# SMPS.net
KiCad netlist of a schematic drawn in Altium Designer
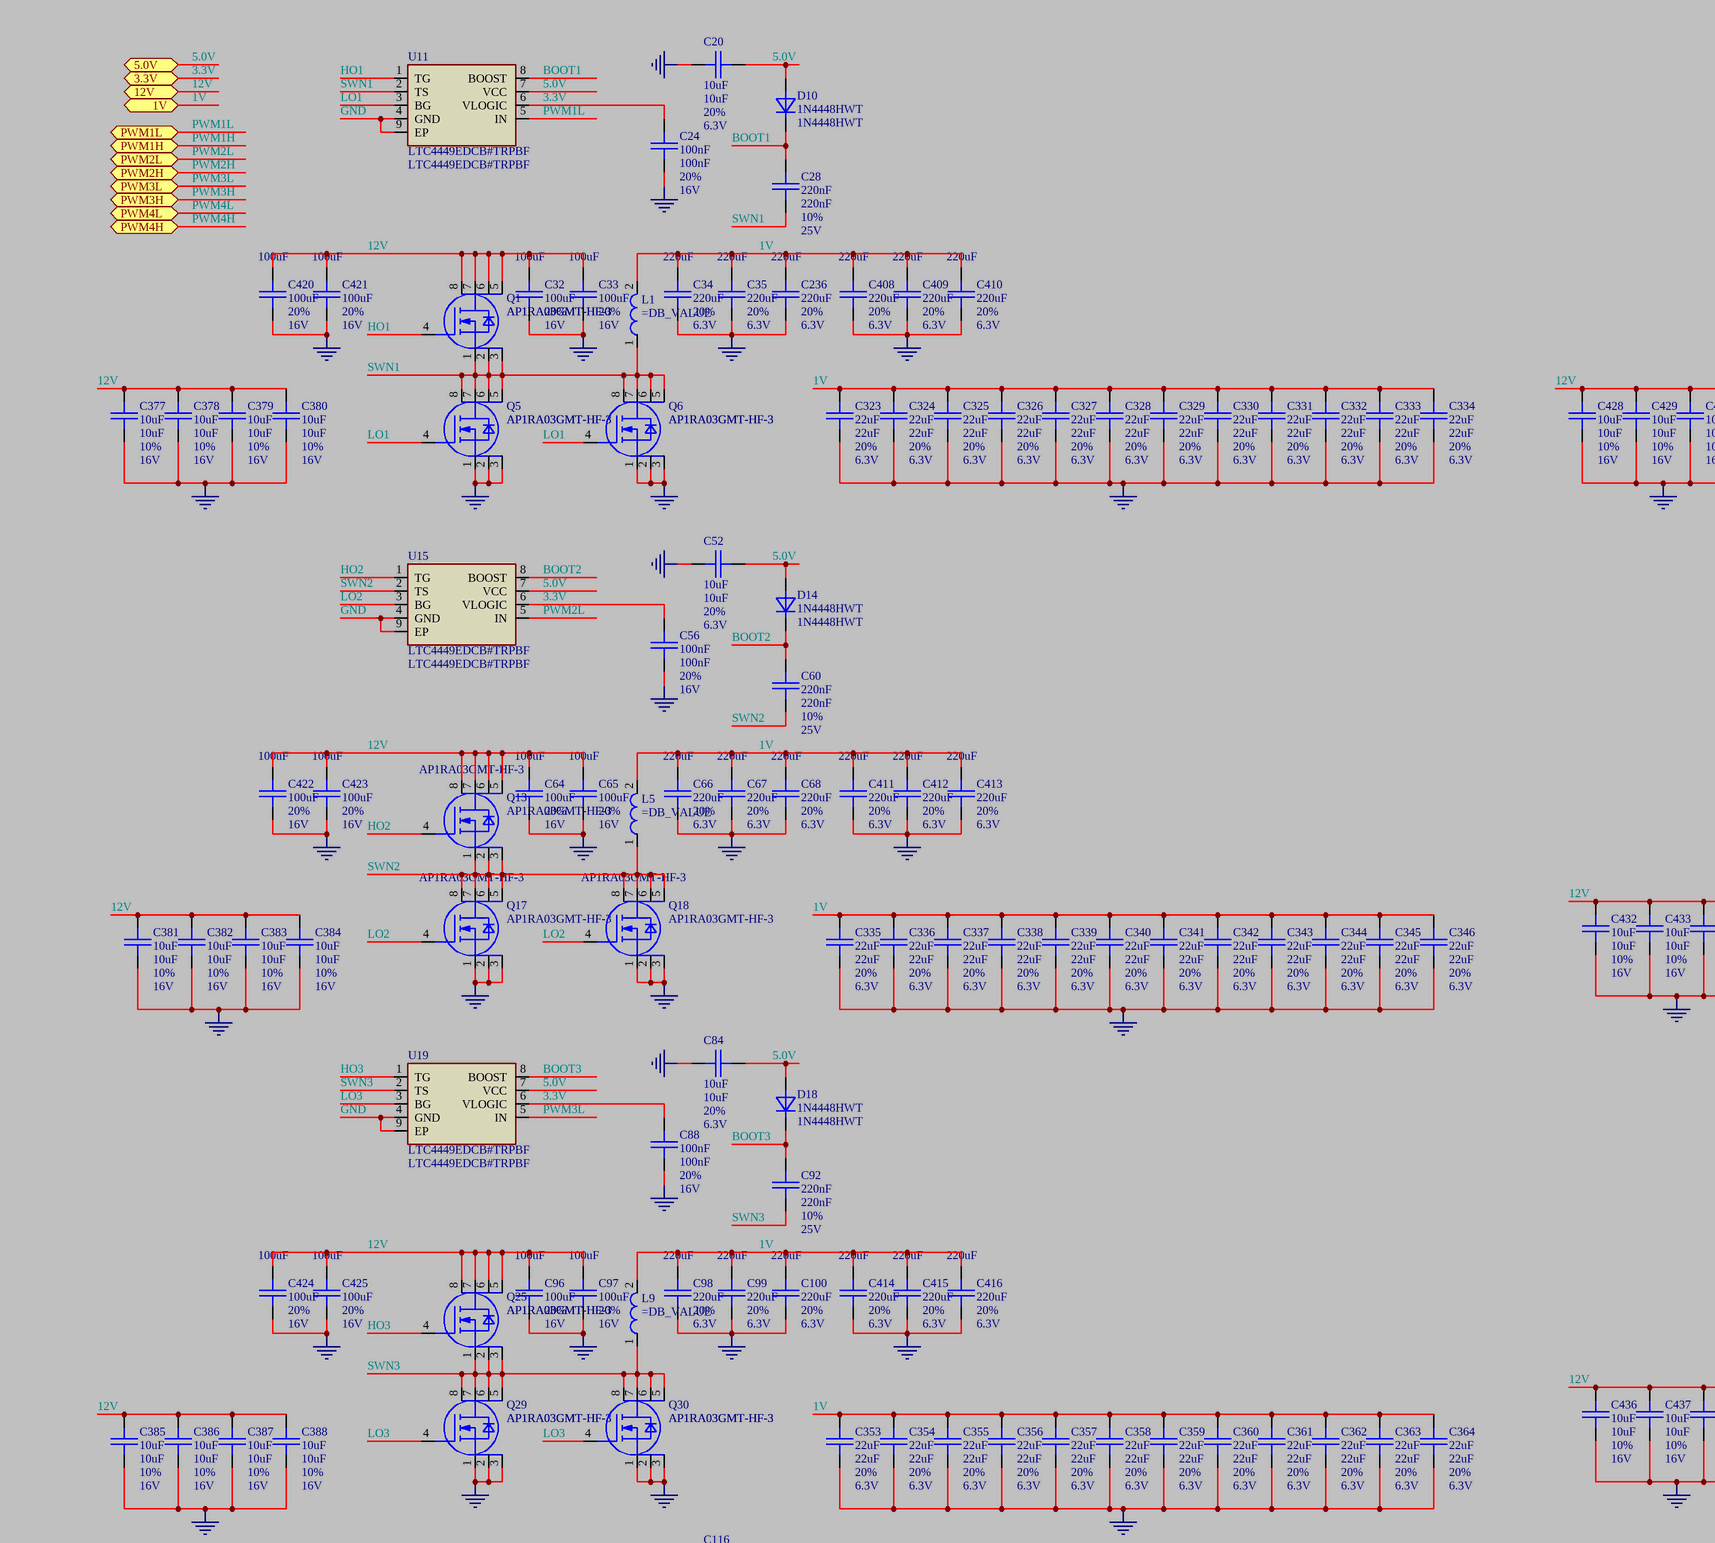
[diagram p0: SMPS.SchDoc, top left]
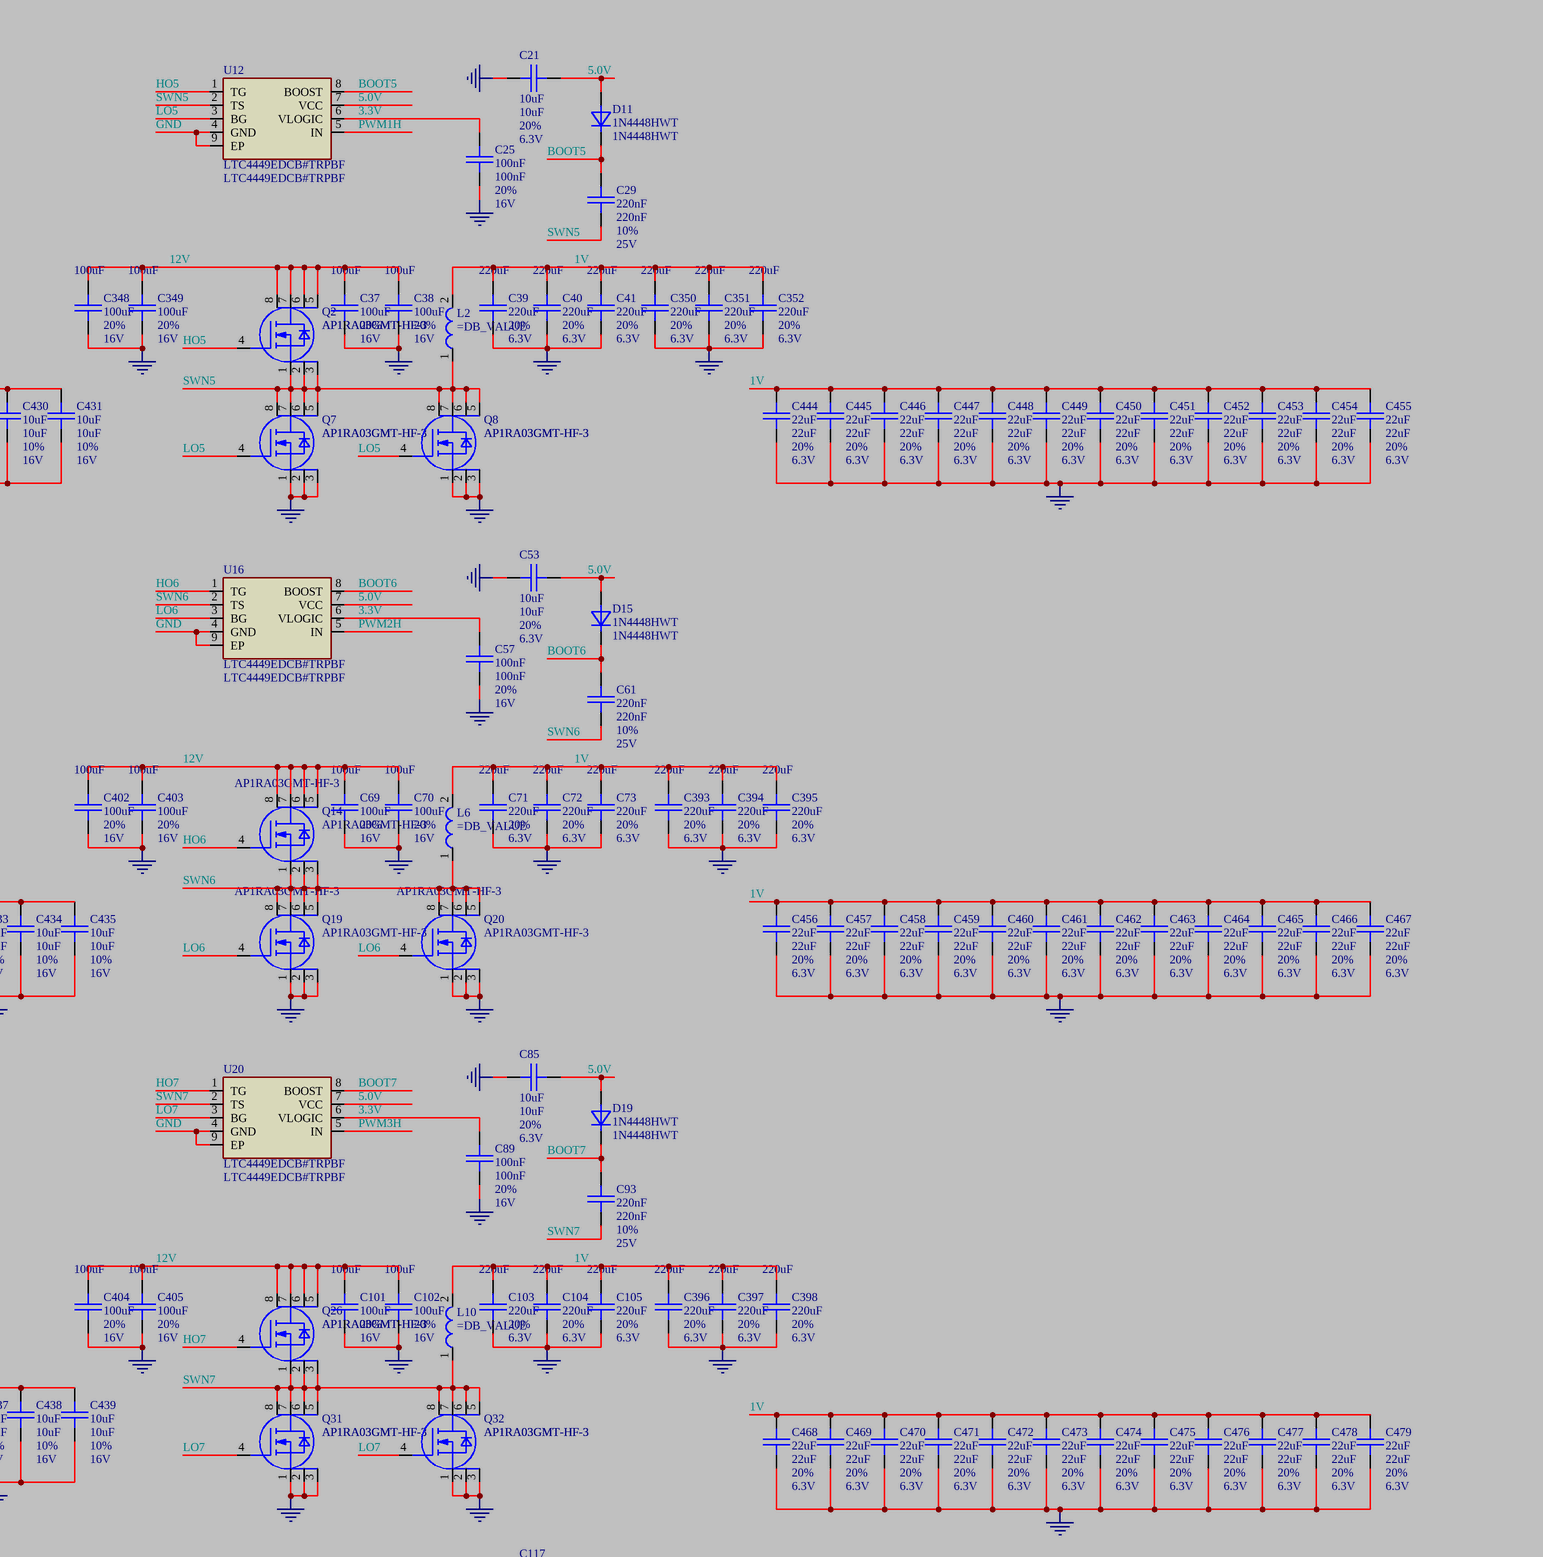
[diagram p1: SMPS.SchDoc, top right]
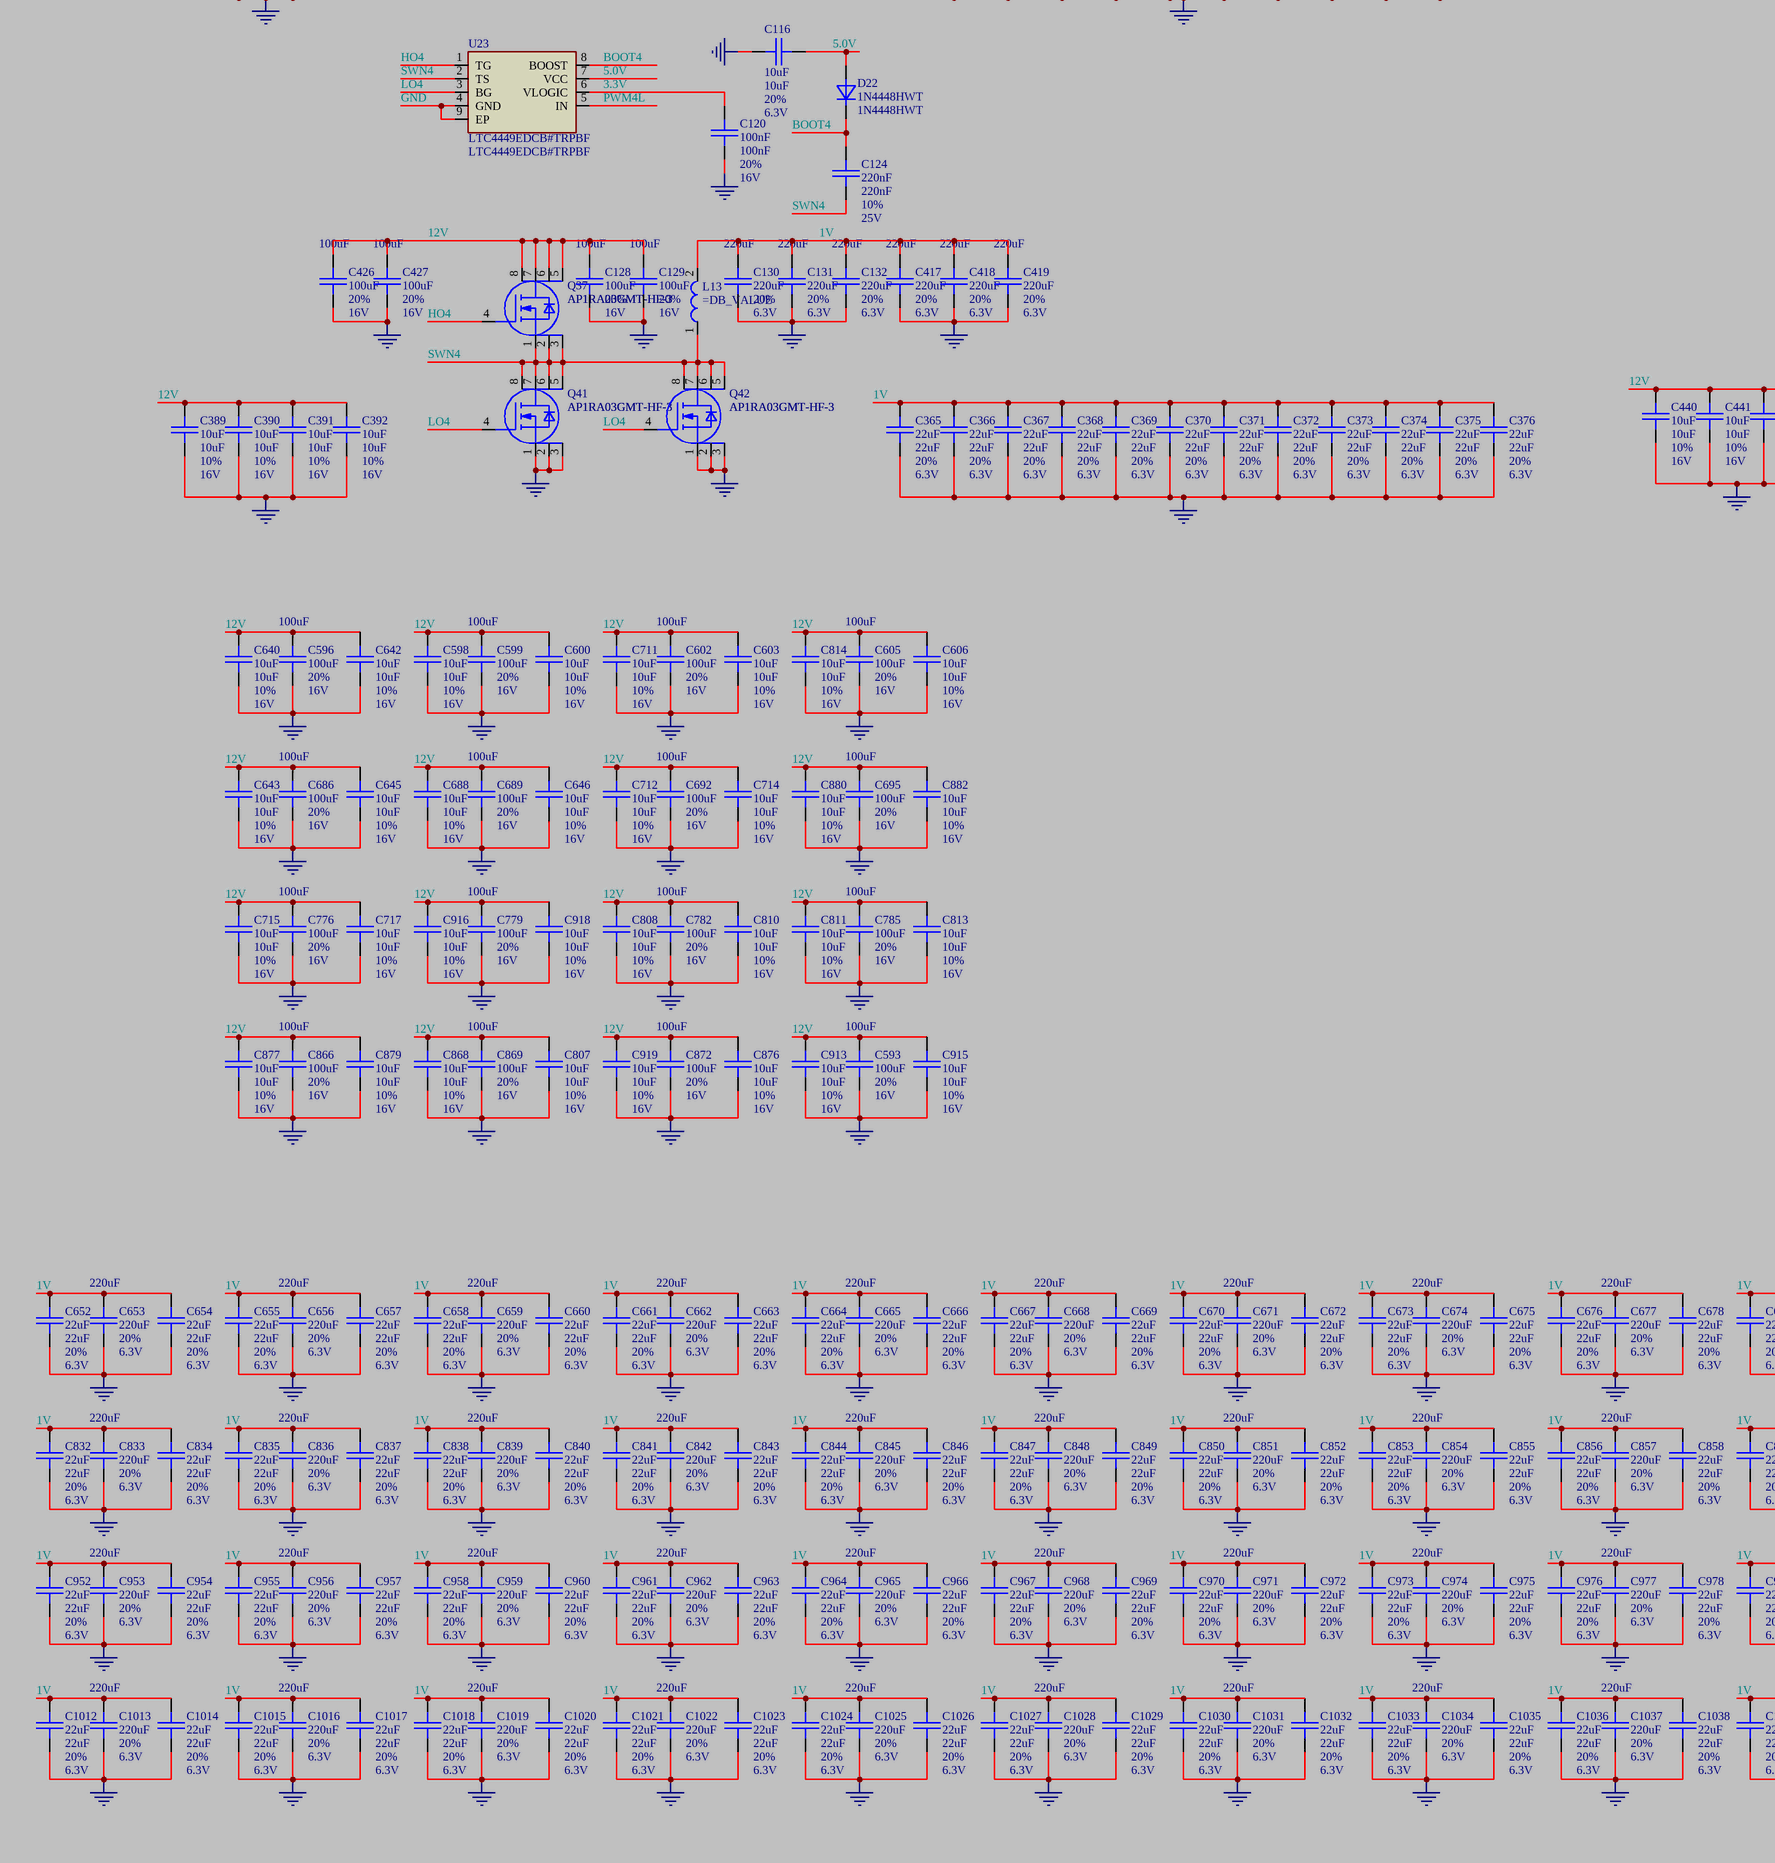
[diagram p2: SMPS.SchDoc, bottom left]
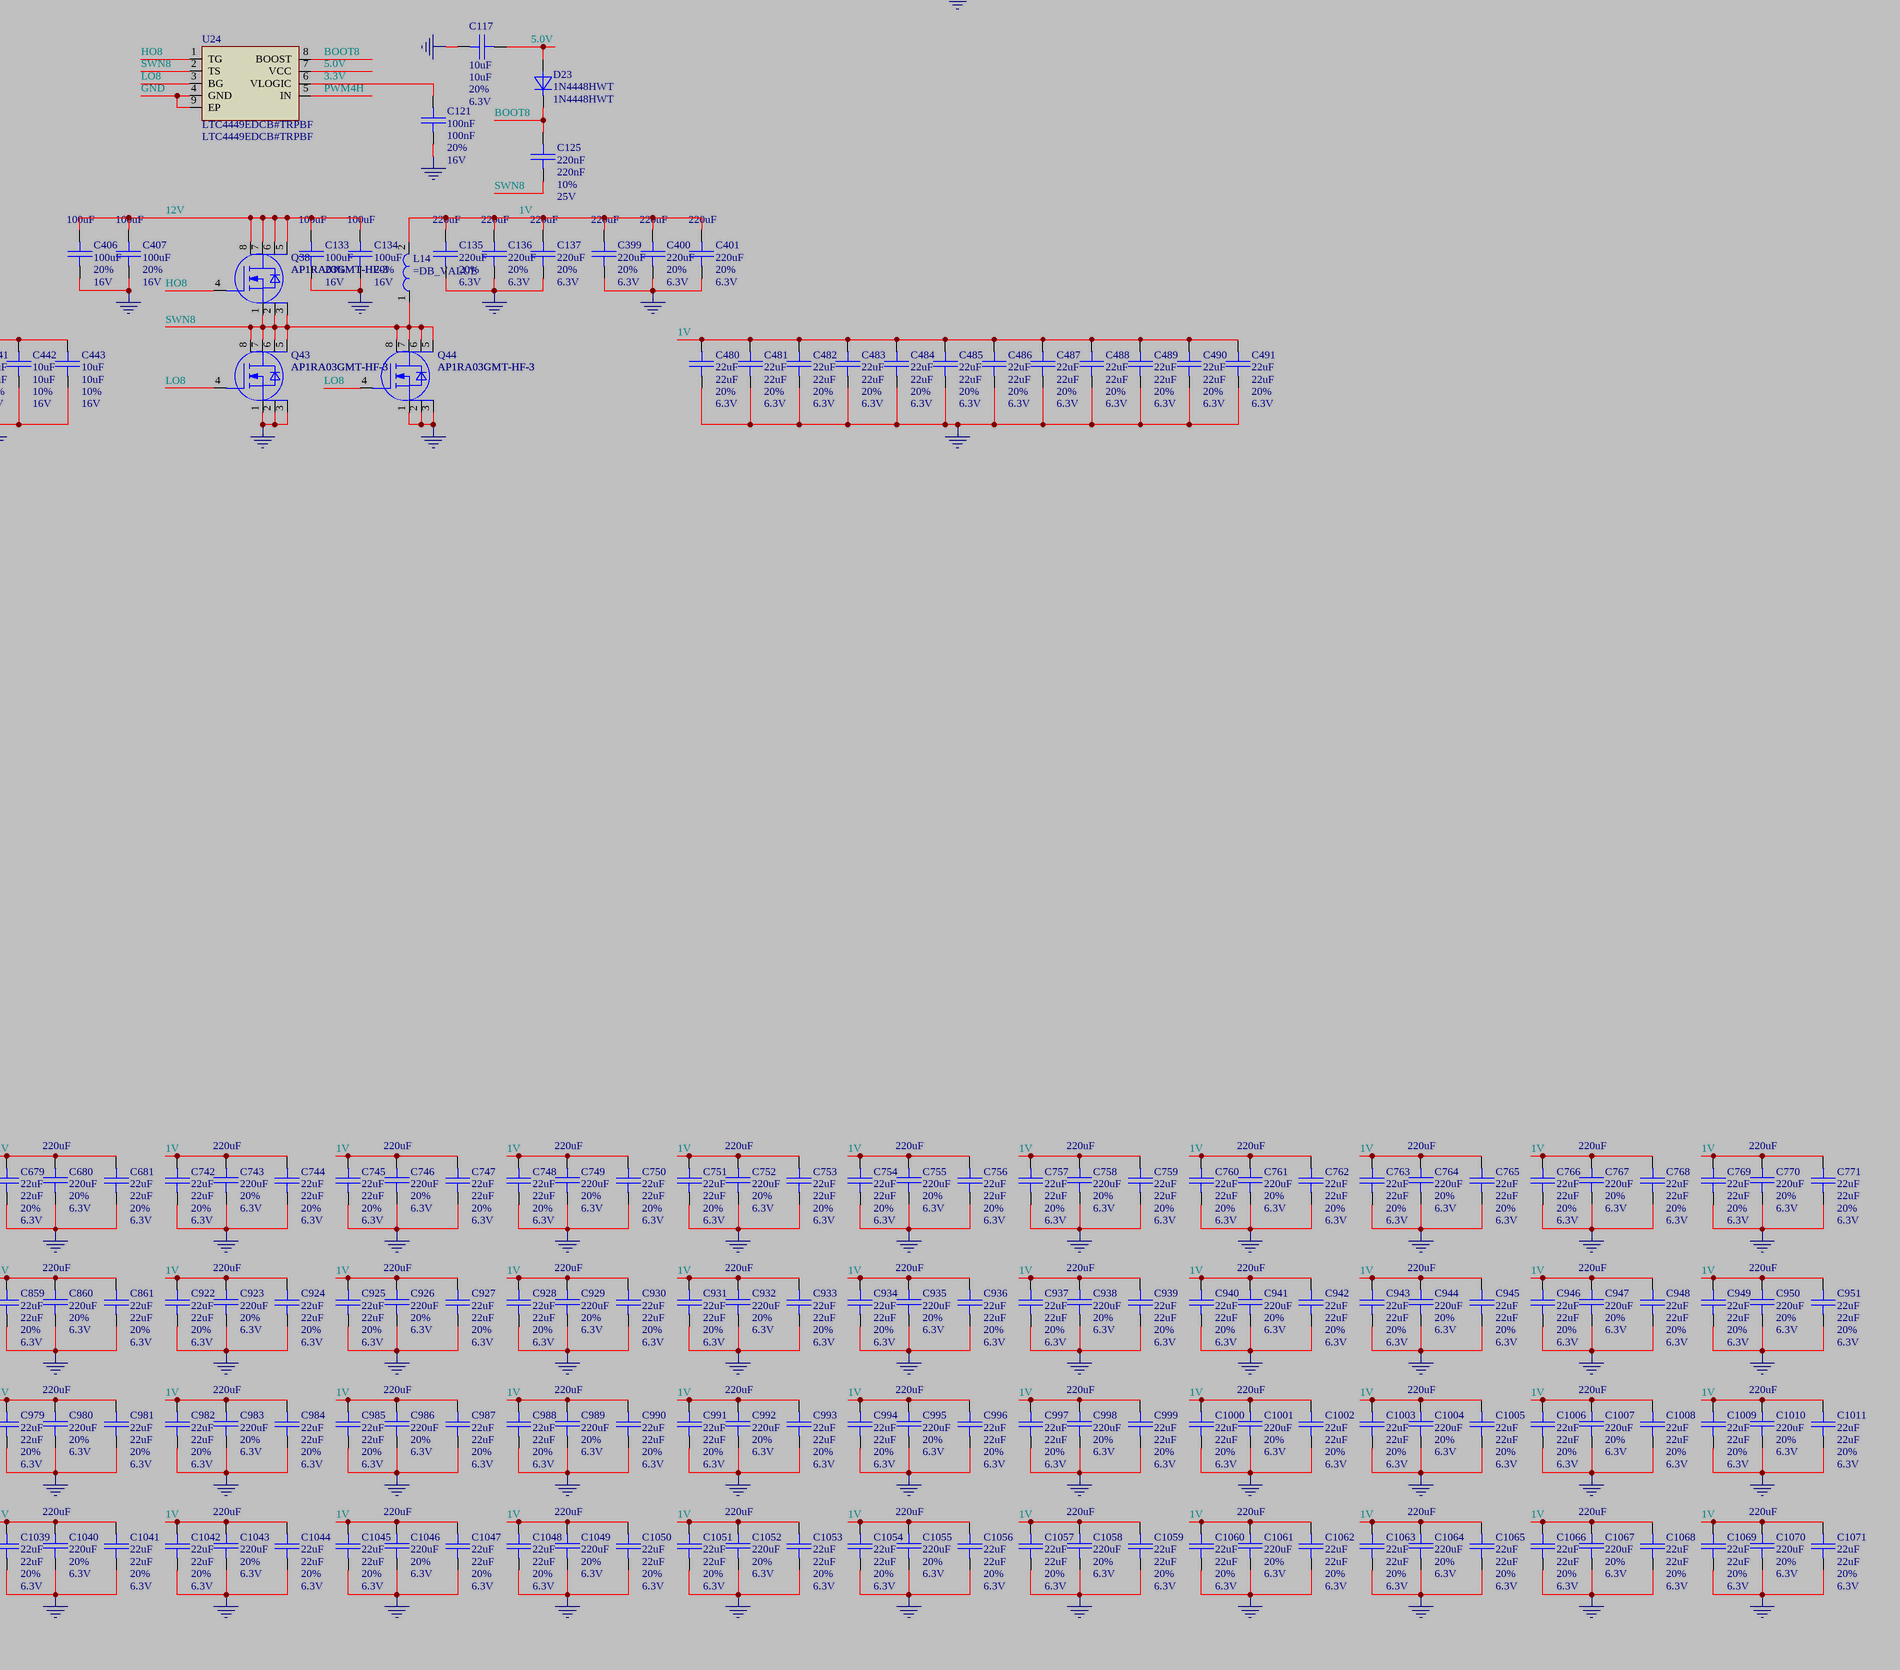
[diagram p3: SMPS.SchDoc, bottom right]

(export (version "E")
  (design (tool "Eeschema 10.0.6"))
  (components
    (comp (ref "C20")
      (value "10uF")
      (footprint "SMD_0603_CAPC1608X95N")
      (fields
        (field (name "DB_PART_NUMBER") "CAP000043646")
        (field (name "DB_VALUE") "10uF")
        (field (name "DB_TOLERANCE") "20%")
        (field (name "DB_VOLTAGE") "6.3V")
        (field (name "DB_MANUFACTURER_PART") "KEMET    C0603C106M9PAC")
        (field (name "DB_APPROVED_BY") "ISHIDDEN=T")
      )
      (libsource (lib "Database_Libs1") (part "C"))
    )
    (comp (ref "C21")
      (value "10uF")
      (footprint "SMD_0603_CAPC1608X95N")
      (fields
        (field (name "DB_PART_NUMBER") "CAP000043646")
        (field (name "DB_VALUE") "10uF")
        (field (name "DB_TOLERANCE") "20%")
        (field (name "DB_VOLTAGE") "6.3V")
        (field (name "DB_MANUFACTURER_PART") "KEMET    C0603C106M9PAC")
        (field (name "DB_APPROVED_BY") "ISHIDDEN=T")
      )
      (libsource (lib "Database_Libs1") (part "C"))
    )
    (comp (ref "C24")
      (value "100nF")
      (footprint "SMD_0402_CAPC1005X55N")
      (fields
        (field (name "DB_PART_NUMBER") "CAP000022751")
        (field (name "DB_VALUE") "100nF")
        (field (name "DB_TOLERANCE") "20%")
        (field (name "DB_VOLTAGE") "16V")
        (field (name "DB_MANUFACTURER_PART") "KEMET    C0402F104M4RAC")
        (field (name "DB_APPROVED_BY") "ISHIDDEN=T")
      )
      (libsource (lib "Database_Libs1") (part "C"))
    )
    (comp (ref "C25")
      (value "100nF")
      (footprint "SMD_0402_CAPC1005X55N")
      (fields
        (field (name "DB_PART_NUMBER") "CAP000022751")
        (field (name "DB_VALUE") "100nF")
        (field (name "DB_TOLERANCE") "20%")
        (field (name "DB_VOLTAGE") "16V")
        (field (name "DB_MANUFACTURER_PART") "KEMET    C0402F104M4RAC")
        (field (name "DB_APPROVED_BY") "ISHIDDEN=T")
      )
      (libsource (lib "Database_Libs1") (part "C"))
    )
    (comp (ref "C28")
      (value "220nF")
      (footprint "SMD_0603_CAPC1608X95N")
      (fields
        (field (name "DB_PART_NUMBER") "CAP000022968")
        (field (name "DB_VALUE") "220nF")
        (field (name "DB_TOLERANCE") "10%")
        (field (name "DB_VOLTAGE") "25V")
        (field (name "DB_MANUFACTURER_PART") "KEMET    C0603F224K3RAC")
        (field (name "DB_APPROVED_BY") "ISHIDDEN=T")
      )
      (libsource (lib "Database_Libs1") (part "C"))
    )
    (comp (ref "C29")
      (value "220nF")
      (footprint "SMD_0603_CAPC1608X95N")
      (fields
        (field (name "DB_PART_NUMBER") "CAP000022968")
        (field (name "DB_VALUE") "220nF")
        (field (name "DB_TOLERANCE") "10%")
        (field (name "DB_VOLTAGE") "25V")
        (field (name "DB_MANUFACTURER_PART") "KEMET    C0603F224K3RAC")
        (field (name "DB_APPROVED_BY") "ISHIDDEN=T")
      )
      (libsource (lib "Database_Libs1") (part "C"))
    )
    (comp (ref "C32")
      (value "100uF")
      (footprint "SMD_1210_CAPC3225X270N")
      (fields
        (field (name "DB_PART_NUMBER") "TMP-2512")
        (field (name "DB_VALUE") "100uF")
        (field (name "DB_TOLERANCE") "20%")
        (field (name "DB_VOLTAGE") "16V")
        (field (name "DB_MANUFACTURER_PART") "YAGEO    CC1210MRX5R7BB107")
      )
      (libsource (lib "Database_Libs1") (part "C"))
    )
    (comp (ref "C33")
      (value "100uF")
      (footprint "SMD_1210_CAPC3225X270N")
      (fields
        (field (name "DB_PART_NUMBER") "TMP-2512")
        (field (name "DB_VALUE") "100uF")
        (field (name "DB_TOLERANCE") "20%")
        (field (name "DB_VOLTAGE") "16V")
        (field (name "DB_MANUFACTURER_PART") "YAGEO    CC1210MRX5R7BB107")
      )
      (libsource (lib "Database_Libs1") (part "C"))
    )
    (comp (ref "C34")
      (value "220uF")
      (footprint "SMD_1210_CAPC3225X279N")
      (fields
        (field (name "DB_PART_NUMBER") "CAP000047355")
        (field (name "DB_VALUE") "220uF")
        (field (name "DB_TOLERANCE") "20%")
        (field (name "DB_VOLTAGE") "6.3V")
        (field (name "DB_MANUFACTURER_PART") "SAMSUNG    CL32A227MQVNNNE")
        (field (name "DB_APPROVED_BY") "VSN")
      )
      (libsource (lib "Database_Libs1") (part "C"))
    )
    (comp (ref "C35")
      (value "220uF")
      (footprint "SMD_1210_CAPC3225X279N")
      (fields
        (field (name "DB_PART_NUMBER") "CAP000047355")
        (field (name "DB_VALUE") "220uF")
        (field (name "DB_TOLERANCE") "20%")
        (field (name "DB_VOLTAGE") "6.3V")
        (field (name "DB_MANUFACTURER_PART") "SAMSUNG    CL32A227MQVNNNE")
        (field (name "DB_APPROVED_BY") "VSN")
      )
      (libsource (lib "Database_Libs1") (part "C"))
    )
    (comp (ref "C37")
      (value "100uF")
      (footprint "SMD_1210_CAPC3225X270N")
      (fields
        (field (name "DB_PART_NUMBER") "TMP-2512")
        (field (name "DB_VALUE") "100uF")
        (field (name "DB_TOLERANCE") "20%")
        (field (name "DB_VOLTAGE") "16V")
        (field (name "DB_MANUFACTURER_PART") "YAGEO    CC1210MRX5R7BB107")
      )
      (libsource (lib "Database_Libs1") (part "C"))
    )
    (comp (ref "C38")
      (value "100uF")
      (footprint "SMD_1210_CAPC3225X270N")
      (fields
        (field (name "DB_PART_NUMBER") "TMP-2512")
        (field (name "DB_VALUE") "100uF")
        (field (name "DB_TOLERANCE") "20%")
        (field (name "DB_VOLTAGE") "16V")
        (field (name "DB_MANUFACTURER_PART") "YAGEO    CC1210MRX5R7BB107")
      )
      (libsource (lib "Database_Libs1") (part "C"))
    )
    (comp (ref "C39")
      (value "220uF")
      (footprint "SMD_1210_CAPC3225X279N")
      (fields
        (field (name "DB_PART_NUMBER") "CAP000047355")
        (field (name "DB_VALUE") "220uF")
        (field (name "DB_TOLERANCE") "20%")
        (field (name "DB_VOLTAGE") "6.3V")
        (field (name "DB_MANUFACTURER_PART") "SAMSUNG    CL32A227MQVNNNE")
        (field (name "DB_APPROVED_BY") "VSN")
      )
      (libsource (lib "Database_Libs1") (part "C"))
    )
    (comp (ref "C40")
      (value "220uF")
      (footprint "SMD_1210_CAPC3225X279N")
      (fields
        (field (name "DB_PART_NUMBER") "CAP000047355")
        (field (name "DB_VALUE") "220uF")
        (field (name "DB_TOLERANCE") "20%")
        (field (name "DB_VOLTAGE") "6.3V")
        (field (name "DB_MANUFACTURER_PART") "SAMSUNG    CL32A227MQVNNNE")
        (field (name "DB_APPROVED_BY") "VSN")
      )
      (libsource (lib "Database_Libs1") (part "C"))
    )
    (comp (ref "C41")
      (value "220uF")
      (footprint "SMD_1210_CAPC3225X279N")
      (fields
        (field (name "DB_PART_NUMBER") "CAP000047355")
        (field (name "DB_VALUE") "220uF")
        (field (name "DB_TOLERANCE") "20%")
        (field (name "DB_VOLTAGE") "6.3V")
        (field (name "DB_MANUFACTURER_PART") "SAMSUNG    CL32A227MQVNNNE")
        (field (name "DB_APPROVED_BY") "VSN")
      )
      (libsource (lib "Database_Libs1") (part "C"))
    )
    (comp (ref "C52")
      (value "10uF")
      (footprint "SMD_0603_CAPC1608X95N")
      (fields
        (field (name "DB_PART_NUMBER") "CAP000043646")
        (field (name "DB_VALUE") "10uF")
        (field (name "DB_TOLERANCE") "20%")
        (field (name "DB_VOLTAGE") "6.3V")
        (field (name "DB_MANUFACTURER_PART") "KEMET    C0603C106M9PAC")
        (field (name "DB_APPROVED_BY") "ISHIDDEN=T")
      )
      (libsource (lib "Database_Libs1") (part "C"))
    )
    (comp (ref "C53")
      (value "10uF")
      (footprint "SMD_0603_CAPC1608X95N")
      (fields
        (field (name "DB_PART_NUMBER") "CAP000043646")
        (field (name "DB_VALUE") "10uF")
        (field (name "DB_TOLERANCE") "20%")
        (field (name "DB_VOLTAGE") "6.3V")
        (field (name "DB_MANUFACTURER_PART") "KEMET    C0603C106M9PAC")
        (field (name "DB_APPROVED_BY") "ISHIDDEN=T")
      )
      (libsource (lib "Database_Libs1") (part "C"))
    )
    (comp (ref "C56")
      (value "100nF")
      (footprint "SMD_0402_CAPC1005X55N")
      (fields
        (field (name "DB_PART_NUMBER") "CAP000022751")
        (field (name "DB_VALUE") "100nF")
        (field (name "DB_TOLERANCE") "20%")
        (field (name "DB_VOLTAGE") "16V")
        (field (name "DB_MANUFACTURER_PART") "KEMET    C0402F104M4RAC")
        (field (name "DB_APPROVED_BY") "ISHIDDEN=T")
      )
      (libsource (lib "Database_Libs1") (part "C"))
    )
    (comp (ref "C57")
      (value "100nF")
      (footprint "SMD_0402_CAPC1005X55N")
      (fields
        (field (name "DB_PART_NUMBER") "CAP000022751")
        (field (name "DB_VALUE") "100nF")
        (field (name "DB_TOLERANCE") "20%")
        (field (name "DB_VOLTAGE") "16V")
        (field (name "DB_MANUFACTURER_PART") "KEMET    C0402F104M4RAC")
        (field (name "DB_APPROVED_BY") "ISHIDDEN=T")
      )
      (libsource (lib "Database_Libs1") (part "C"))
    )
    (comp (ref "C60")
      (value "220nF")
      (footprint "SMD_0603_CAPC1608X95N")
      (fields
        (field (name "DB_PART_NUMBER") "CAP000022968")
        (field (name "DB_VALUE") "220nF")
        (field (name "DB_TOLERANCE") "10%")
        (field (name "DB_VOLTAGE") "25V")
        (field (name "DB_MANUFACTURER_PART") "KEMET    C0603F224K3RAC")
        (field (name "DB_APPROVED_BY") "ISHIDDEN=T")
      )
      (libsource (lib "Database_Libs1") (part "C"))
    )
    (comp (ref "C61")
      (value "220nF")
      (footprint "SMD_0603_CAPC1608X95N")
      (fields
        (field (name "DB_PART_NUMBER") "CAP000022968")
        (field (name "DB_VALUE") "220nF")
        (field (name "DB_TOLERANCE") "10%")
        (field (name "DB_VOLTAGE") "25V")
        (field (name "DB_MANUFACTURER_PART") "KEMET    C0603F224K3RAC")
        (field (name "DB_APPROVED_BY") "ISHIDDEN=T")
      )
      (libsource (lib "Database_Libs1") (part "C"))
    )
    (comp (ref "C64")
      (value "100uF")
      (footprint "SMD_1210_CAPC3225X270N")
      (fields
        (field (name "DB_PART_NUMBER") "TMP-2512")
        (field (name "DB_VALUE") "100uF")
        (field (name "DB_TOLERANCE") "20%")
        (field (name "DB_VOLTAGE") "16V")
        (field (name "DB_MANUFACTURER_PART") "YAGEO    CC1210MRX5R7BB107")
      )
      (libsource (lib "Database_Libs1") (part "C"))
    )
    (comp (ref "C65")
      (value "100uF")
      (footprint "SMD_1210_CAPC3225X270N")
      (fields
        (field (name "DB_PART_NUMBER") "TMP-2512")
        (field (name "DB_VALUE") "100uF")
        (field (name "DB_TOLERANCE") "20%")
        (field (name "DB_VOLTAGE") "16V")
        (field (name "DB_MANUFACTURER_PART") "YAGEO    CC1210MRX5R7BB107")
      )
      (libsource (lib "Database_Libs1") (part "C"))
    )
    (comp (ref "C66")
      (value "220uF")
      (footprint "SMD_1210_CAPC3225X279N")
      (fields
        (field (name "DB_PART_NUMBER") "CAP000047355")
        (field (name "DB_VALUE") "220uF")
        (field (name "DB_TOLERANCE") "20%")
        (field (name "DB_VOLTAGE") "6.3V")
        (field (name "DB_MANUFACTURER_PART") "SAMSUNG    CL32A227MQVNNNE")
        (field (name "DB_APPROVED_BY") "VSN")
      )
      (libsource (lib "Database_Libs1") (part "C"))
    )
    (comp (ref "C67")
      (value "220uF")
      (footprint "SMD_1210_CAPC3225X279N")
      (fields
        (field (name "DB_PART_NUMBER") "CAP000047355")
        (field (name "DB_VALUE") "220uF")
        (field (name "DB_TOLERANCE") "20%")
        (field (name "DB_VOLTAGE") "6.3V")
        (field (name "DB_MANUFACTURER_PART") "SAMSUNG    CL32A227MQVNNNE")
        (field (name "DB_APPROVED_BY") "VSN")
      )
      (libsource (lib "Database_Libs1") (part "C"))
    )
    (comp (ref "C68")
      (value "220uF")
      (footprint "SMD_1210_CAPC3225X279N")
      (fields
        (field (name "DB_PART_NUMBER") "CAP000047355")
        (field (name "DB_VALUE") "220uF")
        (field (name "DB_TOLERANCE") "20%")
        (field (name "DB_VOLTAGE") "6.3V")
        (field (name "DB_MANUFACTURER_PART") "SAMSUNG    CL32A227MQVNNNE")
        (field (name "DB_APPROVED_BY") "VSN")
      )
      (libsource (lib "Database_Libs1") (part "C"))
    )
    (comp (ref "C69")
      (value "100uF")
      (footprint "SMD_1210_CAPC3225X270N")
      (fields
        (field (name "DB_PART_NUMBER") "TMP-2512")
        (field (name "DB_VALUE") "100uF")
        (field (name "DB_TOLERANCE") "20%")
        (field (name "DB_VOLTAGE") "16V")
        (field (name "DB_MANUFACTURER_PART") "YAGEO    CC1210MRX5R7BB107")
      )
      (libsource (lib "Database_Libs1") (part "C"))
    )
    (comp (ref "C70")
      (value "100uF")
      (footprint "SMD_1210_CAPC3225X270N")
      (fields
        (field (name "DB_PART_NUMBER") "TMP-2512")
        (field (name "DB_VALUE") "100uF")
        (field (name "DB_TOLERANCE") "20%")
        (field (name "DB_VOLTAGE") "16V")
        (field (name "DB_MANUFACTURER_PART") "YAGEO    CC1210MRX5R7BB107")
      )
      (libsource (lib "Database_Libs1") (part "C"))
    )
    (comp (ref "C71")
      (value "220uF")
      (footprint "SMD_1210_CAPC3225X279N")
      (fields
        (field (name "DB_PART_NUMBER") "CAP000047355")
        (field (name "DB_VALUE") "220uF")
        (field (name "DB_TOLERANCE") "20%")
        (field (name "DB_VOLTAGE") "6.3V")
        (field (name "DB_MANUFACTURER_PART") "SAMSUNG    CL32A227MQVNNNE")
        (field (name "DB_APPROVED_BY") "VSN")
      )
      (libsource (lib "Database_Libs1") (part "C"))
    )
    (comp (ref "C72")
      (value "220uF")
      (footprint "SMD_1210_CAPC3225X279N")
      (fields
        (field (name "DB_PART_NUMBER") "CAP000047355")
        (field (name "DB_VALUE") "220uF")
        (field (name "DB_TOLERANCE") "20%")
        (field (name "DB_VOLTAGE") "6.3V")
        (field (name "DB_MANUFACTURER_PART") "SAMSUNG    CL32A227MQVNNNE")
        (field (name "DB_APPROVED_BY") "VSN")
      )
      (libsource (lib "Database_Libs1") (part "C"))
    )
    (comp (ref "C73")
      (value "220uF")
      (footprint "SMD_1210_CAPC3225X279N")
      (fields
        (field (name "DB_PART_NUMBER") "CAP000047355")
        (field (name "DB_VALUE") "220uF")
        (field (name "DB_TOLERANCE") "20%")
        (field (name "DB_VOLTAGE") "6.3V")
        (field (name "DB_MANUFACTURER_PART") "SAMSUNG    CL32A227MQVNNNE")
        (field (name "DB_APPROVED_BY") "VSN")
      )
      (libsource (lib "Database_Libs1") (part "C"))
    )
    (comp (ref "C84")
      (value "10uF")
      (footprint "SMD_0603_CAPC1608X95N")
      (fields
        (field (name "DB_PART_NUMBER") "CAP000043646")
        (field (name "DB_VALUE") "10uF")
        (field (name "DB_TOLERANCE") "20%")
        (field (name "DB_VOLTAGE") "6.3V")
        (field (name "DB_MANUFACTURER_PART") "KEMET    C0603C106M9PAC")
        (field (name "DB_APPROVED_BY") "ISHIDDEN=T")
      )
      (libsource (lib "Database_Libs1") (part "C"))
    )
    (comp (ref "C85")
      (value "10uF")
      (footprint "SMD_0603_CAPC1608X95N")
      (fields
        (field (name "DB_PART_NUMBER") "CAP000043646")
        (field (name "DB_VALUE") "10uF")
        (field (name "DB_TOLERANCE") "20%")
        (field (name "DB_VOLTAGE") "6.3V")
        (field (name "DB_MANUFACTURER_PART") "KEMET    C0603C106M9PAC")
        (field (name "DB_APPROVED_BY") "ISHIDDEN=T")
      )
      (libsource (lib "Database_Libs1") (part "C"))
    )
    (comp (ref "C88")
      (value "100nF")
      (footprint "SMD_0402_CAPC1005X55N")
      (fields
        (field (name "DB_PART_NUMBER") "CAP000022751")
        (field (name "DB_VALUE") "100nF")
        (field (name "DB_TOLERANCE") "20%")
        (field (name "DB_VOLTAGE") "16V")
        (field (name "DB_MANUFACTURER_PART") "KEMET    C0402F104M4RAC")
        (field (name "DB_APPROVED_BY") "ISHIDDEN=T")
      )
      (libsource (lib "Database_Libs1") (part "C"))
    )
    (comp (ref "C89")
      (value "100nF")
      (footprint "SMD_0402_CAPC1005X55N")
      (fields
        (field (name "DB_PART_NUMBER") "CAP000022751")
        (field (name "DB_VALUE") "100nF")
        (field (name "DB_TOLERANCE") "20%")
        (field (name "DB_VOLTAGE") "16V")
        (field (name "DB_MANUFACTURER_PART") "KEMET    C0402F104M4RAC")
        (field (name "DB_APPROVED_BY") "ISHIDDEN=T")
      )
      (libsource (lib "Database_Libs1") (part "C"))
    )
    (comp (ref "C92")
      (value "220nF")
      (footprint "SMD_0603_CAPC1608X95N")
      (fields
        (field (name "DB_PART_NUMBER") "CAP000022968")
        (field (name "DB_VALUE") "220nF")
        (field (name "DB_TOLERANCE") "10%")
        (field (name "DB_VOLTAGE") "25V")
        (field (name "DB_MANUFACTURER_PART") "KEMET    C0603F224K3RAC")
        (field (name "DB_APPROVED_BY") "ISHIDDEN=T")
      )
      (libsource (lib "Database_Libs1") (part "C"))
    )
    (comp (ref "C93")
      (value "220nF")
      (footprint "SMD_0603_CAPC1608X95N")
      (fields
        (field (name "DB_PART_NUMBER") "CAP000022968")
        (field (name "DB_VALUE") "220nF")
        (field (name "DB_TOLERANCE") "10%")
        (field (name "DB_VOLTAGE") "25V")
        (field (name "DB_MANUFACTURER_PART") "KEMET    C0603F224K3RAC")
        (field (name "DB_APPROVED_BY") "ISHIDDEN=T")
      )
      (libsource (lib "Database_Libs1") (part "C"))
    )
    (comp (ref "C96")
      (value "100uF")
      (footprint "SMD_1210_CAPC3225X270N")
      (fields
        (field (name "DB_PART_NUMBER") "TMP-2512")
        (field (name "DB_VALUE") "100uF")
        (field (name "DB_TOLERANCE") "20%")
        (field (name "DB_VOLTAGE") "16V")
        (field (name "DB_MANUFACTURER_PART") "YAGEO    CC1210MRX5R7BB107")
      )
      (libsource (lib "Database_Libs1") (part "C"))
    )
    (comp (ref "C97")
      (value "100uF")
      (footprint "SMD_1210_CAPC3225X270N")
      (fields
        (field (name "DB_PART_NUMBER") "TMP-2512")
        (field (name "DB_VALUE") "100uF")
        (field (name "DB_TOLERANCE") "20%")
        (field (name "DB_VOLTAGE") "16V")
        (field (name "DB_MANUFACTURER_PART") "YAGEO    CC1210MRX5R7BB107")
      )
      (libsource (lib "Database_Libs1") (part "C"))
    )
    (comp (ref "C98")
      (value "220uF")
      (footprint "SMD_1210_CAPC3225X279N")
      (fields
        (field (name "DB_PART_NUMBER") "CAP000047355")
        (field (name "DB_VALUE") "220uF")
        (field (name "DB_TOLERANCE") "20%")
        (field (name "DB_VOLTAGE") "6.3V")
        (field (name "DB_MANUFACTURER_PART") "SAMSUNG    CL32A227MQVNNNE")
        (field (name "DB_APPROVED_BY") "VSN")
      )
      (libsource (lib "Database_Libs1") (part "C"))
    )
    (comp (ref "C99")
      (value "220uF")
      (footprint "SMD_1210_CAPC3225X279N")
      (fields
        (field (name "DB_PART_NUMBER") "CAP000047355")
        (field (name "DB_VALUE") "220uF")
        (field (name "DB_TOLERANCE") "20%")
        (field (name "DB_VOLTAGE") "6.3V")
        (field (name "DB_MANUFACTURER_PART") "SAMSUNG    CL32A227MQVNNNE")
        (field (name "DB_APPROVED_BY") "VSN")
      )
      (libsource (lib "Database_Libs1") (part "C"))
    )
    (comp (ref "C100")
      (value "220uF")
      (footprint "SMD_1210_CAPC3225X279N")
      (fields
        (field (name "DB_PART_NUMBER") "CAP000047355")
        (field (name "DB_VALUE") "220uF")
        (field (name "DB_TOLERANCE") "20%")
        (field (name "DB_VOLTAGE") "6.3V")
        (field (name "DB_MANUFACTURER_PART") "SAMSUNG    CL32A227MQVNNNE")
        (field (name "DB_APPROVED_BY") "VSN")
      )
      (libsource (lib "Database_Libs1") (part "C"))
    )
    (comp (ref "C101")
      (value "100uF")
      (footprint "SMD_1210_CAPC3225X270N")
      (fields
        (field (name "DB_PART_NUMBER") "TMP-2512")
        (field (name "DB_VALUE") "100uF")
        (field (name "DB_TOLERANCE") "20%")
        (field (name "DB_VOLTAGE") "16V")
        (field (name "DB_MANUFACTURER_PART") "YAGEO    CC1210MRX5R7BB107")
      )
      (libsource (lib "Database_Libs1") (part "C"))
    )
    (comp (ref "C102")
      (value "100uF")
      (footprint "SMD_1210_CAPC3225X270N")
      (fields
        (field (name "DB_PART_NUMBER") "TMP-2512")
        (field (name "DB_VALUE") "100uF")
        (field (name "DB_TOLERANCE") "20%")
        (field (name "DB_VOLTAGE") "16V")
        (field (name "DB_MANUFACTURER_PART") "YAGEO    CC1210MRX5R7BB107")
      )
      (libsource (lib "Database_Libs1") (part "C"))
    )
    (comp (ref "C103")
      (value "220uF")
      (footprint "SMD_1210_CAPC3225X279N")
      (fields
        (field (name "DB_PART_NUMBER") "CAP000047355")
        (field (name "DB_VALUE") "220uF")
        (field (name "DB_TOLERANCE") "20%")
        (field (name "DB_VOLTAGE") "6.3V")
        (field (name "DB_MANUFACTURER_PART") "SAMSUNG    CL32A227MQVNNNE")
        (field (name "DB_APPROVED_BY") "VSN")
      )
      (libsource (lib "Database_Libs1") (part "C"))
    )
    (comp (ref "C104")
      (value "220uF")
      (footprint "SMD_1210_CAPC3225X279N")
      (fields
        (field (name "DB_PART_NUMBER") "CAP000047355")
        (field (name "DB_VALUE") "220uF")
        (field (name "DB_TOLERANCE") "20%")
        (field (name "DB_VOLTAGE") "6.3V")
        (field (name "DB_MANUFACTURER_PART") "SAMSUNG    CL32A227MQVNNNE")
        (field (name "DB_APPROVED_BY") "VSN")
      )
      (libsource (lib "Database_Libs1") (part "C"))
    )
    (comp (ref "C105")
      (value "220uF")
      (footprint "SMD_1210_CAPC3225X279N")
      (fields
        (field (name "DB_PART_NUMBER") "CAP000047355")
        (field (name "DB_VALUE") "220uF")
        (field (name "DB_TOLERANCE") "20%")
        (field (name "DB_VOLTAGE") "6.3V")
        (field (name "DB_MANUFACTURER_PART") "SAMSUNG    CL32A227MQVNNNE")
        (field (name "DB_APPROVED_BY") "VSN")
      )
      (libsource (lib "Database_Libs1") (part "C"))
    )
    (comp (ref "C116")
      (value "10uF")
      (footprint "SMD_0603_CAPC1608X95N")
      (fields
        (field (name "DB_PART_NUMBER") "CAP000043646")
        (field (name "DB_VALUE") "10uF")
        (field (name "DB_TOLERANCE") "20%")
        (field (name "DB_VOLTAGE") "6.3V")
        (field (name "DB_MANUFACTURER_PART") "KEMET    C0603C106M9PAC")
        (field (name "DB_APPROVED_BY") "ISHIDDEN=T")
      )
      (libsource (lib "Database_Libs1") (part "C"))
    )
    (comp (ref "C117")
      (value "10uF")
      (footprint "SMD_0603_CAPC1608X95N")
      (fields
        (field (name "DB_PART_NUMBER") "CAP000043646")
        (field (name "DB_VALUE") "10uF")
        (field (name "DB_TOLERANCE") "20%")
        (field (name "DB_VOLTAGE") "6.3V")
        (field (name "DB_MANUFACTURER_PART") "KEMET    C0603C106M9PAC")
        (field (name "DB_APPROVED_BY") "ISHIDDEN=T")
      )
      (libsource (lib "Database_Libs1") (part "C"))
    )
    (comp (ref "C120")
      (value "100nF")
      (footprint "SMD_0402_CAPC1005X55N")
      (fields
        (field (name "DB_PART_NUMBER") "CAP000022751")
        (field (name "DB_VALUE") "100nF")
        (field (name "DB_TOLERANCE") "20%")
        (field (name "DB_VOLTAGE") "16V")
        (field (name "DB_MANUFACTURER_PART") "KEMET    C0402F104M4RAC")
        (field (name "DB_APPROVED_BY") "ISHIDDEN=T")
      )
      (libsource (lib "Database_Libs1") (part "C"))
    )
    (comp (ref "C121")
      (value "100nF")
      (footprint "SMD_0402_CAPC1005X55N")
      (fields
        (field (name "DB_PART_NUMBER") "CAP000022751")
        (field (name "DB_VALUE") "100nF")
        (field (name "DB_TOLERANCE") "20%")
        (field (name "DB_VOLTAGE") "16V")
        (field (name "DB_MANUFACTURER_PART") "KEMET    C0402F104M4RAC")
        (field (name "DB_APPROVED_BY") "ISHIDDEN=T")
      )
      (libsource (lib "Database_Libs1") (part "C"))
    )
    (comp (ref "C124")
      (value "220nF")
      (footprint "SMD_0603_CAPC1608X95N")
      (fields
        (field (name "DB_PART_NUMBER") "CAP000022968")
        (field (name "DB_VALUE") "220nF")
        (field (name "DB_TOLERANCE") "10%")
        (field (name "DB_VOLTAGE") "25V")
        (field (name "DB_MANUFACTURER_PART") "KEMET    C0603F224K3RAC")
        (field (name "DB_APPROVED_BY") "ISHIDDEN=T")
      )
      (libsource (lib "Database_Libs1") (part "C"))
    )
    (comp (ref "C125")
      (value "220nF")
      (footprint "SMD_0603_CAPC1608X95N")
      (fields
        (field (name "DB_PART_NUMBER") "CAP000022968")
        (field (name "DB_VALUE") "220nF")
        (field (name "DB_TOLERANCE") "10%")
        (field (name "DB_VOLTAGE") "25V")
        (field (name "DB_MANUFACTURER_PART") "KEMET    C0603F224K3RAC")
        (field (name "DB_APPROVED_BY") "ISHIDDEN=T")
      )
      (libsource (lib "Database_Libs1") (part "C"))
    )
    (comp (ref "C128")
      (value "100uF")
      (footprint "SMD_1210_CAPC3225X270N")
      (fields
        (field (name "DB_PART_NUMBER") "TMP-2512")
        (field (name "DB_VALUE") "100uF")
        (field (name "DB_TOLERANCE") "20%")
        (field (name "DB_VOLTAGE") "16V")
        (field (name "DB_MANUFACTURER_PART") "YAGEO    CC1210MRX5R7BB107")
      )
      (libsource (lib "Database_Libs1") (part "C"))
    )
    (comp (ref "C129")
      (value "100uF")
      (footprint "SMD_1210_CAPC3225X270N")
      (fields
        (field (name "DB_PART_NUMBER") "TMP-2512")
        (field (name "DB_VALUE") "100uF")
        (field (name "DB_TOLERANCE") "20%")
        (field (name "DB_VOLTAGE") "16V")
        (field (name "DB_MANUFACTURER_PART") "YAGEO    CC1210MRX5R7BB107")
      )
      (libsource (lib "Database_Libs1") (part "C"))
    )
    (comp (ref "C130")
      (value "220uF")
      (footprint "SMD_1210_CAPC3225X279N")
      (fields
        (field (name "DB_PART_NUMBER") "CAP000047355")
        (field (name "DB_VALUE") "220uF")
        (field (name "DB_TOLERANCE") "20%")
        (field (name "DB_VOLTAGE") "6.3V")
        (field (name "DB_MANUFACTURER_PART") "SAMSUNG    CL32A227MQVNNNE")
        (field (name "DB_APPROVED_BY") "VSN")
      )
      (libsource (lib "Database_Libs1") (part "C"))
    )
    (comp (ref "C131")
      (value "220uF")
      (footprint "SMD_1210_CAPC3225X279N")
      (fields
        (field (name "DB_PART_NUMBER") "CAP000047355")
        (field (name "DB_VALUE") "220uF")
        (field (name "DB_TOLERANCE") "20%")
        (field (name "DB_VOLTAGE") "6.3V")
        (field (name "DB_MANUFACTURER_PART") "SAMSUNG    CL32A227MQVNNNE")
        (field (name "DB_APPROVED_BY") "VSN")
      )
      (libsource (lib "Database_Libs1") (part "C"))
    )
    (comp (ref "C132")
      (value "220uF")
      (footprint "SMD_1210_CAPC3225X279N")
      (fields
        (field (name "DB_PART_NUMBER") "CAP000047355")
        (field (name "DB_VALUE") "220uF")
        (field (name "DB_TOLERANCE") "20%")
        (field (name "DB_VOLTAGE") "6.3V")
        (field (name "DB_MANUFACTURER_PART") "SAMSUNG    CL32A227MQVNNNE")
        (field (name "DB_APPROVED_BY") "VSN")
      )
      (libsource (lib "Database_Libs1") (part "C"))
    )
    (comp (ref "C133")
      (value "100uF")
      (footprint "SMD_1210_CAPC3225X270N")
      (fields
        (field (name "DB_PART_NUMBER") "TMP-2512")
        (field (name "DB_VALUE") "100uF")
        (field (name "DB_TOLERANCE") "20%")
        (field (name "DB_VOLTAGE") "16V")
        (field (name "DB_MANUFACTURER_PART") "YAGEO    CC1210MRX5R7BB107")
      )
      (libsource (lib "Database_Libs1") (part "C"))
    )
    (comp (ref "C134")
      (value "100uF")
      (footprint "SMD_1210_CAPC3225X270N")
      (fields
        (field (name "DB_PART_NUMBER") "TMP-2512")
        (field (name "DB_VALUE") "100uF")
        (field (name "DB_TOLERANCE") "20%")
        (field (name "DB_VOLTAGE") "16V")
        (field (name "DB_MANUFACTURER_PART") "YAGEO    CC1210MRX5R7BB107")
      )
      (libsource (lib "Database_Libs1") (part "C"))
    )
    (comp (ref "C135")
      (value "220uF")
      (footprint "SMD_1210_CAPC3225X279N")
      (fields
        (field (name "DB_PART_NUMBER") "CAP000047355")
        (field (name "DB_VALUE") "220uF")
        (field (name "DB_TOLERANCE") "20%")
        (field (name "DB_VOLTAGE") "6.3V")
        (field (name "DB_MANUFACTURER_PART") "SAMSUNG    CL32A227MQVNNNE")
        (field (name "DB_APPROVED_BY") "VSN")
      )
      (libsource (lib "Database_Libs1") (part "C"))
    )
    (comp (ref "C136")
      (value "220uF")
      (footprint "SMD_1210_CAPC3225X279N")
      (fields
        (field (name "DB_PART_NUMBER") "CAP000047355")
        (field (name "DB_VALUE") "220uF")
        (field (name "DB_TOLERANCE") "20%")
        (field (name "DB_VOLTAGE") "6.3V")
        (field (name "DB_MANUFACTURER_PART") "SAMSUNG    CL32A227MQVNNNE")
        (field (name "DB_APPROVED_BY") "VSN")
      )
      (libsource (lib "Database_Libs1") (part "C"))
    )
    (comp (ref "C137")
      (value "220uF")
      (footprint "SMD_1210_CAPC3225X279N")
      (fields
        (field (name "DB_PART_NUMBER") "CAP000047355")
        (field (name "DB_VALUE") "220uF")
        (field (name "DB_TOLERANCE") "20%")
        (field (name "DB_VOLTAGE") "6.3V")
        (field (name "DB_MANUFACTURER_PART") "SAMSUNG    CL32A227MQVNNNE")
        (field (name "DB_APPROVED_BY") "VSN")
      )
      (libsource (lib "Database_Libs1") (part "C"))
    )
    (comp (ref "C236")
      (value "220uF")
      (footprint "SMD_1210_CAPC3225X279N")
      (fields
        (field (name "DB_PART_NUMBER") "CAP000047355")
        (field (name "DB_VALUE") "220uF")
        (field (name "DB_TOLERANCE") "20%")
        (field (name "DB_VOLTAGE") "6.3V")
        (field (name "DB_MANUFACTURER_PART") "SAMSUNG    CL32A227MQVNNNE")
        (field (name "DB_APPROVED_BY") "VSN")
      )
      (libsource (lib "Database_Libs1") (part "C"))
    )
    (comp (ref "C323")
      (value "22uF")
      (footprint "SMD_0805_CAPC2012X145N")
      (fields
        (field (name "DB_PART_NUMBER") "CAP000043686")
        (field (name "DB_VALUE") "22uF")
        (field (name "DB_TOLERANCE") "20%")
        (field (name "DB_VOLTAGE") "6.3V")
        (field (name "DB_MANUFACTURER_PART") "KEMET    C0805C226M9PAC")
        (field (name "DB_APPROVED_BY") "ISHIDDEN=T")
      )
      (libsource (lib "Database_Libs1") (part "C"))
    )
    (comp (ref "C324")
      (value "22uF")
      (footprint "SMD_0805_CAPC2012X145N")
      (fields
        (field (name "DB_PART_NUMBER") "CAP000043686")
        (field (name "DB_VALUE") "22uF")
        (field (name "DB_TOLERANCE") "20%")
        (field (name "DB_VOLTAGE") "6.3V")
        (field (name "DB_MANUFACTURER_PART") "KEMET    C0805C226M9PAC")
        (field (name "DB_APPROVED_BY") "ISHIDDEN=T")
      )
      (libsource (lib "Database_Libs1") (part "C"))
    )
    (comp (ref "C325")
      (value "22uF")
      (footprint "SMD_0805_CAPC2012X145N")
      (fields
        (field (name "DB_PART_NUMBER") "CAP000043686")
        (field (name "DB_VALUE") "22uF")
        (field (name "DB_TOLERANCE") "20%")
        (field (name "DB_VOLTAGE") "6.3V")
        (field (name "DB_MANUFACTURER_PART") "KEMET    C0805C226M9PAC")
        (field (name "DB_APPROVED_BY") "ISHIDDEN=T")
      )
      (libsource (lib "Database_Libs1") (part "C"))
    )
    (comp (ref "C326")
      (value "22uF")
      (footprint "SMD_0805_CAPC2012X145N")
      (fields
        (field (name "DB_PART_NUMBER") "CAP000043686")
        (field (name "DB_VALUE") "22uF")
        (field (name "DB_TOLERANCE") "20%")
        (field (name "DB_VOLTAGE") "6.3V")
        (field (name "DB_MANUFACTURER_PART") "KEMET    C0805C226M9PAC")
        (field (name "DB_APPROVED_BY") "ISHIDDEN=T")
      )
      (libsource (lib "Database_Libs1") (part "C"))
    )
    (comp (ref "C327")
      (value "22uF")
      (footprint "SMD_0805_CAPC2012X145N")
      (fields
        (field (name "DB_PART_NUMBER") "CAP000043686")
        (field (name "DB_VALUE") "22uF")
        (field (name "DB_TOLERANCE") "20%")
        (field (name "DB_VOLTAGE") "6.3V")
        (field (name "DB_MANUFACTURER_PART") "KEMET    C0805C226M9PAC")
        (field (name "DB_APPROVED_BY") "ISHIDDEN=T")
      )
      (libsource (lib "Database_Libs1") (part "C"))
    )
    (comp (ref "C328")
      (value "22uF")
      (footprint "SMD_0805_CAPC2012X145N")
      (fields
        (field (name "DB_PART_NUMBER") "CAP000043686")
        (field (name "DB_VALUE") "22uF")
        (field (name "DB_TOLERANCE") "20%")
        (field (name "DB_VOLTAGE") "6.3V")
        (field (name "DB_MANUFACTURER_PART") "KEMET    C0805C226M9PAC")
        (field (name "DB_APPROVED_BY") "ISHIDDEN=T")
      )
      (libsource (lib "Database_Libs1") (part "C"))
    )
    (comp (ref "C329")
      (value "22uF")
      (footprint "SMD_0805_CAPC2012X145N")
      (fields
        (field (name "DB_PART_NUMBER") "CAP000043686")
        (field (name "DB_VALUE") "22uF")
        (field (name "DB_TOLERANCE") "20%")
        (field (name "DB_VOLTAGE") "6.3V")
        (field (name "DB_MANUFACTURER_PART") "KEMET    C0805C226M9PAC")
        (field (name "DB_APPROVED_BY") "ISHIDDEN=T")
      )
      (libsource (lib "Database_Libs1") (part "C"))
    )
    (comp (ref "C330")
      (value "22uF")
      (footprint "SMD_0805_CAPC2012X145N")
      (fields
        (field (name "DB_PART_NUMBER") "CAP000043686")
        (field (name "DB_VALUE") "22uF")
        (field (name "DB_TOLERANCE") "20%")
        (field (name "DB_VOLTAGE") "6.3V")
        (field (name "DB_MANUFACTURER_PART") "KEMET    C0805C226M9PAC")
        (field (name "DB_APPROVED_BY") "ISHIDDEN=T")
      )
      (libsource (lib "Database_Libs1") (part "C"))
    )
    (comp (ref "C331")
      (value "22uF")
      (footprint "SMD_0805_CAPC2012X145N")
      (fields
        (field (name "DB_PART_NUMBER") "CAP000043686")
        (field (name "DB_VALUE") "22uF")
        (field (name "DB_TOLERANCE") "20%")
        (field (name "DB_VOLTAGE") "6.3V")
        (field (name "DB_MANUFACTURER_PART") "KEMET    C0805C226M9PAC")
        (field (name "DB_APPROVED_BY") "ISHIDDEN=T")
      )
      (libsource (lib "Database_Libs1") (part "C"))
    )
    (comp (ref "C332")
      (value "22uF")
      (footprint "SMD_0805_CAPC2012X145N")
      (fields
        (field (name "DB_PART_NUMBER") "CAP000043686")
        (field (name "DB_VALUE") "22uF")
        (field (name "DB_TOLERANCE") "20%")
        (field (name "DB_VOLTAGE") "6.3V")
        (field (name "DB_MANUFACTURER_PART") "KEMET    C0805C226M9PAC")
        (field (name "DB_APPROVED_BY") "ISHIDDEN=T")
      )
      (libsource (lib "Database_Libs1") (part "C"))
    )
    (comp (ref "C333")
      (value "22uF")
      (footprint "SMD_0805_CAPC2012X145N")
      (fields
        (field (name "DB_PART_NUMBER") "CAP000043686")
        (field (name "DB_VALUE") "22uF")
        (field (name "DB_TOLERANCE") "20%")
        (field (name "DB_VOLTAGE") "6.3V")
        (field (name "DB_MANUFACTURER_PART") "KEMET    C0805C226M9PAC")
        (field (name "DB_APPROVED_BY") "ISHIDDEN=T")
      )
      (libsource (lib "Database_Libs1") (part "C"))
    )
    (comp (ref "C334")
      (value "22uF")
      (footprint "SMD_0805_CAPC2012X145N")
      (fields
        (field (name "DB_PART_NUMBER") "CAP000043686")
        (field (name "DB_VALUE") "22uF")
        (field (name "DB_TOLERANCE") "20%")
        (field (name "DB_VOLTAGE") "6.3V")
        (field (name "DB_MANUFACTURER_PART") "KEMET    C0805C226M9PAC")
        (field (name "DB_APPROVED_BY") "ISHIDDEN=T")
      )
      (libsource (lib "Database_Libs1") (part "C"))
    )
    (comp (ref "C335")
      (value "22uF")
      (footprint "SMD_0805_CAPC2012X145N")
      (fields
        (field (name "DB_PART_NUMBER") "CAP000043686")
        (field (name "DB_VALUE") "22uF")
        (field (name "DB_TOLERANCE") "20%")
        (field (name "DB_VOLTAGE") "6.3V")
        (field (name "DB_MANUFACTURER_PART") "KEMET    C0805C226M9PAC")
        (field (name "DB_APPROVED_BY") "ISHIDDEN=T")
      )
      (libsource (lib "Database_Libs1") (part "C"))
    )
    (comp (ref "C336")
      (value "22uF")
      (footprint "SMD_0805_CAPC2012X145N")
      (fields
        (field (name "DB_PART_NUMBER") "CAP000043686")
        (field (name "DB_VALUE") "22uF")
        (field (name "DB_TOLERANCE") "20%")
        (field (name "DB_VOLTAGE") "6.3V")
        (field (name "DB_MANUFACTURER_PART") "KEMET    C0805C226M9PAC")
        (field (name "DB_APPROVED_BY") "ISHIDDEN=T")
      )
      (libsource (lib "Database_Libs1") (part "C"))
    )
    (comp (ref "C337")
      (value "22uF")
      (footprint "SMD_0805_CAPC2012X145N")
      (fields
        (field (name "DB_PART_NUMBER") "CAP000043686")
        (field (name "DB_VALUE") "22uF")
        (field (name "DB_TOLERANCE") "20%")
        (field (name "DB_VOLTAGE") "6.3V")
        (field (name "DB_MANUFACTURER_PART") "KEMET    C0805C226M9PAC")
        (field (name "DB_APPROVED_BY") "ISHIDDEN=T")
      )
      (libsource (lib "Database_Libs1") (part "C"))
    )
    (comp (ref "C338")
      (value "22uF")
      (footprint "SMD_0805_CAPC2012X145N")
      (fields
        (field (name "DB_PART_NUMBER") "CAP000043686")
        (field (name "DB_VALUE") "22uF")
        (field (name "DB_TOLERANCE") "20%")
        (field (name "DB_VOLTAGE") "6.3V")
        (field (name "DB_MANUFACTURER_PART") "KEMET    C0805C226M9PAC")
        (field (name "DB_APPROVED_BY") "ISHIDDEN=T")
      )
      (libsource (lib "Database_Libs1") (part "C"))
    )
    (comp (ref "C339")
      (value "22uF")
      (footprint "SMD_0805_CAPC2012X145N")
      (fields
        (field (name "DB_PART_NUMBER") "CAP000043686")
        (field (name "DB_VALUE") "22uF")
        (field (name "DB_TOLERANCE") "20%")
        (field (name "DB_VOLTAGE") "6.3V")
        (field (name "DB_MANUFACTURER_PART") "KEMET    C0805C226M9PAC")
        (field (name "DB_APPROVED_BY") "ISHIDDEN=T")
      )
      (libsource (lib "Database_Libs1") (part "C"))
    )
    (comp (ref "C340")
      (value "22uF")
      (footprint "SMD_0805_CAPC2012X145N")
      (fields
        (field (name "DB_PART_NUMBER") "CAP000043686")
        (field (name "DB_VALUE") "22uF")
        (field (name "DB_TOLERANCE") "20%")
        (field (name "DB_VOLTAGE") "6.3V")
        (field (name "DB_MANUFACTURER_PART") "KEMET    C0805C226M9PAC")
        (field (name "DB_APPROVED_BY") "ISHIDDEN=T")
      )
      (libsource (lib "Database_Libs1") (part "C"))
    )
    (comp (ref "C341")
      (value "22uF")
      (footprint "SMD_0805_CAPC2012X145N")
      (fields
        (field (name "DB_PART_NUMBER") "CAP000043686")
        (field (name "DB_VALUE") "22uF")
        (field (name "DB_TOLERANCE") "20%")
        (field (name "DB_VOLTAGE") "6.3V")
        (field (name "DB_MANUFACTURER_PART") "KEMET    C0805C226M9PAC")
        (field (name "DB_APPROVED_BY") "ISHIDDEN=T")
      )
      (libsource (lib "Database_Libs1") (part "C"))
    )
    (comp (ref "C342")
      (value "22uF")
      (footprint "SMD_0805_CAPC2012X145N")
      (fields
        (field (name "DB_PART_NUMBER") "CAP000043686")
        (field (name "DB_VALUE") "22uF")
        (field (name "DB_TOLERANCE") "20%")
        (field (name "DB_VOLTAGE") "6.3V")
        (field (name "DB_MANUFACTURER_PART") "KEMET    C0805C226M9PAC")
        (field (name "DB_APPROVED_BY") "ISHIDDEN=T")
      )
      (libsource (lib "Database_Libs1") (part "C"))
    )
    (comp (ref "C343")
      (value "22uF")
      (footprint "SMD_0805_CAPC2012X145N")
      (fields
        (field (name "DB_PART_NUMBER") "CAP000043686")
        (field (name "DB_VALUE") "22uF")
        (field (name "DB_TOLERANCE") "20%")
        (field (name "DB_VOLTAGE") "6.3V")
        (field (name "DB_MANUFACTURER_PART") "KEMET    C0805C226M9PAC")
        (field (name "DB_APPROVED_BY") "ISHIDDEN=T")
      )
      (libsource (lib "Database_Libs1") (part "C"))
    )
    (comp (ref "C344")
      (value "22uF")
      (footprint "SMD_0805_CAPC2012X145N")
      (fields
        (field (name "DB_PART_NUMBER") "CAP000043686")
        (field (name "DB_VALUE") "22uF")
        (field (name "DB_TOLERANCE") "20%")
        (field (name "DB_VOLTAGE") "6.3V")
        (field (name "DB_MANUFACTURER_PART") "KEMET    C0805C226M9PAC")
        (field (name "DB_APPROVED_BY") "ISHIDDEN=T")
      )
      (libsource (lib "Database_Libs1") (part "C"))
    )
    (comp (ref "C345")
      (value "22uF")
      (footprint "SMD_0805_CAPC2012X145N")
      (fields
        (field (name "DB_PART_NUMBER") "CAP000043686")
        (field (name "DB_VALUE") "22uF")
        (field (name "DB_TOLERANCE") "20%")
        (field (name "DB_VOLTAGE") "6.3V")
        (field (name "DB_MANUFACTURER_PART") "KEMET    C0805C226M9PAC")
        (field (name "DB_APPROVED_BY") "ISHIDDEN=T")
      )
      (libsource (lib "Database_Libs1") (part "C"))
    )
    (comp (ref "C346")
      (value "22uF")
      (footprint "SMD_0805_CAPC2012X145N")
      (fields
        (field (name "DB_PART_NUMBER") "CAP000043686")
        (field (name "DB_VALUE") "22uF")
        (field (name "DB_TOLERANCE") "20%")
        (field (name "DB_VOLTAGE") "6.3V")
        (field (name "DB_MANUFACTURER_PART") "KEMET    C0805C226M9PAC")
        (field (name "DB_APPROVED_BY") "ISHIDDEN=T")
      )
      (libsource (lib "Database_Libs1") (part "C"))
    )
    (comp (ref "C348")
      (value "100uF")
      (footprint "SMD_1210_CAPC3225X270N")
      (fields
        (field (name "DB_PART_NUMBER") "TMP-2512")
        (field (name "DB_VALUE") "100uF")
        (field (name "DB_TOLERANCE") "20%")
        (field (name "DB_VOLTAGE") "16V")
        (field (name "DB_MANUFACTURER_PART") "YAGEO    CC1210MRX5R7BB107")
      )
      (libsource (lib "Database_Libs1") (part "C"))
    )
    (comp (ref "C349")
      (value "100uF")
      (footprint "SMD_1210_CAPC3225X270N")
      (fields
        (field (name "DB_PART_NUMBER") "TMP-2512")
        (field (name "DB_VALUE") "100uF")
        (field (name "DB_TOLERANCE") "20%")
        (field (name "DB_VOLTAGE") "16V")
        (field (name "DB_MANUFACTURER_PART") "YAGEO    CC1210MRX5R7BB107")
      )
      (libsource (lib "Database_Libs1") (part "C"))
    )
    (comp (ref "C350")
      (value "220uF")
      (footprint "SMD_1210_CAPC3225X279N")
      (fields
        (field (name "DB_PART_NUMBER") "CAP000047355")
        (field (name "DB_VALUE") "220uF")
        (field (name "DB_TOLERANCE") "20%")
        (field (name "DB_VOLTAGE") "6.3V")
        (field (name "DB_MANUFACTURER_PART") "SAMSUNG    CL32A227MQVNNNE")
        (field (name "DB_APPROVED_BY") "VSN")
      )
      (libsource (lib "Database_Libs1") (part "C"))
    )
    (comp (ref "C351")
      (value "220uF")
      (footprint "SMD_1210_CAPC3225X279N")
      (fields
        (field (name "DB_PART_NUMBER") "CAP000047355")
        (field (name "DB_VALUE") "220uF")
        (field (name "DB_TOLERANCE") "20%")
        (field (name "DB_VOLTAGE") "6.3V")
        (field (name "DB_MANUFACTURER_PART") "SAMSUNG    CL32A227MQVNNNE")
        (field (name "DB_APPROVED_BY") "VSN")
      )
      (libsource (lib "Database_Libs1") (part "C"))
    )
    (comp (ref "C352")
      (value "220uF")
      (footprint "SMD_1210_CAPC3225X279N")
      (fields
        (field (name "DB_PART_NUMBER") "CAP000047355")
        (field (name "DB_VALUE") "220uF")
        (field (name "DB_TOLERANCE") "20%")
        (field (name "DB_VOLTAGE") "6.3V")
        (field (name "DB_MANUFACTURER_PART") "SAMSUNG    CL32A227MQVNNNE")
        (field (name "DB_APPROVED_BY") "VSN")
      )
      (libsource (lib "Database_Libs1") (part "C"))
    )
    (comp (ref "C353")
      (value "22uF")
      (footprint "SMD_0805_CAPC2012X145N")
      (fields
        (field (name "DB_PART_NUMBER") "CAP000043686")
        (field (name "DB_VALUE") "22uF")
        (field (name "DB_TOLERANCE") "20%")
        (field (name "DB_VOLTAGE") "6.3V")
        (field (name "DB_MANUFACTURER_PART") "KEMET    C0805C226M9PAC")
        (field (name "DB_APPROVED_BY") "ISHIDDEN=T")
      )
      (libsource (lib "Database_Libs1") (part "C"))
    )
    (comp (ref "C354")
      (value "22uF")
      (footprint "SMD_0805_CAPC2012X145N")
      (fields
        (field (name "DB_PART_NUMBER") "CAP000043686")
        (field (name "DB_VALUE") "22uF")
        (field (name "DB_TOLERANCE") "20%")
        (field (name "DB_VOLTAGE") "6.3V")
        (field (name "DB_MANUFACTURER_PART") "KEMET    C0805C226M9PAC")
        (field (name "DB_APPROVED_BY") "ISHIDDEN=T")
      )
      (libsource (lib "Database_Libs1") (part "C"))
    )
    (comp (ref "C355")
      (value "22uF")
      (footprint "SMD_0805_CAPC2012X145N")
      (fields
        (field (name "DB_PART_NUMBER") "CAP000043686")
        (field (name "DB_VALUE") "22uF")
        (field (name "DB_TOLERANCE") "20%")
        (field (name "DB_VOLTAGE") "6.3V")
        (field (name "DB_MANUFACTURER_PART") "KEMET    C0805C226M9PAC")
        (field (name "DB_APPROVED_BY") "ISHIDDEN=T")
      )
      (libsource (lib "Database_Libs1") (part "C"))
    )
    (comp (ref "C356")
      (value "22uF")
      (footprint "SMD_0805_CAPC2012X145N")
      (fields
        (field (name "DB_PART_NUMBER") "CAP000043686")
        (field (name "DB_VALUE") "22uF")
        (field (name "DB_TOLERANCE") "20%")
        (field (name "DB_VOLTAGE") "6.3V")
        (field (name "DB_MANUFACTURER_PART") "KEMET    C0805C226M9PAC")
        (field (name "DB_APPROVED_BY") "ISHIDDEN=T")
      )
      (libsource (lib "Database_Libs1") (part "C"))
    )
    (comp (ref "C357")
      (value "22uF")
      (footprint "SMD_0805_CAPC2012X145N")
      (fields
        (field (name "DB_PART_NUMBER") "CAP000043686")
        (field (name "DB_VALUE") "22uF")
        (field (name "DB_TOLERANCE") "20%")
        (field (name "DB_VOLTAGE") "6.3V")
        (field (name "DB_MANUFACTURER_PART") "KEMET    C0805C226M9PAC")
        (field (name "DB_APPROVED_BY") "ISHIDDEN=T")
      )
      (libsource (lib "Database_Libs1") (part "C"))
    )
    (comp (ref "C358")
      (value "22uF")
      (footprint "SMD_0805_CAPC2012X145N")
      (fields
        (field (name "DB_PART_NUMBER") "CAP000043686")
        (field (name "DB_VALUE") "22uF")
        (field (name "DB_TOLERANCE") "20%")
        (field (name "DB_VOLTAGE") "6.3V")
        (field (name "DB_MANUFACTURER_PART") "KEMET    C0805C226M9PAC")
        (field (name "DB_APPROVED_BY") "ISHIDDEN=T")
      )
      (libsource (lib "Database_Libs1") (part "C"))
    )
    (comp (ref "C359")
      (value "22uF")
      (footprint "SMD_0805_CAPC2012X145N")
      (fields
        (field (name "DB_PART_NUMBER") "CAP000043686")
        (field (name "DB_VALUE") "22uF")
        (field (name "DB_TOLERANCE") "20%")
        (field (name "DB_VOLTAGE") "6.3V")
        (field (name "DB_MANUFACTURER_PART") "KEMET    C0805C226M9PAC")
        (field (name "DB_APPROVED_BY") "ISHIDDEN=T")
      )
      (libsource (lib "Database_Libs1") (part "C"))
    )
    (comp (ref "C360")
      (value "22uF")
      (footprint "SMD_0805_CAPC2012X145N")
      (fields
        (field (name "DB_PART_NUMBER") "CAP000043686")
        (field (name "DB_VALUE") "22uF")
        (field (name "DB_TOLERANCE") "20%")
        (field (name "DB_VOLTAGE") "6.3V")
        (field (name "DB_MANUFACTURER_PART") "KEMET    C0805C226M9PAC")
        (field (name "DB_APPROVED_BY") "ISHIDDEN=T")
      )
      (libsource (lib "Database_Libs1") (part "C"))
    )
    (comp (ref "C361")
      (value "22uF")
      (footprint "SMD_0805_CAPC2012X145N")
      (fields
        (field (name "DB_PART_NUMBER") "CAP000043686")
        (field (name "DB_VALUE") "22uF")
        (field (name "DB_TOLERANCE") "20%")
        (field (name "DB_VOLTAGE") "6.3V")
        (field (name "DB_MANUFACTURER_PART") "KEMET    C0805C226M9PAC")
        (field (name "DB_APPROVED_BY") "ISHIDDEN=T")
      )
      (libsource (lib "Database_Libs1") (part "C"))
    )
    (comp (ref "C362")
      (value "22uF")
      (footprint "SMD_0805_CAPC2012X145N")
      (fields
        (field (name "DB_PART_NUMBER") "CAP000043686")
        (field (name "DB_VALUE") "22uF")
        (field (name "DB_TOLERANCE") "20%")
        (field (name "DB_VOLTAGE") "6.3V")
        (field (name "DB_MANUFACTURER_PART") "KEMET    C0805C226M9PAC")
        (field (name "DB_APPROVED_BY") "ISHIDDEN=T")
      )
      (libsource (lib "Database_Libs1") (part "C"))
    )
    (comp (ref "C363")
      (value "22uF")
      (footprint "SMD_0805_CAPC2012X145N")
      (fields
        (field (name "DB_PART_NUMBER") "CAP000043686")
        (field (name "DB_VALUE") "22uF")
        (field (name "DB_TOLERANCE") "20%")
        (field (name "DB_VOLTAGE") "6.3V")
        (field (name "DB_MANUFACTURER_PART") "KEMET    C0805C226M9PAC")
        (field (name "DB_APPROVED_BY") "ISHIDDEN=T")
      )
      (libsource (lib "Database_Libs1") (part "C"))
    )
    (comp (ref "C364")
      (value "22uF")
      (footprint "SMD_0805_CAPC2012X145N")
      (fields
        (field (name "DB_PART_NUMBER") "CAP000043686")
        (field (name "DB_VALUE") "22uF")
        (field (name "DB_TOLERANCE") "20%")
        (field (name "DB_VOLTAGE") "6.3V")
        (field (name "DB_MANUFACTURER_PART") "KEMET    C0805C226M9PAC")
        (field (name "DB_APPROVED_BY") "ISHIDDEN=T")
      )
      (libsource (lib "Database_Libs1") (part "C"))
    )
    (comp (ref "C365")
      (value "22uF")
      (footprint "SMD_0805_CAPC2012X145N")
      (fields
        (field (name "DB_PART_NUMBER") "CAP000043686")
        (field (name "DB_VALUE") "22uF")
        (field (name "DB_TOLERANCE") "20%")
        (field (name "DB_VOLTAGE") "6.3V")
        (field (name "DB_MANUFACTURER_PART") "KEMET    C0805C226M9PAC")
        (field (name "DB_APPROVED_BY") "ISHIDDEN=T")
      )
      (libsource (lib "Database_Libs1") (part "C"))
    )
    (comp (ref "C366")
      (value "22uF")
      (footprint "SMD_0805_CAPC2012X145N")
      (fields
        (field (name "DB_PART_NUMBER") "CAP000043686")
        (field (name "DB_VALUE") "22uF")
        (field (name "DB_TOLERANCE") "20%")
        (field (name "DB_VOLTAGE") "6.3V")
        (field (name "DB_MANUFACTURER_PART") "KEMET    C0805C226M9PAC")
        (field (name "DB_APPROVED_BY") "ISHIDDEN=T")
      )
      (libsource (lib "Database_Libs1") (part "C"))
    )
    (comp (ref "C367")
      (value "22uF")
      (footprint "SMD_0805_CAPC2012X145N")
      (fields
        (field (name "DB_PART_NUMBER") "CAP000043686")
        (field (name "DB_VALUE") "22uF")
        (field (name "DB_TOLERANCE") "20%")
        (field (name "DB_VOLTAGE") "6.3V")
        (field (name "DB_MANUFACTURER_PART") "KEMET    C0805C226M9PAC")
        (field (name "DB_APPROVED_BY") "ISHIDDEN=T")
      )
      (libsource (lib "Database_Libs1") (part "C"))
    )
    (comp (ref "C368")
      (value "22uF")
      (footprint "SMD_0805_CAPC2012X145N")
      (fields
        (field (name "DB_PART_NUMBER") "CAP000043686")
        (field (name "DB_VALUE") "22uF")
        (field (name "DB_TOLERANCE") "20%")
        (field (name "DB_VOLTAGE") "6.3V")
        (field (name "DB_MANUFACTURER_PART") "KEMET    C0805C226M9PAC")
        (field (name "DB_APPROVED_BY") "ISHIDDEN=T")
      )
      (libsource (lib "Database_Libs1") (part "C"))
    )
    (comp (ref "C369")
      (value "22uF")
      (footprint "SMD_0805_CAPC2012X145N")
      (fields
        (field (name "DB_PART_NUMBER") "CAP000043686")
        (field (name "DB_VALUE") "22uF")
        (field (name "DB_TOLERANCE") "20%")
        (field (name "DB_VOLTAGE") "6.3V")
        (field (name "DB_MANUFACTURER_PART") "KEMET    C0805C226M9PAC")
        (field (name "DB_APPROVED_BY") "ISHIDDEN=T")
      )
      (libsource (lib "Database_Libs1") (part "C"))
    )
    (comp (ref "C370")
      (value "22uF")
      (footprint "SMD_0805_CAPC2012X145N")
      (fields
        (field (name "DB_PART_NUMBER") "CAP000043686")
        (field (name "DB_VALUE") "22uF")
        (field (name "DB_TOLERANCE") "20%")
        (field (name "DB_VOLTAGE") "6.3V")
        (field (name "DB_MANUFACTURER_PART") "KEMET    C0805C226M9PAC")
        (field (name "DB_APPROVED_BY") "ISHIDDEN=T")
      )
      (libsource (lib "Database_Libs1") (part "C"))
    )
    (comp (ref "C371")
      (value "22uF")
      (footprint "SMD_0805_CAPC2012X145N")
      (fields
        (field (name "DB_PART_NUMBER") "CAP000043686")
        (field (name "DB_VALUE") "22uF")
        (field (name "DB_TOLERANCE") "20%")
        (field (name "DB_VOLTAGE") "6.3V")
        (field (name "DB_MANUFACTURER_PART") "KEMET    C0805C226M9PAC")
        (field (name "DB_APPROVED_BY") "ISHIDDEN=T")
      )
      (libsource (lib "Database_Libs1") (part "C"))
    )
    (comp (ref "C372")
      (value "22uF")
      (footprint "SMD_0805_CAPC2012X145N")
      (fields
        (field (name "DB_PART_NUMBER") "CAP000043686")
        (field (name "DB_VALUE") "22uF")
        (field (name "DB_TOLERANCE") "20%")
        (field (name "DB_VOLTAGE") "6.3V")
        (field (name "DB_MANUFACTURER_PART") "KEMET    C0805C226M9PAC")
        (field (name "DB_APPROVED_BY") "ISHIDDEN=T")
      )
      (libsource (lib "Database_Libs1") (part "C"))
    )
    (comp (ref "C373")
      (value "22uF")
      (footprint "SMD_0805_CAPC2012X145N")
      (fields
        (field (name "DB_PART_NUMBER") "CAP000043686")
        (field (name "DB_VALUE") "22uF")
        (field (name "DB_TOLERANCE") "20%")
        (field (name "DB_VOLTAGE") "6.3V")
        (field (name "DB_MANUFACTURER_PART") "KEMET    C0805C226M9PAC")
        (field (name "DB_APPROVED_BY") "ISHIDDEN=T")
      )
      (libsource (lib "Database_Libs1") (part "C"))
    )
    (comp (ref "C374")
      (value "22uF")
      (footprint "SMD_0805_CAPC2012X145N")
      (fields
        (field (name "DB_PART_NUMBER") "CAP000043686")
        (field (name "DB_VALUE") "22uF")
        (field (name "DB_TOLERANCE") "20%")
        (field (name "DB_VOLTAGE") "6.3V")
        (field (name "DB_MANUFACTURER_PART") "KEMET    C0805C226M9PAC")
        (field (name "DB_APPROVED_BY") "ISHIDDEN=T")
      )
      (libsource (lib "Database_Libs1") (part "C"))
    )
    (comp (ref "C375")
      (value "22uF")
      (footprint "SMD_0805_CAPC2012X145N")
      (fields
        (field (name "DB_PART_NUMBER") "CAP000043686")
        (field (name "DB_VALUE") "22uF")
        (field (name "DB_TOLERANCE") "20%")
        (field (name "DB_VOLTAGE") "6.3V")
        (field (name "DB_MANUFACTURER_PART") "KEMET    C0805C226M9PAC")
        (field (name "DB_APPROVED_BY") "ISHIDDEN=T")
      )
      (libsource (lib "Database_Libs1") (part "C"))
    )
    (comp (ref "C376")
      (value "22uF")
      (footprint "SMD_0805_CAPC2012X145N")
      (fields
        (field (name "DB_PART_NUMBER") "CAP000043686")
        (field (name "DB_VALUE") "22uF")
        (field (name "DB_TOLERANCE") "20%")
        (field (name "DB_VOLTAGE") "6.3V")
        (field (name "DB_MANUFACTURER_PART") "KEMET    C0805C226M9PAC")
        (field (name "DB_APPROVED_BY") "ISHIDDEN=T")
      )
      (libsource (lib "Database_Libs1") (part "C"))
    )
    (comp (ref "C377")
      (value "10uF")
      (footprint "SMD_0805_CAPC2012X145N")
      (fields
        (field (name "DB_PART_NUMBER") "CAP000043636")
        (field (name "DB_VALUE") "10uF")
        (field (name "DB_TOLERANCE") "10%")
        (field (name "DB_VOLTAGE") "16V")
        (field (name "DB_MANUFACTURER_PART") "KEMET    C0805C106K4PAC")
        (field (name "DB_APPROVED_BY") "ISHIDDEN=T")
      )
      (libsource (lib "Database_Libs1") (part "C"))
    )
    (comp (ref "C378")
      (value "10uF")
      (footprint "SMD_0805_CAPC2012X145N")
      (fields
        (field (name "DB_PART_NUMBER") "CAP000043636")
        (field (name "DB_VALUE") "10uF")
        (field (name "DB_TOLERANCE") "10%")
        (field (name "DB_VOLTAGE") "16V")
        (field (name "DB_MANUFACTURER_PART") "KEMET    C0805C106K4PAC")
        (field (name "DB_APPROVED_BY") "ISHIDDEN=T")
      )
      (libsource (lib "Database_Libs1") (part "C"))
    )
    (comp (ref "C379")
      (value "10uF")
      (footprint "SMD_0805_CAPC2012X145N")
      (fields
        (field (name "DB_PART_NUMBER") "CAP000043636")
        (field (name "DB_VALUE") "10uF")
        (field (name "DB_TOLERANCE") "10%")
        (field (name "DB_VOLTAGE") "16V")
        (field (name "DB_MANUFACTURER_PART") "KEMET    C0805C106K4PAC")
        (field (name "DB_APPROVED_BY") "ISHIDDEN=T")
      )
      (libsource (lib "Database_Libs1") (part "C"))
    )
    (comp (ref "C380")
      (value "10uF")
      (footprint "SMD_0805_CAPC2012X145N")
      (fields
        (field (name "DB_PART_NUMBER") "CAP000043636")
        (field (name "DB_VALUE") "10uF")
        (field (name "DB_TOLERANCE") "10%")
        (field (name "DB_VOLTAGE") "16V")
        (field (name "DB_MANUFACTURER_PART") "KEMET    C0805C106K4PAC")
        (field (name "DB_APPROVED_BY") "ISHIDDEN=T")
      )
      (libsource (lib "Database_Libs1") (part "C"))
    )
    (comp (ref "C381")
      (value "10uF")
      (footprint "SMD_0805_CAPC2012X145N")
      (fields
        (field (name "DB_PART_NUMBER") "CAP000043636")
        (field (name "DB_VALUE") "10uF")
        (field (name "DB_TOLERANCE") "10%")
        (field (name "DB_VOLTAGE") "16V")
        (field (name "DB_MANUFACTURER_PART") "KEMET    C0805C106K4PAC")
        (field (name "DB_APPROVED_BY") "ISHIDDEN=T")
      )
      (libsource (lib "Database_Libs1") (part "C"))
    )
    (comp (ref "C382")
      (value "10uF")
      (footprint "SMD_0805_CAPC2012X145N")
      (fields
        (field (name "DB_PART_NUMBER") "CAP000043636")
        (field (name "DB_VALUE") "10uF")
        (field (name "DB_TOLERANCE") "10%")
        (field (name "DB_VOLTAGE") "16V")
        (field (name "DB_MANUFACTURER_PART") "KEMET    C0805C106K4PAC")
        (field (name "DB_APPROVED_BY") "ISHIDDEN=T")
      )
      (libsource (lib "Database_Libs1") (part "C"))
    )
    (comp (ref "C383")
      (value "10uF")
      (footprint "SMD_0805_CAPC2012X145N")
      (fields
        (field (name "DB_PART_NUMBER") "CAP000043636")
        (field (name "DB_VALUE") "10uF")
        (field (name "DB_TOLERANCE") "10%")
        (field (name "DB_VOLTAGE") "16V")
        (field (name "DB_MANUFACTURER_PART") "KEMET    C0805C106K4PAC")
        (field (name "DB_APPROVED_BY") "ISHIDDEN=T")
      )
      (libsource (lib "Database_Libs1") (part "C"))
    )
    (comp (ref "C384")
      (value "10uF")
      (footprint "SMD_0805_CAPC2012X145N")
      (fields
        (field (name "DB_PART_NUMBER") "CAP000043636")
        (field (name "DB_VALUE") "10uF")
        (field (name "DB_TOLERANCE") "10%")
        (field (name "DB_VOLTAGE") "16V")
        (field (name "DB_MANUFACTURER_PART") "KEMET    C0805C106K4PAC")
        (field (name "DB_APPROVED_BY") "ISHIDDEN=T")
      )
      (libsource (lib "Database_Libs1") (part "C"))
    )
    (comp (ref "C385")
      (value "10uF")
      (footprint "SMD_0805_CAPC2012X145N")
      (fields
        (field (name "DB_PART_NUMBER") "CAP000043636")
        (field (name "DB_VALUE") "10uF")
        (field (name "DB_TOLERANCE") "10%")
        (field (name "DB_VOLTAGE") "16V")
        (field (name "DB_MANUFACTURER_PART") "KEMET    C0805C106K4PAC")
        (field (name "DB_APPROVED_BY") "ISHIDDEN=T")
      )
      (libsource (lib "Database_Libs1") (part "C"))
    )
    (comp (ref "C386")
      (value "10uF")
      (footprint "SMD_0805_CAPC2012X145N")
      (fields
        (field (name "DB_PART_NUMBER") "CAP000043636")
        (field (name "DB_VALUE") "10uF")
        (field (name "DB_TOLERANCE") "10%")
        (field (name "DB_VOLTAGE") "16V")
        (field (name "DB_MANUFACTURER_PART") "KEMET    C0805C106K4PAC")
        (field (name "DB_APPROVED_BY") "ISHIDDEN=T")
      )
      (libsource (lib "Database_Libs1") (part "C"))
    )
    (comp (ref "C387")
      (value "10uF")
      (footprint "SMD_0805_CAPC2012X145N")
      (fields
        (field (name "DB_PART_NUMBER") "CAP000043636")
        (field (name "DB_VALUE") "10uF")
        (field (name "DB_TOLERANCE") "10%")
        (field (name "DB_VOLTAGE") "16V")
        (field (name "DB_MANUFACTURER_PART") "KEMET    C0805C106K4PAC")
        (field (name "DB_APPROVED_BY") "ISHIDDEN=T")
      )
      (libsource (lib "Database_Libs1") (part "C"))
    )
    (comp (ref "C388")
      (value "10uF")
      (footprint "SMD_0805_CAPC2012X145N")
      (fields
        (field (name "DB_PART_NUMBER") "CAP000043636")
        (field (name "DB_VALUE") "10uF")
        (field (name "DB_TOLERANCE") "10%")
        (field (name "DB_VOLTAGE") "16V")
        (field (name "DB_MANUFACTURER_PART") "KEMET    C0805C106K4PAC")
        (field (name "DB_APPROVED_BY") "ISHIDDEN=T")
      )
      (libsource (lib "Database_Libs1") (part "C"))
    )
    (comp (ref "C389")
      (value "10uF")
      (footprint "SMD_0805_CAPC2012X145N")
      (fields
        (field (name "DB_PART_NUMBER") "CAP000043636")
        (field (name "DB_VALUE") "10uF")
        (field (name "DB_TOLERANCE") "10%")
        (field (name "DB_VOLTAGE") "16V")
        (field (name "DB_MANUFACTURER_PART") "KEMET    C0805C106K4PAC")
        (field (name "DB_APPROVED_BY") "ISHIDDEN=T")
      )
      (libsource (lib "Database_Libs1") (part "C"))
    )
    (comp (ref "C390")
      (value "10uF")
      (footprint "SMD_0805_CAPC2012X145N")
      (fields
        (field (name "DB_PART_NUMBER") "CAP000043636")
        (field (name "DB_VALUE") "10uF")
        (field (name "DB_TOLERANCE") "10%")
        (field (name "DB_VOLTAGE") "16V")
        (field (name "DB_MANUFACTURER_PART") "KEMET    C0805C106K4PAC")
        (field (name "DB_APPROVED_BY") "ISHIDDEN=T")
      )
      (libsource (lib "Database_Libs1") (part "C"))
    )
    (comp (ref "C391")
      (value "10uF")
      (footprint "SMD_0805_CAPC2012X145N")
      (fields
        (field (name "DB_PART_NUMBER") "CAP000043636")
        (field (name "DB_VALUE") "10uF")
        (field (name "DB_TOLERANCE") "10%")
        (field (name "DB_VOLTAGE") "16V")
        (field (name "DB_MANUFACTURER_PART") "KEMET    C0805C106K4PAC")
        (field (name "DB_APPROVED_BY") "ISHIDDEN=T")
      )
      (libsource (lib "Database_Libs1") (part "C"))
    )
    (comp (ref "C392")
      (value "10uF")
      (footprint "SMD_0805_CAPC2012X145N")
      (fields
        (field (name "DB_PART_NUMBER") "CAP000043636")
        (field (name "DB_VALUE") "10uF")
        (field (name "DB_TOLERANCE") "10%")
        (field (name "DB_VOLTAGE") "16V")
        (field (name "DB_MANUFACTURER_PART") "KEMET    C0805C106K4PAC")
        (field (name "DB_APPROVED_BY") "ISHIDDEN=T")
      )
      (libsource (lib "Database_Libs1") (part "C"))
    )
    (comp (ref "C393")
      (value "220uF")
      (footprint "SMD_1210_CAPC3225X279N")
      (fields
        (field (name "DB_PART_NUMBER") "CAP000047355")
        (field (name "DB_VALUE") "220uF")
        (field (name "DB_TOLERANCE") "20%")
        (field (name "DB_VOLTAGE") "6.3V")
        (field (name "DB_MANUFACTURER_PART") "SAMSUNG    CL32A227MQVNNNE")
        (field (name "DB_APPROVED_BY") "VSN")
      )
      (libsource (lib "Database_Libs1") (part "C"))
    )
    (comp (ref "C394")
      (value "220uF")
      (footprint "SMD_1210_CAPC3225X279N")
      (fields
        (field (name "DB_PART_NUMBER") "CAP000047355")
        (field (name "DB_VALUE") "220uF")
        (field (name "DB_TOLERANCE") "20%")
        (field (name "DB_VOLTAGE") "6.3V")
        (field (name "DB_MANUFACTURER_PART") "SAMSUNG    CL32A227MQVNNNE")
        (field (name "DB_APPROVED_BY") "VSN")
      )
      (libsource (lib "Database_Libs1") (part "C"))
    )
    (comp (ref "C395")
      (value "220uF")
      (footprint "SMD_1210_CAPC3225X279N")
      (fields
        (field (name "DB_PART_NUMBER") "CAP000047355")
        (field (name "DB_VALUE") "220uF")
        (field (name "DB_TOLERANCE") "20%")
        (field (name "DB_VOLTAGE") "6.3V")
        (field (name "DB_MANUFACTURER_PART") "SAMSUNG    CL32A227MQVNNNE")
        (field (name "DB_APPROVED_BY") "VSN")
      )
      (libsource (lib "Database_Libs1") (part "C"))
    )
    (comp (ref "C396")
      (value "220uF")
      (footprint "SMD_1210_CAPC3225X279N")
      (fields
        (field (name "DB_PART_NUMBER") "CAP000047355")
        (field (name "DB_VALUE") "220uF")
        (field (name "DB_TOLERANCE") "20%")
        (field (name "DB_VOLTAGE") "6.3V")
        (field (name "DB_MANUFACTURER_PART") "SAMSUNG    CL32A227MQVNNNE")
        (field (name "DB_APPROVED_BY") "VSN")
      )
      (libsource (lib "Database_Libs1") (part "C"))
    )
    (comp (ref "C397")
      (value "220uF")
      (footprint "SMD_1210_CAPC3225X279N")
      (fields
        (field (name "DB_PART_NUMBER") "CAP000047355")
        (field (name "DB_VALUE") "220uF")
        (field (name "DB_TOLERANCE") "20%")
        (field (name "DB_VOLTAGE") "6.3V")
        (field (name "DB_MANUFACTURER_PART") "SAMSUNG    CL32A227MQVNNNE")
        (field (name "DB_APPROVED_BY") "VSN")
      )
      (libsource (lib "Database_Libs1") (part "C"))
    )
    (comp (ref "C398")
      (value "220uF")
      (footprint "SMD_1210_CAPC3225X279N")
      (fields
        (field (name "DB_PART_NUMBER") "CAP000047355")
        (field (name "DB_VALUE") "220uF")
        (field (name "DB_TOLERANCE") "20%")
        (field (name "DB_VOLTAGE") "6.3V")
        (field (name "DB_MANUFACTURER_PART") "SAMSUNG    CL32A227MQVNNNE")
        (field (name "DB_APPROVED_BY") "VSN")
      )
      (libsource (lib "Database_Libs1") (part "C"))
    )
    (comp (ref "C399")
      (value "220uF")
      (footprint "SMD_1210_CAPC3225X279N")
      (fields
        (field (name "DB_PART_NUMBER") "CAP000047355")
        (field (name "DB_VALUE") "220uF")
        (field (name "DB_TOLERANCE") "20%")
        (field (name "DB_VOLTAGE") "6.3V")
        (field (name "DB_MANUFACTURER_PART") "SAMSUNG    CL32A227MQVNNNE")
        (field (name "DB_APPROVED_BY") "VSN")
      )
      (libsource (lib "Database_Libs1") (part "C"))
    )
    (comp (ref "C400")
      (value "220uF")
      (footprint "SMD_1210_CAPC3225X279N")
      (fields
        (field (name "DB_PART_NUMBER") "CAP000047355")
        (field (name "DB_VALUE") "220uF")
        (field (name "DB_TOLERANCE") "20%")
        (field (name "DB_VOLTAGE") "6.3V")
        (field (name "DB_MANUFACTURER_PART") "SAMSUNG    CL32A227MQVNNNE")
        (field (name "DB_APPROVED_BY") "VSN")
      )
      (libsource (lib "Database_Libs1") (part "C"))
    )
    (comp (ref "C401")
      (value "220uF")
      (footprint "SMD_1210_CAPC3225X279N")
      (fields
        (field (name "DB_PART_NUMBER") "CAP000047355")
        (field (name "DB_VALUE") "220uF")
        (field (name "DB_TOLERANCE") "20%")
        (field (name "DB_VOLTAGE") "6.3V")
        (field (name "DB_MANUFACTURER_PART") "SAMSUNG    CL32A227MQVNNNE")
        (field (name "DB_APPROVED_BY") "VSN")
      )
      (libsource (lib "Database_Libs1") (part "C"))
    )
    (comp (ref "C402")
      (value "100uF")
      (footprint "SMD_1210_CAPC3225X270N")
      (fields
        (field (name "DB_PART_NUMBER") "TMP-2512")
        (field (name "DB_VALUE") "100uF")
        (field (name "DB_TOLERANCE") "20%")
        (field (name "DB_VOLTAGE") "16V")
        (field (name "DB_MANUFACTURER_PART") "YAGEO    CC1210MRX5R7BB107")
      )
      (libsource (lib "Database_Libs1") (part "C"))
    )
    (comp (ref "C403")
      (value "100uF")
      (footprint "SMD_1210_CAPC3225X270N")
      (fields
        (field (name "DB_PART_NUMBER") "TMP-2512")
        (field (name "DB_VALUE") "100uF")
        (field (name "DB_TOLERANCE") "20%")
        (field (name "DB_VOLTAGE") "16V")
        (field (name "DB_MANUFACTURER_PART") "YAGEO    CC1210MRX5R7BB107")
      )
      (libsource (lib "Database_Libs1") (part "C"))
    )
    (comp (ref "C404")
      (value "100uF")
      (footprint "SMD_1210_CAPC3225X270N")
      (fields
        (field (name "DB_PART_NUMBER") "TMP-2512")
        (field (name "DB_VALUE") "100uF")
        (field (name "DB_TOLERANCE") "20%")
        (field (name "DB_VOLTAGE") "16V")
        (field (name "DB_MANUFACTURER_PART") "YAGEO    CC1210MRX5R7BB107")
      )
      (libsource (lib "Database_Libs1") (part "C"))
    )
    (comp (ref "C405")
      (value "100uF")
      (footprint "SMD_1210_CAPC3225X270N")
      (fields
        (field (name "DB_PART_NUMBER") "TMP-2512")
        (field (name "DB_VALUE") "100uF")
        (field (name "DB_TOLERANCE") "20%")
        (field (name "DB_VOLTAGE") "16V")
        (field (name "DB_MANUFACTURER_PART") "YAGEO    CC1210MRX5R7BB107")
      )
      (libsource (lib "Database_Libs1") (part "C"))
    )
    (comp (ref "C406")
      (value "100uF")
      (footprint "SMD_1210_CAPC3225X270N")
      (fields
        (field (name "DB_PART_NUMBER") "TMP-2512")
        (field (name "DB_VALUE") "100uF")
        (field (name "DB_TOLERANCE") "20%")
        (field (name "DB_VOLTAGE") "16V")
        (field (name "DB_MANUFACTURER_PART") "YAGEO    CC1210MRX5R7BB107")
      )
      (libsource (lib "Database_Libs1") (part "C"))
    )
    (comp (ref "C407")
      (value "100uF")
      (footprint "SMD_1210_CAPC3225X270N")
      (fields
        (field (name "DB_PART_NUMBER") "TMP-2512")
        (field (name "DB_VALUE") "100uF")
        (field (name "DB_TOLERANCE") "20%")
        (field (name "DB_VOLTAGE") "16V")
        (field (name "DB_MANUFACTURER_PART") "YAGEO    CC1210MRX5R7BB107")
      )
      (libsource (lib "Database_Libs1") (part "C"))
    )
    (comp (ref "C408")
      (value "220uF")
      (footprint "SMD_1210_CAPC3225X279N")
      (fields
        (field (name "DB_PART_NUMBER") "CAP000047355")
        (field (name "DB_VALUE") "220uF")
        (field (name "DB_TOLERANCE") "20%")
        (field (name "DB_VOLTAGE") "6.3V")
        (field (name "DB_MANUFACTURER_PART") "SAMSUNG    CL32A227MQVNNNE")
        (field (name "DB_APPROVED_BY") "VSN")
      )
      (libsource (lib "Database_Libs1") (part "C"))
    )
    (comp (ref "C409")
      (value "220uF")
      (footprint "SMD_1210_CAPC3225X279N")
      (fields
        (field (name "DB_PART_NUMBER") "CAP000047355")
        (field (name "DB_VALUE") "220uF")
        (field (name "DB_TOLERANCE") "20%")
        (field (name "DB_VOLTAGE") "6.3V")
        (field (name "DB_MANUFACTURER_PART") "SAMSUNG    CL32A227MQVNNNE")
        (field (name "DB_APPROVED_BY") "VSN")
      )
      (libsource (lib "Database_Libs1") (part "C"))
    )
    (comp (ref "C410")
      (value "220uF")
      (footprint "SMD_1210_CAPC3225X279N")
      (fields
        (field (name "DB_PART_NUMBER") "CAP000047355")
        (field (name "DB_VALUE") "220uF")
        (field (name "DB_TOLERANCE") "20%")
        (field (name "DB_VOLTAGE") "6.3V")
        (field (name "DB_MANUFACTURER_PART") "SAMSUNG    CL32A227MQVNNNE")
        (field (name "DB_APPROVED_BY") "VSN")
      )
      (libsource (lib "Database_Libs1") (part "C"))
    )
    (comp (ref "C411")
      (value "220uF")
      (footprint "SMD_1210_CAPC3225X279N")
      (fields
        (field (name "DB_PART_NUMBER") "CAP000047355")
        (field (name "DB_VALUE") "220uF")
        (field (name "DB_TOLERANCE") "20%")
        (field (name "DB_VOLTAGE") "6.3V")
        (field (name "DB_MANUFACTURER_PART") "SAMSUNG    CL32A227MQVNNNE")
        (field (name "DB_APPROVED_BY") "VSN")
      )
      (libsource (lib "Database_Libs1") (part "C"))
    )
    (comp (ref "C412")
      (value "220uF")
      (footprint "SMD_1210_CAPC3225X279N")
      (fields
        (field (name "DB_PART_NUMBER") "CAP000047355")
        (field (name "DB_VALUE") "220uF")
        (field (name "DB_TOLERANCE") "20%")
        (field (name "DB_VOLTAGE") "6.3V")
        (field (name "DB_MANUFACTURER_PART") "SAMSUNG    CL32A227MQVNNNE")
        (field (name "DB_APPROVED_BY") "VSN")
      )
      (libsource (lib "Database_Libs1") (part "C"))
    )
    (comp (ref "C413")
      (value "220uF")
      (footprint "SMD_1210_CAPC3225X279N")
      (fields
        (field (name "DB_PART_NUMBER") "CAP000047355")
        (field (name "DB_VALUE") "220uF")
        (field (name "DB_TOLERANCE") "20%")
        (field (name "DB_VOLTAGE") "6.3V")
        (field (name "DB_MANUFACTURER_PART") "SAMSUNG    CL32A227MQVNNNE")
        (field (name "DB_APPROVED_BY") "VSN")
      )
      (libsource (lib "Database_Libs1") (part "C"))
    )
    (comp (ref "C414")
      (value "220uF")
      (footprint "SMD_1210_CAPC3225X279N")
      (fields
        (field (name "DB_PART_NUMBER") "CAP000047355")
        (field (name "DB_VALUE") "220uF")
        (field (name "DB_TOLERANCE") "20%")
        (field (name "DB_VOLTAGE") "6.3V")
        (field (name "DB_MANUFACTURER_PART") "SAMSUNG    CL32A227MQVNNNE")
        (field (name "DB_APPROVED_BY") "VSN")
      )
      (libsource (lib "Database_Libs1") (part "C"))
    )
    (comp (ref "C415")
      (value "220uF")
      (footprint "SMD_1210_CAPC3225X279N")
      (fields
        (field (name "DB_PART_NUMBER") "CAP000047355")
        (field (name "DB_VALUE") "220uF")
        (field (name "DB_TOLERANCE") "20%")
        (field (name "DB_VOLTAGE") "6.3V")
        (field (name "DB_MANUFACTURER_PART") "SAMSUNG    CL32A227MQVNNNE")
        (field (name "DB_APPROVED_BY") "VSN")
      )
      (libsource (lib "Database_Libs1") (part "C"))
    )
    (comp (ref "C416")
      (value "220uF")
      (footprint "SMD_1210_CAPC3225X279N")
      (fields
        (field (name "DB_PART_NUMBER") "CAP000047355")
        (field (name "DB_VALUE") "220uF")
        (field (name "DB_TOLERANCE") "20%")
        (field (name "DB_VOLTAGE") "6.3V")
        (field (name "DB_MANUFACTURER_PART") "SAMSUNG    CL32A227MQVNNNE")
        (field (name "DB_APPROVED_BY") "VSN")
      )
      (libsource (lib "Database_Libs1") (part "C"))
    )
    (comp (ref "C417")
      (value "220uF")
      (footprint "SMD_1210_CAPC3225X279N")
      (fields
        (field (name "DB_PART_NUMBER") "CAP000047355")
        (field (name "DB_VALUE") "220uF")
        (field (name "DB_TOLERANCE") "20%")
        (field (name "DB_VOLTAGE") "6.3V")
        (field (name "DB_MANUFACTURER_PART") "SAMSUNG    CL32A227MQVNNNE")
        (field (name "DB_APPROVED_BY") "VSN")
      )
      (libsource (lib "Database_Libs1") (part "C"))
    )
    (comp (ref "C418")
      (value "220uF")
      (footprint "SMD_1210_CAPC3225X279N")
      (fields
        (field (name "DB_PART_NUMBER") "CAP000047355")
        (field (name "DB_VALUE") "220uF")
        (field (name "DB_TOLERANCE") "20%")
        (field (name "DB_VOLTAGE") "6.3V")
        (field (name "DB_MANUFACTURER_PART") "SAMSUNG    CL32A227MQVNNNE")
        (field (name "DB_APPROVED_BY") "VSN")
      )
      (libsource (lib "Database_Libs1") (part "C"))
    )
    (comp (ref "C419")
      (value "220uF")
      (footprint "SMD_1210_CAPC3225X279N")
      (fields
        (field (name "DB_PART_NUMBER") "CAP000047355")
        (field (name "DB_VALUE") "220uF")
        (field (name "DB_TOLERANCE") "20%")
        (field (name "DB_VOLTAGE") "6.3V")
        (field (name "DB_MANUFACTURER_PART") "SAMSUNG    CL32A227MQVNNNE")
        (field (name "DB_APPROVED_BY") "VSN")
      )
      (libsource (lib "Database_Libs1") (part "C"))
    )
    (comp (ref "C420")
      (value "100uF")
      (footprint "SMD_1210_CAPC3225X270N")
      (fields
        (field (name "DB_PART_NUMBER") "TMP-2512")
        (field (name "DB_VALUE") "100uF")
        (field (name "DB_TOLERANCE") "20%")
        (field (name "DB_VOLTAGE") "16V")
        (field (name "DB_MANUFACTURER_PART") "YAGEO    CC1210MRX5R7BB107")
      )
      (libsource (lib "Database_Libs1") (part "C"))
    )
    (comp (ref "C421")
      (value "100uF")
      (footprint "SMD_1210_CAPC3225X270N")
      (fields
        (field (name "DB_PART_NUMBER") "TMP-2512")
        (field (name "DB_VALUE") "100uF")
        (field (name "DB_TOLERANCE") "20%")
        (field (name "DB_VOLTAGE") "16V")
        (field (name "DB_MANUFACTURER_PART") "YAGEO    CC1210MRX5R7BB107")
      )
      (libsource (lib "Database_Libs1") (part "C"))
    )
    (comp (ref "C422")
      (value "100uF")
      (footprint "SMD_1210_CAPC3225X270N")
      (fields
        (field (name "DB_PART_NUMBER") "TMP-2512")
        (field (name "DB_VALUE") "100uF")
        (field (name "DB_TOLERANCE") "20%")
        (field (name "DB_VOLTAGE") "16V")
        (field (name "DB_MANUFACTURER_PART") "YAGEO    CC1210MRX5R7BB107")
      )
      (libsource (lib "Database_Libs1") (part "C"))
    )
    (comp (ref "C423")
      (value "100uF")
      (footprint "SMD_1210_CAPC3225X270N")
      (fields
        (field (name "DB_PART_NUMBER") "TMP-2512")
        (field (name "DB_VALUE") "100uF")
        (field (name "DB_TOLERANCE") "20%")
        (field (name "DB_VOLTAGE") "16V")
        (field (name "DB_MANUFACTURER_PART") "YAGEO    CC1210MRX5R7BB107")
      )
      (libsource (lib "Database_Libs1") (part "C"))
    )
    (comp (ref "C424")
      (value "100uF")
      (footprint "SMD_1210_CAPC3225X270N")
      (fields
        (field (name "DB_PART_NUMBER") "TMP-2512")
        (field (name "DB_VALUE") "100uF")
        (field (name "DB_TOLERANCE") "20%")
        (field (name "DB_VOLTAGE") "16V")
        (field (name "DB_MANUFACTURER_PART") "YAGEO    CC1210MRX5R7BB107")
      )
      (libsource (lib "Database_Libs1") (part "C"))
    )
    (comp (ref "C425")
      (value "100uF")
      (footprint "SMD_1210_CAPC3225X270N")
      (fields
        (field (name "DB_PART_NUMBER") "TMP-2512")
        (field (name "DB_VALUE") "100uF")
        (field (name "DB_TOLERANCE") "20%")
        (field (name "DB_VOLTAGE") "16V")
        (field (name "DB_MANUFACTURER_PART") "YAGEO    CC1210MRX5R7BB107")
      )
      (libsource (lib "Database_Libs1") (part "C"))
    )
    (comp (ref "C426")
      (value "100uF")
      (footprint "SMD_1210_CAPC3225X270N")
      (fields
        (field (name "DB_PART_NUMBER") "TMP-2512")
        (field (name "DB_VALUE") "100uF")
        (field (name "DB_TOLERANCE") "20%")
        (field (name "DB_VOLTAGE") "16V")
        (field (name "DB_MANUFACTURER_PART") "YAGEO    CC1210MRX5R7BB107")
      )
      (libsource (lib "Database_Libs1") (part "C"))
    )
    (comp (ref "C427")
      (value "100uF")
      (footprint "SMD_1210_CAPC3225X270N")
      (fields
        (field (name "DB_PART_NUMBER") "TMP-2512")
        (field (name "DB_VALUE") "100uF")
        (field (name "DB_TOLERANCE") "20%")
        (field (name "DB_VOLTAGE") "16V")
        (field (name "DB_MANUFACTURER_PART") "YAGEO    CC1210MRX5R7BB107")
      )
      (libsource (lib "Database_Libs1") (part "C"))
    )
    (comp (ref "C428")
      (value "10uF")
      (footprint "SMD_0805_CAPC2012X145N")
      (fields
        (field (name "DB_PART_NUMBER") "CAP000043636")
        (field (name "DB_VALUE") "10uF")
        (field (name "DB_TOLERANCE") "10%")
        (field (name "DB_VOLTAGE") "16V")
        (field (name "DB_MANUFACTURER_PART") "KEMET    C0805C106K4PAC")
        (field (name "DB_APPROVED_BY") "ISHIDDEN=T")
      )
      (libsource (lib "Database_Libs1") (part "C"))
    )
    (comp (ref "C429")
      (value "10uF")
      (footprint "SMD_0805_CAPC2012X145N")
      (fields
        (field (name "DB_PART_NUMBER") "CAP000043636")
        (field (name "DB_VALUE") "10uF")
        (field (name "DB_TOLERANCE") "10%")
        (field (name "DB_VOLTAGE") "16V")
        (field (name "DB_MANUFACTURER_PART") "KEMET    C0805C106K4PAC")
        (field (name "DB_APPROVED_BY") "ISHIDDEN=T")
      )
      (libsource (lib "Database_Libs1") (part "C"))
    )
    (comp (ref "C430")
      (value "10uF")
      (footprint "SMD_0805_CAPC2012X145N")
      (fields
        (field (name "DB_PART_NUMBER") "CAP000043636")
        (field (name "DB_VALUE") "10uF")
        (field (name "DB_TOLERANCE") "10%")
        (field (name "DB_VOLTAGE") "16V")
        (field (name "DB_MANUFACTURER_PART") "KEMET    C0805C106K4PAC")
        (field (name "DB_APPROVED_BY") "ISHIDDEN=T")
      )
      (libsource (lib "Database_Libs1") (part "C"))
    )
    (comp (ref "C431")
      (value "10uF")
      (footprint "SMD_0805_CAPC2012X145N")
      (fields
        (field (name "DB_PART_NUMBER") "CAP000043636")
        (field (name "DB_VALUE") "10uF")
        (field (name "DB_TOLERANCE") "10%")
        (field (name "DB_VOLTAGE") "16V")
        (field (name "DB_MANUFACTURER_PART") "KEMET    C0805C106K4PAC")
        (field (name "DB_APPROVED_BY") "ISHIDDEN=T")
      )
      (libsource (lib "Database_Libs1") (part "C"))
    )
    (comp (ref "C432")
      (value "10uF")
      (footprint "SMD_0805_CAPC2012X145N")
      (fields
        (field (name "DB_PART_NUMBER") "CAP000043636")
        (field (name "DB_VALUE") "10uF")
        (field (name "DB_TOLERANCE") "10%")
        (field (name "DB_VOLTAGE") "16V")
        (field (name "DB_MANUFACTURER_PART") "KEMET    C0805C106K4PAC")
        (field (name "DB_APPROVED_BY") "ISHIDDEN=T")
      )
      (libsource (lib "Database_Libs1") (part "C"))
    )
    (comp (ref "C433")
      (value "10uF")
      (footprint "SMD_0805_CAPC2012X145N")
      (fields
        (field (name "DB_PART_NUMBER") "CAP000043636")
        (field (name "DB_VALUE") "10uF")
        (field (name "DB_TOLERANCE") "10%")
        (field (name "DB_VOLTAGE") "16V")
        (field (name "DB_MANUFACTURER_PART") "KEMET    C0805C106K4PAC")
        (field (name "DB_APPROVED_BY") "ISHIDDEN=T")
      )
      (libsource (lib "Database_Libs1") (part "C"))
    )
    (comp (ref "C434")
      (value "10uF")
      (footprint "SMD_0805_CAPC2012X145N")
      (fields
        (field (name "DB_PART_NUMBER") "CAP000043636")
        (field (name "DB_VALUE") "10uF")
        (field (name "DB_TOLERANCE") "10%")
        (field (name "DB_VOLTAGE") "16V")
        (field (name "DB_MANUFACTURER_PART") "KEMET    C0805C106K4PAC")
        (field (name "DB_APPROVED_BY") "ISHIDDEN=T")
      )
      (libsource (lib "Database_Libs1") (part "C"))
    )
    (comp (ref "C435")
      (value "10uF")
      (footprint "SMD_0805_CAPC2012X145N")
      (fields
        (field (name "DB_PART_NUMBER") "CAP000043636")
        (field (name "DB_VALUE") "10uF")
        (field (name "DB_TOLERANCE") "10%")
        (field (name "DB_VOLTAGE") "16V")
        (field (name "DB_MANUFACTURER_PART") "KEMET    C0805C106K4PAC")
        (field (name "DB_APPROVED_BY") "ISHIDDEN=T")
      )
      (libsource (lib "Database_Libs1") (part "C"))
    )
    (comp (ref "C436")
      (value "10uF")
      (footprint "SMD_0805_CAPC2012X145N")
      (fields
        (field (name "DB_PART_NUMBER") "CAP000043636")
        (field (name "DB_VALUE") "10uF")
        (field (name "DB_TOLERANCE") "10%")
        (field (name "DB_VOLTAGE") "16V")
        (field (name "DB_MANUFACTURER_PART") "KEMET    C0805C106K4PAC")
        (field (name "DB_APPROVED_BY") "ISHIDDEN=T")
      )
      (libsource (lib "Database_Libs1") (part "C"))
    )
    (comp (ref "C437")
      (value "10uF")
      (footprint "SMD_0805_CAPC2012X145N")
      (fields
        (field (name "DB_PART_NUMBER") "CAP000043636")
        (field (name "DB_VALUE") "10uF")
        (field (name "DB_TOLERANCE") "10%")
        (field (name "DB_VOLTAGE") "16V")
        (field (name "DB_MANUFACTURER_PART") "KEMET    C0805C106K4PAC")
        (field (name "DB_APPROVED_BY") "ISHIDDEN=T")
      )
      (libsource (lib "Database_Libs1") (part "C"))
    )
    (comp (ref "C438")
      (value "10uF")
      (footprint "SMD_0805_CAPC2012X145N")
      (fields
        (field (name "DB_PART_NUMBER") "CAP000043636")
        (field (name "DB_VALUE") "10uF")
        (field (name "DB_TOLERANCE") "10%")
        (field (name "DB_VOLTAGE") "16V")
        (field (name "DB_MANUFACTURER_PART") "KEMET    C0805C106K4PAC")
        (field (name "DB_APPROVED_BY") "ISHIDDEN=T")
      )
      (libsource (lib "Database_Libs1") (part "C"))
    )
    (comp (ref "C439")
      (value "10uF")
      (footprint "SMD_0805_CAPC2012X145N")
      (fields
        (field (name "DB_PART_NUMBER") "CAP000043636")
        (field (name "DB_VALUE") "10uF")
        (field (name "DB_TOLERANCE") "10%")
        (field (name "DB_VOLTAGE") "16V")
        (field (name "DB_MANUFACTURER_PART") "KEMET    C0805C106K4PAC")
        (field (name "DB_APPROVED_BY") "ISHIDDEN=T")
      )
      (libsource (lib "Database_Libs1") (part "C"))
    )
    (comp (ref "C440")
      (value "10uF")
      (footprint "SMD_0805_CAPC2012X145N")
      (fields
        (field (name "DB_PART_NUMBER") "CAP000043636")
        (field (name "DB_VALUE") "10uF")
        (field (name "DB_TOLERANCE") "10%")
        (field (name "DB_VOLTAGE") "16V")
        (field (name "DB_MANUFACTURER_PART") "KEMET    C0805C106K4PAC")
        (field (name "DB_APPROVED_BY") "ISHIDDEN=T")
      )
      (libsource (lib "Database_Libs1") (part "C"))
    )
    (comp (ref "C441")
      (value "10uF")
      (footprint "SMD_0805_CAPC2012X145N")
      (fields
        (field (name "DB_PART_NUMBER") "CAP000043636")
        (field (name "DB_VALUE") "10uF")
        (field (name "DB_TOLERANCE") "10%")
        (field (name "DB_VOLTAGE") "16V")
        (field (name "DB_MANUFACTURER_PART") "KEMET    C0805C106K4PAC")
        (field (name "DB_APPROVED_BY") "ISHIDDEN=T")
      )
      (libsource (lib "Database_Libs1") (part "C"))
    )
    (comp (ref "C442")
      (value "10uF")
      (footprint "SMD_0805_CAPC2012X145N")
      (fields
        (field (name "DB_PART_NUMBER") "CAP000043636")
        (field (name "DB_VALUE") "10uF")
        (field (name "DB_TOLERANCE") "10%")
        (field (name "DB_VOLTAGE") "16V")
        (field (name "DB_MANUFACTURER_PART") "KEMET    C0805C106K4PAC")
        (field (name "DB_APPROVED_BY") "ISHIDDEN=T")
      )
      (libsource (lib "Database_Libs1") (part "C"))
    )
    (comp (ref "C443")
      (value "10uF")
      (footprint "SMD_0805_CAPC2012X145N")
      (fields
        (field (name "DB_PART_NUMBER") "CAP000043636")
        (field (name "DB_VALUE") "10uF")
        (field (name "DB_TOLERANCE") "10%")
        (field (name "DB_VOLTAGE") "16V")
        (field (name "DB_MANUFACTURER_PART") "KEMET    C0805C106K4PAC")
        (field (name "DB_APPROVED_BY") "ISHIDDEN=T")
      )
      (libsource (lib "Database_Libs1") (part "C"))
    )
    (comp (ref "C444")
      (value "22uF")
      (footprint "SMD_0805_CAPC2012X145N")
      (fields
        (field (name "DB_PART_NUMBER") "CAP000043686")
        (field (name "DB_VALUE") "22uF")
        (field (name "DB_TOLERANCE") "20%")
        (field (name "DB_VOLTAGE") "6.3V")
        (field (name "DB_MANUFACTURER_PART") "KEMET    C0805C226M9PAC")
        (field (name "DB_APPROVED_BY") "ISHIDDEN=T")
      )
      (libsource (lib "Database_Libs1") (part "C"))
    )
    (comp (ref "C445")
      (value "22uF")
      (footprint "SMD_0805_CAPC2012X145N")
      (fields
        (field (name "DB_PART_NUMBER") "CAP000043686")
        (field (name "DB_VALUE") "22uF")
        (field (name "DB_TOLERANCE") "20%")
        (field (name "DB_VOLTAGE") "6.3V")
        (field (name "DB_MANUFACTURER_PART") "KEMET    C0805C226M9PAC")
        (field (name "DB_APPROVED_BY") "ISHIDDEN=T")
      )
      (libsource (lib "Database_Libs1") (part "C"))
    )
    (comp (ref "C446")
      (value "22uF")
      (footprint "SMD_0805_CAPC2012X145N")
      (fields
        (field (name "DB_PART_NUMBER") "CAP000043686")
        (field (name "DB_VALUE") "22uF")
        (field (name "DB_TOLERANCE") "20%")
        (field (name "DB_VOLTAGE") "6.3V")
        (field (name "DB_MANUFACTURER_PART") "KEMET    C0805C226M9PAC")
        (field (name "DB_APPROVED_BY") "ISHIDDEN=T")
      )
      (libsource (lib "Database_Libs1") (part "C"))
    )
    (comp (ref "C447")
      (value "22uF")
      (footprint "SMD_0805_CAPC2012X145N")
      (fields
        (field (name "DB_PART_NUMBER") "CAP000043686")
        (field (name "DB_VALUE") "22uF")
        (field (name "DB_TOLERANCE") "20%")
        (field (name "DB_VOLTAGE") "6.3V")
        (field (name "DB_MANUFACTURER_PART") "KEMET    C0805C226M9PAC")
        (field (name "DB_APPROVED_BY") "ISHIDDEN=T")
      )
      (libsource (lib "Database_Libs1") (part "C"))
    )
    (comp (ref "C448")
      (value "22uF")
      (footprint "SMD_0805_CAPC2012X145N")
      (fields
        (field (name "DB_PART_NUMBER") "CAP000043686")
        (field (name "DB_VALUE") "22uF")
        (field (name "DB_TOLERANCE") "20%")
        (field (name "DB_VOLTAGE") "6.3V")
        (field (name "DB_MANUFACTURER_PART") "KEMET    C0805C226M9PAC")
        (field (name "DB_APPROVED_BY") "ISHIDDEN=T")
      )
      (libsource (lib "Database_Libs1") (part "C"))
    )
    (comp (ref "C449")
      (value "22uF")
      (footprint "SMD_0805_CAPC2012X145N")
      (fields
        (field (name "DB_PART_NUMBER") "CAP000043686")
        (field (name "DB_VALUE") "22uF")
        (field (name "DB_TOLERANCE") "20%")
        (field (name "DB_VOLTAGE") "6.3V")
        (field (name "DB_MANUFACTURER_PART") "KEMET    C0805C226M9PAC")
        (field (name "DB_APPROVED_BY") "ISHIDDEN=T")
      )
      (libsource (lib "Database_Libs1") (part "C"))
    )
    (comp (ref "C450")
      (value "22uF")
      (footprint "SMD_0805_CAPC2012X145N")
      (fields
        (field (name "DB_PART_NUMBER") "CAP000043686")
        (field (name "DB_VALUE") "22uF")
        (field (name "DB_TOLERANCE") "20%")
        (field (name "DB_VOLTAGE") "6.3V")
        (field (name "DB_MANUFACTURER_PART") "KEMET    C0805C226M9PAC")
        (field (name "DB_APPROVED_BY") "ISHIDDEN=T")
      )
      (libsource (lib "Database_Libs1") (part "C"))
    )
    (comp (ref "C451")
      (value "22uF")
      (footprint "SMD_0805_CAPC2012X145N")
      (fields
        (field (name "DB_PART_NUMBER") "CAP000043686")
        (field (name "DB_VALUE") "22uF")
        (field (name "DB_TOLERANCE") "20%")
        (field (name "DB_VOLTAGE") "6.3V")
        (field (name "DB_MANUFACTURER_PART") "KEMET    C0805C226M9PAC")
        (field (name "DB_APPROVED_BY") "ISHIDDEN=T")
      )
      (libsource (lib "Database_Libs1") (part "C"))
    )
    (comp (ref "C452")
      (value "22uF")
      (footprint "SMD_0805_CAPC2012X145N")
      (fields
        (field (name "DB_PART_NUMBER") "CAP000043686")
        (field (name "DB_VALUE") "22uF")
        (field (name "DB_TOLERANCE") "20%")
        (field (name "DB_VOLTAGE") "6.3V")
        (field (name "DB_MANUFACTURER_PART") "KEMET    C0805C226M9PAC")
        (field (name "DB_APPROVED_BY") "ISHIDDEN=T")
      )
      (libsource (lib "Database_Libs1") (part "C"))
    )
    (comp (ref "C453")
      (value "22uF")
      (footprint "SMD_0805_CAPC2012X145N")
      (fields
        (field (name "DB_PART_NUMBER") "CAP000043686")
        (field (name "DB_VALUE") "22uF")
        (field (name "DB_TOLERANCE") "20%")
        (field (name "DB_VOLTAGE") "6.3V")
        (field (name "DB_MANUFACTURER_PART") "KEMET    C0805C226M9PAC")
        (field (name "DB_APPROVED_BY") "ISHIDDEN=T")
      )
      (libsource (lib "Database_Libs1") (part "C"))
    )
    (comp (ref "C454")
      (value "22uF")
      (footprint "SMD_0805_CAPC2012X145N")
      (fields
        (field (name "DB_PART_NUMBER") "CAP000043686")
        (field (name "DB_VALUE") "22uF")
        (field (name "DB_TOLERANCE") "20%")
        (field (name "DB_VOLTAGE") "6.3V")
        (field (name "DB_MANUFACTURER_PART") "KEMET    C0805C226M9PAC")
        (field (name "DB_APPROVED_BY") "ISHIDDEN=T")
      )
      (libsource (lib "Database_Libs1") (part "C"))
    )
    (comp (ref "C455")
      (value "22uF")
      (footprint "SMD_0805_CAPC2012X145N")
      (fields
        (field (name "DB_PART_NUMBER") "CAP000043686")
        (field (name "DB_VALUE") "22uF")
        (field (name "DB_TOLERANCE") "20%")
        (field (name "DB_VOLTAGE") "6.3V")
        (field (name "DB_MANUFACTURER_PART") "KEMET    C0805C226M9PAC")
        (field (name "DB_APPROVED_BY") "ISHIDDEN=T")
      )
      (libsource (lib "Database_Libs1") (part "C"))
    )
    (comp (ref "C456")
      (value "22uF")
      (footprint "SMD_0805_CAPC2012X145N")
      (fields
        (field (name "DB_PART_NUMBER") "CAP000043686")
        (field (name "DB_VALUE") "22uF")
        (field (name "DB_TOLERANCE") "20%")
        (field (name "DB_VOLTAGE") "6.3V")
        (field (name "DB_MANUFACTURER_PART") "KEMET    C0805C226M9PAC")
        (field (name "DB_APPROVED_BY") "ISHIDDEN=T")
      )
      (libsource (lib "Database_Libs1") (part "C"))
    )
    (comp (ref "C457")
      (value "22uF")
      (footprint "SMD_0805_CAPC2012X145N")
      (fields
        (field (name "DB_PART_NUMBER") "CAP000043686")
        (field (name "DB_VALUE") "22uF")
        (field (name "DB_TOLERANCE") "20%")
        (field (name "DB_VOLTAGE") "6.3V")
        (field (name "DB_MANUFACTURER_PART") "KEMET    C0805C226M9PAC")
        (field (name "DB_APPROVED_BY") "ISHIDDEN=T")
      )
      (libsource (lib "Database_Libs1") (part "C"))
    )
    (comp (ref "C458")
      (value "22uF")
      (footprint "SMD_0805_CAPC2012X145N")
      (fields
        (field (name "DB_PART_NUMBER") "CAP000043686")
        (field (name "DB_VALUE") "22uF")
        (field (name "DB_TOLERANCE") "20%")
        (field (name "DB_VOLTAGE") "6.3V")
        (field (name "DB_MANUFACTURER_PART") "KEMET    C0805C226M9PAC")
        (field (name "DB_APPROVED_BY") "ISHIDDEN=T")
      )
      (libsource (lib "Database_Libs1") (part "C"))
    )
    (comp (ref "C459")
      (value "22uF")
      (footprint "SMD_0805_CAPC2012X145N")
      (fields
        (field (name "DB_PART_NUMBER") "CAP000043686")
        (field (name "DB_VALUE") "22uF")
        (field (name "DB_TOLERANCE") "20%")
        (field (name "DB_VOLTAGE") "6.3V")
        (field (name "DB_MANUFACTURER_PART") "KEMET    C0805C226M9PAC")
        (field (name "DB_APPROVED_BY") "ISHIDDEN=T")
      )
      (libsource (lib "Database_Libs1") (part "C"))
    )
    (comp (ref "C460")
      (value "22uF")
      (footprint "SMD_0805_CAPC2012X145N")
      (fields
        (field (name "DB_PART_NUMBER") "CAP000043686")
        (field (name "DB_VALUE") "22uF")
        (field (name "DB_TOLERANCE") "20%")
        (field (name "DB_VOLTAGE") "6.3V")
        (field (name "DB_MANUFACTURER_PART") "KEMET    C0805C226M9PAC")
        (field (name "DB_APPROVED_BY") "ISHIDDEN=T")
      )
      (libsource (lib "Database_Libs1") (part "C"))
    )
    (comp (ref "C461")
      (value "22uF")
      (footprint "SMD_0805_CAPC2012X145N")
      (fields
        (field (name "DB_PART_NUMBER") "CAP000043686")
        (field (name "DB_VALUE") "22uF")
        (field (name "DB_TOLERANCE") "20%")
        (field (name "DB_VOLTAGE") "6.3V")
        (field (name "DB_MANUFACTURER_PART") "KEMET    C0805C226M9PAC")
        (field (name "DB_APPROVED_BY") "ISHIDDEN=T")
      )
      (libsource (lib "Database_Libs1") (part "C"))
    )
    (comp (ref "C462")
      (value "22uF")
      (footprint "SMD_0805_CAPC2012X145N")
      (fields
        (field (name "DB_PART_NUMBER") "CAP000043686")
        (field (name "DB_VALUE") "22uF")
        (field (name "DB_TOLERANCE") "20%")
        (field (name "DB_VOLTAGE") "6.3V")
        (field (name "DB_MANUFACTURER_PART") "KEMET    C0805C226M9PAC")
        (field (name "DB_APPROVED_BY") "ISHIDDEN=T")
      )
      (libsource (lib "Database_Libs1") (part "C"))
    )
    (comp (ref "C463")
      (value "22uF")
      (footprint "SMD_0805_CAPC2012X145N")
      (fields
        (field (name "DB_PART_NUMBER") "CAP000043686")
        (field (name "DB_VALUE") "22uF")
        (field (name "DB_TOLERANCE") "20%")
        (field (name "DB_VOLTAGE") "6.3V")
        (field (name "DB_MANUFACTURER_PART") "KEMET    C0805C226M9PAC")
        (field (name "DB_APPROVED_BY") "ISHIDDEN=T")
      )
      (libsource (lib "Database_Libs1") (part "C"))
    )
    (comp (ref "C464")
      (value "22uF")
      (footprint "SMD_0805_CAPC2012X145N")
      (fields
        (field (name "DB_PART_NUMBER") "CAP000043686")
        (field (name "DB_VALUE") "22uF")
        (field (name "DB_TOLERANCE") "20%")
        (field (name "DB_VOLTAGE") "6.3V")
        (field (name "DB_MANUFACTURER_PART") "KEMET    C0805C226M9PAC")
        (field (name "DB_APPROVED_BY") "ISHIDDEN=T")
      )
      (libsource (lib "Database_Libs1") (part "C"))
    )
    (comp (ref "C465")
      (value "22uF")
      (footprint "SMD_0805_CAPC2012X145N")
      (fields
        (field (name "DB_PART_NUMBER") "CAP000043686")
        (field (name "DB_VALUE") "22uF")
        (field (name "DB_TOLERANCE") "20%")
        (field (name "DB_VOLTAGE") "6.3V")
        (field (name "DB_MANUFACTURER_PART") "KEMET    C0805C226M9PAC")
        (field (name "DB_APPROVED_BY") "ISHIDDEN=T")
      )
      (libsource (lib "Database_Libs1") (part "C"))
    )
    (comp (ref "C466")
      (value "22uF")
      (footprint "SMD_0805_CAPC2012X145N")
      (fields
        (field (name "DB_PART_NUMBER") "CAP000043686")
        (field (name "DB_VALUE") "22uF")
        (field (name "DB_TOLERANCE") "20%")
        (field (name "DB_VOLTAGE") "6.3V")
        (field (name "DB_MANUFACTURER_PART") "KEMET    C0805C226M9PAC")
        (field (name "DB_APPROVED_BY") "ISHIDDEN=T")
      )
      (libsource (lib "Database_Libs1") (part "C"))
    )
    (comp (ref "C467")
      (value "22uF")
      (footprint "SMD_0805_CAPC2012X145N")
      (fields
        (field (name "DB_PART_NUMBER") "CAP000043686")
        (field (name "DB_VALUE") "22uF")
        (field (name "DB_TOLERANCE") "20%")
        (field (name "DB_VOLTAGE") "6.3V")
        (field (name "DB_MANUFACTURER_PART") "KEMET    C0805C226M9PAC")
        (field (name "DB_APPROVED_BY") "ISHIDDEN=T")
      )
      (libsource (lib "Database_Libs1") (part "C"))
    )
    (comp (ref "C468")
      (value "22uF")
      (footprint "SMD_0805_CAPC2012X145N")
      (fields
        (field (name "DB_PART_NUMBER") "CAP000043686")
        (field (name "DB_VALUE") "22uF")
        (field (name "DB_TOLERANCE") "20%")
        (field (name "DB_VOLTAGE") "6.3V")
        (field (name "DB_MANUFACTURER_PART") "KEMET    C0805C226M9PAC")
        (field (name "DB_APPROVED_BY") "ISHIDDEN=T")
      )
      (libsource (lib "Database_Libs1") (part "C"))
    )
    (comp (ref "C469")
      (value "22uF")
      (footprint "SMD_0805_CAPC2012X145N")
      (fields
        (field (name "DB_PART_NUMBER") "CAP000043686")
        (field (name "DB_VALUE") "22uF")
        (field (name "DB_TOLERANCE") "20%")
        (field (name "DB_VOLTAGE") "6.3V")
        (field (name "DB_MANUFACTURER_PART") "KEMET    C0805C226M9PAC")
        (field (name "DB_APPROVED_BY") "ISHIDDEN=T")
      )
      (libsource (lib "Database_Libs1") (part "C"))
    )
    (comp (ref "C470")
      (value "22uF")
      (footprint "SMD_0805_CAPC2012X145N")
      (fields
        (field (name "DB_PART_NUMBER") "CAP000043686")
        (field (name "DB_VALUE") "22uF")
        (field (name "DB_TOLERANCE") "20%")
        (field (name "DB_VOLTAGE") "6.3V")
        (field (name "DB_MANUFACTURER_PART") "KEMET    C0805C226M9PAC")
        (field (name "DB_APPROVED_BY") "ISHIDDEN=T")
      )
      (libsource (lib "Database_Libs1") (part "C"))
    )
    (comp (ref "C471")
      (value "22uF")
      (footprint "SMD_0805_CAPC2012X145N")
      (fields
        (field (name "DB_PART_NUMBER") "CAP000043686")
        (field (name "DB_VALUE") "22uF")
        (field (name "DB_TOLERANCE") "20%")
        (field (name "DB_VOLTAGE") "6.3V")
        (field (name "DB_MANUFACTURER_PART") "KEMET    C0805C226M9PAC")
        (field (name "DB_APPROVED_BY") "ISHIDDEN=T")
      )
      (libsource (lib "Database_Libs1") (part "C"))
    )
    (comp (ref "C472")
      (value "22uF")
      (footprint "SMD_0805_CAPC2012X145N")
      (fields
        (field (name "DB_PART_NUMBER") "CAP000043686")
        (field (name "DB_VALUE") "22uF")
        (field (name "DB_TOLERANCE") "20%")
        (field (name "DB_VOLTAGE") "6.3V")
        (field (name "DB_MANUFACTURER_PART") "KEMET    C0805C226M9PAC")
        (field (name "DB_APPROVED_BY") "ISHIDDEN=T")
      )
      (libsource (lib "Database_Libs1") (part "C"))
    )
    (comp (ref "C473")
      (value "22uF")
      (footprint "SMD_0805_CAPC2012X145N")
      (fields
        (field (name "DB_PART_NUMBER") "CAP000043686")
        (field (name "DB_VALUE") "22uF")
        (field (name "DB_TOLERANCE") "20%")
        (field (name "DB_VOLTAGE") "6.3V")
        (field (name "DB_MANUFACTURER_PART") "KEMET    C0805C226M9PAC")
        (field (name "DB_APPROVED_BY") "ISHIDDEN=T")
      )
      (libsource (lib "Database_Libs1") (part "C"))
    )
    (comp (ref "C474")
      (value "22uF")
      (footprint "SMD_0805_CAPC2012X145N")
      (fields
        (field (name "DB_PART_NUMBER") "CAP000043686")
        (field (name "DB_VALUE") "22uF")
        (field (name "DB_TOLERANCE") "20%")
        (field (name "DB_VOLTAGE") "6.3V")
        (field (name "DB_MANUFACTURER_PART") "KEMET    C0805C226M9PAC")
        (field (name "DB_APPROVED_BY") "ISHIDDEN=T")
      )
      (libsource (lib "Database_Libs1") (part "C"))
    )
    (comp (ref "C475")
      (value "22uF")
      (footprint "SMD_0805_CAPC2012X145N")
      (fields
        (field (name "DB_PART_NUMBER") "CAP000043686")
        (field (name "DB_VALUE") "22uF")
        (field (name "DB_TOLERANCE") "20%")
        (field (name "DB_VOLTAGE") "6.3V")
        (field (name "DB_MANUFACTURER_PART") "KEMET    C0805C226M9PAC")
        (field (name "DB_APPROVED_BY") "ISHIDDEN=T")
      )
      (libsource (lib "Database_Libs1") (part "C"))
    )
    (comp (ref "C476")
      (value "22uF")
      (footprint "SMD_0805_CAPC2012X145N")
      (fields
        (field (name "DB_PART_NUMBER") "CAP000043686")
        (field (name "DB_VALUE") "22uF")
        (field (name "DB_TOLERANCE") "20%")
        (field (name "DB_VOLTAGE") "6.3V")
        (field (name "DB_MANUFACTURER_PART") "KEMET    C0805C226M9PAC")
        (field (name "DB_APPROVED_BY") "ISHIDDEN=T")
      )
      (libsource (lib "Database_Libs1") (part "C"))
    )
    (comp (ref "C477")
      (value "22uF")
      (footprint "SMD_0805_CAPC2012X145N")
      (fields
        (field (name "DB_PART_NUMBER") "CAP000043686")
        (field (name "DB_VALUE") "22uF")
        (field (name "DB_TOLERANCE") "20%")
        (field (name "DB_VOLTAGE") "6.3V")
        (field (name "DB_MANUFACTURER_PART") "KEMET    C0805C226M9PAC")
        (field (name "DB_APPROVED_BY") "ISHIDDEN=T")
      )
      (libsource (lib "Database_Libs1") (part "C"))
    )
    (comp (ref "C478")
      (value "22uF")
      (footprint "SMD_0805_CAPC2012X145N")
      (fields
        (field (name "DB_PART_NUMBER") "CAP000043686")
        (field (name "DB_VALUE") "22uF")
        (field (name "DB_TOLERANCE") "20%")
        (field (name "DB_VOLTAGE") "6.3V")
        (field (name "DB_MANUFACTURER_PART") "KEMET    C0805C226M9PAC")
        (field (name "DB_APPROVED_BY") "ISHIDDEN=T")
      )
      (libsource (lib "Database_Libs1") (part "C"))
    )
    (comp (ref "C479")
      (value "22uF")
      (footprint "SMD_0805_CAPC2012X145N")
      (fields
        (field (name "DB_PART_NUMBER") "CAP000043686")
        (field (name "DB_VALUE") "22uF")
        (field (name "DB_TOLERANCE") "20%")
        (field (name "DB_VOLTAGE") "6.3V")
        (field (name "DB_MANUFACTURER_PART") "KEMET    C0805C226M9PAC")
        (field (name "DB_APPROVED_BY") "ISHIDDEN=T")
      )
      (libsource (lib "Database_Libs1") (part "C"))
    )
    (comp (ref "C480")
      (value "22uF")
      (footprint "SMD_0805_CAPC2012X145N")
      (fields
        (field (name "DB_PART_NUMBER") "CAP000043686")
        (field (name "DB_VALUE") "22uF")
        (field (name "DB_TOLERANCE") "20%")
        (field (name "DB_VOLTAGE") "6.3V")
        (field (name "DB_MANUFACTURER_PART") "KEMET    C0805C226M9PAC")
        (field (name "DB_APPROVED_BY") "ISHIDDEN=T")
      )
      (libsource (lib "Database_Libs1") (part "C"))
    )
    (comp (ref "C481")
      (value "22uF")
      (footprint "SMD_0805_CAPC2012X145N")
      (fields
        (field (name "DB_PART_NUMBER") "CAP000043686")
        (field (name "DB_VALUE") "22uF")
        (field (name "DB_TOLERANCE") "20%")
        (field (name "DB_VOLTAGE") "6.3V")
        (field (name "DB_MANUFACTURER_PART") "KEMET    C0805C226M9PAC")
        (field (name "DB_APPROVED_BY") "ISHIDDEN=T")
      )
      (libsource (lib "Database_Libs1") (part "C"))
    )
    (comp (ref "C482")
      (value "22uF")
      (footprint "SMD_0805_CAPC2012X145N")
      (fields
        (field (name "DB_PART_NUMBER") "CAP000043686")
        (field (name "DB_VALUE") "22uF")
        (field (name "DB_TOLERANCE") "20%")
        (field (name "DB_VOLTAGE") "6.3V")
        (field (name "DB_MANUFACTURER_PART") "KEMET    C0805C226M9PAC")
        (field (name "DB_APPROVED_BY") "ISHIDDEN=T")
      )
      (libsource (lib "Database_Libs1") (part "C"))
    )
    (comp (ref "C483")
      (value "22uF")
      (footprint "SMD_0805_CAPC2012X145N")
      (fields
        (field (name "DB_PART_NUMBER") "CAP000043686")
        (field (name "DB_VALUE") "22uF")
        (field (name "DB_TOLERANCE") "20%")
        (field (name "DB_VOLTAGE") "6.3V")
        (field (name "DB_MANUFACTURER_PART") "KEMET    C0805C226M9PAC")
        (field (name "DB_APPROVED_BY") "ISHIDDEN=T")
      )
      (libsource (lib "Database_Libs1") (part "C"))
    )
    (comp (ref "C484")
      (value "22uF")
      (footprint "SMD_0805_CAPC2012X145N")
      (fields
        (field (name "DB_PART_NUMBER") "CAP000043686")
        (field (name "DB_VALUE") "22uF")
        (field (name "DB_TOLERANCE") "20%")
        (field (name "DB_VOLTAGE") "6.3V")
        (field (name "DB_MANUFACTURER_PART") "KEMET    C0805C226M9PAC")
        (field (name "DB_APPROVED_BY") "ISHIDDEN=T")
      )
      (libsource (lib "Database_Libs1") (part "C"))
    )
    (comp (ref "C485")
      (value "22uF")
      (footprint "SMD_0805_CAPC2012X145N")
      (fields
        (field (name "DB_PART_NUMBER") "CAP000043686")
        (field (name "DB_VALUE") "22uF")
        (field (name "DB_TOLERANCE") "20%")
        (field (name "DB_VOLTAGE") "6.3V")
        (field (name "DB_MANUFACTURER_PART") "KEMET    C0805C226M9PAC")
        (field (name "DB_APPROVED_BY") "ISHIDDEN=T")
      )
      (libsource (lib "Database_Libs1") (part "C"))
    )
    (comp (ref "C486")
      (value "22uF")
      (footprint "SMD_0805_CAPC2012X145N")
      (fields
        (field (name "DB_PART_NUMBER") "CAP000043686")
        (field (name "DB_VALUE") "22uF")
        (field (name "DB_TOLERANCE") "20%")
        (field (name "DB_VOLTAGE") "6.3V")
        (field (name "DB_MANUFACTURER_PART") "KEMET    C0805C226M9PAC")
        (field (name "DB_APPROVED_BY") "ISHIDDEN=T")
      )
      (libsource (lib "Database_Libs1") (part "C"))
    )
    (comp (ref "C487")
      (value "22uF")
      (footprint "SMD_0805_CAPC2012X145N")
      (fields
        (field (name "DB_PART_NUMBER") "CAP000043686")
        (field (name "DB_VALUE") "22uF")
        (field (name "DB_TOLERANCE") "20%")
        (field (name "DB_VOLTAGE") "6.3V")
        (field (name "DB_MANUFACTURER_PART") "KEMET    C0805C226M9PAC")
        (field (name "DB_APPROVED_BY") "ISHIDDEN=T")
      )
      (libsource (lib "Database_Libs1") (part "C"))
    )
    (comp (ref "C488")
      (value "22uF")
      (footprint "SMD_0805_CAPC2012X145N")
      (fields
        (field (name "DB_PART_NUMBER") "CAP000043686")
        (field (name "DB_VALUE") "22uF")
        (field (name "DB_TOLERANCE") "20%")
        (field (name "DB_VOLTAGE") "6.3V")
        (field (name "DB_MANUFACTURER_PART") "KEMET    C0805C226M9PAC")
        (field (name "DB_APPROVED_BY") "ISHIDDEN=T")
      )
      (libsource (lib "Database_Libs1") (part "C"))
    )
    (comp (ref "C489")
      (value "22uF")
      (footprint "SMD_0805_CAPC2012X145N")
      (fields
        (field (name "DB_PART_NUMBER") "CAP000043686")
        (field (name "DB_VALUE") "22uF")
        (field (name "DB_TOLERANCE") "20%")
        (field (name "DB_VOLTAGE") "6.3V")
        (field (name "DB_MANUFACTURER_PART") "KEMET    C0805C226M9PAC")
        (field (name "DB_APPROVED_BY") "ISHIDDEN=T")
      )
      (libsource (lib "Database_Libs1") (part "C"))
    )
    (comp (ref "C490")
      (value "22uF")
      (footprint "SMD_0805_CAPC2012X145N")
      (fields
        (field (name "DB_PART_NUMBER") "CAP000043686")
        (field (name "DB_VALUE") "22uF")
        (field (name "DB_TOLERANCE") "20%")
        (field (name "DB_VOLTAGE") "6.3V")
        (field (name "DB_MANUFACTURER_PART") "KEMET    C0805C226M9PAC")
        (field (name "DB_APPROVED_BY") "ISHIDDEN=T")
      )
      (libsource (lib "Database_Libs1") (part "C"))
    )
    (comp (ref "C491")
      (value "22uF")
      (footprint "SMD_0805_CAPC2012X145N")
      (fields
        (field (name "DB_PART_NUMBER") "CAP000043686")
        (field (name "DB_VALUE") "22uF")
        (field (name "DB_TOLERANCE") "20%")
        (field (name "DB_VOLTAGE") "6.3V")
        (field (name "DB_MANUFACTURER_PART") "KEMET    C0805C226M9PAC")
        (field (name "DB_APPROVED_BY") "ISHIDDEN=T")
      )
      (libsource (lib "Database_Libs1") (part "C"))
    )
    (comp (ref "C593")
      (value "100uF")
      (footprint "SMD_1210_CAPC3225X270N")
      (fields
        (field (name "DB_PART_NUMBER") "TMP-2512")
        (field (name "DB_VALUE") "100uF")
        (field (name "DB_TOLERANCE") "20%")
        (field (name "DB_VOLTAGE") "16V")
        (field (name "DB_MANUFACTURER_PART") "YAGEO    CC1210MRX5R7BB107")
      )
      (libsource (lib "Database_Libs1") (part "C"))
    )
    (comp (ref "C596")
      (value "100uF")
      (footprint "SMD_1210_CAPC3225X270N")
      (fields
        (field (name "DB_PART_NUMBER") "TMP-2512")
        (field (name "DB_VALUE") "100uF")
        (field (name "DB_TOLERANCE") "20%")
        (field (name "DB_VOLTAGE") "16V")
        (field (name "DB_MANUFACTURER_PART") "YAGEO    CC1210MRX5R7BB107")
      )
      (libsource (lib "Database_Libs1") (part "C"))
    )
    (comp (ref "C598")
      (value "10uF")
      (footprint "SMD_0805_CAPC2012X145N")
      (fields
        (field (name "DB_PART_NUMBER") "CAP000043636")
        (field (name "DB_VALUE") "10uF")
        (field (name "DB_TOLERANCE") "10%")
        (field (name "DB_VOLTAGE") "16V")
        (field (name "DB_MANUFACTURER_PART") "KEMET    C0805C106K4PAC")
        (field (name "DB_APPROVED_BY") "ISHIDDEN=T")
      )
      (libsource (lib "Database_Libs1") (part "C"))
    )
    (comp (ref "C599")
      (value "100uF")
      (footprint "SMD_1210_CAPC3225X270N")
      (fields
        (field (name "DB_PART_NUMBER") "TMP-2512")
        (field (name "DB_VALUE") "100uF")
        (field (name "DB_TOLERANCE") "20%")
        (field (name "DB_VOLTAGE") "16V")
        (field (name "DB_MANUFACTURER_PART") "YAGEO    CC1210MRX5R7BB107")
      )
      (libsource (lib "Database_Libs1") (part "C"))
    )
    (comp (ref "C600")
      (value "10uF")
      (footprint "SMD_0805_CAPC2012X145N")
      (fields
        (field (name "DB_PART_NUMBER") "CAP000043636")
        (field (name "DB_VALUE") "10uF")
        (field (name "DB_TOLERANCE") "10%")
        (field (name "DB_VOLTAGE") "16V")
        (field (name "DB_MANUFACTURER_PART") "KEMET    C0805C106K4PAC")
        (field (name "DB_APPROVED_BY") "ISHIDDEN=T")
      )
      (libsource (lib "Database_Libs1") (part "C"))
    )
    (comp (ref "C602")
      (value "100uF")
      (footprint "SMD_1210_CAPC3225X270N")
      (fields
        (field (name "DB_PART_NUMBER") "TMP-2512")
        (field (name "DB_VALUE") "100uF")
        (field (name "DB_TOLERANCE") "20%")
        (field (name "DB_VOLTAGE") "16V")
        (field (name "DB_MANUFACTURER_PART") "YAGEO    CC1210MRX5R7BB107")
      )
      (libsource (lib "Database_Libs1") (part "C"))
    )
    (comp (ref "C603")
      (value "10uF")
      (footprint "SMD_0805_CAPC2012X145N")
      (fields
        (field (name "DB_PART_NUMBER") "CAP000043636")
        (field (name "DB_VALUE") "10uF")
        (field (name "DB_TOLERANCE") "10%")
        (field (name "DB_VOLTAGE") "16V")
        (field (name "DB_MANUFACTURER_PART") "KEMET    C0805C106K4PAC")
        (field (name "DB_APPROVED_BY") "ISHIDDEN=T")
      )
      (libsource (lib "Database_Libs1") (part "C"))
    )
    (comp (ref "C605")
      (value "100uF")
      (footprint "SMD_1210_CAPC3225X270N")
      (fields
        (field (name "DB_PART_NUMBER") "TMP-2512")
        (field (name "DB_VALUE") "100uF")
        (field (name "DB_TOLERANCE") "20%")
        (field (name "DB_VOLTAGE") "16V")
        (field (name "DB_MANUFACTURER_PART") "YAGEO    CC1210MRX5R7BB107")
      )
      (libsource (lib "Database_Libs1") (part "C"))
    )
    (comp (ref "C606")
      (value "10uF")
      (footprint "SMD_0805_CAPC2012X145N")
      (fields
        (field (name "DB_PART_NUMBER") "CAP000043636")
        (field (name "DB_VALUE") "10uF")
        (field (name "DB_TOLERANCE") "10%")
        (field (name "DB_VOLTAGE") "16V")
        (field (name "DB_MANUFACTURER_PART") "KEMET    C0805C106K4PAC")
        (field (name "DB_APPROVED_BY") "ISHIDDEN=T")
      )
      (libsource (lib "Database_Libs1") (part "C"))
    )
    (comp (ref "C640")
      (value "10uF")
      (footprint "SMD_0805_CAPC2012X145N")
      (fields
        (field (name "DB_PART_NUMBER") "CAP000043636")
        (field (name "DB_VALUE") "10uF")
        (field (name "DB_TOLERANCE") "10%")
        (field (name "DB_VOLTAGE") "16V")
        (field (name "DB_MANUFACTURER_PART") "KEMET    C0805C106K4PAC")
        (field (name "DB_APPROVED_BY") "ISHIDDEN=T")
      )
      (libsource (lib "Database_Libs1") (part "C"))
    )
    (comp (ref "C642")
      (value "10uF")
      (footprint "SMD_0805_CAPC2012X145N")
      (fields
        (field (name "DB_PART_NUMBER") "CAP000043636")
        (field (name "DB_VALUE") "10uF")
        (field (name "DB_TOLERANCE") "10%")
        (field (name "DB_VOLTAGE") "16V")
        (field (name "DB_MANUFACTURER_PART") "KEMET    C0805C106K4PAC")
        (field (name "DB_APPROVED_BY") "ISHIDDEN=T")
      )
      (libsource (lib "Database_Libs1") (part "C"))
    )
    (comp (ref "C643")
      (value "10uF")
      (footprint "SMD_0805_CAPC2012X145N")
      (fields
        (field (name "DB_PART_NUMBER") "CAP000043636")
        (field (name "DB_VALUE") "10uF")
        (field (name "DB_TOLERANCE") "10%")
        (field (name "DB_VOLTAGE") "16V")
        (field (name "DB_MANUFACTURER_PART") "KEMET    C0805C106K4PAC")
        (field (name "DB_APPROVED_BY") "ISHIDDEN=T")
      )
      (libsource (lib "Database_Libs1") (part "C"))
    )
    (comp (ref "C645")
      (value "10uF")
      (footprint "SMD_0805_CAPC2012X145N")
      (fields
        (field (name "DB_PART_NUMBER") "CAP000043636")
        (field (name "DB_VALUE") "10uF")
        (field (name "DB_TOLERANCE") "10%")
        (field (name "DB_VOLTAGE") "16V")
        (field (name "DB_MANUFACTURER_PART") "KEMET    C0805C106K4PAC")
        (field (name "DB_APPROVED_BY") "ISHIDDEN=T")
      )
      (libsource (lib "Database_Libs1") (part "C"))
    )
    (comp (ref "C646")
      (value "10uF")
      (footprint "SMD_0805_CAPC2012X145N")
      (fields
        (field (name "DB_PART_NUMBER") "CAP000043636")
        (field (name "DB_VALUE") "10uF")
        (field (name "DB_TOLERANCE") "10%")
        (field (name "DB_VOLTAGE") "16V")
        (field (name "DB_MANUFACTURER_PART") "KEMET    C0805C106K4PAC")
        (field (name "DB_APPROVED_BY") "ISHIDDEN=T")
      )
      (libsource (lib "Database_Libs1") (part "C"))
    )
    (comp (ref "C652")
      (value "22uF")
      (footprint "SMD_0805_CAPC2012X145N")
      (fields
        (field (name "DB_PART_NUMBER") "CAP000043686")
        (field (name "DB_VALUE") "22uF")
        (field (name "DB_TOLERANCE") "20%")
        (field (name "DB_VOLTAGE") "6.3V")
        (field (name "DB_MANUFACTURER_PART") "KEMET    C0805C226M9PAC")
        (field (name "DB_APPROVED_BY") "ISHIDDEN=T")
      )
      (libsource (lib "Database_Libs1") (part "C"))
    )
    (comp (ref "C653")
      (value "220uF")
      (footprint "SMD_1210_CAPC3225X279N")
      (fields
        (field (name "DB_PART_NUMBER") "CAP000047355")
        (field (name "DB_VALUE") "220uF")
        (field (name "DB_TOLERANCE") "20%")
        (field (name "DB_VOLTAGE") "6.3V")
        (field (name "DB_MANUFACTURER_PART") "SAMSUNG    CL32A227MQVNNNE")
        (field (name "DB_APPROVED_BY") "VSN")
      )
      (libsource (lib "Database_Libs1") (part "C"))
    )
    (comp (ref "C654")
      (value "22uF")
      (footprint "SMD_0805_CAPC2012X145N")
      (fields
        (field (name "DB_PART_NUMBER") "CAP000043686")
        (field (name "DB_VALUE") "22uF")
        (field (name "DB_TOLERANCE") "20%")
        (field (name "DB_VOLTAGE") "6.3V")
        (field (name "DB_MANUFACTURER_PART") "KEMET    C0805C226M9PAC")
        (field (name "DB_APPROVED_BY") "ISHIDDEN=T")
      )
      (libsource (lib "Database_Libs1") (part "C"))
    )
    (comp (ref "C655")
      (value "22uF")
      (footprint "SMD_0805_CAPC2012X145N")
      (fields
        (field (name "DB_PART_NUMBER") "CAP000043686")
        (field (name "DB_VALUE") "22uF")
        (field (name "DB_TOLERANCE") "20%")
        (field (name "DB_VOLTAGE") "6.3V")
        (field (name "DB_MANUFACTURER_PART") "KEMET    C0805C226M9PAC")
        (field (name "DB_APPROVED_BY") "ISHIDDEN=T")
      )
      (libsource (lib "Database_Libs1") (part "C"))
    )
    (comp (ref "C656")
      (value "220uF")
      (footprint "SMD_1210_CAPC3225X279N")
      (fields
        (field (name "DB_PART_NUMBER") "CAP000047355")
        (field (name "DB_VALUE") "220uF")
        (field (name "DB_TOLERANCE") "20%")
        (field (name "DB_VOLTAGE") "6.3V")
        (field (name "DB_MANUFACTURER_PART") "SAMSUNG    CL32A227MQVNNNE")
        (field (name "DB_APPROVED_BY") "VSN")
      )
      (libsource (lib "Database_Libs1") (part "C"))
    )
    (comp (ref "C657")
      (value "22uF")
      (footprint "SMD_0805_CAPC2012X145N")
      (fields
        (field (name "DB_PART_NUMBER") "CAP000043686")
        (field (name "DB_VALUE") "22uF")
        (field (name "DB_TOLERANCE") "20%")
        (field (name "DB_VOLTAGE") "6.3V")
        (field (name "DB_MANUFACTURER_PART") "KEMET    C0805C226M9PAC")
        (field (name "DB_APPROVED_BY") "ISHIDDEN=T")
      )
      (libsource (lib "Database_Libs1") (part "C"))
    )
    (comp (ref "C658")
      (value "22uF")
      (footprint "SMD_0805_CAPC2012X145N")
      (fields
        (field (name "DB_PART_NUMBER") "CAP000043686")
        (field (name "DB_VALUE") "22uF")
        (field (name "DB_TOLERANCE") "20%")
        (field (name "DB_VOLTAGE") "6.3V")
        (field (name "DB_MANUFACTURER_PART") "KEMET    C0805C226M9PAC")
        (field (name "DB_APPROVED_BY") "ISHIDDEN=T")
      )
      (libsource (lib "Database_Libs1") (part "C"))
    )
    (comp (ref "C659")
      (value "220uF")
      (footprint "SMD_1210_CAPC3225X279N")
      (fields
        (field (name "DB_PART_NUMBER") "CAP000047355")
        (field (name "DB_VALUE") "220uF")
        (field (name "DB_TOLERANCE") "20%")
        (field (name "DB_VOLTAGE") "6.3V")
        (field (name "DB_MANUFACTURER_PART") "SAMSUNG    CL32A227MQVNNNE")
        (field (name "DB_APPROVED_BY") "VSN")
      )
      (libsource (lib "Database_Libs1") (part "C"))
    )
    (comp (ref "C660")
      (value "22uF")
      (footprint "SMD_0805_CAPC2012X145N")
      (fields
        (field (name "DB_PART_NUMBER") "CAP000043686")
        (field (name "DB_VALUE") "22uF")
        (field (name "DB_TOLERANCE") "20%")
        (field (name "DB_VOLTAGE") "6.3V")
        (field (name "DB_MANUFACTURER_PART") "KEMET    C0805C226M9PAC")
        (field (name "DB_APPROVED_BY") "ISHIDDEN=T")
      )
      (libsource (lib "Database_Libs1") (part "C"))
    )
    (comp (ref "C661")
      (value "22uF")
      (footprint "SMD_0805_CAPC2012X145N")
      (fields
        (field (name "DB_PART_NUMBER") "CAP000043686")
        (field (name "DB_VALUE") "22uF")
        (field (name "DB_TOLERANCE") "20%")
        (field (name "DB_VOLTAGE") "6.3V")
        (field (name "DB_MANUFACTURER_PART") "KEMET    C0805C226M9PAC")
        (field (name "DB_APPROVED_BY") "ISHIDDEN=T")
      )
      (libsource (lib "Database_Libs1") (part "C"))
    )
    (comp (ref "C662")
      (value "220uF")
      (footprint "SMD_1210_CAPC3225X279N")
      (fields
        (field (name "DB_PART_NUMBER") "CAP000047355")
        (field (name "DB_VALUE") "220uF")
        (field (name "DB_TOLERANCE") "20%")
        (field (name "DB_VOLTAGE") "6.3V")
        (field (name "DB_MANUFACTURER_PART") "SAMSUNG    CL32A227MQVNNNE")
        (field (name "DB_APPROVED_BY") "VSN")
      )
      (libsource (lib "Database_Libs1") (part "C"))
    )
    (comp (ref "C663")
      (value "22uF")
      (footprint "SMD_0805_CAPC2012X145N")
      (fields
        (field (name "DB_PART_NUMBER") "CAP000043686")
        (field (name "DB_VALUE") "22uF")
        (field (name "DB_TOLERANCE") "20%")
        (field (name "DB_VOLTAGE") "6.3V")
        (field (name "DB_MANUFACTURER_PART") "KEMET    C0805C226M9PAC")
        (field (name "DB_APPROVED_BY") "ISHIDDEN=T")
      )
      (libsource (lib "Database_Libs1") (part "C"))
    )
    (comp (ref "C664")
      (value "22uF")
      (footprint "SMD_0805_CAPC2012X145N")
      (fields
        (field (name "DB_PART_NUMBER") "CAP000043686")
        (field (name "DB_VALUE") "22uF")
        (field (name "DB_TOLERANCE") "20%")
        (field (name "DB_VOLTAGE") "6.3V")
        (field (name "DB_MANUFACTURER_PART") "KEMET    C0805C226M9PAC")
        (field (name "DB_APPROVED_BY") "ISHIDDEN=T")
      )
      (libsource (lib "Database_Libs1") (part "C"))
    )
    (comp (ref "C665")
      (value "220uF")
      (footprint "SMD_1210_CAPC3225X279N")
      (fields
        (field (name "DB_PART_NUMBER") "CAP000047355")
        (field (name "DB_VALUE") "220uF")
        (field (name "DB_TOLERANCE") "20%")
        (field (name "DB_VOLTAGE") "6.3V")
        (field (name "DB_MANUFACTURER_PART") "SAMSUNG    CL32A227MQVNNNE")
        (field (name "DB_APPROVED_BY") "VSN")
      )
      (libsource (lib "Database_Libs1") (part "C"))
    )
    (comp (ref "C666")
      (value "22uF")
      (footprint "SMD_0805_CAPC2012X145N")
      (fields
        (field (name "DB_PART_NUMBER") "CAP000043686")
        (field (name "DB_VALUE") "22uF")
        (field (name "DB_TOLERANCE") "20%")
        (field (name "DB_VOLTAGE") "6.3V")
        (field (name "DB_MANUFACTURER_PART") "KEMET    C0805C226M9PAC")
        (field (name "DB_APPROVED_BY") "ISHIDDEN=T")
      )
      (libsource (lib "Database_Libs1") (part "C"))
    )
    (comp (ref "C667")
      (value "22uF")
      (footprint "SMD_0805_CAPC2012X145N")
      (fields
        (field (name "DB_PART_NUMBER") "CAP000043686")
        (field (name "DB_VALUE") "22uF")
        (field (name "DB_TOLERANCE") "20%")
        (field (name "DB_VOLTAGE") "6.3V")
        (field (name "DB_MANUFACTURER_PART") "KEMET    C0805C226M9PAC")
        (field (name "DB_APPROVED_BY") "ISHIDDEN=T")
      )
      (libsource (lib "Database_Libs1") (part "C"))
    )
    (comp (ref "C668")
      (value "220uF")
      (footprint "SMD_1210_CAPC3225X279N")
      (fields
        (field (name "DB_PART_NUMBER") "CAP000047355")
        (field (name "DB_VALUE") "220uF")
        (field (name "DB_TOLERANCE") "20%")
        (field (name "DB_VOLTAGE") "6.3V")
        (field (name "DB_MANUFACTURER_PART") "SAMSUNG    CL32A227MQVNNNE")
        (field (name "DB_APPROVED_BY") "VSN")
      )
      (libsource (lib "Database_Libs1") (part "C"))
    )
    (comp (ref "C669")
      (value "22uF")
      (footprint "SMD_0805_CAPC2012X145N")
      (fields
        (field (name "DB_PART_NUMBER") "CAP000043686")
        (field (name "DB_VALUE") "22uF")
        (field (name "DB_TOLERANCE") "20%")
        (field (name "DB_VOLTAGE") "6.3V")
        (field (name "DB_MANUFACTURER_PART") "KEMET    C0805C226M9PAC")
        (field (name "DB_APPROVED_BY") "ISHIDDEN=T")
      )
      (libsource (lib "Database_Libs1") (part "C"))
    )
    (comp (ref "C670")
      (value "22uF")
      (footprint "SMD_0805_CAPC2012X145N")
      (fields
        (field (name "DB_PART_NUMBER") "CAP000043686")
        (field (name "DB_VALUE") "22uF")
        (field (name "DB_TOLERANCE") "20%")
        (field (name "DB_VOLTAGE") "6.3V")
        (field (name "DB_MANUFACTURER_PART") "KEMET    C0805C226M9PAC")
        (field (name "DB_APPROVED_BY") "ISHIDDEN=T")
      )
      (libsource (lib "Database_Libs1") (part "C"))
    )
    (comp (ref "C671")
      (value "220uF")
      (footprint "SMD_1210_CAPC3225X279N")
      (fields
        (field (name "DB_PART_NUMBER") "CAP000047355")
        (field (name "DB_VALUE") "220uF")
        (field (name "DB_TOLERANCE") "20%")
        (field (name "DB_VOLTAGE") "6.3V")
        (field (name "DB_MANUFACTURER_PART") "SAMSUNG    CL32A227MQVNNNE")
        (field (name "DB_APPROVED_BY") "VSN")
      )
      (libsource (lib "Database_Libs1") (part "C"))
    )
    (comp (ref "C672")
      (value "22uF")
      (footprint "SMD_0805_CAPC2012X145N")
      (fields
        (field (name "DB_PART_NUMBER") "CAP000043686")
        (field (name "DB_VALUE") "22uF")
        (field (name "DB_TOLERANCE") "20%")
        (field (name "DB_VOLTAGE") "6.3V")
        (field (name "DB_MANUFACTURER_PART") "KEMET    C0805C226M9PAC")
        (field (name "DB_APPROVED_BY") "ISHIDDEN=T")
      )
      (libsource (lib "Database_Libs1") (part "C"))
    )
    (comp (ref "C673")
      (value "22uF")
      (footprint "SMD_0805_CAPC2012X145N")
      (fields
        (field (name "DB_PART_NUMBER") "CAP000043686")
        (field (name "DB_VALUE") "22uF")
        (field (name "DB_TOLERANCE") "20%")
        (field (name "DB_VOLTAGE") "6.3V")
        (field (name "DB_MANUFACTURER_PART") "KEMET    C0805C226M9PAC")
        (field (name "DB_APPROVED_BY") "ISHIDDEN=T")
      )
      (libsource (lib "Database_Libs1") (part "C"))
    )
    (comp (ref "C674")
      (value "220uF")
      (footprint "SMD_1210_CAPC3225X279N")
      (fields
        (field (name "DB_PART_NUMBER") "CAP000047355")
        (field (name "DB_VALUE") "220uF")
        (field (name "DB_TOLERANCE") "20%")
        (field (name "DB_VOLTAGE") "6.3V")
        (field (name "DB_MANUFACTURER_PART") "SAMSUNG    CL32A227MQVNNNE")
        (field (name "DB_APPROVED_BY") "VSN")
      )
      (libsource (lib "Database_Libs1") (part "C"))
    )
    (comp (ref "C675")
      (value "22uF")
      (footprint "SMD_0805_CAPC2012X145N")
      (fields
        (field (name "DB_PART_NUMBER") "CAP000043686")
        (field (name "DB_VALUE") "22uF")
        (field (name "DB_TOLERANCE") "20%")
        (field (name "DB_VOLTAGE") "6.3V")
        (field (name "DB_MANUFACTURER_PART") "KEMET    C0805C226M9PAC")
        (field (name "DB_APPROVED_BY") "ISHIDDEN=T")
      )
      (libsource (lib "Database_Libs1") (part "C"))
    )
    (comp (ref "C676")
      (value "22uF")
      (footprint "SMD_0805_CAPC2012X145N")
      (fields
        (field (name "DB_PART_NUMBER") "CAP000043686")
        (field (name "DB_VALUE") "22uF")
        (field (name "DB_TOLERANCE") "20%")
        (field (name "DB_VOLTAGE") "6.3V")
        (field (name "DB_MANUFACTURER_PART") "KEMET    C0805C226M9PAC")
        (field (name "DB_APPROVED_BY") "ISHIDDEN=T")
      )
      (libsource (lib "Database_Libs1") (part "C"))
    )
    (comp (ref "C677")
      (value "220uF")
      (footprint "SMD_1210_CAPC3225X279N")
      (fields
        (field (name "DB_PART_NUMBER") "CAP000047355")
        (field (name "DB_VALUE") "220uF")
        (field (name "DB_TOLERANCE") "20%")
        (field (name "DB_VOLTAGE") "6.3V")
        (field (name "DB_MANUFACTURER_PART") "SAMSUNG    CL32A227MQVNNNE")
        (field (name "DB_APPROVED_BY") "VSN")
      )
      (libsource (lib "Database_Libs1") (part "C"))
    )
    (comp (ref "C678")
      (value "22uF")
      (footprint "SMD_0805_CAPC2012X145N")
      (fields
        (field (name "DB_PART_NUMBER") "CAP000043686")
        (field (name "DB_VALUE") "22uF")
        (field (name "DB_TOLERANCE") "20%")
        (field (name "DB_VOLTAGE") "6.3V")
        (field (name "DB_MANUFACTURER_PART") "KEMET    C0805C226M9PAC")
        (field (name "DB_APPROVED_BY") "ISHIDDEN=T")
      )
      (libsource (lib "Database_Libs1") (part "C"))
    )
    (comp (ref "C679")
      (value "22uF")
      (footprint "SMD_0805_CAPC2012X145N")
      (fields
        (field (name "DB_PART_NUMBER") "CAP000043686")
        (field (name "DB_VALUE") "22uF")
        (field (name "DB_TOLERANCE") "20%")
        (field (name "DB_VOLTAGE") "6.3V")
        (field (name "DB_MANUFACTURER_PART") "KEMET    C0805C226M9PAC")
        (field (name "DB_APPROVED_BY") "ISHIDDEN=T")
      )
      (libsource (lib "Database_Libs1") (part "C"))
    )
    (comp (ref "C680")
      (value "220uF")
      (footprint "SMD_1210_CAPC3225X279N")
      (fields
        (field (name "DB_PART_NUMBER") "CAP000047355")
        (field (name "DB_VALUE") "220uF")
        (field (name "DB_TOLERANCE") "20%")
        (field (name "DB_VOLTAGE") "6.3V")
        (field (name "DB_MANUFACTURER_PART") "SAMSUNG    CL32A227MQVNNNE")
        (field (name "DB_APPROVED_BY") "VSN")
      )
      (libsource (lib "Database_Libs1") (part "C"))
    )
    (comp (ref "C681")
      (value "22uF")
      (footprint "SMD_0805_CAPC2012X145N")
      (fields
        (field (name "DB_PART_NUMBER") "CAP000043686")
        (field (name "DB_VALUE") "22uF")
        (field (name "DB_TOLERANCE") "20%")
        (field (name "DB_VOLTAGE") "6.3V")
        (field (name "DB_MANUFACTURER_PART") "KEMET    C0805C226M9PAC")
        (field (name "DB_APPROVED_BY") "ISHIDDEN=T")
      )
      (libsource (lib "Database_Libs1") (part "C"))
    )
    (comp (ref "C686")
      (value "100uF")
      (footprint "SMD_1210_CAPC3225X270N")
      (fields
        (field (name "DB_PART_NUMBER") "TMP-2512")
        (field (name "DB_VALUE") "100uF")
        (field (name "DB_TOLERANCE") "20%")
        (field (name "DB_VOLTAGE") "16V")
        (field (name "DB_MANUFACTURER_PART") "YAGEO    CC1210MRX5R7BB107")
      )
      (libsource (lib "Database_Libs1") (part "C"))
    )
    (comp (ref "C688")
      (value "10uF")
      (footprint "SMD_0805_CAPC2012X145N")
      (fields
        (field (name "DB_PART_NUMBER") "CAP000043636")
        (field (name "DB_VALUE") "10uF")
        (field (name "DB_TOLERANCE") "10%")
        (field (name "DB_VOLTAGE") "16V")
        (field (name "DB_MANUFACTURER_PART") "KEMET    C0805C106K4PAC")
        (field (name "DB_APPROVED_BY") "ISHIDDEN=T")
      )
      (libsource (lib "Database_Libs1") (part "C"))
    )
    (comp (ref "C689")
      (value "100uF")
      (footprint "SMD_1210_CAPC3225X270N")
      (fields
        (field (name "DB_PART_NUMBER") "TMP-2512")
        (field (name "DB_VALUE") "100uF")
        (field (name "DB_TOLERANCE") "20%")
        (field (name "DB_VOLTAGE") "16V")
        (field (name "DB_MANUFACTURER_PART") "YAGEO    CC1210MRX5R7BB107")
      )
      (libsource (lib "Database_Libs1") (part "C"))
    )
    (comp (ref "C692")
      (value "100uF")
      (footprint "SMD_1210_CAPC3225X270N")
      (fields
        (field (name "DB_PART_NUMBER") "TMP-2512")
        (field (name "DB_VALUE") "100uF")
        (field (name "DB_TOLERANCE") "20%")
        (field (name "DB_VOLTAGE") "16V")
        (field (name "DB_MANUFACTURER_PART") "YAGEO    CC1210MRX5R7BB107")
      )
      (libsource (lib "Database_Libs1") (part "C"))
    )
    (comp (ref "C695")
      (value "100uF")
      (footprint "SMD_1210_CAPC3225X270N")
      (fields
        (field (name "DB_PART_NUMBER") "TMP-2512")
        (field (name "DB_VALUE") "100uF")
        (field (name "DB_TOLERANCE") "20%")
        (field (name "DB_VOLTAGE") "16V")
        (field (name "DB_MANUFACTURER_PART") "YAGEO    CC1210MRX5R7BB107")
      )
      (libsource (lib "Database_Libs1") (part "C"))
    )
    (comp (ref "C711")
      (value "10uF")
      (footprint "SMD_0805_CAPC2012X145N")
      (fields
        (field (name "DB_PART_NUMBER") "CAP000043636")
        (field (name "DB_VALUE") "10uF")
        (field (name "DB_TOLERANCE") "10%")
        (field (name "DB_VOLTAGE") "16V")
        (field (name "DB_MANUFACTURER_PART") "KEMET    C0805C106K4PAC")
        (field (name "DB_APPROVED_BY") "ISHIDDEN=T")
      )
      (libsource (lib "Database_Libs1") (part "C"))
    )
    (comp (ref "C712")
      (value "10uF")
      (footprint "SMD_0805_CAPC2012X145N")
      (fields
        (field (name "DB_PART_NUMBER") "CAP000043636")
        (field (name "DB_VALUE") "10uF")
        (field (name "DB_TOLERANCE") "10%")
        (field (name "DB_VOLTAGE") "16V")
        (field (name "DB_MANUFACTURER_PART") "KEMET    C0805C106K4PAC")
        (field (name "DB_APPROVED_BY") "ISHIDDEN=T")
      )
      (libsource (lib "Database_Libs1") (part "C"))
    )
    (comp (ref "C714")
      (value "10uF")
      (footprint "SMD_0805_CAPC2012X145N")
      (fields
        (field (name "DB_PART_NUMBER") "CAP000043636")
        (field (name "DB_VALUE") "10uF")
        (field (name "DB_TOLERANCE") "10%")
        (field (name "DB_VOLTAGE") "16V")
        (field (name "DB_MANUFACTURER_PART") "KEMET    C0805C106K4PAC")
        (field (name "DB_APPROVED_BY") "ISHIDDEN=T")
      )
      (libsource (lib "Database_Libs1") (part "C"))
    )
    (comp (ref "C715")
      (value "10uF")
      (footprint "SMD_0805_CAPC2012X145N")
      (fields
        (field (name "DB_PART_NUMBER") "CAP000043636")
        (field (name "DB_VALUE") "10uF")
        (field (name "DB_TOLERANCE") "10%")
        (field (name "DB_VOLTAGE") "16V")
        (field (name "DB_MANUFACTURER_PART") "KEMET    C0805C106K4PAC")
        (field (name "DB_APPROVED_BY") "ISHIDDEN=T")
      )
      (libsource (lib "Database_Libs1") (part "C"))
    )
    (comp (ref "C717")
      (value "10uF")
      (footprint "SMD_0805_CAPC2012X145N")
      (fields
        (field (name "DB_PART_NUMBER") "CAP000043636")
        (field (name "DB_VALUE") "10uF")
        (field (name "DB_TOLERANCE") "10%")
        (field (name "DB_VOLTAGE") "16V")
        (field (name "DB_MANUFACTURER_PART") "KEMET    C0805C106K4PAC")
        (field (name "DB_APPROVED_BY") "ISHIDDEN=T")
      )
      (libsource (lib "Database_Libs1") (part "C"))
    )
    (comp (ref "C742")
      (value "22uF")
      (footprint "SMD_0805_CAPC2012X145N")
      (fields
        (field (name "DB_PART_NUMBER") "CAP000043686")
        (field (name "DB_VALUE") "22uF")
        (field (name "DB_TOLERANCE") "20%")
        (field (name "DB_VOLTAGE") "6.3V")
        (field (name "DB_MANUFACTURER_PART") "KEMET    C0805C226M9PAC")
        (field (name "DB_APPROVED_BY") "ISHIDDEN=T")
      )
      (libsource (lib "Database_Libs1") (part "C"))
    )
    (comp (ref "C743")
      (value "220uF")
      (footprint "SMD_1210_CAPC3225X279N")
      (fields
        (field (name "DB_PART_NUMBER") "CAP000047355")
        (field (name "DB_VALUE") "220uF")
        (field (name "DB_TOLERANCE") "20%")
        (field (name "DB_VOLTAGE") "6.3V")
        (field (name "DB_MANUFACTURER_PART") "SAMSUNG    CL32A227MQVNNNE")
        (field (name "DB_APPROVED_BY") "VSN")
      )
      (libsource (lib "Database_Libs1") (part "C"))
    )
    (comp (ref "C744")
      (value "22uF")
      (footprint "SMD_0805_CAPC2012X145N")
      (fields
        (field (name "DB_PART_NUMBER") "CAP000043686")
        (field (name "DB_VALUE") "22uF")
        (field (name "DB_TOLERANCE") "20%")
        (field (name "DB_VOLTAGE") "6.3V")
        (field (name "DB_MANUFACTURER_PART") "KEMET    C0805C226M9PAC")
        (field (name "DB_APPROVED_BY") "ISHIDDEN=T")
      )
      (libsource (lib "Database_Libs1") (part "C"))
    )
    (comp (ref "C745")
      (value "22uF")
      (footprint "SMD_0805_CAPC2012X145N")
      (fields
        (field (name "DB_PART_NUMBER") "CAP000043686")
        (field (name "DB_VALUE") "22uF")
        (field (name "DB_TOLERANCE") "20%")
        (field (name "DB_VOLTAGE") "6.3V")
        (field (name "DB_MANUFACTURER_PART") "KEMET    C0805C226M9PAC")
        (field (name "DB_APPROVED_BY") "ISHIDDEN=T")
      )
      (libsource (lib "Database_Libs1") (part "C"))
    )
    (comp (ref "C746")
      (value "220uF")
      (footprint "SMD_1210_CAPC3225X279N")
      (fields
        (field (name "DB_PART_NUMBER") "CAP000047355")
        (field (name "DB_VALUE") "220uF")
        (field (name "DB_TOLERANCE") "20%")
        (field (name "DB_VOLTAGE") "6.3V")
        (field (name "DB_MANUFACTURER_PART") "SAMSUNG    CL32A227MQVNNNE")
        (field (name "DB_APPROVED_BY") "VSN")
      )
      (libsource (lib "Database_Libs1") (part "C"))
    )
    (comp (ref "C747")
      (value "22uF")
      (footprint "SMD_0805_CAPC2012X145N")
      (fields
        (field (name "DB_PART_NUMBER") "CAP000043686")
        (field (name "DB_VALUE") "22uF")
        (field (name "DB_TOLERANCE") "20%")
        (field (name "DB_VOLTAGE") "6.3V")
        (field (name "DB_MANUFACTURER_PART") "KEMET    C0805C226M9PAC")
        (field (name "DB_APPROVED_BY") "ISHIDDEN=T")
      )
      (libsource (lib "Database_Libs1") (part "C"))
    )
    (comp (ref "C748")
      (value "22uF")
      (footprint "SMD_0805_CAPC2012X145N")
      (fields
        (field (name "DB_PART_NUMBER") "CAP000043686")
        (field (name "DB_VALUE") "22uF")
        (field (name "DB_TOLERANCE") "20%")
        (field (name "DB_VOLTAGE") "6.3V")
        (field (name "DB_MANUFACTURER_PART") "KEMET    C0805C226M9PAC")
        (field (name "DB_APPROVED_BY") "ISHIDDEN=T")
      )
      (libsource (lib "Database_Libs1") (part "C"))
    )
    (comp (ref "C749")
      (value "220uF")
      (footprint "SMD_1210_CAPC3225X279N")
      (fields
        (field (name "DB_PART_NUMBER") "CAP000047355")
        (field (name "DB_VALUE") "220uF")
        (field (name "DB_TOLERANCE") "20%")
        (field (name "DB_VOLTAGE") "6.3V")
        (field (name "DB_MANUFACTURER_PART") "SAMSUNG    CL32A227MQVNNNE")
        (field (name "DB_APPROVED_BY") "VSN")
      )
      (libsource (lib "Database_Libs1") (part "C"))
    )
    (comp (ref "C750")
      (value "22uF")
      (footprint "SMD_0805_CAPC2012X145N")
      (fields
        (field (name "DB_PART_NUMBER") "CAP000043686")
        (field (name "DB_VALUE") "22uF")
        (field (name "DB_TOLERANCE") "20%")
        (field (name "DB_VOLTAGE") "6.3V")
        (field (name "DB_MANUFACTURER_PART") "KEMET    C0805C226M9PAC")
        (field (name "DB_APPROVED_BY") "ISHIDDEN=T")
      )
      (libsource (lib "Database_Libs1") (part "C"))
    )
    (comp (ref "C751")
      (value "22uF")
      (footprint "SMD_0805_CAPC2012X145N")
      (fields
        (field (name "DB_PART_NUMBER") "CAP000043686")
        (field (name "DB_VALUE") "22uF")
        (field (name "DB_TOLERANCE") "20%")
        (field (name "DB_VOLTAGE") "6.3V")
        (field (name "DB_MANUFACTURER_PART") "KEMET    C0805C226M9PAC")
        (field (name "DB_APPROVED_BY") "ISHIDDEN=T")
      )
      (libsource (lib "Database_Libs1") (part "C"))
    )
    (comp (ref "C752")
      (value "220uF")
      (footprint "SMD_1210_CAPC3225X279N")
      (fields
        (field (name "DB_PART_NUMBER") "CAP000047355")
        (field (name "DB_VALUE") "220uF")
        (field (name "DB_TOLERANCE") "20%")
        (field (name "DB_VOLTAGE") "6.3V")
        (field (name "DB_MANUFACTURER_PART") "SAMSUNG    CL32A227MQVNNNE")
        (field (name "DB_APPROVED_BY") "VSN")
      )
      (libsource (lib "Database_Libs1") (part "C"))
    )
    (comp (ref "C753")
      (value "22uF")
      (footprint "SMD_0805_CAPC2012X145N")
      (fields
        (field (name "DB_PART_NUMBER") "CAP000043686")
        (field (name "DB_VALUE") "22uF")
        (field (name "DB_TOLERANCE") "20%")
        (field (name "DB_VOLTAGE") "6.3V")
        (field (name "DB_MANUFACTURER_PART") "KEMET    C0805C226M9PAC")
        (field (name "DB_APPROVED_BY") "ISHIDDEN=T")
      )
      (libsource (lib "Database_Libs1") (part "C"))
    )
    (comp (ref "C754")
      (value "22uF")
      (footprint "SMD_0805_CAPC2012X145N")
      (fields
        (field (name "DB_PART_NUMBER") "CAP000043686")
        (field (name "DB_VALUE") "22uF")
        (field (name "DB_TOLERANCE") "20%")
        (field (name "DB_VOLTAGE") "6.3V")
        (field (name "DB_MANUFACTURER_PART") "KEMET    C0805C226M9PAC")
        (field (name "DB_APPROVED_BY") "ISHIDDEN=T")
      )
      (libsource (lib "Database_Libs1") (part "C"))
    )
    (comp (ref "C755")
      (value "220uF")
      (footprint "SMD_1210_CAPC3225X279N")
      (fields
        (field (name "DB_PART_NUMBER") "CAP000047355")
        (field (name "DB_VALUE") "220uF")
        (field (name "DB_TOLERANCE") "20%")
        (field (name "DB_VOLTAGE") "6.3V")
        (field (name "DB_MANUFACTURER_PART") "SAMSUNG    CL32A227MQVNNNE")
        (field (name "DB_APPROVED_BY") "VSN")
      )
      (libsource (lib "Database_Libs1") (part "C"))
    )
    (comp (ref "C756")
      (value "22uF")
      (footprint "SMD_0805_CAPC2012X145N")
      (fields
        (field (name "DB_PART_NUMBER") "CAP000043686")
        (field (name "DB_VALUE") "22uF")
        (field (name "DB_TOLERANCE") "20%")
        (field (name "DB_VOLTAGE") "6.3V")
        (field (name "DB_MANUFACTURER_PART") "KEMET    C0805C226M9PAC")
        (field (name "DB_APPROVED_BY") "ISHIDDEN=T")
      )
      (libsource (lib "Database_Libs1") (part "C"))
    )
    (comp (ref "C757")
      (value "22uF")
      (footprint "SMD_0805_CAPC2012X145N")
      (fields
        (field (name "DB_PART_NUMBER") "CAP000043686")
        (field (name "DB_VALUE") "22uF")
        (field (name "DB_TOLERANCE") "20%")
        (field (name "DB_VOLTAGE") "6.3V")
        (field (name "DB_MANUFACTURER_PART") "KEMET    C0805C226M9PAC")
        (field (name "DB_APPROVED_BY") "ISHIDDEN=T")
      )
      (libsource (lib "Database_Libs1") (part "C"))
    )
    (comp (ref "C758")
      (value "220uF")
      (footprint "SMD_1210_CAPC3225X279N")
      (fields
        (field (name "DB_PART_NUMBER") "CAP000047355")
        (field (name "DB_VALUE") "220uF")
        (field (name "DB_TOLERANCE") "20%")
        (field (name "DB_VOLTAGE") "6.3V")
        (field (name "DB_MANUFACTURER_PART") "SAMSUNG    CL32A227MQVNNNE")
        (field (name "DB_APPROVED_BY") "VSN")
      )
      (libsource (lib "Database_Libs1") (part "C"))
    )
    (comp (ref "C759")
      (value "22uF")
      (footprint "SMD_0805_CAPC2012X145N")
      (fields
        (field (name "DB_PART_NUMBER") "CAP000043686")
        (field (name "DB_VALUE") "22uF")
        (field (name "DB_TOLERANCE") "20%")
        (field (name "DB_VOLTAGE") "6.3V")
        (field (name "DB_MANUFACTURER_PART") "KEMET    C0805C226M9PAC")
        (field (name "DB_APPROVED_BY") "ISHIDDEN=T")
      )
      (libsource (lib "Database_Libs1") (part "C"))
    )
    (comp (ref "C760")
      (value "22uF")
      (footprint "SMD_0805_CAPC2012X145N")
      (fields
        (field (name "DB_PART_NUMBER") "CAP000043686")
        (field (name "DB_VALUE") "22uF")
        (field (name "DB_TOLERANCE") "20%")
        (field (name "DB_VOLTAGE") "6.3V")
        (field (name "DB_MANUFACTURER_PART") "KEMET    C0805C226M9PAC")
        (field (name "DB_APPROVED_BY") "ISHIDDEN=T")
      )
      (libsource (lib "Database_Libs1") (part "C"))
    )
    (comp (ref "C761")
      (value "220uF")
      (footprint "SMD_1210_CAPC3225X279N")
      (fields
        (field (name "DB_PART_NUMBER") "CAP000047355")
        (field (name "DB_VALUE") "220uF")
        (field (name "DB_TOLERANCE") "20%")
        (field (name "DB_VOLTAGE") "6.3V")
        (field (name "DB_MANUFACTURER_PART") "SAMSUNG    CL32A227MQVNNNE")
        (field (name "DB_APPROVED_BY") "VSN")
      )
      (libsource (lib "Database_Libs1") (part "C"))
    )
    (comp (ref "C762")
      (value "22uF")
      (footprint "SMD_0805_CAPC2012X145N")
      (fields
        (field (name "DB_PART_NUMBER") "CAP000043686")
        (field (name "DB_VALUE") "22uF")
        (field (name "DB_TOLERANCE") "20%")
        (field (name "DB_VOLTAGE") "6.3V")
        (field (name "DB_MANUFACTURER_PART") "KEMET    C0805C226M9PAC")
        (field (name "DB_APPROVED_BY") "ISHIDDEN=T")
      )
      (libsource (lib "Database_Libs1") (part "C"))
    )
    (comp (ref "C763")
      (value "22uF")
      (footprint "SMD_0805_CAPC2012X145N")
      (fields
        (field (name "DB_PART_NUMBER") "CAP000043686")
        (field (name "DB_VALUE") "22uF")
        (field (name "DB_TOLERANCE") "20%")
        (field (name "DB_VOLTAGE") "6.3V")
        (field (name "DB_MANUFACTURER_PART") "KEMET    C0805C226M9PAC")
        (field (name "DB_APPROVED_BY") "ISHIDDEN=T")
      )
      (libsource (lib "Database_Libs1") (part "C"))
    )
    (comp (ref "C764")
      (value "220uF")
      (footprint "SMD_1210_CAPC3225X279N")
      (fields
        (field (name "DB_PART_NUMBER") "CAP000047355")
        (field (name "DB_VALUE") "220uF")
        (field (name "DB_TOLERANCE") "20%")
        (field (name "DB_VOLTAGE") "6.3V")
        (field (name "DB_MANUFACTURER_PART") "SAMSUNG    CL32A227MQVNNNE")
        (field (name "DB_APPROVED_BY") "VSN")
      )
      (libsource (lib "Database_Libs1") (part "C"))
    )
    (comp (ref "C765")
      (value "22uF")
      (footprint "SMD_0805_CAPC2012X145N")
      (fields
        (field (name "DB_PART_NUMBER") "CAP000043686")
        (field (name "DB_VALUE") "22uF")
        (field (name "DB_TOLERANCE") "20%")
        (field (name "DB_VOLTAGE") "6.3V")
        (field (name "DB_MANUFACTURER_PART") "KEMET    C0805C226M9PAC")
        (field (name "DB_APPROVED_BY") "ISHIDDEN=T")
      )
      (libsource (lib "Database_Libs1") (part "C"))
    )
    (comp (ref "C766")
      (value "22uF")
      (footprint "SMD_0805_CAPC2012X145N")
      (fields
        (field (name "DB_PART_NUMBER") "CAP000043686")
        (field (name "DB_VALUE") "22uF")
        (field (name "DB_TOLERANCE") "20%")
        (field (name "DB_VOLTAGE") "6.3V")
        (field (name "DB_MANUFACTURER_PART") "KEMET    C0805C226M9PAC")
        (field (name "DB_APPROVED_BY") "ISHIDDEN=T")
      )
      (libsource (lib "Database_Libs1") (part "C"))
    )
    (comp (ref "C767")
      (value "220uF")
      (footprint "SMD_1210_CAPC3225X279N")
      (fields
        (field (name "DB_PART_NUMBER") "CAP000047355")
        (field (name "DB_VALUE") "220uF")
        (field (name "DB_TOLERANCE") "20%")
        (field (name "DB_VOLTAGE") "6.3V")
        (field (name "DB_MANUFACTURER_PART") "SAMSUNG    CL32A227MQVNNNE")
        (field (name "DB_APPROVED_BY") "VSN")
      )
      (libsource (lib "Database_Libs1") (part "C"))
    )
    (comp (ref "C768")
      (value "22uF")
      (footprint "SMD_0805_CAPC2012X145N")
      (fields
        (field (name "DB_PART_NUMBER") "CAP000043686")
        (field (name "DB_VALUE") "22uF")
        (field (name "DB_TOLERANCE") "20%")
        (field (name "DB_VOLTAGE") "6.3V")
        (field (name "DB_MANUFACTURER_PART") "KEMET    C0805C226M9PAC")
        (field (name "DB_APPROVED_BY") "ISHIDDEN=T")
      )
      (libsource (lib "Database_Libs1") (part "C"))
    )
    (comp (ref "C769")
      (value "22uF")
      (footprint "SMD_0805_CAPC2012X145N")
      (fields
        (field (name "DB_PART_NUMBER") "CAP000043686")
        (field (name "DB_VALUE") "22uF")
        (field (name "DB_TOLERANCE") "20%")
        (field (name "DB_VOLTAGE") "6.3V")
        (field (name "DB_MANUFACTURER_PART") "KEMET    C0805C226M9PAC")
        (field (name "DB_APPROVED_BY") "ISHIDDEN=T")
      )
      (libsource (lib "Database_Libs1") (part "C"))
    )
    (comp (ref "C770")
      (value "220uF")
      (footprint "SMD_1210_CAPC3225X279N")
      (fields
        (field (name "DB_PART_NUMBER") "CAP000047355")
        (field (name "DB_VALUE") "220uF")
        (field (name "DB_TOLERANCE") "20%")
        (field (name "DB_VOLTAGE") "6.3V")
        (field (name "DB_MANUFACTURER_PART") "SAMSUNG    CL32A227MQVNNNE")
        (field (name "DB_APPROVED_BY") "VSN")
      )
      (libsource (lib "Database_Libs1") (part "C"))
    )
    (comp (ref "C771")
      (value "22uF")
      (footprint "SMD_0805_CAPC2012X145N")
      (fields
        (field (name "DB_PART_NUMBER") "CAP000043686")
        (field (name "DB_VALUE") "22uF")
        (field (name "DB_TOLERANCE") "20%")
        (field (name "DB_VOLTAGE") "6.3V")
        (field (name "DB_MANUFACTURER_PART") "KEMET    C0805C226M9PAC")
        (field (name "DB_APPROVED_BY") "ISHIDDEN=T")
      )
      (libsource (lib "Database_Libs1") (part "C"))
    )
    (comp (ref "C776")
      (value "100uF")
      (footprint "SMD_1210_CAPC3225X270N")
      (fields
        (field (name "DB_PART_NUMBER") "TMP-2512")
        (field (name "DB_VALUE") "100uF")
        (field (name "DB_TOLERANCE") "20%")
        (field (name "DB_VOLTAGE") "16V")
        (field (name "DB_MANUFACTURER_PART") "YAGEO    CC1210MRX5R7BB107")
      )
      (libsource (lib "Database_Libs1") (part "C"))
    )
    (comp (ref "C779")
      (value "100uF")
      (footprint "SMD_1210_CAPC3225X270N")
      (fields
        (field (name "DB_PART_NUMBER") "TMP-2512")
        (field (name "DB_VALUE") "100uF")
        (field (name "DB_TOLERANCE") "20%")
        (field (name "DB_VOLTAGE") "16V")
        (field (name "DB_MANUFACTURER_PART") "YAGEO    CC1210MRX5R7BB107")
      )
      (libsource (lib "Database_Libs1") (part "C"))
    )
    (comp (ref "C782")
      (value "100uF")
      (footprint "SMD_1210_CAPC3225X270N")
      (fields
        (field (name "DB_PART_NUMBER") "TMP-2512")
        (field (name "DB_VALUE") "100uF")
        (field (name "DB_TOLERANCE") "20%")
        (field (name "DB_VOLTAGE") "16V")
        (field (name "DB_MANUFACTURER_PART") "YAGEO    CC1210MRX5R7BB107")
      )
      (libsource (lib "Database_Libs1") (part "C"))
    )
    (comp (ref "C785")
      (value "100uF")
      (footprint "SMD_1210_CAPC3225X270N")
      (fields
        (field (name "DB_PART_NUMBER") "TMP-2512")
        (field (name "DB_VALUE") "100uF")
        (field (name "DB_TOLERANCE") "20%")
        (field (name "DB_VOLTAGE") "16V")
        (field (name "DB_MANUFACTURER_PART") "YAGEO    CC1210MRX5R7BB107")
      )
      (libsource (lib "Database_Libs1") (part "C"))
    )
    (comp (ref "C807")
      (value "10uF")
      (footprint "SMD_0805_CAPC2012X145N")
      (fields
        (field (name "DB_PART_NUMBER") "CAP000043636")
        (field (name "DB_VALUE") "10uF")
        (field (name "DB_TOLERANCE") "10%")
        (field (name "DB_VOLTAGE") "16V")
        (field (name "DB_MANUFACTURER_PART") "KEMET    C0805C106K4PAC")
        (field (name "DB_APPROVED_BY") "ISHIDDEN=T")
      )
      (libsource (lib "Database_Libs1") (part "C"))
    )
    (comp (ref "C808")
      (value "10uF")
      (footprint "SMD_0805_CAPC2012X145N")
      (fields
        (field (name "DB_PART_NUMBER") "CAP000043636")
        (field (name "DB_VALUE") "10uF")
        (field (name "DB_TOLERANCE") "10%")
        (field (name "DB_VOLTAGE") "16V")
        (field (name "DB_MANUFACTURER_PART") "KEMET    C0805C106K4PAC")
        (field (name "DB_APPROVED_BY") "ISHIDDEN=T")
      )
      (libsource (lib "Database_Libs1") (part "C"))
    )
    (comp (ref "C810")
      (value "10uF")
      (footprint "SMD_0805_CAPC2012X145N")
      (fields
        (field (name "DB_PART_NUMBER") "CAP000043636")
        (field (name "DB_VALUE") "10uF")
        (field (name "DB_TOLERANCE") "10%")
        (field (name "DB_VOLTAGE") "16V")
        (field (name "DB_MANUFACTURER_PART") "KEMET    C0805C106K4PAC")
        (field (name "DB_APPROVED_BY") "ISHIDDEN=T")
      )
      (libsource (lib "Database_Libs1") (part "C"))
    )
    (comp (ref "C811")
      (value "10uF")
      (footprint "SMD_0805_CAPC2012X145N")
      (fields
        (field (name "DB_PART_NUMBER") "CAP000043636")
        (field (name "DB_VALUE") "10uF")
        (field (name "DB_TOLERANCE") "10%")
        (field (name "DB_VOLTAGE") "16V")
        (field (name "DB_MANUFACTURER_PART") "KEMET    C0805C106K4PAC")
        (field (name "DB_APPROVED_BY") "ISHIDDEN=T")
      )
      (libsource (lib "Database_Libs1") (part "C"))
    )
    (comp (ref "C813")
      (value "10uF")
      (footprint "SMD_0805_CAPC2012X145N")
      (fields
        (field (name "DB_PART_NUMBER") "CAP000043636")
        (field (name "DB_VALUE") "10uF")
        (field (name "DB_TOLERANCE") "10%")
        (field (name "DB_VOLTAGE") "16V")
        (field (name "DB_MANUFACTURER_PART") "KEMET    C0805C106K4PAC")
        (field (name "DB_APPROVED_BY") "ISHIDDEN=T")
      )
      (libsource (lib "Database_Libs1") (part "C"))
    )
    (comp (ref "C814")
      (value "10uF")
      (footprint "SMD_0805_CAPC2012X145N")
      (fields
        (field (name "DB_PART_NUMBER") "CAP000043636")
        (field (name "DB_VALUE") "10uF")
        (field (name "DB_TOLERANCE") "10%")
        (field (name "DB_VOLTAGE") "16V")
        (field (name "DB_MANUFACTURER_PART") "KEMET    C0805C106K4PAC")
        (field (name "DB_APPROVED_BY") "ISHIDDEN=T")
      )
      (libsource (lib "Database_Libs1") (part "C"))
    )
    (comp (ref "C832")
      (value "22uF")
      (footprint "SMD_0805_CAPC2012X145N")
      (fields
        (field (name "DB_PART_NUMBER") "CAP000043686")
        (field (name "DB_VALUE") "22uF")
        (field (name "DB_TOLERANCE") "20%")
        (field (name "DB_VOLTAGE") "6.3V")
        (field (name "DB_MANUFACTURER_PART") "KEMET    C0805C226M9PAC")
        (field (name "DB_APPROVED_BY") "ISHIDDEN=T")
      )
      (libsource (lib "Database_Libs1") (part "C"))
    )
    (comp (ref "C833")
      (value "220uF")
      (footprint "SMD_1210_CAPC3225X279N")
      (fields
        (field (name "DB_PART_NUMBER") "CAP000047355")
        (field (name "DB_VALUE") "220uF")
        (field (name "DB_TOLERANCE") "20%")
        (field (name "DB_VOLTAGE") "6.3V")
        (field (name "DB_MANUFACTURER_PART") "SAMSUNG    CL32A227MQVNNNE")
        (field (name "DB_APPROVED_BY") "VSN")
      )
      (libsource (lib "Database_Libs1") (part "C"))
    )
    (comp (ref "C834")
      (value "22uF")
      (footprint "SMD_0805_CAPC2012X145N")
      (fields
        (field (name "DB_PART_NUMBER") "CAP000043686")
        (field (name "DB_VALUE") "22uF")
        (field (name "DB_TOLERANCE") "20%")
        (field (name "DB_VOLTAGE") "6.3V")
        (field (name "DB_MANUFACTURER_PART") "KEMET    C0805C226M9PAC")
        (field (name "DB_APPROVED_BY") "ISHIDDEN=T")
      )
      (libsource (lib "Database_Libs1") (part "C"))
    )
    (comp (ref "C835")
      (value "22uF")
      (footprint "SMD_0805_CAPC2012X145N")
      (fields
        (field (name "DB_PART_NUMBER") "CAP000043686")
        (field (name "DB_VALUE") "22uF")
        (field (name "DB_TOLERANCE") "20%")
        (field (name "DB_VOLTAGE") "6.3V")
        (field (name "DB_MANUFACTURER_PART") "KEMET    C0805C226M9PAC")
        (field (name "DB_APPROVED_BY") "ISHIDDEN=T")
      )
      (libsource (lib "Database_Libs1") (part "C"))
    )
    (comp (ref "C836")
      (value "220uF")
      (footprint "SMD_1210_CAPC3225X279N")
      (fields
        (field (name "DB_PART_NUMBER") "CAP000047355")
        (field (name "DB_VALUE") "220uF")
        (field (name "DB_TOLERANCE") "20%")
        (field (name "DB_VOLTAGE") "6.3V")
        (field (name "DB_MANUFACTURER_PART") "SAMSUNG    CL32A227MQVNNNE")
        (field (name "DB_APPROVED_BY") "VSN")
      )
      (libsource (lib "Database_Libs1") (part "C"))
    )
    (comp (ref "C837")
      (value "22uF")
      (footprint "SMD_0805_CAPC2012X145N")
      (fields
        (field (name "DB_PART_NUMBER") "CAP000043686")
        (field (name "DB_VALUE") "22uF")
        (field (name "DB_TOLERANCE") "20%")
        (field (name "DB_VOLTAGE") "6.3V")
        (field (name "DB_MANUFACTURER_PART") "KEMET    C0805C226M9PAC")
        (field (name "DB_APPROVED_BY") "ISHIDDEN=T")
      )
      (libsource (lib "Database_Libs1") (part "C"))
    )
    (comp (ref "C838")
      (value "22uF")
      (footprint "SMD_0805_CAPC2012X145N")
      (fields
        (field (name "DB_PART_NUMBER") "CAP000043686")
        (field (name "DB_VALUE") "22uF")
        (field (name "DB_TOLERANCE") "20%")
        (field (name "DB_VOLTAGE") "6.3V")
        (field (name "DB_MANUFACTURER_PART") "KEMET    C0805C226M9PAC")
        (field (name "DB_APPROVED_BY") "ISHIDDEN=T")
      )
      (libsource (lib "Database_Libs1") (part "C"))
    )
    (comp (ref "C839")
      (value "220uF")
      (footprint "SMD_1210_CAPC3225X279N")
      (fields
        (field (name "DB_PART_NUMBER") "CAP000047355")
        (field (name "DB_VALUE") "220uF")
        (field (name "DB_TOLERANCE") "20%")
        (field (name "DB_VOLTAGE") "6.3V")
        (field (name "DB_MANUFACTURER_PART") "SAMSUNG    CL32A227MQVNNNE")
        (field (name "DB_APPROVED_BY") "VSN")
      )
      (libsource (lib "Database_Libs1") (part "C"))
    )
    (comp (ref "C840")
      (value "22uF")
      (footprint "SMD_0805_CAPC2012X145N")
      (fields
        (field (name "DB_PART_NUMBER") "CAP000043686")
        (field (name "DB_VALUE") "22uF")
        (field (name "DB_TOLERANCE") "20%")
        (field (name "DB_VOLTAGE") "6.3V")
        (field (name "DB_MANUFACTURER_PART") "KEMET    C0805C226M9PAC")
        (field (name "DB_APPROVED_BY") "ISHIDDEN=T")
      )
      (libsource (lib "Database_Libs1") (part "C"))
    )
    (comp (ref "C841")
      (value "22uF")
      (footprint "SMD_0805_CAPC2012X145N")
      (fields
        (field (name "DB_PART_NUMBER") "CAP000043686")
        (field (name "DB_VALUE") "22uF")
        (field (name "DB_TOLERANCE") "20%")
        (field (name "DB_VOLTAGE") "6.3V")
        (field (name "DB_MANUFACTURER_PART") "KEMET    C0805C226M9PAC")
        (field (name "DB_APPROVED_BY") "ISHIDDEN=T")
      )
      (libsource (lib "Database_Libs1") (part "C"))
    )
    (comp (ref "C842")
      (value "220uF")
      (footprint "SMD_1210_CAPC3225X279N")
      (fields
        (field (name "DB_PART_NUMBER") "CAP000047355")
        (field (name "DB_VALUE") "220uF")
        (field (name "DB_TOLERANCE") "20%")
        (field (name "DB_VOLTAGE") "6.3V")
        (field (name "DB_MANUFACTURER_PART") "SAMSUNG    CL32A227MQVNNNE")
        (field (name "DB_APPROVED_BY") "VSN")
      )
      (libsource (lib "Database_Libs1") (part "C"))
    )
    (comp (ref "C843")
      (value "22uF")
      (footprint "SMD_0805_CAPC2012X145N")
      (fields
        (field (name "DB_PART_NUMBER") "CAP000043686")
        (field (name "DB_VALUE") "22uF")
        (field (name "DB_TOLERANCE") "20%")
        (field (name "DB_VOLTAGE") "6.3V")
        (field (name "DB_MANUFACTURER_PART") "KEMET    C0805C226M9PAC")
        (field (name "DB_APPROVED_BY") "ISHIDDEN=T")
      )
      (libsource (lib "Database_Libs1") (part "C"))
    )
    (comp (ref "C844")
      (value "22uF")
      (footprint "SMD_0805_CAPC2012X145N")
      (fields
        (field (name "DB_PART_NUMBER") "CAP000043686")
        (field (name "DB_VALUE") "22uF")
        (field (name "DB_TOLERANCE") "20%")
        (field (name "DB_VOLTAGE") "6.3V")
        (field (name "DB_MANUFACTURER_PART") "KEMET    C0805C226M9PAC")
        (field (name "DB_APPROVED_BY") "ISHIDDEN=T")
      )
      (libsource (lib "Database_Libs1") (part "C"))
    )
    (comp (ref "C845")
      (value "220uF")
      (footprint "SMD_1210_CAPC3225X279N")
      (fields
        (field (name "DB_PART_NUMBER") "CAP000047355")
        (field (name "DB_VALUE") "220uF")
        (field (name "DB_TOLERANCE") "20%")
        (field (name "DB_VOLTAGE") "6.3V")
        (field (name "DB_MANUFACTURER_PART") "SAMSUNG    CL32A227MQVNNNE")
        (field (name "DB_APPROVED_BY") "VSN")
      )
      (libsource (lib "Database_Libs1") (part "C"))
    )
    (comp (ref "C846")
      (value "22uF")
      (footprint "SMD_0805_CAPC2012X145N")
      (fields
        (field (name "DB_PART_NUMBER") "CAP000043686")
        (field (name "DB_VALUE") "22uF")
        (field (name "DB_TOLERANCE") "20%")
        (field (name "DB_VOLTAGE") "6.3V")
        (field (name "DB_MANUFACTURER_PART") "KEMET    C0805C226M9PAC")
        (field (name "DB_APPROVED_BY") "ISHIDDEN=T")
      )
      (libsource (lib "Database_Libs1") (part "C"))
    )
    (comp (ref "C847")
      (value "22uF")
      (footprint "SMD_0805_CAPC2012X145N")
      (fields
        (field (name "DB_PART_NUMBER") "CAP000043686")
        (field (name "DB_VALUE") "22uF")
        (field (name "DB_TOLERANCE") "20%")
        (field (name "DB_VOLTAGE") "6.3V")
        (field (name "DB_MANUFACTURER_PART") "KEMET    C0805C226M9PAC")
        (field (name "DB_APPROVED_BY") "ISHIDDEN=T")
      )
      (libsource (lib "Database_Libs1") (part "C"))
    )
    (comp (ref "C848")
      (value "220uF")
      (footprint "SMD_1210_CAPC3225X279N")
      (fields
        (field (name "DB_PART_NUMBER") "CAP000047355")
        (field (name "DB_VALUE") "220uF")
        (field (name "DB_TOLERANCE") "20%")
        (field (name "DB_VOLTAGE") "6.3V")
        (field (name "DB_MANUFACTURER_PART") "SAMSUNG    CL32A227MQVNNNE")
        (field (name "DB_APPROVED_BY") "VSN")
      )
      (libsource (lib "Database_Libs1") (part "C"))
    )
    (comp (ref "C849")
      (value "22uF")
      (footprint "SMD_0805_CAPC2012X145N")
      (fields
        (field (name "DB_PART_NUMBER") "CAP000043686")
        (field (name "DB_VALUE") "22uF")
        (field (name "DB_TOLERANCE") "20%")
        (field (name "DB_VOLTAGE") "6.3V")
        (field (name "DB_MANUFACTURER_PART") "KEMET    C0805C226M9PAC")
        (field (name "DB_APPROVED_BY") "ISHIDDEN=T")
      )
      (libsource (lib "Database_Libs1") (part "C"))
    )
    (comp (ref "C850")
      (value "22uF")
      (footprint "SMD_0805_CAPC2012X145N")
      (fields
        (field (name "DB_PART_NUMBER") "CAP000043686")
        (field (name "DB_VALUE") "22uF")
        (field (name "DB_TOLERANCE") "20%")
        (field (name "DB_VOLTAGE") "6.3V")
        (field (name "DB_MANUFACTURER_PART") "KEMET    C0805C226M9PAC")
        (field (name "DB_APPROVED_BY") "ISHIDDEN=T")
      )
      (libsource (lib "Database_Libs1") (part "C"))
    )
    (comp (ref "C851")
      (value "220uF")
      (footprint "SMD_1210_CAPC3225X279N")
      (fields
        (field (name "DB_PART_NUMBER") "CAP000047355")
        (field (name "DB_VALUE") "220uF")
        (field (name "DB_TOLERANCE") "20%")
        (field (name "DB_VOLTAGE") "6.3V")
        (field (name "DB_MANUFACTURER_PART") "SAMSUNG    CL32A227MQVNNNE")
        (field (name "DB_APPROVED_BY") "VSN")
      )
      (libsource (lib "Database_Libs1") (part "C"))
    )
    (comp (ref "C852")
      (value "22uF")
      (footprint "SMD_0805_CAPC2012X145N")
      (fields
        (field (name "DB_PART_NUMBER") "CAP000043686")
        (field (name "DB_VALUE") "22uF")
        (field (name "DB_TOLERANCE") "20%")
        (field (name "DB_VOLTAGE") "6.3V")
        (field (name "DB_MANUFACTURER_PART") "KEMET    C0805C226M9PAC")
        (field (name "DB_APPROVED_BY") "ISHIDDEN=T")
      )
      (libsource (lib "Database_Libs1") (part "C"))
    )
    (comp (ref "C853")
      (value "22uF")
      (footprint "SMD_0805_CAPC2012X145N")
      (fields
        (field (name "DB_PART_NUMBER") "CAP000043686")
        (field (name "DB_VALUE") "22uF")
        (field (name "DB_TOLERANCE") "20%")
        (field (name "DB_VOLTAGE") "6.3V")
        (field (name "DB_MANUFACTURER_PART") "KEMET    C0805C226M9PAC")
        (field (name "DB_APPROVED_BY") "ISHIDDEN=T")
      )
      (libsource (lib "Database_Libs1") (part "C"))
    )
    (comp (ref "C854")
      (value "220uF")
      (footprint "SMD_1210_CAPC3225X279N")
      (fields
        (field (name "DB_PART_NUMBER") "CAP000047355")
        (field (name "DB_VALUE") "220uF")
        (field (name "DB_TOLERANCE") "20%")
        (field (name "DB_VOLTAGE") "6.3V")
        (field (name "DB_MANUFACTURER_PART") "SAMSUNG    CL32A227MQVNNNE")
        (field (name "DB_APPROVED_BY") "VSN")
      )
      (libsource (lib "Database_Libs1") (part "C"))
    )
    (comp (ref "C855")
      (value "22uF")
      (footprint "SMD_0805_CAPC2012X145N")
      (fields
        (field (name "DB_PART_NUMBER") "CAP000043686")
        (field (name "DB_VALUE") "22uF")
        (field (name "DB_TOLERANCE") "20%")
        (field (name "DB_VOLTAGE") "6.3V")
        (field (name "DB_MANUFACTURER_PART") "KEMET    C0805C226M9PAC")
        (field (name "DB_APPROVED_BY") "ISHIDDEN=T")
      )
      (libsource (lib "Database_Libs1") (part "C"))
    )
    (comp (ref "C856")
      (value "22uF")
      (footprint "SMD_0805_CAPC2012X145N")
      (fields
        (field (name "DB_PART_NUMBER") "CAP000043686")
        (field (name "DB_VALUE") "22uF")
        (field (name "DB_TOLERANCE") "20%")
        (field (name "DB_VOLTAGE") "6.3V")
        (field (name "DB_MANUFACTURER_PART") "KEMET    C0805C226M9PAC")
        (field (name "DB_APPROVED_BY") "ISHIDDEN=T")
      )
      (libsource (lib "Database_Libs1") (part "C"))
    )
    (comp (ref "C857")
      (value "220uF")
      (footprint "SMD_1210_CAPC3225X279N")
      (fields
        (field (name "DB_PART_NUMBER") "CAP000047355")
        (field (name "DB_VALUE") "220uF")
        (field (name "DB_TOLERANCE") "20%")
        (field (name "DB_VOLTAGE") "6.3V")
        (field (name "DB_MANUFACTURER_PART") "SAMSUNG    CL32A227MQVNNNE")
        (field (name "DB_APPROVED_BY") "VSN")
      )
      (libsource (lib "Database_Libs1") (part "C"))
    )
    (comp (ref "C858")
      (value "22uF")
      (footprint "SMD_0805_CAPC2012X145N")
      (fields
        (field (name "DB_PART_NUMBER") "CAP000043686")
        (field (name "DB_VALUE") "22uF")
        (field (name "DB_TOLERANCE") "20%")
        (field (name "DB_VOLTAGE") "6.3V")
        (field (name "DB_MANUFACTURER_PART") "KEMET    C0805C226M9PAC")
        (field (name "DB_APPROVED_BY") "ISHIDDEN=T")
      )
      (libsource (lib "Database_Libs1") (part "C"))
    )
    (comp (ref "C859")
      (value "22uF")
      (footprint "SMD_0805_CAPC2012X145N")
      (fields
        (field (name "DB_PART_NUMBER") "CAP000043686")
        (field (name "DB_VALUE") "22uF")
        (field (name "DB_TOLERANCE") "20%")
        (field (name "DB_VOLTAGE") "6.3V")
        (field (name "DB_MANUFACTURER_PART") "KEMET    C0805C226M9PAC")
        (field (name "DB_APPROVED_BY") "ISHIDDEN=T")
      )
      (libsource (lib "Database_Libs1") (part "C"))
    )
    (comp (ref "C860")
      (value "220uF")
      (footprint "SMD_1210_CAPC3225X279N")
      (fields
        (field (name "DB_PART_NUMBER") "CAP000047355")
        (field (name "DB_VALUE") "220uF")
        (field (name "DB_TOLERANCE") "20%")
        (field (name "DB_VOLTAGE") "6.3V")
        (field (name "DB_MANUFACTURER_PART") "SAMSUNG    CL32A227MQVNNNE")
        (field (name "DB_APPROVED_BY") "VSN")
      )
      (libsource (lib "Database_Libs1") (part "C"))
    )
    (comp (ref "C861")
      (value "22uF")
      (footprint "SMD_0805_CAPC2012X145N")
      (fields
        (field (name "DB_PART_NUMBER") "CAP000043686")
        (field (name "DB_VALUE") "22uF")
        (field (name "DB_TOLERANCE") "20%")
        (field (name "DB_VOLTAGE") "6.3V")
        (field (name "DB_MANUFACTURER_PART") "KEMET    C0805C226M9PAC")
        (field (name "DB_APPROVED_BY") "ISHIDDEN=T")
      )
      (libsource (lib "Database_Libs1") (part "C"))
    )
    (comp (ref "C866")
      (value "100uF")
      (footprint "SMD_1210_CAPC3225X270N")
      (fields
        (field (name "DB_PART_NUMBER") "TMP-2512")
        (field (name "DB_VALUE") "100uF")
        (field (name "DB_TOLERANCE") "20%")
        (field (name "DB_VOLTAGE") "16V")
        (field (name "DB_MANUFACTURER_PART") "YAGEO    CC1210MRX5R7BB107")
      )
      (libsource (lib "Database_Libs1") (part "C"))
    )
    (comp (ref "C868")
      (value "10uF")
      (footprint "SMD_0805_CAPC2012X145N")
      (fields
        (field (name "DB_PART_NUMBER") "CAP000043636")
        (field (name "DB_VALUE") "10uF")
        (field (name "DB_TOLERANCE") "10%")
        (field (name "DB_VOLTAGE") "16V")
        (field (name "DB_MANUFACTURER_PART") "KEMET    C0805C106K4PAC")
        (field (name "DB_APPROVED_BY") "ISHIDDEN=T")
      )
      (libsource (lib "Database_Libs1") (part "C"))
    )
    (comp (ref "C869")
      (value "100uF")
      (footprint "SMD_1210_CAPC3225X270N")
      (fields
        (field (name "DB_PART_NUMBER") "TMP-2512")
        (field (name "DB_VALUE") "100uF")
        (field (name "DB_TOLERANCE") "20%")
        (field (name "DB_VOLTAGE") "16V")
        (field (name "DB_MANUFACTURER_PART") "YAGEO    CC1210MRX5R7BB107")
      )
      (libsource (lib "Database_Libs1") (part "C"))
    )
    (comp (ref "C872")
      (value "100uF")
      (footprint "SMD_1210_CAPC3225X270N")
      (fields
        (field (name "DB_PART_NUMBER") "TMP-2512")
        (field (name "DB_VALUE") "100uF")
        (field (name "DB_TOLERANCE") "20%")
        (field (name "DB_VOLTAGE") "16V")
        (field (name "DB_MANUFACTURER_PART") "YAGEO    CC1210MRX5R7BB107")
      )
      (libsource (lib "Database_Libs1") (part "C"))
    )
    (comp (ref "C876")
      (value "10uF")
      (footprint "SMD_0805_CAPC2012X145N")
      (fields
        (field (name "DB_PART_NUMBER") "CAP000043636")
        (field (name "DB_VALUE") "10uF")
        (field (name "DB_TOLERANCE") "10%")
        (field (name "DB_VOLTAGE") "16V")
        (field (name "DB_MANUFACTURER_PART") "KEMET    C0805C106K4PAC")
        (field (name "DB_APPROVED_BY") "ISHIDDEN=T")
      )
      (libsource (lib "Database_Libs1") (part "C"))
    )
    (comp (ref "C877")
      (value "10uF")
      (footprint "SMD_0805_CAPC2012X145N")
      (fields
        (field (name "DB_PART_NUMBER") "CAP000043636")
        (field (name "DB_VALUE") "10uF")
        (field (name "DB_TOLERANCE") "10%")
        (field (name "DB_VOLTAGE") "16V")
        (field (name "DB_MANUFACTURER_PART") "KEMET    C0805C106K4PAC")
        (field (name "DB_APPROVED_BY") "ISHIDDEN=T")
      )
      (libsource (lib "Database_Libs1") (part "C"))
    )
    (comp (ref "C879")
      (value "10uF")
      (footprint "SMD_0805_CAPC2012X145N")
      (fields
        (field (name "DB_PART_NUMBER") "CAP000043636")
        (field (name "DB_VALUE") "10uF")
        (field (name "DB_TOLERANCE") "10%")
        (field (name "DB_VOLTAGE") "16V")
        (field (name "DB_MANUFACTURER_PART") "KEMET    C0805C106K4PAC")
        (field (name "DB_APPROVED_BY") "ISHIDDEN=T")
      )
      (libsource (lib "Database_Libs1") (part "C"))
    )
    (comp (ref "C880")
      (value "10uF")
      (footprint "SMD_0805_CAPC2012X145N")
      (fields
        (field (name "DB_PART_NUMBER") "CAP000043636")
        (field (name "DB_VALUE") "10uF")
        (field (name "DB_TOLERANCE") "10%")
        (field (name "DB_VOLTAGE") "16V")
        (field (name "DB_MANUFACTURER_PART") "KEMET    C0805C106K4PAC")
        (field (name "DB_APPROVED_BY") "ISHIDDEN=T")
      )
      (libsource (lib "Database_Libs1") (part "C"))
    )
    (comp (ref "C882")
      (value "10uF")
      (footprint "SMD_0805_CAPC2012X145N")
      (fields
        (field (name "DB_PART_NUMBER") "CAP000043636")
        (field (name "DB_VALUE") "10uF")
        (field (name "DB_TOLERANCE") "10%")
        (field (name "DB_VOLTAGE") "16V")
        (field (name "DB_MANUFACTURER_PART") "KEMET    C0805C106K4PAC")
        (field (name "DB_APPROVED_BY") "ISHIDDEN=T")
      )
      (libsource (lib "Database_Libs1") (part "C"))
    )
    (comp (ref "C913")
      (value "10uF")
      (footprint "SMD_0805_CAPC2012X145N")
      (fields
        (field (name "DB_PART_NUMBER") "CAP000043636")
        (field (name "DB_VALUE") "10uF")
        (field (name "DB_TOLERANCE") "10%")
        (field (name "DB_VOLTAGE") "16V")
        (field (name "DB_MANUFACTURER_PART") "KEMET    C0805C106K4PAC")
        (field (name "DB_APPROVED_BY") "ISHIDDEN=T")
      )
      (libsource (lib "Database_Libs1") (part "C"))
    )
    (comp (ref "C915")
      (value "10uF")
      (footprint "SMD_0805_CAPC2012X145N")
      (fields
        (field (name "DB_PART_NUMBER") "CAP000043636")
        (field (name "DB_VALUE") "10uF")
        (field (name "DB_TOLERANCE") "10%")
        (field (name "DB_VOLTAGE") "16V")
        (field (name "DB_MANUFACTURER_PART") "KEMET    C0805C106K4PAC")
        (field (name "DB_APPROVED_BY") "ISHIDDEN=T")
      )
      (libsource (lib "Database_Libs1") (part "C"))
    )
    (comp (ref "C916")
      (value "10uF")
      (footprint "SMD_0805_CAPC2012X145N")
      (fields
        (field (name "DB_PART_NUMBER") "CAP000043636")
        (field (name "DB_VALUE") "10uF")
        (field (name "DB_TOLERANCE") "10%")
        (field (name "DB_VOLTAGE") "16V")
        (field (name "DB_MANUFACTURER_PART") "KEMET    C0805C106K4PAC")
        (field (name "DB_APPROVED_BY") "ISHIDDEN=T")
      )
      (libsource (lib "Database_Libs1") (part "C"))
    )
    (comp (ref "C918")
      (value "10uF")
      (footprint "SMD_0805_CAPC2012X145N")
      (fields
        (field (name "DB_PART_NUMBER") "CAP000043636")
        (field (name "DB_VALUE") "10uF")
        (field (name "DB_TOLERANCE") "10%")
        (field (name "DB_VOLTAGE") "16V")
        (field (name "DB_MANUFACTURER_PART") "KEMET    C0805C106K4PAC")
        (field (name "DB_APPROVED_BY") "ISHIDDEN=T")
      )
      (libsource (lib "Database_Libs1") (part "C"))
    )
    (comp (ref "C919")
      (value "10uF")
      (footprint "SMD_0805_CAPC2012X145N")
      (fields
        (field (name "DB_PART_NUMBER") "CAP000043636")
        (field (name "DB_VALUE") "10uF")
        (field (name "DB_TOLERANCE") "10%")
        (field (name "DB_VOLTAGE") "16V")
        (field (name "DB_MANUFACTURER_PART") "KEMET    C0805C106K4PAC")
        (field (name "DB_APPROVED_BY") "ISHIDDEN=T")
      )
      (libsource (lib "Database_Libs1") (part "C"))
    )
    (comp (ref "C922")
      (value "22uF")
      (footprint "SMD_0805_CAPC2012X145N")
      (fields
        (field (name "DB_PART_NUMBER") "CAP000043686")
        (field (name "DB_VALUE") "22uF")
        (field (name "DB_TOLERANCE") "20%")
        (field (name "DB_VOLTAGE") "6.3V")
        (field (name "DB_MANUFACTURER_PART") "KEMET    C0805C226M9PAC")
        (field (name "DB_APPROVED_BY") "ISHIDDEN=T")
      )
      (libsource (lib "Database_Libs1") (part "C"))
    )
    (comp (ref "C923")
      (value "220uF")
      (footprint "SMD_1210_CAPC3225X279N")
      (fields
        (field (name "DB_PART_NUMBER") "CAP000047355")
        (field (name "DB_VALUE") "220uF")
        (field (name "DB_TOLERANCE") "20%")
        (field (name "DB_VOLTAGE") "6.3V")
        (field (name "DB_MANUFACTURER_PART") "SAMSUNG    CL32A227MQVNNNE")
        (field (name "DB_APPROVED_BY") "VSN")
      )
      (libsource (lib "Database_Libs1") (part "C"))
    )
    (comp (ref "C924")
      (value "22uF")
      (footprint "SMD_0805_CAPC2012X145N")
      (fields
        (field (name "DB_PART_NUMBER") "CAP000043686")
        (field (name "DB_VALUE") "22uF")
        (field (name "DB_TOLERANCE") "20%")
        (field (name "DB_VOLTAGE") "6.3V")
        (field (name "DB_MANUFACTURER_PART") "KEMET    C0805C226M9PAC")
        (field (name "DB_APPROVED_BY") "ISHIDDEN=T")
      )
      (libsource (lib "Database_Libs1") (part "C"))
    )
    (comp (ref "C925")
      (value "22uF")
      (footprint "SMD_0805_CAPC2012X145N")
      (fields
        (field (name "DB_PART_NUMBER") "CAP000043686")
        (field (name "DB_VALUE") "22uF")
        (field (name "DB_TOLERANCE") "20%")
        (field (name "DB_VOLTAGE") "6.3V")
        (field (name "DB_MANUFACTURER_PART") "KEMET    C0805C226M9PAC")
        (field (name "DB_APPROVED_BY") "ISHIDDEN=T")
      )
      (libsource (lib "Database_Libs1") (part "C"))
    )
    (comp (ref "C926")
      (value "220uF")
      (footprint "SMD_1210_CAPC3225X279N")
      (fields
        (field (name "DB_PART_NUMBER") "CAP000047355")
        (field (name "DB_VALUE") "220uF")
        (field (name "DB_TOLERANCE") "20%")
        (field (name "DB_VOLTAGE") "6.3V")
        (field (name "DB_MANUFACTURER_PART") "SAMSUNG    CL32A227MQVNNNE")
        (field (name "DB_APPROVED_BY") "VSN")
      )
      (libsource (lib "Database_Libs1") (part "C"))
    )
    (comp (ref "C927")
      (value "22uF")
      (footprint "SMD_0805_CAPC2012X145N")
      (fields
        (field (name "DB_PART_NUMBER") "CAP000043686")
        (field (name "DB_VALUE") "22uF")
        (field (name "DB_TOLERANCE") "20%")
        (field (name "DB_VOLTAGE") "6.3V")
        (field (name "DB_MANUFACTURER_PART") "KEMET    C0805C226M9PAC")
        (field (name "DB_APPROVED_BY") "ISHIDDEN=T")
      )
      (libsource (lib "Database_Libs1") (part "C"))
    )
    (comp (ref "C928")
      (value "22uF")
      (footprint "SMD_0805_CAPC2012X145N")
      (fields
        (field (name "DB_PART_NUMBER") "CAP000043686")
        (field (name "DB_VALUE") "22uF")
        (field (name "DB_TOLERANCE") "20%")
        (field (name "DB_VOLTAGE") "6.3V")
        (field (name "DB_MANUFACTURER_PART") "KEMET    C0805C226M9PAC")
        (field (name "DB_APPROVED_BY") "ISHIDDEN=T")
      )
      (libsource (lib "Database_Libs1") (part "C"))
    )
    (comp (ref "C929")
      (value "220uF")
      (footprint "SMD_1210_CAPC3225X279N")
      (fields
        (field (name "DB_PART_NUMBER") "CAP000047355")
        (field (name "DB_VALUE") "220uF")
        (field (name "DB_TOLERANCE") "20%")
        (field (name "DB_VOLTAGE") "6.3V")
        (field (name "DB_MANUFACTURER_PART") "SAMSUNG    CL32A227MQVNNNE")
        (field (name "DB_APPROVED_BY") "VSN")
      )
      (libsource (lib "Database_Libs1") (part "C"))
    )
    (comp (ref "C930")
      (value "22uF")
      (footprint "SMD_0805_CAPC2012X145N")
      (fields
        (field (name "DB_PART_NUMBER") "CAP000043686")
        (field (name "DB_VALUE") "22uF")
        (field (name "DB_TOLERANCE") "20%")
        (field (name "DB_VOLTAGE") "6.3V")
        (field (name "DB_MANUFACTURER_PART") "KEMET    C0805C226M9PAC")
        (field (name "DB_APPROVED_BY") "ISHIDDEN=T")
      )
      (libsource (lib "Database_Libs1") (part "C"))
    )
    (comp (ref "C931")
      (value "22uF")
      (footprint "SMD_0805_CAPC2012X145N")
      (fields
        (field (name "DB_PART_NUMBER") "CAP000043686")
        (field (name "DB_VALUE") "22uF")
        (field (name "DB_TOLERANCE") "20%")
        (field (name "DB_VOLTAGE") "6.3V")
        (field (name "DB_MANUFACTURER_PART") "KEMET    C0805C226M9PAC")
        (field (name "DB_APPROVED_BY") "ISHIDDEN=T")
      )
      (libsource (lib "Database_Libs1") (part "C"))
    )
    (comp (ref "C932")
      (value "220uF")
      (footprint "SMD_1210_CAPC3225X279N")
      (fields
        (field (name "DB_PART_NUMBER") "CAP000047355")
        (field (name "DB_VALUE") "220uF")
        (field (name "DB_TOLERANCE") "20%")
        (field (name "DB_VOLTAGE") "6.3V")
        (field (name "DB_MANUFACTURER_PART") "SAMSUNG    CL32A227MQVNNNE")
        (field (name "DB_APPROVED_BY") "VSN")
      )
      (libsource (lib "Database_Libs1") (part "C"))
    )
    (comp (ref "C933")
      (value "22uF")
      (footprint "SMD_0805_CAPC2012X145N")
      (fields
        (field (name "DB_PART_NUMBER") "CAP000043686")
        (field (name "DB_VALUE") "22uF")
        (field (name "DB_TOLERANCE") "20%")
        (field (name "DB_VOLTAGE") "6.3V")
        (field (name "DB_MANUFACTURER_PART") "KEMET    C0805C226M9PAC")
        (field (name "DB_APPROVED_BY") "ISHIDDEN=T")
      )
      (libsource (lib "Database_Libs1") (part "C"))
    )
    (comp (ref "C934")
      (value "22uF")
      (footprint "SMD_0805_CAPC2012X145N")
      (fields
        (field (name "DB_PART_NUMBER") "CAP000043686")
        (field (name "DB_VALUE") "22uF")
        (field (name "DB_TOLERANCE") "20%")
        (field (name "DB_VOLTAGE") "6.3V")
        (field (name "DB_MANUFACTURER_PART") "KEMET    C0805C226M9PAC")
        (field (name "DB_APPROVED_BY") "ISHIDDEN=T")
      )
      (libsource (lib "Database_Libs1") (part "C"))
    )
    (comp (ref "C935")
      (value "220uF")
      (footprint "SMD_1210_CAPC3225X279N")
      (fields
        (field (name "DB_PART_NUMBER") "CAP000047355")
        (field (name "DB_VALUE") "220uF")
        (field (name "DB_TOLERANCE") "20%")
        (field (name "DB_VOLTAGE") "6.3V")
        (field (name "DB_MANUFACTURER_PART") "SAMSUNG    CL32A227MQVNNNE")
        (field (name "DB_APPROVED_BY") "VSN")
      )
      (libsource (lib "Database_Libs1") (part "C"))
    )
    (comp (ref "C936")
      (value "22uF")
      (footprint "SMD_0805_CAPC2012X145N")
      (fields
        (field (name "DB_PART_NUMBER") "CAP000043686")
        (field (name "DB_VALUE") "22uF")
        (field (name "DB_TOLERANCE") "20%")
        (field (name "DB_VOLTAGE") "6.3V")
        (field (name "DB_MANUFACTURER_PART") "KEMET    C0805C226M9PAC")
        (field (name "DB_APPROVED_BY") "ISHIDDEN=T")
      )
      (libsource (lib "Database_Libs1") (part "C"))
    )
    (comp (ref "C937")
      (value "22uF")
      (footprint "SMD_0805_CAPC2012X145N")
      (fields
        (field (name "DB_PART_NUMBER") "CAP000043686")
        (field (name "DB_VALUE") "22uF")
        (field (name "DB_TOLERANCE") "20%")
        (field (name "DB_VOLTAGE") "6.3V")
        (field (name "DB_MANUFACTURER_PART") "KEMET    C0805C226M9PAC")
        (field (name "DB_APPROVED_BY") "ISHIDDEN=T")
      )
      (libsource (lib "Database_Libs1") (part "C"))
    )
    (comp (ref "C938")
      (value "220uF")
      (footprint "SMD_1210_CAPC3225X279N")
      (fields
        (field (name "DB_PART_NUMBER") "CAP000047355")
        (field (name "DB_VALUE") "220uF")
        (field (name "DB_TOLERANCE") "20%")
        (field (name "DB_VOLTAGE") "6.3V")
        (field (name "DB_MANUFACTURER_PART") "SAMSUNG    CL32A227MQVNNNE")
        (field (name "DB_APPROVED_BY") "VSN")
      )
      (libsource (lib "Database_Libs1") (part "C"))
    )
    (comp (ref "C939")
      (value "22uF")
      (footprint "SMD_0805_CAPC2012X145N")
      (fields
        (field (name "DB_PART_NUMBER") "CAP000043686")
        (field (name "DB_VALUE") "22uF")
        (field (name "DB_TOLERANCE") "20%")
        (field (name "DB_VOLTAGE") "6.3V")
        (field (name "DB_MANUFACTURER_PART") "KEMET    C0805C226M9PAC")
        (field (name "DB_APPROVED_BY") "ISHIDDEN=T")
      )
      (libsource (lib "Database_Libs1") (part "C"))
    )
    (comp (ref "C940")
      (value "22uF")
      (footprint "SMD_0805_CAPC2012X145N")
      (fields
        (field (name "DB_PART_NUMBER") "CAP000043686")
        (field (name "DB_VALUE") "22uF")
        (field (name "DB_TOLERANCE") "20%")
        (field (name "DB_VOLTAGE") "6.3V")
        (field (name "DB_MANUFACTURER_PART") "KEMET    C0805C226M9PAC")
        (field (name "DB_APPROVED_BY") "ISHIDDEN=T")
      )
      (libsource (lib "Database_Libs1") (part "C"))
    )
    (comp (ref "C941")
      (value "220uF")
      (footprint "SMD_1210_CAPC3225X279N")
      (fields
        (field (name "DB_PART_NUMBER") "CAP000047355")
        (field (name "DB_VALUE") "220uF")
        (field (name "DB_TOLERANCE") "20%")
        (field (name "DB_VOLTAGE") "6.3V")
        (field (name "DB_MANUFACTURER_PART") "SAMSUNG    CL32A227MQVNNNE")
        (field (name "DB_APPROVED_BY") "VSN")
      )
      (libsource (lib "Database_Libs1") (part "C"))
    )
    (comp (ref "C942")
      (value "22uF")
      (footprint "SMD_0805_CAPC2012X145N")
      (fields
        (field (name "DB_PART_NUMBER") "CAP000043686")
        (field (name "DB_VALUE") "22uF")
        (field (name "DB_TOLERANCE") "20%")
        (field (name "DB_VOLTAGE") "6.3V")
        (field (name "DB_MANUFACTURER_PART") "KEMET    C0805C226M9PAC")
        (field (name "DB_APPROVED_BY") "ISHIDDEN=T")
      )
      (libsource (lib "Database_Libs1") (part "C"))
    )
    (comp (ref "C943")
      (value "22uF")
      (footprint "SMD_0805_CAPC2012X145N")
      (fields
        (field (name "DB_PART_NUMBER") "CAP000043686")
        (field (name "DB_VALUE") "22uF")
        (field (name "DB_TOLERANCE") "20%")
        (field (name "DB_VOLTAGE") "6.3V")
        (field (name "DB_MANUFACTURER_PART") "KEMET    C0805C226M9PAC")
        (field (name "DB_APPROVED_BY") "ISHIDDEN=T")
      )
      (libsource (lib "Database_Libs1") (part "C"))
    )
    (comp (ref "C944")
      (value "220uF")
      (footprint "SMD_1210_CAPC3225X279N")
      (fields
        (field (name "DB_PART_NUMBER") "CAP000047355")
        (field (name "DB_VALUE") "220uF")
        (field (name "DB_TOLERANCE") "20%")
        (field (name "DB_VOLTAGE") "6.3V")
        (field (name "DB_MANUFACTURER_PART") "SAMSUNG    CL32A227MQVNNNE")
        (field (name "DB_APPROVED_BY") "VSN")
      )
      (libsource (lib "Database_Libs1") (part "C"))
    )
    (comp (ref "C945")
      (value "22uF")
      (footprint "SMD_0805_CAPC2012X145N")
      (fields
        (field (name "DB_PART_NUMBER") "CAP000043686")
        (field (name "DB_VALUE") "22uF")
        (field (name "DB_TOLERANCE") "20%")
        (field (name "DB_VOLTAGE") "6.3V")
        (field (name "DB_MANUFACTURER_PART") "KEMET    C0805C226M9PAC")
        (field (name "DB_APPROVED_BY") "ISHIDDEN=T")
      )
      (libsource (lib "Database_Libs1") (part "C"))
    )
    (comp (ref "C946")
      (value "22uF")
      (footprint "SMD_0805_CAPC2012X145N")
      (fields
        (field (name "DB_PART_NUMBER") "CAP000043686")
        (field (name "DB_VALUE") "22uF")
        (field (name "DB_TOLERANCE") "20%")
        (field (name "DB_VOLTAGE") "6.3V")
        (field (name "DB_MANUFACTURER_PART") "KEMET    C0805C226M9PAC")
        (field (name "DB_APPROVED_BY") "ISHIDDEN=T")
      )
      (libsource (lib "Database_Libs1") (part "C"))
    )
    (comp (ref "C947")
      (value "220uF")
      (footprint "SMD_1210_CAPC3225X279N")
      (fields
        (field (name "DB_PART_NUMBER") "CAP000047355")
        (field (name "DB_VALUE") "220uF")
        (field (name "DB_TOLERANCE") "20%")
        (field (name "DB_VOLTAGE") "6.3V")
        (field (name "DB_MANUFACTURER_PART") "SAMSUNG    CL32A227MQVNNNE")
        (field (name "DB_APPROVED_BY") "VSN")
      )
      (libsource (lib "Database_Libs1") (part "C"))
    )
    (comp (ref "C948")
      (value "22uF")
      (footprint "SMD_0805_CAPC2012X145N")
      (fields
        (field (name "DB_PART_NUMBER") "CAP000043686")
        (field (name "DB_VALUE") "22uF")
        (field (name "DB_TOLERANCE") "20%")
        (field (name "DB_VOLTAGE") "6.3V")
        (field (name "DB_MANUFACTURER_PART") "KEMET    C0805C226M9PAC")
        (field (name "DB_APPROVED_BY") "ISHIDDEN=T")
      )
      (libsource (lib "Database_Libs1") (part "C"))
    )
    (comp (ref "C949")
      (value "22uF")
      (footprint "SMD_0805_CAPC2012X145N")
      (fields
        (field (name "DB_PART_NUMBER") "CAP000043686")
        (field (name "DB_VALUE") "22uF")
        (field (name "DB_TOLERANCE") "20%")
        (field (name "DB_VOLTAGE") "6.3V")
        (field (name "DB_MANUFACTURER_PART") "KEMET    C0805C226M9PAC")
        (field (name "DB_APPROVED_BY") "ISHIDDEN=T")
      )
      (libsource (lib "Database_Libs1") (part "C"))
    )
    (comp (ref "C950")
      (value "220uF")
      (footprint "SMD_1210_CAPC3225X279N")
      (fields
        (field (name "DB_PART_NUMBER") "CAP000047355")
        (field (name "DB_VALUE") "220uF")
        (field (name "DB_TOLERANCE") "20%")
        (field (name "DB_VOLTAGE") "6.3V")
        (field (name "DB_MANUFACTURER_PART") "SAMSUNG    CL32A227MQVNNNE")
        (field (name "DB_APPROVED_BY") "VSN")
      )
      (libsource (lib "Database_Libs1") (part "C"))
    )
    (comp (ref "C951")
      (value "22uF")
      (footprint "SMD_0805_CAPC2012X145N")
      (fields
        (field (name "DB_PART_NUMBER") "CAP000043686")
        (field (name "DB_VALUE") "22uF")
        (field (name "DB_TOLERANCE") "20%")
        (field (name "DB_VOLTAGE") "6.3V")
        (field (name "DB_MANUFACTURER_PART") "KEMET    C0805C226M9PAC")
        (field (name "DB_APPROVED_BY") "ISHIDDEN=T")
      )
      (libsource (lib "Database_Libs1") (part "C"))
    )
    (comp (ref "C952")
      (value "22uF")
      (footprint "SMD_0805_CAPC2012X145N")
      (fields
        (field (name "DB_PART_NUMBER") "CAP000043686")
        (field (name "DB_VALUE") "22uF")
        (field (name "DB_TOLERANCE") "20%")
        (field (name "DB_VOLTAGE") "6.3V")
        (field (name "DB_MANUFACTURER_PART") "KEMET    C0805C226M9PAC")
        (field (name "DB_APPROVED_BY") "ISHIDDEN=T")
      )
      (libsource (lib "Database_Libs1") (part "C"))
    )
    (comp (ref "C953")
      (value "220uF")
      (footprint "SMD_1210_CAPC3225X279N")
      (fields
        (field (name "DB_PART_NUMBER") "CAP000047355")
        (field (name "DB_VALUE") "220uF")
        (field (name "DB_TOLERANCE") "20%")
        (field (name "DB_VOLTAGE") "6.3V")
        (field (name "DB_MANUFACTURER_PART") "SAMSUNG    CL32A227MQVNNNE")
        (field (name "DB_APPROVED_BY") "VSN")
      )
      (libsource (lib "Database_Libs1") (part "C"))
    )
    (comp (ref "C954")
      (value "22uF")
      (footprint "SMD_0805_CAPC2012X145N")
      (fields
        (field (name "DB_PART_NUMBER") "CAP000043686")
        (field (name "DB_VALUE") "22uF")
        (field (name "DB_TOLERANCE") "20%")
        (field (name "DB_VOLTAGE") "6.3V")
        (field (name "DB_MANUFACTURER_PART") "KEMET    C0805C226M9PAC")
        (field (name "DB_APPROVED_BY") "ISHIDDEN=T")
      )
      (libsource (lib "Database_Libs1") (part "C"))
    )
    (comp (ref "C955")
      (value "22uF")
      (footprint "SMD_0805_CAPC2012X145N")
      (fields
        (field (name "DB_PART_NUMBER") "CAP000043686")
        (field (name "DB_VALUE") "22uF")
        (field (name "DB_TOLERANCE") "20%")
        (field (name "DB_VOLTAGE") "6.3V")
        (field (name "DB_MANUFACTURER_PART") "KEMET    C0805C226M9PAC")
        (field (name "DB_APPROVED_BY") "ISHIDDEN=T")
      )
      (libsource (lib "Database_Libs1") (part "C"))
    )
    (comp (ref "C956")
      (value "220uF")
      (footprint "SMD_1210_CAPC3225X279N")
      (fields
        (field (name "DB_PART_NUMBER") "CAP000047355")
        (field (name "DB_VALUE") "220uF")
        (field (name "DB_TOLERANCE") "20%")
        (field (name "DB_VOLTAGE") "6.3V")
        (field (name "DB_MANUFACTURER_PART") "SAMSUNG    CL32A227MQVNNNE")
        (field (name "DB_APPROVED_BY") "VSN")
      )
      (libsource (lib "Database_Libs1") (part "C"))
    )
    (comp (ref "C957")
      (value "22uF")
      (footprint "SMD_0805_CAPC2012X145N")
      (fields
        (field (name "DB_PART_NUMBER") "CAP000043686")
        (field (name "DB_VALUE") "22uF")
        (field (name "DB_TOLERANCE") "20%")
        (field (name "DB_VOLTAGE") "6.3V")
        (field (name "DB_MANUFACTURER_PART") "KEMET    C0805C226M9PAC")
        (field (name "DB_APPROVED_BY") "ISHIDDEN=T")
      )
      (libsource (lib "Database_Libs1") (part "C"))
    )
    (comp (ref "C958")
      (value "22uF")
      (footprint "SMD_0805_CAPC2012X145N")
      (fields
        (field (name "DB_PART_NUMBER") "CAP000043686")
        (field (name "DB_VALUE") "22uF")
        (field (name "DB_TOLERANCE") "20%")
        (field (name "DB_VOLTAGE") "6.3V")
        (field (name "DB_MANUFACTURER_PART") "KEMET    C0805C226M9PAC")
        (field (name "DB_APPROVED_BY") "ISHIDDEN=T")
      )
      (libsource (lib "Database_Libs1") (part "C"))
    )
    (comp (ref "C959")
      (value "220uF")
      (footprint "SMD_1210_CAPC3225X279N")
      (fields
        (field (name "DB_PART_NUMBER") "CAP000047355")
        (field (name "DB_VALUE") "220uF")
        (field (name "DB_TOLERANCE") "20%")
        (field (name "DB_VOLTAGE") "6.3V")
        (field (name "DB_MANUFACTURER_PART") "SAMSUNG    CL32A227MQVNNNE")
        (field (name "DB_APPROVED_BY") "VSN")
      )
      (libsource (lib "Database_Libs1") (part "C"))
    )
    (comp (ref "C960")
      (value "22uF")
      (footprint "SMD_0805_CAPC2012X145N")
      (fields
        (field (name "DB_PART_NUMBER") "CAP000043686")
        (field (name "DB_VALUE") "22uF")
        (field (name "DB_TOLERANCE") "20%")
        (field (name "DB_VOLTAGE") "6.3V")
        (field (name "DB_MANUFACTURER_PART") "KEMET    C0805C226M9PAC")
        (field (name "DB_APPROVED_BY") "ISHIDDEN=T")
      )
      (libsource (lib "Database_Libs1") (part "C"))
    )
    (comp (ref "C961")
      (value "22uF")
      (footprint "SMD_0805_CAPC2012X145N")
      (fields
        (field (name "DB_PART_NUMBER") "CAP000043686")
        (field (name "DB_VALUE") "22uF")
        (field (name "DB_TOLERANCE") "20%")
        (field (name "DB_VOLTAGE") "6.3V")
        (field (name "DB_MANUFACTURER_PART") "KEMET    C0805C226M9PAC")
        (field (name "DB_APPROVED_BY") "ISHIDDEN=T")
      )
      (libsource (lib "Database_Libs1") (part "C"))
    )
    (comp (ref "C962")
      (value "220uF")
      (footprint "SMD_1210_CAPC3225X279N")
      (fields
        (field (name "DB_PART_NUMBER") "CAP000047355")
        (field (name "DB_VALUE") "220uF")
        (field (name "DB_TOLERANCE") "20%")
        (field (name "DB_VOLTAGE") "6.3V")
        (field (name "DB_MANUFACTURER_PART") "SAMSUNG    CL32A227MQVNNNE")
        (field (name "DB_APPROVED_BY") "VSN")
      )
      (libsource (lib "Database_Libs1") (part "C"))
    )
    (comp (ref "C963")
      (value "22uF")
      (footprint "SMD_0805_CAPC2012X145N")
      (fields
        (field (name "DB_PART_NUMBER") "CAP000043686")
        (field (name "DB_VALUE") "22uF")
        (field (name "DB_TOLERANCE") "20%")
        (field (name "DB_VOLTAGE") "6.3V")
        (field (name "DB_MANUFACTURER_PART") "KEMET    C0805C226M9PAC")
        (field (name "DB_APPROVED_BY") "ISHIDDEN=T")
      )
      (libsource (lib "Database_Libs1") (part "C"))
    )
    (comp (ref "C964")
      (value "22uF")
      (footprint "SMD_0805_CAPC2012X145N")
      (fields
        (field (name "DB_PART_NUMBER") "CAP000043686")
        (field (name "DB_VALUE") "22uF")
        (field (name "DB_TOLERANCE") "20%")
        (field (name "DB_VOLTAGE") "6.3V")
        (field (name "DB_MANUFACTURER_PART") "KEMET    C0805C226M9PAC")
        (field (name "DB_APPROVED_BY") "ISHIDDEN=T")
      )
      (libsource (lib "Database_Libs1") (part "C"))
    )
    (comp (ref "C965")
      (value "220uF")
      (footprint "SMD_1210_CAPC3225X279N")
      (fields
        (field (name "DB_PART_NUMBER") "CAP000047355")
        (field (name "DB_VALUE") "220uF")
        (field (name "DB_TOLERANCE") "20%")
        (field (name "DB_VOLTAGE") "6.3V")
        (field (name "DB_MANUFACTURER_PART") "SAMSUNG    CL32A227MQVNNNE")
        (field (name "DB_APPROVED_BY") "VSN")
      )
      (libsource (lib "Database_Libs1") (part "C"))
    )
    (comp (ref "C966")
      (value "22uF")
      (footprint "SMD_0805_CAPC2012X145N")
      (fields
        (field (name "DB_PART_NUMBER") "CAP000043686")
        (field (name "DB_VALUE") "22uF")
        (field (name "DB_TOLERANCE") "20%")
        (field (name "DB_VOLTAGE") "6.3V")
        (field (name "DB_MANUFACTURER_PART") "KEMET    C0805C226M9PAC")
        (field (name "DB_APPROVED_BY") "ISHIDDEN=T")
      )
      (libsource (lib "Database_Libs1") (part "C"))
    )
    (comp (ref "C967")
      (value "22uF")
      (footprint "SMD_0805_CAPC2012X145N")
      (fields
        (field (name "DB_PART_NUMBER") "CAP000043686")
        (field (name "DB_VALUE") "22uF")
        (field (name "DB_TOLERANCE") "20%")
        (field (name "DB_VOLTAGE") "6.3V")
        (field (name "DB_MANUFACTURER_PART") "KEMET    C0805C226M9PAC")
        (field (name "DB_APPROVED_BY") "ISHIDDEN=T")
      )
      (libsource (lib "Database_Libs1") (part "C"))
    )
    (comp (ref "C968")
      (value "220uF")
      (footprint "SMD_1210_CAPC3225X279N")
      (fields
        (field (name "DB_PART_NUMBER") "CAP000047355")
        (field (name "DB_VALUE") "220uF")
        (field (name "DB_TOLERANCE") "20%")
        (field (name "DB_VOLTAGE") "6.3V")
        (field (name "DB_MANUFACTURER_PART") "SAMSUNG    CL32A227MQVNNNE")
        (field (name "DB_APPROVED_BY") "VSN")
      )
      (libsource (lib "Database_Libs1") (part "C"))
    )
    (comp (ref "C969")
      (value "22uF")
      (footprint "SMD_0805_CAPC2012X145N")
      (fields
        (field (name "DB_PART_NUMBER") "CAP000043686")
        (field (name "DB_VALUE") "22uF")
        (field (name "DB_TOLERANCE") "20%")
        (field (name "DB_VOLTAGE") "6.3V")
        (field (name "DB_MANUFACTURER_PART") "KEMET    C0805C226M9PAC")
        (field (name "DB_APPROVED_BY") "ISHIDDEN=T")
      )
      (libsource (lib "Database_Libs1") (part "C"))
    )
    (comp (ref "C970")
      (value "22uF")
      (footprint "SMD_0805_CAPC2012X145N")
      (fields
        (field (name "DB_PART_NUMBER") "CAP000043686")
        (field (name "DB_VALUE") "22uF")
        (field (name "DB_TOLERANCE") "20%")
        (field (name "DB_VOLTAGE") "6.3V")
        (field (name "DB_MANUFACTURER_PART") "KEMET    C0805C226M9PAC")
        (field (name "DB_APPROVED_BY") "ISHIDDEN=T")
      )
      (libsource (lib "Database_Libs1") (part "C"))
    )
    (comp (ref "C971")
      (value "220uF")
      (footprint "SMD_1210_CAPC3225X279N")
      (fields
        (field (name "DB_PART_NUMBER") "CAP000047355")
        (field (name "DB_VALUE") "220uF")
        (field (name "DB_TOLERANCE") "20%")
        (field (name "DB_VOLTAGE") "6.3V")
        (field (name "DB_MANUFACTURER_PART") "SAMSUNG    CL32A227MQVNNNE")
        (field (name "DB_APPROVED_BY") "VSN")
      )
      (libsource (lib "Database_Libs1") (part "C"))
    )
    (comp (ref "C972")
      (value "22uF")
      (footprint "SMD_0805_CAPC2012X145N")
      (fields
        (field (name "DB_PART_NUMBER") "CAP000043686")
        (field (name "DB_VALUE") "22uF")
        (field (name "DB_TOLERANCE") "20%")
        (field (name "DB_VOLTAGE") "6.3V")
        (field (name "DB_MANUFACTURER_PART") "KEMET    C0805C226M9PAC")
        (field (name "DB_APPROVED_BY") "ISHIDDEN=T")
      )
      (libsource (lib "Database_Libs1") (part "C"))
    )
    (comp (ref "C973")
      (value "22uF")
      (footprint "SMD_0805_CAPC2012X145N")
      (fields
        (field (name "DB_PART_NUMBER") "CAP000043686")
        (field (name "DB_VALUE") "22uF")
        (field (name "DB_TOLERANCE") "20%")
        (field (name "DB_VOLTAGE") "6.3V")
        (field (name "DB_MANUFACTURER_PART") "KEMET    C0805C226M9PAC")
        (field (name "DB_APPROVED_BY") "ISHIDDEN=T")
      )
      (libsource (lib "Database_Libs1") (part "C"))
    )
    (comp (ref "C974")
      (value "220uF")
      (footprint "SMD_1210_CAPC3225X279N")
      (fields
        (field (name "DB_PART_NUMBER") "CAP000047355")
        (field (name "DB_VALUE") "220uF")
        (field (name "DB_TOLERANCE") "20%")
        (field (name "DB_VOLTAGE") "6.3V")
        (field (name "DB_MANUFACTURER_PART") "SAMSUNG    CL32A227MQVNNNE")
        (field (name "DB_APPROVED_BY") "VSN")
      )
      (libsource (lib "Database_Libs1") (part "C"))
    )
    (comp (ref "C975")
      (value "22uF")
      (footprint "SMD_0805_CAPC2012X145N")
      (fields
        (field (name "DB_PART_NUMBER") "CAP000043686")
        (field (name "DB_VALUE") "22uF")
        (field (name "DB_TOLERANCE") "20%")
        (field (name "DB_VOLTAGE") "6.3V")
        (field (name "DB_MANUFACTURER_PART") "KEMET    C0805C226M9PAC")
        (field (name "DB_APPROVED_BY") "ISHIDDEN=T")
      )
      (libsource (lib "Database_Libs1") (part "C"))
    )
    (comp (ref "C976")
      (value "22uF")
      (footprint "SMD_0805_CAPC2012X145N")
      (fields
        (field (name "DB_PART_NUMBER") "CAP000043686")
        (field (name "DB_VALUE") "22uF")
        (field (name "DB_TOLERANCE") "20%")
        (field (name "DB_VOLTAGE") "6.3V")
        (field (name "DB_MANUFACTURER_PART") "KEMET    C0805C226M9PAC")
        (field (name "DB_APPROVED_BY") "ISHIDDEN=T")
      )
      (libsource (lib "Database_Libs1") (part "C"))
    )
    (comp (ref "C977")
      (value "220uF")
      (footprint "SMD_1210_CAPC3225X279N")
      (fields
        (field (name "DB_PART_NUMBER") "CAP000047355")
        (field (name "DB_VALUE") "220uF")
        (field (name "DB_TOLERANCE") "20%")
        (field (name "DB_VOLTAGE") "6.3V")
        (field (name "DB_MANUFACTURER_PART") "SAMSUNG    CL32A227MQVNNNE")
        (field (name "DB_APPROVED_BY") "VSN")
      )
      (libsource (lib "Database_Libs1") (part "C"))
    )
    (comp (ref "C978")
      (value "22uF")
      (footprint "SMD_0805_CAPC2012X145N")
      (fields
        (field (name "DB_PART_NUMBER") "CAP000043686")
        (field (name "DB_VALUE") "22uF")
        (field (name "DB_TOLERANCE") "20%")
        (field (name "DB_VOLTAGE") "6.3V")
        (field (name "DB_MANUFACTURER_PART") "KEMET    C0805C226M9PAC")
        (field (name "DB_APPROVED_BY") "ISHIDDEN=T")
      )
      (libsource (lib "Database_Libs1") (part "C"))
    )
    (comp (ref "C979")
      (value "22uF")
      (footprint "SMD_0805_CAPC2012X145N")
      (fields
        (field (name "DB_PART_NUMBER") "CAP000043686")
        (field (name "DB_VALUE") "22uF")
        (field (name "DB_TOLERANCE") "20%")
        (field (name "DB_VOLTAGE") "6.3V")
        (field (name "DB_MANUFACTURER_PART") "KEMET    C0805C226M9PAC")
        (field (name "DB_APPROVED_BY") "ISHIDDEN=T")
      )
      (libsource (lib "Database_Libs1") (part "C"))
    )
    (comp (ref "C980")
      (value "220uF")
      (footprint "SMD_1210_CAPC3225X279N")
      (fields
        (field (name "DB_PART_NUMBER") "CAP000047355")
        (field (name "DB_VALUE") "220uF")
        (field (name "DB_TOLERANCE") "20%")
        (field (name "DB_VOLTAGE") "6.3V")
        (field (name "DB_MANUFACTURER_PART") "SAMSUNG    CL32A227MQVNNNE")
        (field (name "DB_APPROVED_BY") "VSN")
      )
      (libsource (lib "Database_Libs1") (part "C"))
    )
    (comp (ref "C981")
      (value "22uF")
      (footprint "SMD_0805_CAPC2012X145N")
      (fields
        (field (name "DB_PART_NUMBER") "CAP000043686")
        (field (name "DB_VALUE") "22uF")
        (field (name "DB_TOLERANCE") "20%")
        (field (name "DB_VOLTAGE") "6.3V")
        (field (name "DB_MANUFACTURER_PART") "KEMET    C0805C226M9PAC")
        (field (name "DB_APPROVED_BY") "ISHIDDEN=T")
      )
      (libsource (lib "Database_Libs1") (part "C"))
    )
    (comp (ref "C982")
      (value "22uF")
      (footprint "SMD_0805_CAPC2012X145N")
      (fields
        (field (name "DB_PART_NUMBER") "CAP000043686")
        (field (name "DB_VALUE") "22uF")
        (field (name "DB_TOLERANCE") "20%")
        (field (name "DB_VOLTAGE") "6.3V")
        (field (name "DB_MANUFACTURER_PART") "KEMET    C0805C226M9PAC")
        (field (name "DB_APPROVED_BY") "ISHIDDEN=T")
      )
      (libsource (lib "Database_Libs1") (part "C"))
    )
    (comp (ref "C983")
      (value "220uF")
      (footprint "SMD_1210_CAPC3225X279N")
      (fields
        (field (name "DB_PART_NUMBER") "CAP000047355")
        (field (name "DB_VALUE") "220uF")
        (field (name "DB_TOLERANCE") "20%")
        (field (name "DB_VOLTAGE") "6.3V")
        (field (name "DB_MANUFACTURER_PART") "SAMSUNG    CL32A227MQVNNNE")
        (field (name "DB_APPROVED_BY") "VSN")
      )
      (libsource (lib "Database_Libs1") (part "C"))
    )
    (comp (ref "C984")
      (value "22uF")
      (footprint "SMD_0805_CAPC2012X145N")
      (fields
        (field (name "DB_PART_NUMBER") "CAP000043686")
        (field (name "DB_VALUE") "22uF")
        (field (name "DB_TOLERANCE") "20%")
        (field (name "DB_VOLTAGE") "6.3V")
        (field (name "DB_MANUFACTURER_PART") "KEMET    C0805C226M9PAC")
        (field (name "DB_APPROVED_BY") "ISHIDDEN=T")
      )
      (libsource (lib "Database_Libs1") (part "C"))
    )
    (comp (ref "C985")
      (value "22uF")
      (footprint "SMD_0805_CAPC2012X145N")
      (fields
        (field (name "DB_PART_NUMBER") "CAP000043686")
        (field (name "DB_VALUE") "22uF")
        (field (name "DB_TOLERANCE") "20%")
        (field (name "DB_VOLTAGE") "6.3V")
        (field (name "DB_MANUFACTURER_PART") "KEMET    C0805C226M9PAC")
        (field (name "DB_APPROVED_BY") "ISHIDDEN=T")
      )
      (libsource (lib "Database_Libs1") (part "C"))
    )
    (comp (ref "C986")
      (value "220uF")
      (footprint "SMD_1210_CAPC3225X279N")
      (fields
        (field (name "DB_PART_NUMBER") "CAP000047355")
        (field (name "DB_VALUE") "220uF")
        (field (name "DB_TOLERANCE") "20%")
        (field (name "DB_VOLTAGE") "6.3V")
        (field (name "DB_MANUFACTURER_PART") "SAMSUNG    CL32A227MQVNNNE")
        (field (name "DB_APPROVED_BY") "VSN")
      )
      (libsource (lib "Database_Libs1") (part "C"))
    )
    (comp (ref "C987")
      (value "22uF")
      (footprint "SMD_0805_CAPC2012X145N")
      (fields
        (field (name "DB_PART_NUMBER") "CAP000043686")
        (field (name "DB_VALUE") "22uF")
        (field (name "DB_TOLERANCE") "20%")
        (field (name "DB_VOLTAGE") "6.3V")
        (field (name "DB_MANUFACTURER_PART") "KEMET    C0805C226M9PAC")
        (field (name "DB_APPROVED_BY") "ISHIDDEN=T")
      )
      (libsource (lib "Database_Libs1") (part "C"))
    )
    (comp (ref "C988")
      (value "22uF")
      (footprint "SMD_0805_CAPC2012X145N")
      (fields
        (field (name "DB_PART_NUMBER") "CAP000043686")
        (field (name "DB_VALUE") "22uF")
        (field (name "DB_TOLERANCE") "20%")
        (field (name "DB_VOLTAGE") "6.3V")
        (field (name "DB_MANUFACTURER_PART") "KEMET    C0805C226M9PAC")
        (field (name "DB_APPROVED_BY") "ISHIDDEN=T")
      )
      (libsource (lib "Database_Libs1") (part "C"))
    )
    (comp (ref "C989")
      (value "220uF")
      (footprint "SMD_1210_CAPC3225X279N")
      (fields
        (field (name "DB_PART_NUMBER") "CAP000047355")
        (field (name "DB_VALUE") "220uF")
        (field (name "DB_TOLERANCE") "20%")
        (field (name "DB_VOLTAGE") "6.3V")
        (field (name "DB_MANUFACTURER_PART") "SAMSUNG    CL32A227MQVNNNE")
        (field (name "DB_APPROVED_BY") "VSN")
      )
      (libsource (lib "Database_Libs1") (part "C"))
    )
    (comp (ref "C990")
      (value "22uF")
      (footprint "SMD_0805_CAPC2012X145N")
      (fields
        (field (name "DB_PART_NUMBER") "CAP000043686")
        (field (name "DB_VALUE") "22uF")
        (field (name "DB_TOLERANCE") "20%")
        (field (name "DB_VOLTAGE") "6.3V")
        (field (name "DB_MANUFACTURER_PART") "KEMET    C0805C226M9PAC")
        (field (name "DB_APPROVED_BY") "ISHIDDEN=T")
      )
      (libsource (lib "Database_Libs1") (part "C"))
    )
    (comp (ref "C991")
      (value "22uF")
      (footprint "SMD_0805_CAPC2012X145N")
      (fields
        (field (name "DB_PART_NUMBER") "CAP000043686")
        (field (name "DB_VALUE") "22uF")
        (field (name "DB_TOLERANCE") "20%")
        (field (name "DB_VOLTAGE") "6.3V")
        (field (name "DB_MANUFACTURER_PART") "KEMET    C0805C226M9PAC")
        (field (name "DB_APPROVED_BY") "ISHIDDEN=T")
      )
      (libsource (lib "Database_Libs1") (part "C"))
    )
    (comp (ref "C992")
      (value "220uF")
      (footprint "SMD_1210_CAPC3225X279N")
      (fields
        (field (name "DB_PART_NUMBER") "CAP000047355")
        (field (name "DB_VALUE") "220uF")
        (field (name "DB_TOLERANCE") "20%")
        (field (name "DB_VOLTAGE") "6.3V")
        (field (name "DB_MANUFACTURER_PART") "SAMSUNG    CL32A227MQVNNNE")
        (field (name "DB_APPROVED_BY") "VSN")
      )
      (libsource (lib "Database_Libs1") (part "C"))
    )
    (comp (ref "C993")
      (value "22uF")
      (footprint "SMD_0805_CAPC2012X145N")
      (fields
        (field (name "DB_PART_NUMBER") "CAP000043686")
        (field (name "DB_VALUE") "22uF")
        (field (name "DB_TOLERANCE") "20%")
        (field (name "DB_VOLTAGE") "6.3V")
        (field (name "DB_MANUFACTURER_PART") "KEMET    C0805C226M9PAC")
        (field (name "DB_APPROVED_BY") "ISHIDDEN=T")
      )
      (libsource (lib "Database_Libs1") (part "C"))
    )
    (comp (ref "C994")
      (value "22uF")
      (footprint "SMD_0805_CAPC2012X145N")
      (fields
        (field (name "DB_PART_NUMBER") "CAP000043686")
        (field (name "DB_VALUE") "22uF")
        (field (name "DB_TOLERANCE") "20%")
        (field (name "DB_VOLTAGE") "6.3V")
        (field (name "DB_MANUFACTURER_PART") "KEMET    C0805C226M9PAC")
        (field (name "DB_APPROVED_BY") "ISHIDDEN=T")
      )
      (libsource (lib "Database_Libs1") (part "C"))
    )
    (comp (ref "C995")
      (value "220uF")
      (footprint "SMD_1210_CAPC3225X279N")
      (fields
        (field (name "DB_PART_NUMBER") "CAP000047355")
        (field (name "DB_VALUE") "220uF")
        (field (name "DB_TOLERANCE") "20%")
        (field (name "DB_VOLTAGE") "6.3V")
        (field (name "DB_MANUFACTURER_PART") "SAMSUNG    CL32A227MQVNNNE")
        (field (name "DB_APPROVED_BY") "VSN")
      )
      (libsource (lib "Database_Libs1") (part "C"))
    )
    (comp (ref "C996")
      (value "22uF")
      (footprint "SMD_0805_CAPC2012X145N")
      (fields
        (field (name "DB_PART_NUMBER") "CAP000043686")
        (field (name "DB_VALUE") "22uF")
        (field (name "DB_TOLERANCE") "20%")
        (field (name "DB_VOLTAGE") "6.3V")
        (field (name "DB_MANUFACTURER_PART") "KEMET    C0805C226M9PAC")
        (field (name "DB_APPROVED_BY") "ISHIDDEN=T")
      )
      (libsource (lib "Database_Libs1") (part "C"))
    )
    (comp (ref "C997")
      (value "22uF")
      (footprint "SMD_0805_CAPC2012X145N")
      (fields
        (field (name "DB_PART_NUMBER") "CAP000043686")
        (field (name "DB_VALUE") "22uF")
        (field (name "DB_TOLERANCE") "20%")
        (field (name "DB_VOLTAGE") "6.3V")
        (field (name "DB_MANUFACTURER_PART") "KEMET    C0805C226M9PAC")
        (field (name "DB_APPROVED_BY") "ISHIDDEN=T")
      )
      (libsource (lib "Database_Libs1") (part "C"))
    )
    (comp (ref "C998")
      (value "220uF")
      (footprint "SMD_1210_CAPC3225X279N")
      (fields
        (field (name "DB_PART_NUMBER") "CAP000047355")
        (field (name "DB_VALUE") "220uF")
        (field (name "DB_TOLERANCE") "20%")
        (field (name "DB_VOLTAGE") "6.3V")
        (field (name "DB_MANUFACTURER_PART") "SAMSUNG    CL32A227MQVNNNE")
        (field (name "DB_APPROVED_BY") "VSN")
      )
      (libsource (lib "Database_Libs1") (part "C"))
    )
    (comp (ref "C999")
      (value "22uF")
      (footprint "SMD_0805_CAPC2012X145N")
      (fields
        (field (name "DB_PART_NUMBER") "CAP000043686")
        (field (name "DB_VALUE") "22uF")
        (field (name "DB_TOLERANCE") "20%")
        (field (name "DB_VOLTAGE") "6.3V")
        (field (name "DB_MANUFACTURER_PART") "KEMET    C0805C226M9PAC")
        (field (name "DB_APPROVED_BY") "ISHIDDEN=T")
      )
      (libsource (lib "Database_Libs1") (part "C"))
    )
    (comp (ref "C1000")
      (value "22uF")
      (footprint "SMD_0805_CAPC2012X145N")
      (fields
        (field (name "DB_PART_NUMBER") "CAP000043686")
        (field (name "DB_VALUE") "22uF")
        (field (name "DB_TOLERANCE") "20%")
        (field (name "DB_VOLTAGE") "6.3V")
        (field (name "DB_MANUFACTURER_PART") "KEMET    C0805C226M9PAC")
        (field (name "DB_APPROVED_BY") "ISHIDDEN=T")
      )
      (libsource (lib "Database_Libs1") (part "C"))
    )
    (comp (ref "C1001")
      (value "220uF")
      (footprint "SMD_1210_CAPC3225X279N")
      (fields
        (field (name "DB_PART_NUMBER") "CAP000047355")
        (field (name "DB_VALUE") "220uF")
        (field (name "DB_TOLERANCE") "20%")
        (field (name "DB_VOLTAGE") "6.3V")
        (field (name "DB_MANUFACTURER_PART") "SAMSUNG    CL32A227MQVNNNE")
        (field (name "DB_APPROVED_BY") "VSN")
      )
      (libsource (lib "Database_Libs1") (part "C"))
    )
    (comp (ref "C1002")
      (value "22uF")
      (footprint "SMD_0805_CAPC2012X145N")
      (fields
        (field (name "DB_PART_NUMBER") "CAP000043686")
        (field (name "DB_VALUE") "22uF")
        (field (name "DB_TOLERANCE") "20%")
        (field (name "DB_VOLTAGE") "6.3V")
        (field (name "DB_MANUFACTURER_PART") "KEMET    C0805C226M9PAC")
        (field (name "DB_APPROVED_BY") "ISHIDDEN=T")
      )
      (libsource (lib "Database_Libs1") (part "C"))
    )
    (comp (ref "C1003")
      (value "22uF")
      (footprint "SMD_0805_CAPC2012X145N")
      (fields
        (field (name "DB_PART_NUMBER") "CAP000043686")
        (field (name "DB_VALUE") "22uF")
        (field (name "DB_TOLERANCE") "20%")
        (field (name "DB_VOLTAGE") "6.3V")
        (field (name "DB_MANUFACTURER_PART") "KEMET    C0805C226M9PAC")
        (field (name "DB_APPROVED_BY") "ISHIDDEN=T")
      )
      (libsource (lib "Database_Libs1") (part "C"))
    )
    (comp (ref "C1004")
      (value "220uF")
      (footprint "SMD_1210_CAPC3225X279N")
      (fields
        (field (name "DB_PART_NUMBER") "CAP000047355")
        (field (name "DB_VALUE") "220uF")
        (field (name "DB_TOLERANCE") "20%")
        (field (name "DB_VOLTAGE") "6.3V")
        (field (name "DB_MANUFACTURER_PART") "SAMSUNG    CL32A227MQVNNNE")
        (field (name "DB_APPROVED_BY") "VSN")
      )
      (libsource (lib "Database_Libs1") (part "C"))
    )
    (comp (ref "C1005")
      (value "22uF")
      (footprint "SMD_0805_CAPC2012X145N")
      (fields
        (field (name "DB_PART_NUMBER") "CAP000043686")
        (field (name "DB_VALUE") "22uF")
        (field (name "DB_TOLERANCE") "20%")
        (field (name "DB_VOLTAGE") "6.3V")
        (field (name "DB_MANUFACTURER_PART") "KEMET    C0805C226M9PAC")
        (field (name "DB_APPROVED_BY") "ISHIDDEN=T")
      )
      (libsource (lib "Database_Libs1") (part "C"))
    )
    (comp (ref "C1006")
      (value "22uF")
      (footprint "SMD_0805_CAPC2012X145N")
      (fields
        (field (name "DB_PART_NUMBER") "CAP000043686")
        (field (name "DB_VALUE") "22uF")
        (field (name "DB_TOLERANCE") "20%")
        (field (name "DB_VOLTAGE") "6.3V")
        (field (name "DB_MANUFACTURER_PART") "KEMET    C0805C226M9PAC")
        (field (name "DB_APPROVED_BY") "ISHIDDEN=T")
      )
      (libsource (lib "Database_Libs1") (part "C"))
    )
    (comp (ref "C1007")
      (value "220uF")
      (footprint "SMD_1210_CAPC3225X279N")
      (fields
        (field (name "DB_PART_NUMBER") "CAP000047355")
        (field (name "DB_VALUE") "220uF")
        (field (name "DB_TOLERANCE") "20%")
        (field (name "DB_VOLTAGE") "6.3V")
        (field (name "DB_MANUFACTURER_PART") "SAMSUNG    CL32A227MQVNNNE")
        (field (name "DB_APPROVED_BY") "VSN")
      )
      (libsource (lib "Database_Libs1") (part "C"))
    )
    (comp (ref "C1008")
      (value "22uF")
      (footprint "SMD_0805_CAPC2012X145N")
      (fields
        (field (name "DB_PART_NUMBER") "CAP000043686")
        (field (name "DB_VALUE") "22uF")
        (field (name "DB_TOLERANCE") "20%")
        (field (name "DB_VOLTAGE") "6.3V")
        (field (name "DB_MANUFACTURER_PART") "KEMET    C0805C226M9PAC")
        (field (name "DB_APPROVED_BY") "ISHIDDEN=T")
      )
      (libsource (lib "Database_Libs1") (part "C"))
    )
    (comp (ref "C1009")
      (value "22uF")
      (footprint "SMD_0805_CAPC2012X145N")
      (fields
        (field (name "DB_PART_NUMBER") "CAP000043686")
        (field (name "DB_VALUE") "22uF")
        (field (name "DB_TOLERANCE") "20%")
        (field (name "DB_VOLTAGE") "6.3V")
        (field (name "DB_MANUFACTURER_PART") "KEMET    C0805C226M9PAC")
        (field (name "DB_APPROVED_BY") "ISHIDDEN=T")
      )
      (libsource (lib "Database_Libs1") (part "C"))
    )
    (comp (ref "C1010")
      (value "220uF")
      (footprint "SMD_1210_CAPC3225X279N")
      (fields
        (field (name "DB_PART_NUMBER") "CAP000047355")
        (field (name "DB_VALUE") "220uF")
        (field (name "DB_TOLERANCE") "20%")
        (field (name "DB_VOLTAGE") "6.3V")
        (field (name "DB_MANUFACTURER_PART") "SAMSUNG    CL32A227MQVNNNE")
        (field (name "DB_APPROVED_BY") "VSN")
      )
      (libsource (lib "Database_Libs1") (part "C"))
    )
    (comp (ref "C1011")
      (value "22uF")
      (footprint "SMD_0805_CAPC2012X145N")
      (fields
        (field (name "DB_PART_NUMBER") "CAP000043686")
        (field (name "DB_VALUE") "22uF")
        (field (name "DB_TOLERANCE") "20%")
        (field (name "DB_VOLTAGE") "6.3V")
        (field (name "DB_MANUFACTURER_PART") "KEMET    C0805C226M9PAC")
        (field (name "DB_APPROVED_BY") "ISHIDDEN=T")
      )
      (libsource (lib "Database_Libs1") (part "C"))
    )
    (comp (ref "C1012")
      (value "22uF")
      (footprint "SMD_0805_CAPC2012X145N")
      (fields
        (field (name "DB_PART_NUMBER") "CAP000043686")
        (field (name "DB_VALUE") "22uF")
        (field (name "DB_TOLERANCE") "20%")
        (field (name "DB_VOLTAGE") "6.3V")
        (field (name "DB_MANUFACTURER_PART") "KEMET    C0805C226M9PAC")
        (field (name "DB_APPROVED_BY") "ISHIDDEN=T")
      )
      (libsource (lib "Database_Libs1") (part "C"))
    )
    (comp (ref "C1013")
      (value "220uF")
      (footprint "SMD_1210_CAPC3225X279N")
      (fields
        (field (name "DB_PART_NUMBER") "CAP000047355")
        (field (name "DB_VALUE") "220uF")
        (field (name "DB_TOLERANCE") "20%")
        (field (name "DB_VOLTAGE") "6.3V")
        (field (name "DB_MANUFACTURER_PART") "SAMSUNG    CL32A227MQVNNNE")
        (field (name "DB_APPROVED_BY") "VSN")
      )
      (libsource (lib "Database_Libs1") (part "C"))
    )
    (comp (ref "C1014")
      (value "22uF")
      (footprint "SMD_0805_CAPC2012X145N")
      (fields
        (field (name "DB_PART_NUMBER") "CAP000043686")
        (field (name "DB_VALUE") "22uF")
        (field (name "DB_TOLERANCE") "20%")
        (field (name "DB_VOLTAGE") "6.3V")
        (field (name "DB_MANUFACTURER_PART") "KEMET    C0805C226M9PAC")
        (field (name "DB_APPROVED_BY") "ISHIDDEN=T")
      )
      (libsource (lib "Database_Libs1") (part "C"))
    )
    (comp (ref "C1015")
      (value "22uF")
      (footprint "SMD_0805_CAPC2012X145N")
      (fields
        (field (name "DB_PART_NUMBER") "CAP000043686")
        (field (name "DB_VALUE") "22uF")
        (field (name "DB_TOLERANCE") "20%")
        (field (name "DB_VOLTAGE") "6.3V")
        (field (name "DB_MANUFACTURER_PART") "KEMET    C0805C226M9PAC")
        (field (name "DB_APPROVED_BY") "ISHIDDEN=T")
      )
      (libsource (lib "Database_Libs1") (part "C"))
    )
    (comp (ref "C1016")
      (value "220uF")
      (footprint "SMD_1210_CAPC3225X279N")
      (fields
        (field (name "DB_PART_NUMBER") "CAP000047355")
        (field (name "DB_VALUE") "220uF")
        (field (name "DB_TOLERANCE") "20%")
        (field (name "DB_VOLTAGE") "6.3V")
        (field (name "DB_MANUFACTURER_PART") "SAMSUNG    CL32A227MQVNNNE")
        (field (name "DB_APPROVED_BY") "VSN")
      )
      (libsource (lib "Database_Libs1") (part "C"))
    )
    (comp (ref "C1017")
      (value "22uF")
      (footprint "SMD_0805_CAPC2012X145N")
      (fields
        (field (name "DB_PART_NUMBER") "CAP000043686")
        (field (name "DB_VALUE") "22uF")
        (field (name "DB_TOLERANCE") "20%")
        (field (name "DB_VOLTAGE") "6.3V")
        (field (name "DB_MANUFACTURER_PART") "KEMET    C0805C226M9PAC")
        (field (name "DB_APPROVED_BY") "ISHIDDEN=T")
      )
      (libsource (lib "Database_Libs1") (part "C"))
    )
    (comp (ref "C1018")
      (value "22uF")
      (footprint "SMD_0805_CAPC2012X145N")
      (fields
        (field (name "DB_PART_NUMBER") "CAP000043686")
        (field (name "DB_VALUE") "22uF")
        (field (name "DB_TOLERANCE") "20%")
        (field (name "DB_VOLTAGE") "6.3V")
        (field (name "DB_MANUFACTURER_PART") "KEMET    C0805C226M9PAC")
        (field (name "DB_APPROVED_BY") "ISHIDDEN=T")
      )
      (libsource (lib "Database_Libs1") (part "C"))
    )
    (comp (ref "C1019")
      (value "220uF")
      (footprint "SMD_1210_CAPC3225X279N")
      (fields
        (field (name "DB_PART_NUMBER") "CAP000047355")
        (field (name "DB_VALUE") "220uF")
        (field (name "DB_TOLERANCE") "20%")
        (field (name "DB_VOLTAGE") "6.3V")
        (field (name "DB_MANUFACTURER_PART") "SAMSUNG    CL32A227MQVNNNE")
        (field (name "DB_APPROVED_BY") "VSN")
      )
      (libsource (lib "Database_Libs1") (part "C"))
    )
    (comp (ref "C1020")
      (value "22uF")
      (footprint "SMD_0805_CAPC2012X145N")
      (fields
        (field (name "DB_PART_NUMBER") "CAP000043686")
        (field (name "DB_VALUE") "22uF")
        (field (name "DB_TOLERANCE") "20%")
        (field (name "DB_VOLTAGE") "6.3V")
        (field (name "DB_MANUFACTURER_PART") "KEMET    C0805C226M9PAC")
        (field (name "DB_APPROVED_BY") "ISHIDDEN=T")
      )
      (libsource (lib "Database_Libs1") (part "C"))
    )
    (comp (ref "C1021")
      (value "22uF")
      (footprint "SMD_0805_CAPC2012X145N")
      (fields
        (field (name "DB_PART_NUMBER") "CAP000043686")
        (field (name "DB_VALUE") "22uF")
        (field (name "DB_TOLERANCE") "20%")
        (field (name "DB_VOLTAGE") "6.3V")
        (field (name "DB_MANUFACTURER_PART") "KEMET    C0805C226M9PAC")
        (field (name "DB_APPROVED_BY") "ISHIDDEN=T")
      )
      (libsource (lib "Database_Libs1") (part "C"))
    )
    (comp (ref "C1022")
      (value "220uF")
      (footprint "SMD_1210_CAPC3225X279N")
      (fields
        (field (name "DB_PART_NUMBER") "CAP000047355")
        (field (name "DB_VALUE") "220uF")
        (field (name "DB_TOLERANCE") "20%")
        (field (name "DB_VOLTAGE") "6.3V")
        (field (name "DB_MANUFACTURER_PART") "SAMSUNG    CL32A227MQVNNNE")
        (field (name "DB_APPROVED_BY") "VSN")
      )
      (libsource (lib "Database_Libs1") (part "C"))
    )
    (comp (ref "C1023")
      (value "22uF")
      (footprint "SMD_0805_CAPC2012X145N")
      (fields
        (field (name "DB_PART_NUMBER") "CAP000043686")
        (field (name "DB_VALUE") "22uF")
        (field (name "DB_TOLERANCE") "20%")
        (field (name "DB_VOLTAGE") "6.3V")
        (field (name "DB_MANUFACTURER_PART") "KEMET    C0805C226M9PAC")
        (field (name "DB_APPROVED_BY") "ISHIDDEN=T")
      )
      (libsource (lib "Database_Libs1") (part "C"))
    )
    (comp (ref "C1024")
      (value "22uF")
      (footprint "SMD_0805_CAPC2012X145N")
      (fields
        (field (name "DB_PART_NUMBER") "CAP000043686")
        (field (name "DB_VALUE") "22uF")
        (field (name "DB_TOLERANCE") "20%")
        (field (name "DB_VOLTAGE") "6.3V")
        (field (name "DB_MANUFACTURER_PART") "KEMET    C0805C226M9PAC")
        (field (name "DB_APPROVED_BY") "ISHIDDEN=T")
      )
      (libsource (lib "Database_Libs1") (part "C"))
    )
    (comp (ref "C1025")
      (value "220uF")
      (footprint "SMD_1210_CAPC3225X279N")
      (fields
        (field (name "DB_PART_NUMBER") "CAP000047355")
        (field (name "DB_VALUE") "220uF")
        (field (name "DB_TOLERANCE") "20%")
        (field (name "DB_VOLTAGE") "6.3V")
        (field (name "DB_MANUFACTURER_PART") "SAMSUNG    CL32A227MQVNNNE")
        (field (name "DB_APPROVED_BY") "VSN")
      )
      (libsource (lib "Database_Libs1") (part "C"))
    )
    (comp (ref "C1026")
      (value "22uF")
      (footprint "SMD_0805_CAPC2012X145N")
      (fields
        (field (name "DB_PART_NUMBER") "CAP000043686")
        (field (name "DB_VALUE") "22uF")
        (field (name "DB_TOLERANCE") "20%")
        (field (name "DB_VOLTAGE") "6.3V")
        (field (name "DB_MANUFACTURER_PART") "KEMET    C0805C226M9PAC")
        (field (name "DB_APPROVED_BY") "ISHIDDEN=T")
      )
      (libsource (lib "Database_Libs1") (part "C"))
    )
    (comp (ref "C1027")
      (value "22uF")
      (footprint "SMD_0805_CAPC2012X145N")
      (fields
        (field (name "DB_PART_NUMBER") "CAP000043686")
        (field (name "DB_VALUE") "22uF")
        (field (name "DB_TOLERANCE") "20%")
        (field (name "DB_VOLTAGE") "6.3V")
        (field (name "DB_MANUFACTURER_PART") "KEMET    C0805C226M9PAC")
        (field (name "DB_APPROVED_BY") "ISHIDDEN=T")
      )
      (libsource (lib "Database_Libs1") (part "C"))
    )
    (comp (ref "C1028")
      (value "220uF")
      (footprint "SMD_1210_CAPC3225X279N")
      (fields
        (field (name "DB_PART_NUMBER") "CAP000047355")
        (field (name "DB_VALUE") "220uF")
        (field (name "DB_TOLERANCE") "20%")
        (field (name "DB_VOLTAGE") "6.3V")
        (field (name "DB_MANUFACTURER_PART") "SAMSUNG    CL32A227MQVNNNE")
        (field (name "DB_APPROVED_BY") "VSN")
      )
      (libsource (lib "Database_Libs1") (part "C"))
    )
    (comp (ref "C1029")
      (value "22uF")
      (footprint "SMD_0805_CAPC2012X145N")
      (fields
        (field (name "DB_PART_NUMBER") "CAP000043686")
        (field (name "DB_VALUE") "22uF")
        (field (name "DB_TOLERANCE") "20%")
        (field (name "DB_VOLTAGE") "6.3V")
        (field (name "DB_MANUFACTURER_PART") "KEMET    C0805C226M9PAC")
        (field (name "DB_APPROVED_BY") "ISHIDDEN=T")
      )
      (libsource (lib "Database_Libs1") (part "C"))
    )
    (comp (ref "C1030")
      (value "22uF")
      (footprint "SMD_0805_CAPC2012X145N")
      (fields
        (field (name "DB_PART_NUMBER") "CAP000043686")
        (field (name "DB_VALUE") "22uF")
        (field (name "DB_TOLERANCE") "20%")
        (field (name "DB_VOLTAGE") "6.3V")
        (field (name "DB_MANUFACTURER_PART") "KEMET    C0805C226M9PAC")
        (field (name "DB_APPROVED_BY") "ISHIDDEN=T")
      )
      (libsource (lib "Database_Libs1") (part "C"))
    )
    (comp (ref "C1031")
      (value "220uF")
      (footprint "SMD_1210_CAPC3225X279N")
      (fields
        (field (name "DB_PART_NUMBER") "CAP000047355")
        (field (name "DB_VALUE") "220uF")
        (field (name "DB_TOLERANCE") "20%")
        (field (name "DB_VOLTAGE") "6.3V")
        (field (name "DB_MANUFACTURER_PART") "SAMSUNG    CL32A227MQVNNNE")
        (field (name "DB_APPROVED_BY") "VSN")
      )
      (libsource (lib "Database_Libs1") (part "C"))
    )
    (comp (ref "C1032")
      (value "22uF")
      (footprint "SMD_0805_CAPC2012X145N")
      (fields
        (field (name "DB_PART_NUMBER") "CAP000043686")
        (field (name "DB_VALUE") "22uF")
        (field (name "DB_TOLERANCE") "20%")
        (field (name "DB_VOLTAGE") "6.3V")
        (field (name "DB_MANUFACTURER_PART") "KEMET    C0805C226M9PAC")
        (field (name "DB_APPROVED_BY") "ISHIDDEN=T")
      )
      (libsource (lib "Database_Libs1") (part "C"))
    )
    (comp (ref "C1033")
      (value "22uF")
      (footprint "SMD_0805_CAPC2012X145N")
      (fields
        (field (name "DB_PART_NUMBER") "CAP000043686")
        (field (name "DB_VALUE") "22uF")
        (field (name "DB_TOLERANCE") "20%")
        (field (name "DB_VOLTAGE") "6.3V")
        (field (name "DB_MANUFACTURER_PART") "KEMET    C0805C226M9PAC")
        (field (name "DB_APPROVED_BY") "ISHIDDEN=T")
      )
      (libsource (lib "Database_Libs1") (part "C"))
    )
    (comp (ref "C1034")
      (value "220uF")
      (footprint "SMD_1210_CAPC3225X279N")
      (fields
        (field (name "DB_PART_NUMBER") "CAP000047355")
        (field (name "DB_VALUE") "220uF")
        (field (name "DB_TOLERANCE") "20%")
        (field (name "DB_VOLTAGE") "6.3V")
        (field (name "DB_MANUFACTURER_PART") "SAMSUNG    CL32A227MQVNNNE")
        (field (name "DB_APPROVED_BY") "VSN")
      )
      (libsource (lib "Database_Libs1") (part "C"))
    )
    (comp (ref "C1035")
      (value "22uF")
      (footprint "SMD_0805_CAPC2012X145N")
      (fields
        (field (name "DB_PART_NUMBER") "CAP000043686")
        (field (name "DB_VALUE") "22uF")
        (field (name "DB_TOLERANCE") "20%")
        (field (name "DB_VOLTAGE") "6.3V")
        (field (name "DB_MANUFACTURER_PART") "KEMET    C0805C226M9PAC")
        (field (name "DB_APPROVED_BY") "ISHIDDEN=T")
      )
      (libsource (lib "Database_Libs1") (part "C"))
    )
    (comp (ref "C1036")
      (value "22uF")
      (footprint "SMD_0805_CAPC2012X145N")
      (fields
        (field (name "DB_PART_NUMBER") "CAP000043686")
        (field (name "DB_VALUE") "22uF")
        (field (name "DB_TOLERANCE") "20%")
        (field (name "DB_VOLTAGE") "6.3V")
        (field (name "DB_MANUFACTURER_PART") "KEMET    C0805C226M9PAC")
        (field (name "DB_APPROVED_BY") "ISHIDDEN=T")
      )
      (libsource (lib "Database_Libs1") (part "C"))
    )
    (comp (ref "C1037")
      (value "220uF")
      (footprint "SMD_1210_CAPC3225X279N")
      (fields
        (field (name "DB_PART_NUMBER") "CAP000047355")
        (field (name "DB_VALUE") "220uF")
        (field (name "DB_TOLERANCE") "20%")
        (field (name "DB_VOLTAGE") "6.3V")
        (field (name "DB_MANUFACTURER_PART") "SAMSUNG    CL32A227MQVNNNE")
        (field (name "DB_APPROVED_BY") "VSN")
      )
      (libsource (lib "Database_Libs1") (part "C"))
    )
    (comp (ref "C1038")
      (value "22uF")
      (footprint "SMD_0805_CAPC2012X145N")
      (fields
        (field (name "DB_PART_NUMBER") "CAP000043686")
        (field (name "DB_VALUE") "22uF")
        (field (name "DB_TOLERANCE") "20%")
        (field (name "DB_VOLTAGE") "6.3V")
        (field (name "DB_MANUFACTURER_PART") "KEMET    C0805C226M9PAC")
        (field (name "DB_APPROVED_BY") "ISHIDDEN=T")
      )
      (libsource (lib "Database_Libs1") (part "C"))
    )
    (comp (ref "C1039")
      (value "22uF")
      (footprint "SMD_0805_CAPC2012X145N")
      (fields
        (field (name "DB_PART_NUMBER") "CAP000043686")
        (field (name "DB_VALUE") "22uF")
        (field (name "DB_TOLERANCE") "20%")
        (field (name "DB_VOLTAGE") "6.3V")
        (field (name "DB_MANUFACTURER_PART") "KEMET    C0805C226M9PAC")
        (field (name "DB_APPROVED_BY") "ISHIDDEN=T")
      )
      (libsource (lib "Database_Libs1") (part "C"))
    )
    (comp (ref "C1040")
      (value "220uF")
      (footprint "SMD_1210_CAPC3225X279N")
      (fields
        (field (name "DB_PART_NUMBER") "CAP000047355")
        (field (name "DB_VALUE") "220uF")
        (field (name "DB_TOLERANCE") "20%")
        (field (name "DB_VOLTAGE") "6.3V")
        (field (name "DB_MANUFACTURER_PART") "SAMSUNG    CL32A227MQVNNNE")
        (field (name "DB_APPROVED_BY") "VSN")
      )
      (libsource (lib "Database_Libs1") (part "C"))
    )
    (comp (ref "C1041")
      (value "22uF")
      (footprint "SMD_0805_CAPC2012X145N")
      (fields
        (field (name "DB_PART_NUMBER") "CAP000043686")
        (field (name "DB_VALUE") "22uF")
        (field (name "DB_TOLERANCE") "20%")
        (field (name "DB_VOLTAGE") "6.3V")
        (field (name "DB_MANUFACTURER_PART") "KEMET    C0805C226M9PAC")
        (field (name "DB_APPROVED_BY") "ISHIDDEN=T")
      )
      (libsource (lib "Database_Libs1") (part "C"))
    )
    (comp (ref "C1042")
      (value "22uF")
      (footprint "SMD_0805_CAPC2012X145N")
      (fields
        (field (name "DB_PART_NUMBER") "CAP000043686")
        (field (name "DB_VALUE") "22uF")
        (field (name "DB_TOLERANCE") "20%")
        (field (name "DB_VOLTAGE") "6.3V")
        (field (name "DB_MANUFACTURER_PART") "KEMET    C0805C226M9PAC")
        (field (name "DB_APPROVED_BY") "ISHIDDEN=T")
      )
      (libsource (lib "Database_Libs1") (part "C"))
    )
    (comp (ref "C1043")
      (value "220uF")
      (footprint "SMD_1210_CAPC3225X279N")
      (fields
        (field (name "DB_PART_NUMBER") "CAP000047355")
        (field (name "DB_VALUE") "220uF")
        (field (name "DB_TOLERANCE") "20%")
        (field (name "DB_VOLTAGE") "6.3V")
        (field (name "DB_MANUFACTURER_PART") "SAMSUNG    CL32A227MQVNNNE")
        (field (name "DB_APPROVED_BY") "VSN")
      )
      (libsource (lib "Database_Libs1") (part "C"))
    )
    (comp (ref "C1044")
      (value "22uF")
      (footprint "SMD_0805_CAPC2012X145N")
      (fields
        (field (name "DB_PART_NUMBER") "CAP000043686")
        (field (name "DB_VALUE") "22uF")
        (field (name "DB_TOLERANCE") "20%")
        (field (name "DB_VOLTAGE") "6.3V")
        (field (name "DB_MANUFACTURER_PART") "KEMET    C0805C226M9PAC")
        (field (name "DB_APPROVED_BY") "ISHIDDEN=T")
      )
      (libsource (lib "Database_Libs1") (part "C"))
    )
    (comp (ref "C1045")
      (value "22uF")
      (footprint "SMD_0805_CAPC2012X145N")
      (fields
        (field (name "DB_PART_NUMBER") "CAP000043686")
        (field (name "DB_VALUE") "22uF")
        (field (name "DB_TOLERANCE") "20%")
        (field (name "DB_VOLTAGE") "6.3V")
        (field (name "DB_MANUFACTURER_PART") "KEMET    C0805C226M9PAC")
        (field (name "DB_APPROVED_BY") "ISHIDDEN=T")
      )
      (libsource (lib "Database_Libs1") (part "C"))
    )
    (comp (ref "C1046")
      (value "220uF")
      (footprint "SMD_1210_CAPC3225X279N")
      (fields
        (field (name "DB_PART_NUMBER") "CAP000047355")
        (field (name "DB_VALUE") "220uF")
        (field (name "DB_TOLERANCE") "20%")
        (field (name "DB_VOLTAGE") "6.3V")
        (field (name "DB_MANUFACTURER_PART") "SAMSUNG    CL32A227MQVNNNE")
        (field (name "DB_APPROVED_BY") "VSN")
      )
      (libsource (lib "Database_Libs1") (part "C"))
    )
    (comp (ref "C1047")
      (value "22uF")
      (footprint "SMD_0805_CAPC2012X145N")
      (fields
        (field (name "DB_PART_NUMBER") "CAP000043686")
        (field (name "DB_VALUE") "22uF")
        (field (name "DB_TOLERANCE") "20%")
        (field (name "DB_VOLTAGE") "6.3V")
        (field (name "DB_MANUFACTURER_PART") "KEMET    C0805C226M9PAC")
        (field (name "DB_APPROVED_BY") "ISHIDDEN=T")
      )
      (libsource (lib "Database_Libs1") (part "C"))
    )
    (comp (ref "C1048")
      (value "22uF")
      (footprint "SMD_0805_CAPC2012X145N")
      (fields
        (field (name "DB_PART_NUMBER") "CAP000043686")
        (field (name "DB_VALUE") "22uF")
        (field (name "DB_TOLERANCE") "20%")
        (field (name "DB_VOLTAGE") "6.3V")
        (field (name "DB_MANUFACTURER_PART") "KEMET    C0805C226M9PAC")
        (field (name "DB_APPROVED_BY") "ISHIDDEN=T")
      )
      (libsource (lib "Database_Libs1") (part "C"))
    )
    (comp (ref "C1049")
      (value "220uF")
      (footprint "SMD_1210_CAPC3225X279N")
      (fields
        (field (name "DB_PART_NUMBER") "CAP000047355")
        (field (name "DB_VALUE") "220uF")
        (field (name "DB_TOLERANCE") "20%")
        (field (name "DB_VOLTAGE") "6.3V")
        (field (name "DB_MANUFACTURER_PART") "SAMSUNG    CL32A227MQVNNNE")
        (field (name "DB_APPROVED_BY") "VSN")
      )
      (libsource (lib "Database_Libs1") (part "C"))
    )
    (comp (ref "C1050")
      (value "22uF")
      (footprint "SMD_0805_CAPC2012X145N")
      (fields
        (field (name "DB_PART_NUMBER") "CAP000043686")
        (field (name "DB_VALUE") "22uF")
        (field (name "DB_TOLERANCE") "20%")
        (field (name "DB_VOLTAGE") "6.3V")
        (field (name "DB_MANUFACTURER_PART") "KEMET    C0805C226M9PAC")
        (field (name "DB_APPROVED_BY") "ISHIDDEN=T")
      )
      (libsource (lib "Database_Libs1") (part "C"))
    )
    (comp (ref "C1051")
      (value "22uF")
      (footprint "SMD_0805_CAPC2012X145N")
      (fields
        (field (name "DB_PART_NUMBER") "CAP000043686")
        (field (name "DB_VALUE") "22uF")
        (field (name "DB_TOLERANCE") "20%")
        (field (name "DB_VOLTAGE") "6.3V")
        (field (name "DB_MANUFACTURER_PART") "KEMET    C0805C226M9PAC")
        (field (name "DB_APPROVED_BY") "ISHIDDEN=T")
      )
      (libsource (lib "Database_Libs1") (part "C"))
    )
    (comp (ref "C1052")
      (value "220uF")
      (footprint "SMD_1210_CAPC3225X279N")
      (fields
        (field (name "DB_PART_NUMBER") "CAP000047355")
        (field (name "DB_VALUE") "220uF")
        (field (name "DB_TOLERANCE") "20%")
        (field (name "DB_VOLTAGE") "6.3V")
        (field (name "DB_MANUFACTURER_PART") "SAMSUNG    CL32A227MQVNNNE")
        (field (name "DB_APPROVED_BY") "VSN")
      )
      (libsource (lib "Database_Libs1") (part "C"))
    )
    (comp (ref "C1053")
      (value "22uF")
      (footprint "SMD_0805_CAPC2012X145N")
      (fields
        (field (name "DB_PART_NUMBER") "CAP000043686")
        (field (name "DB_VALUE") "22uF")
        (field (name "DB_TOLERANCE") "20%")
        (field (name "DB_VOLTAGE") "6.3V")
        (field (name "DB_MANUFACTURER_PART") "KEMET    C0805C226M9PAC")
        (field (name "DB_APPROVED_BY") "ISHIDDEN=T")
      )
      (libsource (lib "Database_Libs1") (part "C"))
    )
    (comp (ref "C1054")
      (value "22uF")
      (footprint "SMD_0805_CAPC2012X145N")
      (fields
        (field (name "DB_PART_NUMBER") "CAP000043686")
        (field (name "DB_VALUE") "22uF")
        (field (name "DB_TOLERANCE") "20%")
        (field (name "DB_VOLTAGE") "6.3V")
        (field (name "DB_MANUFACTURER_PART") "KEMET    C0805C226M9PAC")
        (field (name "DB_APPROVED_BY") "ISHIDDEN=T")
      )
      (libsource (lib "Database_Libs1") (part "C"))
    )
    (comp (ref "C1055")
      (value "220uF")
      (footprint "SMD_1210_CAPC3225X279N")
      (fields
        (field (name "DB_PART_NUMBER") "CAP000047355")
        (field (name "DB_VALUE") "220uF")
        (field (name "DB_TOLERANCE") "20%")
        (field (name "DB_VOLTAGE") "6.3V")
        (field (name "DB_MANUFACTURER_PART") "SAMSUNG    CL32A227MQVNNNE")
        (field (name "DB_APPROVED_BY") "VSN")
      )
      (libsource (lib "Database_Libs1") (part "C"))
    )
    (comp (ref "C1056")
      (value "22uF")
      (footprint "SMD_0805_CAPC2012X145N")
      (fields
        (field (name "DB_PART_NUMBER") "CAP000043686")
        (field (name "DB_VALUE") "22uF")
        (field (name "DB_TOLERANCE") "20%")
        (field (name "DB_VOLTAGE") "6.3V")
        (field (name "DB_MANUFACTURER_PART") "KEMET    C0805C226M9PAC")
        (field (name "DB_APPROVED_BY") "ISHIDDEN=T")
      )
      (libsource (lib "Database_Libs1") (part "C"))
    )
    (comp (ref "C1057")
      (value "22uF")
      (footprint "SMD_0805_CAPC2012X145N")
      (fields
        (field (name "DB_PART_NUMBER") "CAP000043686")
        (field (name "DB_VALUE") "22uF")
        (field (name "DB_TOLERANCE") "20%")
        (field (name "DB_VOLTAGE") "6.3V")
        (field (name "DB_MANUFACTURER_PART") "KEMET    C0805C226M9PAC")
        (field (name "DB_APPROVED_BY") "ISHIDDEN=T")
      )
      (libsource (lib "Database_Libs1") (part "C"))
    )
    (comp (ref "C1058")
      (value "220uF")
      (footprint "SMD_1210_CAPC3225X279N")
      (fields
        (field (name "DB_PART_NUMBER") "CAP000047355")
        (field (name "DB_VALUE") "220uF")
        (field (name "DB_TOLERANCE") "20%")
        (field (name "DB_VOLTAGE") "6.3V")
        (field (name "DB_MANUFACTURER_PART") "SAMSUNG    CL32A227MQVNNNE")
        (field (name "DB_APPROVED_BY") "VSN")
      )
      (libsource (lib "Database_Libs1") (part "C"))
    )
    (comp (ref "C1059")
      (value "22uF")
      (footprint "SMD_0805_CAPC2012X145N")
      (fields
        (field (name "DB_PART_NUMBER") "CAP000043686")
        (field (name "DB_VALUE") "22uF")
        (field (name "DB_TOLERANCE") "20%")
        (field (name "DB_VOLTAGE") "6.3V")
        (field (name "DB_MANUFACTURER_PART") "KEMET    C0805C226M9PAC")
        (field (name "DB_APPROVED_BY") "ISHIDDEN=T")
      )
      (libsource (lib "Database_Libs1") (part "C"))
    )
    (comp (ref "C1060")
      (value "22uF")
      (footprint "SMD_0805_CAPC2012X145N")
      (fields
        (field (name "DB_PART_NUMBER") "CAP000043686")
        (field (name "DB_VALUE") "22uF")
        (field (name "DB_TOLERANCE") "20%")
        (field (name "DB_VOLTAGE") "6.3V")
        (field (name "DB_MANUFACTURER_PART") "KEMET    C0805C226M9PAC")
        (field (name "DB_APPROVED_BY") "ISHIDDEN=T")
      )
      (libsource (lib "Database_Libs1") (part "C"))
    )
    (comp (ref "C1061")
      (value "220uF")
      (footprint "SMD_1210_CAPC3225X279N")
      (fields
        (field (name "DB_PART_NUMBER") "CAP000047355")
        (field (name "DB_VALUE") "220uF")
        (field (name "DB_TOLERANCE") "20%")
        (field (name "DB_VOLTAGE") "6.3V")
        (field (name "DB_MANUFACTURER_PART") "SAMSUNG    CL32A227MQVNNNE")
        (field (name "DB_APPROVED_BY") "VSN")
      )
      (libsource (lib "Database_Libs1") (part "C"))
    )
    (comp (ref "C1062")
      (value "22uF")
      (footprint "SMD_0805_CAPC2012X145N")
      (fields
        (field (name "DB_PART_NUMBER") "CAP000043686")
        (field (name "DB_VALUE") "22uF")
        (field (name "DB_TOLERANCE") "20%")
        (field (name "DB_VOLTAGE") "6.3V")
        (field (name "DB_MANUFACTURER_PART") "KEMET    C0805C226M9PAC")
        (field (name "DB_APPROVED_BY") "ISHIDDEN=T")
      )
      (libsource (lib "Database_Libs1") (part "C"))
    )
    (comp (ref "C1063")
      (value "22uF")
      (footprint "SMD_0805_CAPC2012X145N")
      (fields
        (field (name "DB_PART_NUMBER") "CAP000043686")
        (field (name "DB_VALUE") "22uF")
        (field (name "DB_TOLERANCE") "20%")
        (field (name "DB_VOLTAGE") "6.3V")
        (field (name "DB_MANUFACTURER_PART") "KEMET    C0805C226M9PAC")
        (field (name "DB_APPROVED_BY") "ISHIDDEN=T")
      )
      (libsource (lib "Database_Libs1") (part "C"))
    )
    (comp (ref "C1064")
      (value "220uF")
      (footprint "SMD_1210_CAPC3225X279N")
      (fields
        (field (name "DB_PART_NUMBER") "CAP000047355")
        (field (name "DB_VALUE") "220uF")
        (field (name "DB_TOLERANCE") "20%")
        (field (name "DB_VOLTAGE") "6.3V")
        (field (name "DB_MANUFACTURER_PART") "SAMSUNG    CL32A227MQVNNNE")
        (field (name "DB_APPROVED_BY") "VSN")
      )
      (libsource (lib "Database_Libs1") (part "C"))
    )
    (comp (ref "C1065")
      (value "22uF")
      (footprint "SMD_0805_CAPC2012X145N")
      (fields
        (field (name "DB_PART_NUMBER") "CAP000043686")
        (field (name "DB_VALUE") "22uF")
        (field (name "DB_TOLERANCE") "20%")
        (field (name "DB_VOLTAGE") "6.3V")
        (field (name "DB_MANUFACTURER_PART") "KEMET    C0805C226M9PAC")
        (field (name "DB_APPROVED_BY") "ISHIDDEN=T")
      )
      (libsource (lib "Database_Libs1") (part "C"))
    )
    (comp (ref "C1066")
      (value "22uF")
      (footprint "SMD_0805_CAPC2012X145N")
      (fields
        (field (name "DB_PART_NUMBER") "CAP000043686")
        (field (name "DB_VALUE") "22uF")
        (field (name "DB_TOLERANCE") "20%")
        (field (name "DB_VOLTAGE") "6.3V")
        (field (name "DB_MANUFACTURER_PART") "KEMET    C0805C226M9PAC")
        (field (name "DB_APPROVED_BY") "ISHIDDEN=T")
      )
      (libsource (lib "Database_Libs1") (part "C"))
    )
    (comp (ref "C1067")
      (value "220uF")
      (footprint "SMD_1210_CAPC3225X279N")
      (fields
        (field (name "DB_PART_NUMBER") "CAP000047355")
        (field (name "DB_VALUE") "220uF")
        (field (name "DB_TOLERANCE") "20%")
        (field (name "DB_VOLTAGE") "6.3V")
        (field (name "DB_MANUFACTURER_PART") "SAMSUNG    CL32A227MQVNNNE")
        (field (name "DB_APPROVED_BY") "VSN")
      )
      (libsource (lib "Database_Libs1") (part "C"))
    )
    (comp (ref "C1068")
      (value "22uF")
      (footprint "SMD_0805_CAPC2012X145N")
      (fields
        (field (name "DB_PART_NUMBER") "CAP000043686")
        (field (name "DB_VALUE") "22uF")
        (field (name "DB_TOLERANCE") "20%")
        (field (name "DB_VOLTAGE") "6.3V")
        (field (name "DB_MANUFACTURER_PART") "KEMET    C0805C226M9PAC")
        (field (name "DB_APPROVED_BY") "ISHIDDEN=T")
      )
      (libsource (lib "Database_Libs1") (part "C"))
    )
    (comp (ref "C1069")
      (value "22uF")
      (footprint "SMD_0805_CAPC2012X145N")
      (fields
        (field (name "DB_PART_NUMBER") "CAP000043686")
        (field (name "DB_VALUE") "22uF")
        (field (name "DB_TOLERANCE") "20%")
        (field (name "DB_VOLTAGE") "6.3V")
        (field (name "DB_MANUFACTURER_PART") "KEMET    C0805C226M9PAC")
        (field (name "DB_APPROVED_BY") "ISHIDDEN=T")
      )
      (libsource (lib "Database_Libs1") (part "C"))
    )
    (comp (ref "C1070")
      (value "220uF")
      (footprint "SMD_1210_CAPC3225X279N")
      (fields
        (field (name "DB_PART_NUMBER") "CAP000047355")
        (field (name "DB_VALUE") "220uF")
        (field (name "DB_TOLERANCE") "20%")
        (field (name "DB_VOLTAGE") "6.3V")
        (field (name "DB_MANUFACTURER_PART") "SAMSUNG    CL32A227MQVNNNE")
        (field (name "DB_APPROVED_BY") "VSN")
      )
      (libsource (lib "Database_Libs1") (part "C"))
    )
    (comp (ref "C1071")
      (value "22uF")
      (footprint "SMD_0805_CAPC2012X145N")
      (fields
        (field (name "DB_PART_NUMBER") "CAP000043686")
        (field (name "DB_VALUE") "22uF")
        (field (name "DB_TOLERANCE") "20%")
        (field (name "DB_VOLTAGE") "6.3V")
        (field (name "DB_MANUFACTURER_PART") "KEMET    C0805C226M9PAC")
        (field (name "DB_APPROVED_BY") "ISHIDDEN=T")
      )
      (libsource (lib "Database_Libs1") (part "C"))
    )
    (comp (ref "D10")
      (value "1N4448HWT")
      (footprint "SMD_SOD523_SOD1608X65N")
      (fields
        (field (name "DB_PART_NUMBER") "DDE000001203")
        (field (name "DB_VALUE") "1N4448HWT")
        (field (name "DB_MANUFACTURER_PART") "Diodes        1N4448HWT")
        (field (name "DB_APPROVED_BY") "ISHIDDEN=T")
      )
      (libsource (lib "Database_Libs1") (part "D"))
    )
    (comp (ref "D11")
      (value "1N4448HWT")
      (footprint "SMD_SOD523_SOD1608X65N")
      (fields
        (field (name "DB_PART_NUMBER") "DDE000001203")
        (field (name "DB_VALUE") "1N4448HWT")
        (field (name "DB_MANUFACTURER_PART") "Diodes        1N4448HWT")
        (field (name "DB_APPROVED_BY") "ISHIDDEN=T")
      )
      (libsource (lib "Database_Libs1") (part "D"))
    )
    (comp (ref "D14")
      (value "1N4448HWT")
      (footprint "SMD_SOD523_SOD1608X65N")
      (fields
        (field (name "DB_PART_NUMBER") "DDE000001203")
        (field (name "DB_VALUE") "1N4448HWT")
        (field (name "DB_MANUFACTURER_PART") "Diodes        1N4448HWT")
        (field (name "DB_APPROVED_BY") "ISHIDDEN=T")
      )
      (libsource (lib "Database_Libs1") (part "D"))
    )
    (comp (ref "D15")
      (value "1N4448HWT")
      (footprint "SMD_SOD523_SOD1608X65N")
      (fields
        (field (name "DB_PART_NUMBER") "DDE000001203")
        (field (name "DB_VALUE") "1N4448HWT")
        (field (name "DB_MANUFACTURER_PART") "Diodes        1N4448HWT")
        (field (name "DB_APPROVED_BY") "ISHIDDEN=T")
      )
      (libsource (lib "Database_Libs1") (part "D"))
    )
    (comp (ref "D18")
      (value "1N4448HWT")
      (footprint "SMD_SOD523_SOD1608X65N")
      (fields
        (field (name "DB_PART_NUMBER") "DDE000001203")
        (field (name "DB_VALUE") "1N4448HWT")
        (field (name "DB_MANUFACTURER_PART") "Diodes        1N4448HWT")
        (field (name "DB_APPROVED_BY") "ISHIDDEN=T")
      )
      (libsource (lib "Database_Libs1") (part "D"))
    )
    (comp (ref "D19")
      (value "1N4448HWT")
      (footprint "SMD_SOD523_SOD1608X65N")
      (fields
        (field (name "DB_PART_NUMBER") "DDE000001203")
        (field (name "DB_VALUE") "1N4448HWT")
        (field (name "DB_MANUFACTURER_PART") "Diodes        1N4448HWT")
        (field (name "DB_APPROVED_BY") "ISHIDDEN=T")
      )
      (libsource (lib "Database_Libs1") (part "D"))
    )
    (comp (ref "D22")
      (value "1N4448HWT")
      (footprint "SMD_SOD523_SOD1608X65N")
      (fields
        (field (name "DB_PART_NUMBER") "DDE000001203")
        (field (name "DB_VALUE") "1N4448HWT")
        (field (name "DB_MANUFACTURER_PART") "Diodes        1N4448HWT")
        (field (name "DB_APPROVED_BY") "ISHIDDEN=T")
      )
      (libsource (lib "Database_Libs1") (part "D"))
    )
    (comp (ref "D23")
      (value "1N4448HWT")
      (footprint "SMD_SOD523_SOD1608X65N")
      (fields
        (field (name "DB_PART_NUMBER") "DDE000001203")
        (field (name "DB_VALUE") "1N4448HWT")
        (field (name "DB_MANUFACTURER_PART") "Diodes        1N4448HWT")
        (field (name "DB_APPROVED_BY") "ISHIDDEN=T")
      )
      (libsource (lib "Database_Libs1") (part "D"))
    )
    (comp (ref "L1")
      (value "~")
      (footprint "SMT_INDM135130X800N")
      (libsource (lib "EPIQ_DND_CIS_Library") (part "L"))
    )
    (comp (ref "L2")
      (value "~")
      (footprint "SMT_INDM135130X800N")
      (libsource (lib "EPIQ_DND_CIS_Library") (part "L"))
    )
    (comp (ref "L5")
      (value "~")
      (footprint "SMT_INDM135130X800N")
      (libsource (lib "EPIQ_DND_CIS_Library") (part "L"))
    )
    (comp (ref "L6")
      (value "~")
      (footprint "SMT_INDM135130X800N")
      (libsource (lib "EPIQ_DND_CIS_Library") (part "L"))
    )
    (comp (ref "L9")
      (value "~")
      (footprint "SMT_INDM135130X800N")
      (libsource (lib "EPIQ_DND_CIS_Library") (part "L"))
    )
    (comp (ref "L10")
      (value "~")
      (footprint "SMT_INDM135130X800N")
      (libsource (lib "EPIQ_DND_CIS_Library") (part "L"))
    )
    (comp (ref "L13")
      (value "~")
      (footprint "SMT_INDM135130X800N")
      (libsource (lib "EPIQ_DND_CIS_Library") (part "L"))
    )
    (comp (ref "L14")
      (value "~")
      (footprint "SMT_INDM135130X800N")
      (libsource (lib "EPIQ_DND_CIS_Library") (part "L"))
    )
    (comp (ref "Q1")
      (value "AP1RA03GMT-HF-3")
      (footprint "SMD_SOIC127P600X110-9AN")
      (fields
        (field (name "DB_PART_NUMBER") "TRA000001604")
        (field (name "DB_VALUE") "AP1RA03GMT-HF-3")
        (field (name "DB_MANUFACTURER_PART") "ADVANCED POWER ELECTRONICS CORP      AP1RA03GMT-HF-3")
        (field (name "DB_APPROVED_BY") "VSN")
      )
      (libsource (lib "Database_Libs1") (part "MOS_N_D1_S1S2S3G4D5D6D7D8"))
    )
    (comp (ref "Q2")
      (value "AP1RA03GMT-HF-3")
      (footprint "SMD_SOIC127P600X110-9AN")
      (fields
        (field (name "DB_PART_NUMBER") "TRA000001604")
        (field (name "DB_VALUE") "AP1RA03GMT-HF-3")
        (field (name "DB_MANUFACTURER_PART") "ADVANCED POWER ELECTRONICS CORP      AP1RA03GMT-HF-3")
        (field (name "DB_APPROVED_BY") "VSN")
      )
      (libsource (lib "Database_Libs1") (part "MOS_N_D1_S1S2S3G4D5D6D7D8"))
    )
    (comp (ref "Q5")
      (value "AP1RA03GMT-HF-3")
      (footprint "SMD_SOIC127P600X110-9AN")
      (fields
        (field (name "DB_PART_NUMBER") "TRA000001604")
        (field (name "DB_VALUE") "AP1RA03GMT-HF-3")
        (field (name "DB_MANUFACTURER_PART") "ADVANCED POWER ELECTRONICS CORP      AP1RA03GMT-HF-3")
        (field (name "DB_APPROVED_BY") "VSN")
      )
      (libsource (lib "Database_Libs1") (part "MOS_N_D1_S1S2S3G4D5D6D7D8"))
    )
    (comp (ref "Q6")
      (value "AP1RA03GMT-HF-3")
      (footprint "SMD_SOIC127P600X110-9AN")
      (fields
        (field (name "DB_PART_NUMBER") "TRA000001604")
        (field (name "DB_VALUE") "AP1RA03GMT-HF-3")
        (field (name "DB_MANUFACTURER_PART") "ADVANCED POWER ELECTRONICS CORP      AP1RA03GMT-HF-3")
        (field (name "DB_APPROVED_BY") "VSN")
      )
      (libsource (lib "Database_Libs1") (part "MOS_N_D1_S1S2S3G4D5D6D7D8"))
    )
    (comp (ref "Q7")
      (value "AP1RA03GMT-HF-3")
      (footprint "SMD_SOIC127P600X110-9AN")
      (fields
        (field (name "DB_PART_NUMBER") "TRA000001604")
        (field (name "DB_VALUE") "AP1RA03GMT-HF-3")
        (field (name "DB_MANUFACTURER_PART") "ADVANCED POWER ELECTRONICS CORP      AP1RA03GMT-HF-3")
        (field (name "DB_APPROVED_BY") "VSN")
      )
      (libsource (lib "Database_Libs1") (part "MOS_N_D1_S1S2S3G4D5D6D7D8"))
    )
    (comp (ref "Q8")
      (value "AP1RA03GMT-HF-3")
      (footprint "SMD_SOIC127P600X110-9AN")
      (fields
        (field (name "DB_PART_NUMBER") "TRA000001604")
        (field (name "DB_VALUE") "AP1RA03GMT-HF-3")
        (field (name "DB_MANUFACTURER_PART") "ADVANCED POWER ELECTRONICS CORP      AP1RA03GMT-HF-3")
        (field (name "DB_APPROVED_BY") "VSN")
      )
      (libsource (lib "Database_Libs1") (part "MOS_N_D1_S1S2S3G4D5D6D7D8"))
    )
    (comp (ref "Q13")
      (value "AP1RA03GMT-HF-3")
      (footprint "SMD_SOIC127P600X110-9AN")
      (fields
        (field (name "DB_PART_NUMBER") "TRA000001604")
        (field (name "DB_VALUE") "AP1RA03GMT-HF-3")
        (field (name "DB_MANUFACTURER_PART") "ADVANCED POWER ELECTRONICS CORP      AP1RA03GMT-HF-3")
        (field (name "DB_APPROVED_BY") "VSN")
      )
      (libsource (lib "Database_Libs1") (part "MOS_N_D1_S1S2S3G4D5D6D7D8"))
    )
    (comp (ref "Q14")
      (value "AP1RA03GMT-HF-3")
      (footprint "SMD_SOIC127P600X110-9AN")
      (fields
        (field (name "DB_PART_NUMBER") "TRA000001604")
        (field (name "DB_VALUE") "AP1RA03GMT-HF-3")
        (field (name "DB_MANUFACTURER_PART") "ADVANCED POWER ELECTRONICS CORP      AP1RA03GMT-HF-3")
        (field (name "DB_APPROVED_BY") "VSN")
      )
      (libsource (lib "Database_Libs1") (part "MOS_N_D1_S1S2S3G4D5D6D7D8"))
    )
    (comp (ref "Q17")
      (value "AP1RA03GMT-HF-3")
      (footprint "SMD_SOIC127P600X110-9AN")
      (fields
        (field (name "DB_PART_NUMBER") "TRA000001604")
        (field (name "DB_VALUE") "AP1RA03GMT-HF-3")
        (field (name "DB_MANUFACTURER_PART") "ADVANCED POWER ELECTRONICS CORP      AP1RA03GMT-HF-3")
        (field (name "DB_APPROVED_BY") "VSN")
      )
      (libsource (lib "Database_Libs1") (part "MOS_N_D1_S1S2S3G4D5D6D7D8"))
    )
    (comp (ref "Q18")
      (value "AP1RA03GMT-HF-3")
      (footprint "SMD_SOIC127P600X110-9AN")
      (fields
        (field (name "DB_PART_NUMBER") "TRA000001604")
        (field (name "DB_VALUE") "AP1RA03GMT-HF-3")
        (field (name "DB_MANUFACTURER_PART") "ADVANCED POWER ELECTRONICS CORP      AP1RA03GMT-HF-3")
        (field (name "DB_APPROVED_BY") "VSN")
      )
      (libsource (lib "Database_Libs1") (part "MOS_N_D1_S1S2S3G4D5D6D7D8"))
    )
    (comp (ref "Q19")
      (value "AP1RA03GMT-HF-3")
      (footprint "SMD_SOIC127P600X110-9AN")
      (fields
        (field (name "DB_PART_NUMBER") "TRA000001604")
        (field (name "DB_VALUE") "AP1RA03GMT-HF-3")
        (field (name "DB_MANUFACTURER_PART") "ADVANCED POWER ELECTRONICS CORP      AP1RA03GMT-HF-3")
        (field (name "DB_APPROVED_BY") "VSN")
      )
      (libsource (lib "Database_Libs1") (part "MOS_N_D1_S1S2S3G4D5D6D7D8"))
    )
    (comp (ref "Q20")
      (value "AP1RA03GMT-HF-3")
      (footprint "SMD_SOIC127P600X110-9AN")
      (fields
        (field (name "DB_PART_NUMBER") "TRA000001604")
        (field (name "DB_VALUE") "AP1RA03GMT-HF-3")
        (field (name "DB_MANUFACTURER_PART") "ADVANCED POWER ELECTRONICS CORP      AP1RA03GMT-HF-3")
        (field (name "DB_APPROVED_BY") "VSN")
      )
      (libsource (lib "Database_Libs1") (part "MOS_N_D1_S1S2S3G4D5D6D7D8"))
    )
    (comp (ref "Q25")
      (value "AP1RA03GMT-HF-3")
      (footprint "SMD_SOIC127P600X110-9AN")
      (fields
        (field (name "DB_PART_NUMBER") "TRA000001604")
        (field (name "DB_VALUE") "AP1RA03GMT-HF-3")
        (field (name "DB_MANUFACTURER_PART") "ADVANCED POWER ELECTRONICS CORP      AP1RA03GMT-HF-3")
        (field (name "DB_APPROVED_BY") "VSN")
      )
      (libsource (lib "Database_Libs1") (part "MOS_N_D1_S1S2S3G4D5D6D7D8"))
    )
    (comp (ref "Q26")
      (value "AP1RA03GMT-HF-3")
      (footprint "SMD_SOIC127P600X110-9AN")
      (fields
        (field (name "DB_PART_NUMBER") "TRA000001604")
        (field (name "DB_VALUE") "AP1RA03GMT-HF-3")
        (field (name "DB_MANUFACTURER_PART") "ADVANCED POWER ELECTRONICS CORP      AP1RA03GMT-HF-3")
        (field (name "DB_APPROVED_BY") "VSN")
      )
      (libsource (lib "Database_Libs1") (part "MOS_N_D1_S1S2S3G4D5D6D7D8"))
    )
    (comp (ref "Q29")
      (value "AP1RA03GMT-HF-3")
      (footprint "SMD_SOIC127P600X110-9AN")
      (fields
        (field (name "DB_PART_NUMBER") "TRA000001604")
        (field (name "DB_VALUE") "AP1RA03GMT-HF-3")
        (field (name "DB_MANUFACTURER_PART") "ADVANCED POWER ELECTRONICS CORP      AP1RA03GMT-HF-3")
        (field (name "DB_APPROVED_BY") "VSN")
      )
      (libsource (lib "Database_Libs1") (part "MOS_N_D1_S1S2S3G4D5D6D7D8"))
    )
    (comp (ref "Q30")
      (value "AP1RA03GMT-HF-3")
      (footprint "SMD_SOIC127P600X110-9AN")
      (fields
        (field (name "DB_PART_NUMBER") "TRA000001604")
        (field (name "DB_VALUE") "AP1RA03GMT-HF-3")
        (field (name "DB_MANUFACTURER_PART") "ADVANCED POWER ELECTRONICS CORP      AP1RA03GMT-HF-3")
        (field (name "DB_APPROVED_BY") "VSN")
      )
      (libsource (lib "Database_Libs1") (part "MOS_N_D1_S1S2S3G4D5D6D7D8"))
    )
    (comp (ref "Q31")
      (value "AP1RA03GMT-HF-3")
      (footprint "SMD_SOIC127P600X110-9AN")
      (fields
        (field (name "DB_PART_NUMBER") "TRA000001604")
        (field (name "DB_VALUE") "AP1RA03GMT-HF-3")
        (field (name "DB_MANUFACTURER_PART") "ADVANCED POWER ELECTRONICS CORP      AP1RA03GMT-HF-3")
        (field (name "DB_APPROVED_BY") "VSN")
      )
      (libsource (lib "Database_Libs1") (part "MOS_N_D1_S1S2S3G4D5D6D7D8"))
    )
    (comp (ref "Q32")
      (value "AP1RA03GMT-HF-3")
      (footprint "SMD_SOIC127P600X110-9AN")
      (fields
        (field (name "DB_PART_NUMBER") "TRA000001604")
        (field (name "DB_VALUE") "AP1RA03GMT-HF-3")
        (field (name "DB_MANUFACTURER_PART") "ADVANCED POWER ELECTRONICS CORP      AP1RA03GMT-HF-3")
        (field (name "DB_APPROVED_BY") "VSN")
      )
      (libsource (lib "Database_Libs1") (part "MOS_N_D1_S1S2S3G4D5D6D7D8"))
    )
    (comp (ref "Q37")
      (value "AP1RA03GMT-HF-3")
      (footprint "SMD_SOIC127P600X110-9AN")
      (fields
        (field (name "DB_PART_NUMBER") "TRA000001604")
        (field (name "DB_VALUE") "AP1RA03GMT-HF-3")
        (field (name "DB_MANUFACTURER_PART") "ADVANCED POWER ELECTRONICS CORP      AP1RA03GMT-HF-3")
        (field (name "DB_APPROVED_BY") "VSN")
      )
      (libsource (lib "Database_Libs1") (part "MOS_N_D1_S1S2S3G4D5D6D7D8"))
    )
    (comp (ref "Q38")
      (value "AP1RA03GMT-HF-3")
      (footprint "SMD_SOIC127P600X110-9AN")
      (fields
        (field (name "DB_PART_NUMBER") "TRA000001604")
        (field (name "DB_VALUE") "AP1RA03GMT-HF-3")
        (field (name "DB_MANUFACTURER_PART") "ADVANCED POWER ELECTRONICS CORP      AP1RA03GMT-HF-3")
        (field (name "DB_APPROVED_BY") "VSN")
      )
      (libsource (lib "Database_Libs1") (part "MOS_N_D1_S1S2S3G4D5D6D7D8"))
    )
    (comp (ref "Q41")
      (value "AP1RA03GMT-HF-3")
      (footprint "SMD_SOIC127P600X110-9AN")
      (fields
        (field (name "DB_PART_NUMBER") "TRA000001604")
        (field (name "DB_VALUE") "AP1RA03GMT-HF-3")
        (field (name "DB_MANUFACTURER_PART") "ADVANCED POWER ELECTRONICS CORP      AP1RA03GMT-HF-3")
        (field (name "DB_APPROVED_BY") "VSN")
      )
      (libsource (lib "Database_Libs1") (part "MOS_N_D1_S1S2S3G4D5D6D7D8"))
    )
    (comp (ref "Q42")
      (value "AP1RA03GMT-HF-3")
      (footprint "SMD_SOIC127P600X110-9AN")
      (fields
        (field (name "DB_PART_NUMBER") "TRA000001604")
        (field (name "DB_VALUE") "AP1RA03GMT-HF-3")
        (field (name "DB_MANUFACTURER_PART") "ADVANCED POWER ELECTRONICS CORP      AP1RA03GMT-HF-3")
        (field (name "DB_APPROVED_BY") "VSN")
      )
      (libsource (lib "Database_Libs1") (part "MOS_N_D1_S1S2S3G4D5D6D7D8"))
    )
    (comp (ref "Q43")
      (value "AP1RA03GMT-HF-3")
      (footprint "SMD_SOIC127P600X110-9AN")
      (fields
        (field (name "DB_PART_NUMBER") "TRA000001604")
        (field (name "DB_VALUE") "AP1RA03GMT-HF-3")
        (field (name "DB_MANUFACTURER_PART") "ADVANCED POWER ELECTRONICS CORP      AP1RA03GMT-HF-3")
        (field (name "DB_APPROVED_BY") "VSN")
      )
      (libsource (lib "Database_Libs1") (part "MOS_N_D1_S1S2S3G4D5D6D7D8"))
    )
    (comp (ref "Q44")
      (value "AP1RA03GMT-HF-3")
      (footprint "SMD_SOIC127P600X110-9AN")
      (fields
        (field (name "DB_PART_NUMBER") "TRA000001604")
        (field (name "DB_VALUE") "AP1RA03GMT-HF-3")
        (field (name "DB_MANUFACTURER_PART") "ADVANCED POWER ELECTRONICS CORP      AP1RA03GMT-HF-3")
        (field (name "DB_APPROVED_BY") "VSN")
      )
      (libsource (lib "Database_Libs1") (part "MOS_N_D1_S1S2S3G4D5D6D7D8"))
    )
    (comp (ref "U11")
      (value "LTC4449EDCB#TRPBF")
      (footprint "SMD_SON45P300X200X80-9N")
      (fields
        (field (name "DB_PART_NUMBER") "DRV000000079")
        (field (name "DB_VALUE") "LTC4449EDCB#TRPBF")
        (field (name "DB_MANUFACTURER_PART") "LINEAR       LTC4449EDCB#TRPBF")
        (field (name "DB_APPROVED_BY") "VSN")
      )
      (libsource (lib "Database_Libs1") (part "IC_LTC4449"))
    )
    (comp (ref "U12")
      (value "LTC4449EDCB#TRPBF")
      (footprint "SMD_SON45P300X200X80-9N")
      (fields
        (field (name "DB_PART_NUMBER") "DRV000000079")
        (field (name "DB_VALUE") "LTC4449EDCB#TRPBF")
        (field (name "DB_MANUFACTURER_PART") "LINEAR       LTC4449EDCB#TRPBF")
        (field (name "DB_APPROVED_BY") "VSN")
      )
      (libsource (lib "Database_Libs1") (part "IC_LTC4449"))
    )
    (comp (ref "U15")
      (value "LTC4449EDCB#TRPBF")
      (footprint "SMD_SON45P300X200X80-9N")
      (fields
        (field (name "DB_PART_NUMBER") "DRV000000079")
        (field (name "DB_VALUE") "LTC4449EDCB#TRPBF")
        (field (name "DB_MANUFACTURER_PART") "LINEAR       LTC4449EDCB#TRPBF")
        (field (name "DB_APPROVED_BY") "VSN")
      )
      (libsource (lib "Database_Libs1") (part "IC_LTC4449"))
    )
    (comp (ref "U16")
      (value "LTC4449EDCB#TRPBF")
      (footprint "SMD_SON45P300X200X80-9N")
      (fields
        (field (name "DB_PART_NUMBER") "DRV000000079")
        (field (name "DB_VALUE") "LTC4449EDCB#TRPBF")
        (field (name "DB_MANUFACTURER_PART") "LINEAR       LTC4449EDCB#TRPBF")
        (field (name "DB_APPROVED_BY") "VSN")
      )
      (libsource (lib "Database_Libs1") (part "IC_LTC4449"))
    )
    (comp (ref "U19")
      (value "LTC4449EDCB#TRPBF")
      (footprint "SMD_SON45P300X200X80-9N")
      (fields
        (field (name "DB_PART_NUMBER") "DRV000000079")
        (field (name "DB_VALUE") "LTC4449EDCB#TRPBF")
        (field (name "DB_MANUFACTURER_PART") "LINEAR       LTC4449EDCB#TRPBF")
        (field (name "DB_APPROVED_BY") "VSN")
      )
      (libsource (lib "Database_Libs1") (part "IC_LTC4449"))
    )
    (comp (ref "U20")
      (value "LTC4449EDCB#TRPBF")
      (footprint "SMD_SON45P300X200X80-9N")
      (fields
        (field (name "DB_PART_NUMBER") "DRV000000079")
        (field (name "DB_VALUE") "LTC4449EDCB#TRPBF")
        (field (name "DB_MANUFACTURER_PART") "LINEAR       LTC4449EDCB#TRPBF")
        (field (name "DB_APPROVED_BY") "VSN")
      )
      (libsource (lib "Database_Libs1") (part "IC_LTC4449"))
    )
    (comp (ref "U23")
      (value "LTC4449EDCB#TRPBF")
      (footprint "SMD_SON45P300X200X80-9N")
      (fields
        (field (name "DB_PART_NUMBER") "DRV000000079")
        (field (name "DB_VALUE") "LTC4449EDCB#TRPBF")
        (field (name "DB_MANUFACTURER_PART") "LINEAR       LTC4449EDCB#TRPBF")
        (field (name "DB_APPROVED_BY") "VSN")
      )
      (libsource (lib "Database_Libs1") (part "IC_LTC4449"))
    )
    (comp (ref "U24")
      (value "LTC4449EDCB#TRPBF")
      (footprint "SMD_SON45P300X200X80-9N")
      (fields
        (field (name "DB_PART_NUMBER") "DRV000000079")
        (field (name "DB_VALUE") "LTC4449EDCB#TRPBF")
        (field (name "DB_MANUFACTURER_PART") "LINEAR       LTC4449EDCB#TRPBF")
        (field (name "DB_APPROVED_BY") "VSN")
      )
      (libsource (lib "Database_Libs1") (part "IC_LTC4449"))
    )
  )
  (nets
    (net (code "1") (name "/1V") (class "Default")
      (node (ref "C100") (pin "2") (pinfunction "2_2") (pintype "passive"))
      (node (ref "C1000") (pin "1") (pinfunction "1_1") (pintype "passive"))
      (node (ref "C1001") (pin "2") (pinfunction "2_2") (pintype "passive"))
      (node (ref "C1002") (pin "1") (pinfunction "1_1") (pintype "passive"))
      (node (ref "C1003") (pin "1") (pinfunction "1_1") (pintype "passive"))
      (node (ref "C1004") (pin "2") (pinfunction "2_2") (pintype "passive"))
      (node (ref "C1005") (pin "1") (pinfunction "1_1") (pintype "passive"))
      (node (ref "C1006") (pin "1") (pinfunction "1_1") (pintype "passive"))
      (node (ref "C1007") (pin "2") (pinfunction "2_2") (pintype "passive"))
      (node (ref "C1008") (pin "1") (pinfunction "1_1") (pintype "passive"))
      (node (ref "C1009") (pin "1") (pinfunction "1_1") (pintype "passive"))
      (node (ref "C1010") (pin "2") (pinfunction "2_2") (pintype "passive"))
      (node (ref "C1011") (pin "1") (pinfunction "1_1") (pintype "passive"))
      (node (ref "C1012") (pin "1") (pinfunction "1_1") (pintype "passive"))
      (node (ref "C1013") (pin "2") (pinfunction "2_2") (pintype "passive"))
      (node (ref "C1014") (pin "1") (pinfunction "1_1") (pintype "passive"))
      (node (ref "C1015") (pin "1") (pinfunction "1_1") (pintype "passive"))
      (node (ref "C1016") (pin "2") (pinfunction "2_2") (pintype "passive"))
      (node (ref "C1017") (pin "1") (pinfunction "1_1") (pintype "passive"))
      (node (ref "C1018") (pin "1") (pinfunction "1_1") (pintype "passive"))
      (node (ref "C1019") (pin "2") (pinfunction "2_2") (pintype "passive"))
      (node (ref "C1020") (pin "1") (pinfunction "1_1") (pintype "passive"))
      (node (ref "C1021") (pin "1") (pinfunction "1_1") (pintype "passive"))
      (node (ref "C1022") (pin "2") (pinfunction "2_2") (pintype "passive"))
      (node (ref "C1023") (pin "1") (pinfunction "1_1") (pintype "passive"))
      (node (ref "C1024") (pin "1") (pinfunction "1_1") (pintype "passive"))
      (node (ref "C1025") (pin "2") (pinfunction "2_2") (pintype "passive"))
      (node (ref "C1026") (pin "1") (pinfunction "1_1") (pintype "passive"))
      (node (ref "C1027") (pin "1") (pinfunction "1_1") (pintype "passive"))
      (node (ref "C1028") (pin "2") (pinfunction "2_2") (pintype "passive"))
      (node (ref "C1029") (pin "1") (pinfunction "1_1") (pintype "passive"))
      (node (ref "C103") (pin "2") (pinfunction "2_2") (pintype "passive"))
      (node (ref "C1030") (pin "1") (pinfunction "1_1") (pintype "passive"))
      (node (ref "C1031") (pin "2") (pinfunction "2_2") (pintype "passive"))
      (node (ref "C1032") (pin "1") (pinfunction "1_1") (pintype "passive"))
      (node (ref "C1033") (pin "1") (pinfunction "1_1") (pintype "passive"))
      (node (ref "C1034") (pin "2") (pinfunction "2_2") (pintype "passive"))
      (node (ref "C1035") (pin "1") (pinfunction "1_1") (pintype "passive"))
      (node (ref "C1036") (pin "1") (pinfunction "1_1") (pintype "passive"))
      (node (ref "C1037") (pin "2") (pinfunction "2_2") (pintype "passive"))
      (node (ref "C1038") (pin "1") (pinfunction "1_1") (pintype "passive"))
      (node (ref "C1039") (pin "1") (pinfunction "1_1") (pintype "passive"))
      (node (ref "C104") (pin "2") (pinfunction "2_2") (pintype "passive"))
      (node (ref "C1040") (pin "2") (pinfunction "2_2") (pintype "passive"))
      (node (ref "C1041") (pin "1") (pinfunction "1_1") (pintype "passive"))
      (node (ref "C1042") (pin "1") (pinfunction "1_1") (pintype "passive"))
      (node (ref "C1043") (pin "2") (pinfunction "2_2") (pintype "passive"))
      (node (ref "C1044") (pin "1") (pinfunction "1_1") (pintype "passive"))
      (node (ref "C1045") (pin "1") (pinfunction "1_1") (pintype "passive"))
      (node (ref "C1046") (pin "2") (pinfunction "2_2") (pintype "passive"))
      (node (ref "C1047") (pin "1") (pinfunction "1_1") (pintype "passive"))
      (node (ref "C1048") (pin "1") (pinfunction "1_1") (pintype "passive"))
      (node (ref "C1049") (pin "2") (pinfunction "2_2") (pintype "passive"))
      (node (ref "C105") (pin "2") (pinfunction "2_2") (pintype "passive"))
      (node (ref "C1050") (pin "1") (pinfunction "1_1") (pintype "passive"))
      (node (ref "C1051") (pin "1") (pinfunction "1_1") (pintype "passive"))
      (node (ref "C1052") (pin "2") (pinfunction "2_2") (pintype "passive"))
      (node (ref "C1053") (pin "1") (pinfunction "1_1") (pintype "passive"))
      (node (ref "C1054") (pin "1") (pinfunction "1_1") (pintype "passive"))
      (node (ref "C1055") (pin "2") (pinfunction "2_2") (pintype "passive"))
      (node (ref "C1056") (pin "1") (pinfunction "1_1") (pintype "passive"))
      (node (ref "C1057") (pin "1") (pinfunction "1_1") (pintype "passive"))
      (node (ref "C1058") (pin "2") (pinfunction "2_2") (pintype "passive"))
      (node (ref "C1059") (pin "1") (pinfunction "1_1") (pintype "passive"))
      (node (ref "C1060") (pin "1") (pinfunction "1_1") (pintype "passive"))
      (node (ref "C1061") (pin "2") (pinfunction "2_2") (pintype "passive"))
      (node (ref "C1062") (pin "1") (pinfunction "1_1") (pintype "passive"))
      (node (ref "C1063") (pin "1") (pinfunction "1_1") (pintype "passive"))
      (node (ref "C1064") (pin "2") (pinfunction "2_2") (pintype "passive"))
      (node (ref "C1065") (pin "1") (pinfunction "1_1") (pintype "passive"))
      (node (ref "C1066") (pin "1") (pinfunction "1_1") (pintype "passive"))
      (node (ref "C1067") (pin "2") (pinfunction "2_2") (pintype "passive"))
      (node (ref "C1068") (pin "1") (pinfunction "1_1") (pintype "passive"))
      (node (ref "C1069") (pin "1") (pinfunction "1_1") (pintype "passive"))
      (node (ref "C1070") (pin "2") (pinfunction "2_2") (pintype "passive"))
      (node (ref "C1071") (pin "1") (pinfunction "1_1") (pintype "passive"))
      (node (ref "C130") (pin "2") (pinfunction "2_2") (pintype "passive"))
      (node (ref "C131") (pin "2") (pinfunction "2_2") (pintype "passive"))
      (node (ref "C132") (pin "2") (pinfunction "2_2") (pintype "passive"))
      (node (ref "C135") (pin "2") (pinfunction "2_2") (pintype "passive"))
      (node (ref "C136") (pin "2") (pinfunction "2_2") (pintype "passive"))
      (node (ref "C137") (pin "2") (pinfunction "2_2") (pintype "passive"))
      (node (ref "C236") (pin "2") (pinfunction "2_2") (pintype "passive"))
      (node (ref "C323") (pin "1") (pinfunction "1_1") (pintype "passive"))
      (node (ref "C324") (pin "1") (pinfunction "1_1") (pintype "passive"))
      (node (ref "C325") (pin "1") (pinfunction "1_1") (pintype "passive"))
      (node (ref "C326") (pin "1") (pinfunction "1_1") (pintype "passive"))
      (node (ref "C327") (pin "1") (pinfunction "1_1") (pintype "passive"))
      (node (ref "C328") (pin "1") (pinfunction "1_1") (pintype "passive"))
      (node (ref "C329") (pin "1") (pinfunction "1_1") (pintype "passive"))
      (node (ref "C330") (pin "1") (pinfunction "1_1") (pintype "passive"))
      (node (ref "C331") (pin "1") (pinfunction "1_1") (pintype "passive"))
      (node (ref "C332") (pin "1") (pinfunction "1_1") (pintype "passive"))
      (node (ref "C333") (pin "1") (pinfunction "1_1") (pintype "passive"))
      (node (ref "C334") (pin "1") (pinfunction "1_1") (pintype "passive"))
      (node (ref "C335") (pin "1") (pinfunction "1_1") (pintype "passive"))
      (node (ref "C336") (pin "1") (pinfunction "1_1") (pintype "passive"))
      (node (ref "C337") (pin "1") (pinfunction "1_1") (pintype "passive"))
      (node (ref "C338") (pin "1") (pinfunction "1_1") (pintype "passive"))
      (node (ref "C339") (pin "1") (pinfunction "1_1") (pintype "passive"))
      (node (ref "C34") (pin "2") (pinfunction "2_2") (pintype "passive"))
      (node (ref "C340") (pin "1") (pinfunction "1_1") (pintype "passive"))
      (node (ref "C341") (pin "1") (pinfunction "1_1") (pintype "passive"))
      (node (ref "C342") (pin "1") (pinfunction "1_1") (pintype "passive"))
      (node (ref "C343") (pin "1") (pinfunction "1_1") (pintype "passive"))
      (node (ref "C344") (pin "1") (pinfunction "1_1") (pintype "passive"))
      (node (ref "C345") (pin "1") (pinfunction "1_1") (pintype "passive"))
      (node (ref "C346") (pin "1") (pinfunction "1_1") (pintype "passive"))
      (node (ref "C35") (pin "2") (pinfunction "2_2") (pintype "passive"))
      (node (ref "C350") (pin "2") (pinfunction "2_2") (pintype "passive"))
      (node (ref "C351") (pin "2") (pinfunction "2_2") (pintype "passive"))
      (node (ref "C352") (pin "2") (pinfunction "2_2") (pintype "passive"))
      (node (ref "C353") (pin "1") (pinfunction "1_1") (pintype "passive"))
      (node (ref "C354") (pin "1") (pinfunction "1_1") (pintype "passive"))
      (node (ref "C355") (pin "1") (pinfunction "1_1") (pintype "passive"))
      (node (ref "C356") (pin "1") (pinfunction "1_1") (pintype "passive"))
      (node (ref "C357") (pin "1") (pinfunction "1_1") (pintype "passive"))
      (node (ref "C358") (pin "1") (pinfunction "1_1") (pintype "passive"))
      (node (ref "C359") (pin "1") (pinfunction "1_1") (pintype "passive"))
      (node (ref "C360") (pin "1") (pinfunction "1_1") (pintype "passive"))
      (node (ref "C361") (pin "1") (pinfunction "1_1") (pintype "passive"))
      (node (ref "C362") (pin "1") (pinfunction "1_1") (pintype "passive"))
      (node (ref "C363") (pin "1") (pinfunction "1_1") (pintype "passive"))
      (node (ref "C364") (pin "1") (pinfunction "1_1") (pintype "passive"))
      (node (ref "C365") (pin "1") (pinfunction "1_1") (pintype "passive"))
      (node (ref "C366") (pin "1") (pinfunction "1_1") (pintype "passive"))
      (node (ref "C367") (pin "1") (pinfunction "1_1") (pintype "passive"))
      (node (ref "C368") (pin "1") (pinfunction "1_1") (pintype "passive"))
      (node (ref "C369") (pin "1") (pinfunction "1_1") (pintype "passive"))
      (node (ref "C370") (pin "1") (pinfunction "1_1") (pintype "passive"))
      (node (ref "C371") (pin "1") (pinfunction "1_1") (pintype "passive"))
      (node (ref "C372") (pin "1") (pinfunction "1_1") (pintype "passive"))
      (node (ref "C373") (pin "1") (pinfunction "1_1") (pintype "passive"))
      (node (ref "C374") (pin "1") (pinfunction "1_1") (pintype "passive"))
      (node (ref "C375") (pin "1") (pinfunction "1_1") (pintype "passive"))
      (node (ref "C376") (pin "1") (pinfunction "1_1") (pintype "passive"))
      (node (ref "C39") (pin "2") (pinfunction "2_2") (pintype "passive"))
      (node (ref "C393") (pin "2") (pinfunction "2_2") (pintype "passive"))
      (node (ref "C394") (pin "2") (pinfunction "2_2") (pintype "passive"))
      (node (ref "C395") (pin "2") (pinfunction "2_2") (pintype "passive"))
      (node (ref "C396") (pin "2") (pinfunction "2_2") (pintype "passive"))
      (node (ref "C397") (pin "2") (pinfunction "2_2") (pintype "passive"))
      (node (ref "C398") (pin "2") (pinfunction "2_2") (pintype "passive"))
      (node (ref "C399") (pin "2") (pinfunction "2_2") (pintype "passive"))
      (node (ref "C40") (pin "2") (pinfunction "2_2") (pintype "passive"))
      (node (ref "C400") (pin "2") (pinfunction "2_2") (pintype "passive"))
      (node (ref "C401") (pin "2") (pinfunction "2_2") (pintype "passive"))
      (node (ref "C408") (pin "2") (pinfunction "2_2") (pintype "passive"))
      (node (ref "C409") (pin "2") (pinfunction "2_2") (pintype "passive"))
      (node (ref "C41") (pin "2") (pinfunction "2_2") (pintype "passive"))
      (node (ref "C410") (pin "2") (pinfunction "2_2") (pintype "passive"))
      (node (ref "C411") (pin "2") (pinfunction "2_2") (pintype "passive"))
      (node (ref "C412") (pin "2") (pinfunction "2_2") (pintype "passive"))
      (node (ref "C413") (pin "2") (pinfunction "2_2") (pintype "passive"))
      (node (ref "C414") (pin "2") (pinfunction "2_2") (pintype "passive"))
      (node (ref "C415") (pin "2") (pinfunction "2_2") (pintype "passive"))
      (node (ref "C416") (pin "2") (pinfunction "2_2") (pintype "passive"))
      (node (ref "C417") (pin "2") (pinfunction "2_2") (pintype "passive"))
      (node (ref "C418") (pin "2") (pinfunction "2_2") (pintype "passive"))
      (node (ref "C419") (pin "2") (pinfunction "2_2") (pintype "passive"))
      (node (ref "C444") (pin "1") (pinfunction "1_1") (pintype "passive"))
      (node (ref "C445") (pin "1") (pinfunction "1_1") (pintype "passive"))
      (node (ref "C446") (pin "1") (pinfunction "1_1") (pintype "passive"))
      (node (ref "C447") (pin "1") (pinfunction "1_1") (pintype "passive"))
      (node (ref "C448") (pin "1") (pinfunction "1_1") (pintype "passive"))
      (node (ref "C449") (pin "1") (pinfunction "1_1") (pintype "passive"))
      (node (ref "C450") (pin "1") (pinfunction "1_1") (pintype "passive"))
      (node (ref "C451") (pin "1") (pinfunction "1_1") (pintype "passive"))
      (node (ref "C452") (pin "1") (pinfunction "1_1") (pintype "passive"))
      (node (ref "C453") (pin "1") (pinfunction "1_1") (pintype "passive"))
      (node (ref "C454") (pin "1") (pinfunction "1_1") (pintype "passive"))
      (node (ref "C455") (pin "1") (pinfunction "1_1") (pintype "passive"))
      (node (ref "C456") (pin "1") (pinfunction "1_1") (pintype "passive"))
      (node (ref "C457") (pin "1") (pinfunction "1_1") (pintype "passive"))
      (node (ref "C458") (pin "1") (pinfunction "1_1") (pintype "passive"))
      (node (ref "C459") (pin "1") (pinfunction "1_1") (pintype "passive"))
      (node (ref "C460") (pin "1") (pinfunction "1_1") (pintype "passive"))
      (node (ref "C461") (pin "1") (pinfunction "1_1") (pintype "passive"))
      (node (ref "C462") (pin "1") (pinfunction "1_1") (pintype "passive"))
      (node (ref "C463") (pin "1") (pinfunction "1_1") (pintype "passive"))
      (node (ref "C464") (pin "1") (pinfunction "1_1") (pintype "passive"))
      (node (ref "C465") (pin "1") (pinfunction "1_1") (pintype "passive"))
      (node (ref "C466") (pin "1") (pinfunction "1_1") (pintype "passive"))
      (node (ref "C467") (pin "1") (pinfunction "1_1") (pintype "passive"))
      (node (ref "C468") (pin "1") (pinfunction "1_1") (pintype "passive"))
      (node (ref "C469") (pin "1") (pinfunction "1_1") (pintype "passive"))
      (node (ref "C470") (pin "1") (pinfunction "1_1") (pintype "passive"))
      (node (ref "C471") (pin "1") (pinfunction "1_1") (pintype "passive"))
      (node (ref "C472") (pin "1") (pinfunction "1_1") (pintype "passive"))
      (node (ref "C473") (pin "1") (pinfunction "1_1") (pintype "passive"))
      (node (ref "C474") (pin "1") (pinfunction "1_1") (pintype "passive"))
      (node (ref "C475") (pin "1") (pinfunction "1_1") (pintype "passive"))
      (node (ref "C476") (pin "1") (pinfunction "1_1") (pintype "passive"))
      (node (ref "C477") (pin "1") (pinfunction "1_1") (pintype "passive"))
      (node (ref "C478") (pin "1") (pinfunction "1_1") (pintype "passive"))
      (node (ref "C479") (pin "1") (pinfunction "1_1") (pintype "passive"))
      (node (ref "C480") (pin "1") (pinfunction "1_1") (pintype "passive"))
      (node (ref "C481") (pin "1") (pinfunction "1_1") (pintype "passive"))
      (node (ref "C482") (pin "1") (pinfunction "1_1") (pintype "passive"))
      (node (ref "C483") (pin "1") (pinfunction "1_1") (pintype "passive"))
      (node (ref "C484") (pin "1") (pinfunction "1_1") (pintype "passive"))
      (node (ref "C485") (pin "1") (pinfunction "1_1") (pintype "passive"))
      (node (ref "C486") (pin "1") (pinfunction "1_1") (pintype "passive"))
      (node (ref "C487") (pin "1") (pinfunction "1_1") (pintype "passive"))
      (node (ref "C488") (pin "1") (pinfunction "1_1") (pintype "passive"))
      (node (ref "C489") (pin "1") (pinfunction "1_1") (pintype "passive"))
      (node (ref "C490") (pin "1") (pinfunction "1_1") (pintype "passive"))
      (node (ref "C491") (pin "1") (pinfunction "1_1") (pintype "passive"))
      (node (ref "C652") (pin "1") (pinfunction "1_1") (pintype "passive"))
      (node (ref "C653") (pin "2") (pinfunction "2_2") (pintype "passive"))
      (node (ref "C654") (pin "1") (pinfunction "1_1") (pintype "passive"))
      (node (ref "C655") (pin "1") (pinfunction "1_1") (pintype "passive"))
      (node (ref "C656") (pin "2") (pinfunction "2_2") (pintype "passive"))
      (node (ref "C657") (pin "1") (pinfunction "1_1") (pintype "passive"))
      (node (ref "C658") (pin "1") (pinfunction "1_1") (pintype "passive"))
      (node (ref "C659") (pin "2") (pinfunction "2_2") (pintype "passive"))
      (node (ref "C66") (pin "2") (pinfunction "2_2") (pintype "passive"))
      (node (ref "C660") (pin "1") (pinfunction "1_1") (pintype "passive"))
      (node (ref "C661") (pin "1") (pinfunction "1_1") (pintype "passive"))
      (node (ref "C662") (pin "2") (pinfunction "2_2") (pintype "passive"))
      (node (ref "C663") (pin "1") (pinfunction "1_1") (pintype "passive"))
      (node (ref "C664") (pin "1") (pinfunction "1_1") (pintype "passive"))
      (node (ref "C665") (pin "2") (pinfunction "2_2") (pintype "passive"))
      (node (ref "C666") (pin "1") (pinfunction "1_1") (pintype "passive"))
      (node (ref "C667") (pin "1") (pinfunction "1_1") (pintype "passive"))
      (node (ref "C668") (pin "2") (pinfunction "2_2") (pintype "passive"))
      (node (ref "C669") (pin "1") (pinfunction "1_1") (pintype "passive"))
      (node (ref "C67") (pin "2") (pinfunction "2_2") (pintype "passive"))
      (node (ref "C670") (pin "1") (pinfunction "1_1") (pintype "passive"))
      (node (ref "C671") (pin "2") (pinfunction "2_2") (pintype "passive"))
      (node (ref "C672") (pin "1") (pinfunction "1_1") (pintype "passive"))
      (node (ref "C673") (pin "1") (pinfunction "1_1") (pintype "passive"))
      (node (ref "C674") (pin "2") (pinfunction "2_2") (pintype "passive"))
      (node (ref "C675") (pin "1") (pinfunction "1_1") (pintype "passive"))
      (node (ref "C676") (pin "1") (pinfunction "1_1") (pintype "passive"))
      (node (ref "C677") (pin "2") (pinfunction "2_2") (pintype "passive"))
      (node (ref "C678") (pin "1") (pinfunction "1_1") (pintype "passive"))
      (node (ref "C679") (pin "1") (pinfunction "1_1") (pintype "passive"))
      (node (ref "C68") (pin "2") (pinfunction "2_2") (pintype "passive"))
      (node (ref "C680") (pin "2") (pinfunction "2_2") (pintype "passive"))
      (node (ref "C681") (pin "1") (pinfunction "1_1") (pintype "passive"))
      (node (ref "C71") (pin "2") (pinfunction "2_2") (pintype "passive"))
      (node (ref "C72") (pin "2") (pinfunction "2_2") (pintype "passive"))
      (node (ref "C73") (pin "2") (pinfunction "2_2") (pintype "passive"))
      (node (ref "C742") (pin "1") (pinfunction "1_1") (pintype "passive"))
      (node (ref "C743") (pin "2") (pinfunction "2_2") (pintype "passive"))
      (node (ref "C744") (pin "1") (pinfunction "1_1") (pintype "passive"))
      (node (ref "C745") (pin "1") (pinfunction "1_1") (pintype "passive"))
      (node (ref "C746") (pin "2") (pinfunction "2_2") (pintype "passive"))
      (node (ref "C747") (pin "1") (pinfunction "1_1") (pintype "passive"))
      (node (ref "C748") (pin "1") (pinfunction "1_1") (pintype "passive"))
      (node (ref "C749") (pin "2") (pinfunction "2_2") (pintype "passive"))
      (node (ref "C750") (pin "1") (pinfunction "1_1") (pintype "passive"))
      (node (ref "C751") (pin "1") (pinfunction "1_1") (pintype "passive"))
      (node (ref "C752") (pin "2") (pinfunction "2_2") (pintype "passive"))
      (node (ref "C753") (pin "1") (pinfunction "1_1") (pintype "passive"))
      (node (ref "C754") (pin "1") (pinfunction "1_1") (pintype "passive"))
      (node (ref "C755") (pin "2") (pinfunction "2_2") (pintype "passive"))
      (node (ref "C756") (pin "1") (pinfunction "1_1") (pintype "passive"))
      (node (ref "C757") (pin "1") (pinfunction "1_1") (pintype "passive"))
      (node (ref "C758") (pin "2") (pinfunction "2_2") (pintype "passive"))
      (node (ref "C759") (pin "1") (pinfunction "1_1") (pintype "passive"))
      (node (ref "C760") (pin "1") (pinfunction "1_1") (pintype "passive"))
      (node (ref "C761") (pin "2") (pinfunction "2_2") (pintype "passive"))
      (node (ref "C762") (pin "1") (pinfunction "1_1") (pintype "passive"))
      (node (ref "C763") (pin "1") (pinfunction "1_1") (pintype "passive"))
      (node (ref "C764") (pin "2") (pinfunction "2_2") (pintype "passive"))
      (node (ref "C765") (pin "1") (pinfunction "1_1") (pintype "passive"))
      (node (ref "C766") (pin "1") (pinfunction "1_1") (pintype "passive"))
      (node (ref "C767") (pin "2") (pinfunction "2_2") (pintype "passive"))
      (node (ref "C768") (pin "1") (pinfunction "1_1") (pintype "passive"))
      (node (ref "C769") (pin "1") (pinfunction "1_1") (pintype "passive"))
      (node (ref "C770") (pin "2") (pinfunction "2_2") (pintype "passive"))
      (node (ref "C771") (pin "1") (pinfunction "1_1") (pintype "passive"))
      (node (ref "C832") (pin "1") (pinfunction "1_1") (pintype "passive"))
      (node (ref "C833") (pin "2") (pinfunction "2_2") (pintype "passive"))
      (node (ref "C834") (pin "1") (pinfunction "1_1") (pintype "passive"))
      (node (ref "C835") (pin "1") (pinfunction "1_1") (pintype "passive"))
      (node (ref "C836") (pin "2") (pinfunction "2_2") (pintype "passive"))
      (node (ref "C837") (pin "1") (pinfunction "1_1") (pintype "passive"))
      (node (ref "C838") (pin "1") (pinfunction "1_1") (pintype "passive"))
      (node (ref "C839") (pin "2") (pinfunction "2_2") (pintype "passive"))
      (node (ref "C840") (pin "1") (pinfunction "1_1") (pintype "passive"))
      (node (ref "C841") (pin "1") (pinfunction "1_1") (pintype "passive"))
      (node (ref "C842") (pin "2") (pinfunction "2_2") (pintype "passive"))
      (node (ref "C843") (pin "1") (pinfunction "1_1") (pintype "passive"))
      (node (ref "C844") (pin "1") (pinfunction "1_1") (pintype "passive"))
      (node (ref "C845") (pin "2") (pinfunction "2_2") (pintype "passive"))
      (node (ref "C846") (pin "1") (pinfunction "1_1") (pintype "passive"))
      (node (ref "C847") (pin "1") (pinfunction "1_1") (pintype "passive"))
      (node (ref "C848") (pin "2") (pinfunction "2_2") (pintype "passive"))
      (node (ref "C849") (pin "1") (pinfunction "1_1") (pintype "passive"))
      (node (ref "C850") (pin "1") (pinfunction "1_1") (pintype "passive"))
      (node (ref "C851") (pin "2") (pinfunction "2_2") (pintype "passive"))
      (node (ref "C852") (pin "1") (pinfunction "1_1") (pintype "passive"))
      (node (ref "C853") (pin "1") (pinfunction "1_1") (pintype "passive"))
      (node (ref "C854") (pin "2") (pinfunction "2_2") (pintype "passive"))
      (node (ref "C855") (pin "1") (pinfunction "1_1") (pintype "passive"))
      (node (ref "C856") (pin "1") (pinfunction "1_1") (pintype "passive"))
      (node (ref "C857") (pin "2") (pinfunction "2_2") (pintype "passive"))
      (node (ref "C858") (pin "1") (pinfunction "1_1") (pintype "passive"))
      (node (ref "C859") (pin "1") (pinfunction "1_1") (pintype "passive"))
      (node (ref "C860") (pin "2") (pinfunction "2_2") (pintype "passive"))
      (node (ref "C861") (pin "1") (pinfunction "1_1") (pintype "passive"))
      (node (ref "C922") (pin "1") (pinfunction "1_1") (pintype "passive"))
      (node (ref "C923") (pin "2") (pinfunction "2_2") (pintype "passive"))
      (node (ref "C924") (pin "1") (pinfunction "1_1") (pintype "passive"))
      (node (ref "C925") (pin "1") (pinfunction "1_1") (pintype "passive"))
      (node (ref "C926") (pin "2") (pinfunction "2_2") (pintype "passive"))
      (node (ref "C927") (pin "1") (pinfunction "1_1") (pintype "passive"))
      (node (ref "C928") (pin "1") (pinfunction "1_1") (pintype "passive"))
      (node (ref "C929") (pin "2") (pinfunction "2_2") (pintype "passive"))
      (node (ref "C930") (pin "1") (pinfunction "1_1") (pintype "passive"))
      (node (ref "C931") (pin "1") (pinfunction "1_1") (pintype "passive"))
      (node (ref "C932") (pin "2") (pinfunction "2_2") (pintype "passive"))
      (node (ref "C933") (pin "1") (pinfunction "1_1") (pintype "passive"))
      (node (ref "C934") (pin "1") (pinfunction "1_1") (pintype "passive"))
      (node (ref "C935") (pin "2") (pinfunction "2_2") (pintype "passive"))
      (node (ref "C936") (pin "1") (pinfunction "1_1") (pintype "passive"))
      (node (ref "C937") (pin "1") (pinfunction "1_1") (pintype "passive"))
      (node (ref "C938") (pin "2") (pinfunction "2_2") (pintype "passive"))
      (node (ref "C939") (pin "1") (pinfunction "1_1") (pintype "passive"))
      (node (ref "C940") (pin "1") (pinfunction "1_1") (pintype "passive"))
      (node (ref "C941") (pin "2") (pinfunction "2_2") (pintype "passive"))
      (node (ref "C942") (pin "1") (pinfunction "1_1") (pintype "passive"))
      (node (ref "C943") (pin "1") (pinfunction "1_1") (pintype "passive"))
      (node (ref "C944") (pin "2") (pinfunction "2_2") (pintype "passive"))
      (node (ref "C945") (pin "1") (pinfunction "1_1") (pintype "passive"))
      (node (ref "C946") (pin "1") (pinfunction "1_1") (pintype "passive"))
      (node (ref "C947") (pin "2") (pinfunction "2_2") (pintype "passive"))
      (node (ref "C948") (pin "1") (pinfunction "1_1") (pintype "passive"))
      (node (ref "C949") (pin "1") (pinfunction "1_1") (pintype "passive"))
      (node (ref "C950") (pin "2") (pinfunction "2_2") (pintype "passive"))
      (node (ref "C951") (pin "1") (pinfunction "1_1") (pintype "passive"))
      (node (ref "C952") (pin "1") (pinfunction "1_1") (pintype "passive"))
      (node (ref "C953") (pin "2") (pinfunction "2_2") (pintype "passive"))
      (node (ref "C954") (pin "1") (pinfunction "1_1") (pintype "passive"))
      (node (ref "C955") (pin "1") (pinfunction "1_1") (pintype "passive"))
      (node (ref "C956") (pin "2") (pinfunction "2_2") (pintype "passive"))
      (node (ref "C957") (pin "1") (pinfunction "1_1") (pintype "passive"))
      (node (ref "C958") (pin "1") (pinfunction "1_1") (pintype "passive"))
      (node (ref "C959") (pin "2") (pinfunction "2_2") (pintype "passive"))
      (node (ref "C960") (pin "1") (pinfunction "1_1") (pintype "passive"))
      (node (ref "C961") (pin "1") (pinfunction "1_1") (pintype "passive"))
      (node (ref "C962") (pin "2") (pinfunction "2_2") (pintype "passive"))
      (node (ref "C963") (pin "1") (pinfunction "1_1") (pintype "passive"))
      (node (ref "C964") (pin "1") (pinfunction "1_1") (pintype "passive"))
      (node (ref "C965") (pin "2") (pinfunction "2_2") (pintype "passive"))
      (node (ref "C966") (pin "1") (pinfunction "1_1") (pintype "passive"))
      (node (ref "C967") (pin "1") (pinfunction "1_1") (pintype "passive"))
      (node (ref "C968") (pin "2") (pinfunction "2_2") (pintype "passive"))
      (node (ref "C969") (pin "1") (pinfunction "1_1") (pintype "passive"))
      (node (ref "C970") (pin "1") (pinfunction "1_1") (pintype "passive"))
      (node (ref "C971") (pin "2") (pinfunction "2_2") (pintype "passive"))
      (node (ref "C972") (pin "1") (pinfunction "1_1") (pintype "passive"))
      (node (ref "C973") (pin "1") (pinfunction "1_1") (pintype "passive"))
      (node (ref "C974") (pin "2") (pinfunction "2_2") (pintype "passive"))
      (node (ref "C975") (pin "1") (pinfunction "1_1") (pintype "passive"))
      (node (ref "C976") (pin "1") (pinfunction "1_1") (pintype "passive"))
      (node (ref "C977") (pin "2") (pinfunction "2_2") (pintype "passive"))
      (node (ref "C978") (pin "1") (pinfunction "1_1") (pintype "passive"))
      (node (ref "C979") (pin "1") (pinfunction "1_1") (pintype "passive"))
      (node (ref "C98") (pin "2") (pinfunction "2_2") (pintype "passive"))
      (node (ref "C980") (pin "2") (pinfunction "2_2") (pintype "passive"))
      (node (ref "C981") (pin "1") (pinfunction "1_1") (pintype "passive"))
      (node (ref "C982") (pin "1") (pinfunction "1_1") (pintype "passive"))
      (node (ref "C983") (pin "2") (pinfunction "2_2") (pintype "passive"))
      (node (ref "C984") (pin "1") (pinfunction "1_1") (pintype "passive"))
      (node (ref "C985") (pin "1") (pinfunction "1_1") (pintype "passive"))
      (node (ref "C986") (pin "2") (pinfunction "2_2") (pintype "passive"))
      (node (ref "C987") (pin "1") (pinfunction "1_1") (pintype "passive"))
      (node (ref "C988") (pin "1") (pinfunction "1_1") (pintype "passive"))
      (node (ref "C989") (pin "2") (pinfunction "2_2") (pintype "passive"))
      (node (ref "C99") (pin "2") (pinfunction "2_2") (pintype "passive"))
      (node (ref "C990") (pin "1") (pinfunction "1_1") (pintype "passive"))
      (node (ref "C991") (pin "1") (pinfunction "1_1") (pintype "passive"))
      (node (ref "C992") (pin "2") (pinfunction "2_2") (pintype "passive"))
      (node (ref "C993") (pin "1") (pinfunction "1_1") (pintype "passive"))
      (node (ref "C994") (pin "1") (pinfunction "1_1") (pintype "passive"))
      (node (ref "C995") (pin "2") (pinfunction "2_2") (pintype "passive"))
      (node (ref "C996") (pin "1") (pinfunction "1_1") (pintype "passive"))
      (node (ref "C997") (pin "1") (pinfunction "1_1") (pintype "passive"))
      (node (ref "C998") (pin "2") (pinfunction "2_2") (pintype "passive"))
      (node (ref "C999") (pin "1") (pinfunction "1_1") (pintype "passive"))
      (node (ref "L1") (pin "2") (pinfunction "2_2") (pintype "passive"))
      (node (ref "L10") (pin "2") (pinfunction "2_2") (pintype "passive"))
      (node (ref "L13") (pin "2") (pinfunction "2_2") (pintype "passive"))
      (node (ref "L14") (pin "2") (pinfunction "2_2") (pintype "passive"))
      (node (ref "L2") (pin "2") (pinfunction "2_2") (pintype "passive"))
      (node (ref "L5") (pin "2") (pinfunction "2_2") (pintype "passive"))
      (node (ref "L6") (pin "2") (pinfunction "2_2") (pintype "passive"))
      (node (ref "L9") (pin "2") (pinfunction "2_2") (pintype "passive"))
    )
    (net (code "2") (name "/3.3V") (class "Default")
      (node (ref "C120") (pin "1") (pinfunction "1_1") (pintype "passive"))
      (node (ref "C121") (pin "1") (pinfunction "1_1") (pintype "passive"))
      (node (ref "C24") (pin "1") (pinfunction "1_1") (pintype "passive"))
      (node (ref "C25") (pin "1") (pinfunction "1_1") (pintype "passive"))
      (node (ref "C56") (pin "1") (pinfunction "1_1") (pintype "passive"))
      (node (ref "C57") (pin "1") (pinfunction "1_1") (pintype "passive"))
      (node (ref "C88") (pin "1") (pinfunction "1_1") (pintype "passive"))
      (node (ref "C89") (pin "1") (pinfunction "1_1") (pintype "passive"))
      (node (ref "U11") (pin "6") (pinfunction "VLOGIC_6") (pintype "passive"))
      (node (ref "U12") (pin "6") (pinfunction "VLOGIC_6") (pintype "passive"))
      (node (ref "U15") (pin "6") (pinfunction "VLOGIC_6") (pintype "passive"))
      (node (ref "U16") (pin "6") (pinfunction "VLOGIC_6") (pintype "passive"))
      (node (ref "U19") (pin "6") (pinfunction "VLOGIC_6") (pintype "passive"))
      (node (ref "U20") (pin "6") (pinfunction "VLOGIC_6") (pintype "passive"))
      (node (ref "U23") (pin "6") (pinfunction "VLOGIC_6") (pintype "passive"))
      (node (ref "U24") (pin "6") (pinfunction "VLOGIC_6") (pintype "passive"))
    )
    (net (code "3") (name "/5.0V") (class "Default")
      (node (ref "C116") (pin "2") (pinfunction "2_2") (pintype "passive"))
      (node (ref "C117") (pin "2") (pinfunction "2_2") (pintype "passive"))
      (node (ref "C20") (pin "2") (pinfunction "2_2") (pintype "passive"))
      (node (ref "C21") (pin "2") (pinfunction "2_2") (pintype "passive"))
      (node (ref "C52") (pin "2") (pinfunction "2_2") (pintype "passive"))
      (node (ref "C53") (pin "2") (pinfunction "2_2") (pintype "passive"))
      (node (ref "C84") (pin "2") (pinfunction "2_2") (pintype "passive"))
      (node (ref "C85") (pin "2") (pinfunction "2_2") (pintype "passive"))
      (node (ref "D10") (pin "2") (pinfunction "A_2") (pintype "passive"))
      (node (ref "D11") (pin "2") (pinfunction "A_2") (pintype "passive"))
      (node (ref "D14") (pin "2") (pinfunction "A_2") (pintype "passive"))
      (node (ref "D15") (pin "2") (pinfunction "A_2") (pintype "passive"))
      (node (ref "D18") (pin "2") (pinfunction "A_2") (pintype "passive"))
      (node (ref "D19") (pin "2") (pinfunction "A_2") (pintype "passive"))
      (node (ref "D22") (pin "2") (pinfunction "A_2") (pintype "passive"))
      (node (ref "D23") (pin "2") (pinfunction "A_2") (pintype "passive"))
      (node (ref "U11") (pin "7") (pinfunction "VCC_7") (pintype "passive"))
      (node (ref "U12") (pin "7") (pinfunction "VCC_7") (pintype "passive"))
      (node (ref "U15") (pin "7") (pinfunction "VCC_7") (pintype "passive"))
      (node (ref "U16") (pin "7") (pinfunction "VCC_7") (pintype "passive"))
      (node (ref "U19") (pin "7") (pinfunction "VCC_7") (pintype "passive"))
      (node (ref "U20") (pin "7") (pinfunction "VCC_7") (pintype "passive"))
      (node (ref "U23") (pin "7") (pinfunction "VCC_7") (pintype "passive"))
      (node (ref "U24") (pin "7") (pinfunction "VCC_7") (pintype "passive"))
    )
    (net (code "4") (name "/12V") (class "Default")
      (node (ref "C101") (pin "2") (pinfunction "2_2") (pintype "passive"))
      (node (ref "C102") (pin "2") (pinfunction "2_2") (pintype "passive"))
      (node (ref "C128") (pin "2") (pinfunction "2_2") (pintype "passive"))
      (node (ref "C129") (pin "2") (pinfunction "2_2") (pintype "passive"))
      (node (ref "C133") (pin "2") (pinfunction "2_2") (pintype "passive"))
      (node (ref "C134") (pin "2") (pinfunction "2_2") (pintype "passive"))
      (node (ref "C32") (pin "2") (pinfunction "2_2") (pintype "passive"))
      (node (ref "C33") (pin "2") (pinfunction "2_2") (pintype "passive"))
      (node (ref "C348") (pin "2") (pinfunction "2_2") (pintype "passive"))
      (node (ref "C349") (pin "2") (pinfunction "2_2") (pintype "passive"))
      (node (ref "C37") (pin "2") (pinfunction "2_2") (pintype "passive"))
      (node (ref "C377") (pin "1") (pinfunction "1_1") (pintype "passive"))
      (node (ref "C378") (pin "1") (pinfunction "1_1") (pintype "passive"))
      (node (ref "C379") (pin "1") (pinfunction "1_1") (pintype "passive"))
      (node (ref "C38") (pin "2") (pinfunction "2_2") (pintype "passive"))
      (node (ref "C380") (pin "1") (pinfunction "1_1") (pintype "passive"))
      (node (ref "C381") (pin "1") (pinfunction "1_1") (pintype "passive"))
      (node (ref "C382") (pin "1") (pinfunction "1_1") (pintype "passive"))
      (node (ref "C383") (pin "1") (pinfunction "1_1") (pintype "passive"))
      (node (ref "C384") (pin "1") (pinfunction "1_1") (pintype "passive"))
      (node (ref "C385") (pin "1") (pinfunction "1_1") (pintype "passive"))
      (node (ref "C386") (pin "1") (pinfunction "1_1") (pintype "passive"))
      (node (ref "C387") (pin "1") (pinfunction "1_1") (pintype "passive"))
      (node (ref "C388") (pin "1") (pinfunction "1_1") (pintype "passive"))
      (node (ref "C389") (pin "1") (pinfunction "1_1") (pintype "passive"))
      (node (ref "C390") (pin "1") (pinfunction "1_1") (pintype "passive"))
      (node (ref "C391") (pin "1") (pinfunction "1_1") (pintype "passive"))
      (node (ref "C392") (pin "1") (pinfunction "1_1") (pintype "passive"))
      (node (ref "C402") (pin "2") (pinfunction "2_2") (pintype "passive"))
      (node (ref "C403") (pin "2") (pinfunction "2_2") (pintype "passive"))
      (node (ref "C404") (pin "2") (pinfunction "2_2") (pintype "passive"))
      (node (ref "C405") (pin "2") (pinfunction "2_2") (pintype "passive"))
      (node (ref "C406") (pin "2") (pinfunction "2_2") (pintype "passive"))
      (node (ref "C407") (pin "2") (pinfunction "2_2") (pintype "passive"))
      (node (ref "C420") (pin "2") (pinfunction "2_2") (pintype "passive"))
      (node (ref "C421") (pin "2") (pinfunction "2_2") (pintype "passive"))
      (node (ref "C422") (pin "2") (pinfunction "2_2") (pintype "passive"))
      (node (ref "C423") (pin "2") (pinfunction "2_2") (pintype "passive"))
      (node (ref "C424") (pin "2") (pinfunction "2_2") (pintype "passive"))
      (node (ref "C425") (pin "2") (pinfunction "2_2") (pintype "passive"))
      (node (ref "C426") (pin "2") (pinfunction "2_2") (pintype "passive"))
      (node (ref "C427") (pin "2") (pinfunction "2_2") (pintype "passive"))
      (node (ref "C428") (pin "1") (pinfunction "1_1") (pintype "passive"))
      (node (ref "C429") (pin "1") (pinfunction "1_1") (pintype "passive"))
      (node (ref "C430") (pin "1") (pinfunction "1_1") (pintype "passive"))
      (node (ref "C431") (pin "1") (pinfunction "1_1") (pintype "passive"))
      (node (ref "C432") (pin "1") (pinfunction "1_1") (pintype "passive"))
      (node (ref "C433") (pin "1") (pinfunction "1_1") (pintype "passive"))
      (node (ref "C434") (pin "1") (pinfunction "1_1") (pintype "passive"))
      (node (ref "C435") (pin "1") (pinfunction "1_1") (pintype "passive"))
      (node (ref "C436") (pin "1") (pinfunction "1_1") (pintype "passive"))
      (node (ref "C437") (pin "1") (pinfunction "1_1") (pintype "passive"))
      (node (ref "C438") (pin "1") (pinfunction "1_1") (pintype "passive"))
      (node (ref "C439") (pin "1") (pinfunction "1_1") (pintype "passive"))
      (node (ref "C440") (pin "1") (pinfunction "1_1") (pintype "passive"))
      (node (ref "C441") (pin "1") (pinfunction "1_1") (pintype "passive"))
      (node (ref "C442") (pin "1") (pinfunction "1_1") (pintype "passive"))
      (node (ref "C443") (pin "1") (pinfunction "1_1") (pintype "passive"))
      (node (ref "C593") (pin "2") (pinfunction "2_2") (pintype "passive"))
      (node (ref "C596") (pin "2") (pinfunction "2_2") (pintype "passive"))
      (node (ref "C598") (pin "1") (pinfunction "1_1") (pintype "passive"))
      (node (ref "C599") (pin "2") (pinfunction "2_2") (pintype "passive"))
      (node (ref "C600") (pin "1") (pinfunction "1_1") (pintype "passive"))
      (node (ref "C602") (pin "2") (pinfunction "2_2") (pintype "passive"))
      (node (ref "C603") (pin "1") (pinfunction "1_1") (pintype "passive"))
      (node (ref "C605") (pin "2") (pinfunction "2_2") (pintype "passive"))
      (node (ref "C606") (pin "1") (pinfunction "1_1") (pintype "passive"))
      (node (ref "C64") (pin "2") (pinfunction "2_2") (pintype "passive"))
      (node (ref "C640") (pin "1") (pinfunction "1_1") (pintype "passive"))
      (node (ref "C642") (pin "1") (pinfunction "1_1") (pintype "passive"))
      (node (ref "C643") (pin "1") (pinfunction "1_1") (pintype "passive"))
      (node (ref "C645") (pin "1") (pinfunction "1_1") (pintype "passive"))
      (node (ref "C646") (pin "1") (pinfunction "1_1") (pintype "passive"))
      (node (ref "C65") (pin "2") (pinfunction "2_2") (pintype "passive"))
      (node (ref "C686") (pin "2") (pinfunction "2_2") (pintype "passive"))
      (node (ref "C688") (pin "1") (pinfunction "1_1") (pintype "passive"))
      (node (ref "C689") (pin "2") (pinfunction "2_2") (pintype "passive"))
      (node (ref "C69") (pin "2") (pinfunction "2_2") (pintype "passive"))
      (node (ref "C692") (pin "2") (pinfunction "2_2") (pintype "passive"))
      (node (ref "C695") (pin "2") (pinfunction "2_2") (pintype "passive"))
      (node (ref "C70") (pin "2") (pinfunction "2_2") (pintype "passive"))
      (node (ref "C711") (pin "1") (pinfunction "1_1") (pintype "passive"))
      (node (ref "C712") (pin "1") (pinfunction "1_1") (pintype "passive"))
      (node (ref "C714") (pin "1") (pinfunction "1_1") (pintype "passive"))
      (node (ref "C715") (pin "1") (pinfunction "1_1") (pintype "passive"))
      (node (ref "C717") (pin "1") (pinfunction "1_1") (pintype "passive"))
      (node (ref "C776") (pin "2") (pinfunction "2_2") (pintype "passive"))
      (node (ref "C779") (pin "2") (pinfunction "2_2") (pintype "passive"))
      (node (ref "C782") (pin "2") (pinfunction "2_2") (pintype "passive"))
      (node (ref "C785") (pin "2") (pinfunction "2_2") (pintype "passive"))
      (node (ref "C807") (pin "1") (pinfunction "1_1") (pintype "passive"))
      (node (ref "C808") (pin "1") (pinfunction "1_1") (pintype "passive"))
      (node (ref "C810") (pin "1") (pinfunction "1_1") (pintype "passive"))
      (node (ref "C811") (pin "1") (pinfunction "1_1") (pintype "passive"))
      (node (ref "C813") (pin "1") (pinfunction "1_1") (pintype "passive"))
      (node (ref "C814") (pin "1") (pinfunction "1_1") (pintype "passive"))
      (node (ref "C866") (pin "2") (pinfunction "2_2") (pintype "passive"))
      (node (ref "C868") (pin "1") (pinfunction "1_1") (pintype "passive"))
      (node (ref "C869") (pin "2") (pinfunction "2_2") (pintype "passive"))
      (node (ref "C872") (pin "2") (pinfunction "2_2") (pintype "passive"))
      (node (ref "C876") (pin "1") (pinfunction "1_1") (pintype "passive"))
      (node (ref "C877") (pin "1") (pinfunction "1_1") (pintype "passive"))
      (node (ref "C879") (pin "1") (pinfunction "1_1") (pintype "passive"))
      (node (ref "C880") (pin "1") (pinfunction "1_1") (pintype "passive"))
      (node (ref "C882") (pin "1") (pinfunction "1_1") (pintype "passive"))
      (node (ref "C913") (pin "1") (pinfunction "1_1") (pintype "passive"))
      (node (ref "C915") (pin "1") (pinfunction "1_1") (pintype "passive"))
      (node (ref "C916") (pin "1") (pinfunction "1_1") (pintype "passive"))
      (node (ref "C918") (pin "1") (pinfunction "1_1") (pintype "passive"))
      (node (ref "C919") (pin "1") (pinfunction "1_1") (pintype "passive"))
      (node (ref "C96") (pin "2") (pinfunction "2_2") (pintype "passive"))
      (node (ref "C97") (pin "2") (pinfunction "2_2") (pintype "passive"))
      (node (ref "Q1") (pin "5") (pinfunction "D_5") (pintype "passive"))
      (node (ref "Q1") (pin "6") (pinfunction "D_6") (pintype "passive"))
      (node (ref "Q1") (pin "7") (pinfunction "D_7") (pintype "passive"))
      (node (ref "Q1") (pin "8") (pinfunction "D_8") (pintype "passive"))
      (node (ref "Q13") (pin "5") (pinfunction "D_5") (pintype "passive"))
      (node (ref "Q13") (pin "6") (pinfunction "D_6") (pintype "passive"))
      (node (ref "Q13") (pin "7") (pinfunction "D_7") (pintype "passive"))
      (node (ref "Q13") (pin "8") (pinfunction "D_8") (pintype "passive"))
      (node (ref "Q14") (pin "5") (pinfunction "D_5") (pintype "passive"))
      (node (ref "Q14") (pin "6") (pinfunction "D_6") (pintype "passive"))
      (node (ref "Q14") (pin "7") (pinfunction "D_7") (pintype "passive"))
      (node (ref "Q14") (pin "8") (pinfunction "D_8") (pintype "passive"))
      (node (ref "Q2") (pin "5") (pinfunction "D_5") (pintype "passive"))
      (node (ref "Q2") (pin "6") (pinfunction "D_6") (pintype "passive"))
      (node (ref "Q2") (pin "7") (pinfunction "D_7") (pintype "passive"))
      (node (ref "Q2") (pin "8") (pinfunction "D_8") (pintype "passive"))
      (node (ref "Q25") (pin "5") (pinfunction "D_5") (pintype "passive"))
      (node (ref "Q25") (pin "6") (pinfunction "D_6") (pintype "passive"))
      (node (ref "Q25") (pin "7") (pinfunction "D_7") (pintype "passive"))
      (node (ref "Q25") (pin "8") (pinfunction "D_8") (pintype "passive"))
      (node (ref "Q26") (pin "5") (pinfunction "D_5") (pintype "passive"))
      (node (ref "Q26") (pin "6") (pinfunction "D_6") (pintype "passive"))
      (node (ref "Q26") (pin "7") (pinfunction "D_7") (pintype "passive"))
      (node (ref "Q26") (pin "8") (pinfunction "D_8") (pintype "passive"))
      (node (ref "Q37") (pin "5") (pinfunction "D_5") (pintype "passive"))
      (node (ref "Q37") (pin "6") (pinfunction "D_6") (pintype "passive"))
      (node (ref "Q37") (pin "7") (pinfunction "D_7") (pintype "passive"))
      (node (ref "Q37") (pin "8") (pinfunction "D_8") (pintype "passive"))
      (node (ref "Q38") (pin "5") (pinfunction "D_5") (pintype "passive"))
      (node (ref "Q38") (pin "6") (pinfunction "D_6") (pintype "passive"))
      (node (ref "Q38") (pin "7") (pinfunction "D_7") (pintype "passive"))
      (node (ref "Q38") (pin "8") (pinfunction "D_8") (pintype "passive"))
    )
    (net (code "5") (name "/BOOT1") (class "Default")
      (node (ref "C28") (pin "1") (pinfunction "1_1") (pintype "passive"))
      (node (ref "D10") (pin "1") (pinfunction "C_1") (pintype "passive"))
      (node (ref "U11") (pin "8") (pinfunction "BOOST_8") (pintype "passive"))
    )
    (net (code "6") (name "/BOOT2") (class "Default")
      (node (ref "C60") (pin "1") (pinfunction "1_1") (pintype "passive"))
      (node (ref "D14") (pin "1") (pinfunction "C_1") (pintype "passive"))
      (node (ref "U15") (pin "8") (pinfunction "BOOST_8") (pintype "passive"))
    )
    (net (code "7") (name "/BOOT3") (class "Default")
      (node (ref "C92") (pin "1") (pinfunction "1_1") (pintype "passive"))
      (node (ref "D18") (pin "1") (pinfunction "C_1") (pintype "passive"))
      (node (ref "U19") (pin "8") (pinfunction "BOOST_8") (pintype "passive"))
    )
    (net (code "8") (name "/BOOT4") (class "Default")
      (node (ref "C124") (pin "1") (pinfunction "1_1") (pintype "passive"))
      (node (ref "D22") (pin "1") (pinfunction "C_1") (pintype "passive"))
      (node (ref "U23") (pin "8") (pinfunction "BOOST_8") (pintype "passive"))
    )
    (net (code "9") (name "/BOOT5") (class "Default")
      (node (ref "C29") (pin "1") (pinfunction "1_1") (pintype "passive"))
      (node (ref "D11") (pin "1") (pinfunction "C_1") (pintype "passive"))
      (node (ref "U12") (pin "8") (pinfunction "BOOST_8") (pintype "passive"))
    )
    (net (code "10") (name "/BOOT6") (class "Default")
      (node (ref "C61") (pin "1") (pinfunction "1_1") (pintype "passive"))
      (node (ref "D15") (pin "1") (pinfunction "C_1") (pintype "passive"))
      (node (ref "U16") (pin "8") (pinfunction "BOOST_8") (pintype "passive"))
    )
    (net (code "11") (name "/BOOT7") (class "Default")
      (node (ref "C93") (pin "1") (pinfunction "1_1") (pintype "passive"))
      (node (ref "D19") (pin "1") (pinfunction "C_1") (pintype "passive"))
      (node (ref "U20") (pin "8") (pinfunction "BOOST_8") (pintype "passive"))
    )
    (net (code "12") (name "/BOOT8") (class "Default")
      (node (ref "C125") (pin "1") (pinfunction "1_1") (pintype "passive"))
      (node (ref "D23") (pin "1") (pinfunction "C_1") (pintype "passive"))
      (node (ref "U24") (pin "8") (pinfunction "BOOST_8") (pintype "passive"))
    )
    (net (code "13") (name "/HO1") (class "Default")
      (node (ref "Q1") (pin "4") (pinfunction "G_4") (pintype "passive"))
      (node (ref "U11") (pin "1") (pinfunction "TG_1") (pintype "passive"))
    )
    (net (code "14") (name "/HO2") (class "Default")
      (node (ref "Q13") (pin "4") (pinfunction "G_4") (pintype "passive"))
      (node (ref "U15") (pin "1") (pinfunction "TG_1") (pintype "passive"))
    )
    (net (code "15") (name "/HO3") (class "Default")
      (node (ref "Q25") (pin "4") (pinfunction "G_4") (pintype "passive"))
      (node (ref "U19") (pin "1") (pinfunction "TG_1") (pintype "passive"))
    )
    (net (code "16") (name "/HO4") (class "Default")
      (node (ref "Q37") (pin "4") (pinfunction "G_4") (pintype "passive"))
      (node (ref "U23") (pin "1") (pinfunction "TG_1") (pintype "passive"))
    )
    (net (code "17") (name "/HO5") (class "Default")
      (node (ref "Q2") (pin "4") (pinfunction "G_4") (pintype "passive"))
      (node (ref "U12") (pin "1") (pinfunction "TG_1") (pintype "passive"))
    )
    (net (code "18") (name "/HO6") (class "Default")
      (node (ref "Q14") (pin "4") (pinfunction "G_4") (pintype "passive"))
      (node (ref "U16") (pin "1") (pinfunction "TG_1") (pintype "passive"))
    )
    (net (code "19") (name "/HO7") (class "Default")
      (node (ref "Q26") (pin "4") (pinfunction "G_4") (pintype "passive"))
      (node (ref "U20") (pin "1") (pinfunction "TG_1") (pintype "passive"))
    )
    (net (code "20") (name "/HO8") (class "Default")
      (node (ref "Q38") (pin "4") (pinfunction "G_4") (pintype "passive"))
      (node (ref "U24") (pin "1") (pinfunction "TG_1") (pintype "passive"))
    )
    (net (code "21") (name "/LO1") (class "Default")
      (node (ref "Q5") (pin "4") (pinfunction "G_4") (pintype "passive"))
      (node (ref "Q6") (pin "4") (pinfunction "G_4") (pintype "passive"))
      (node (ref "U11") (pin "3") (pinfunction "BG_3") (pintype "passive"))
    )
    (net (code "22") (name "/LO2") (class "Default")
      (node (ref "Q17") (pin "4") (pinfunction "G_4") (pintype "passive"))
      (node (ref "Q18") (pin "4") (pinfunction "G_4") (pintype "passive"))
      (node (ref "U15") (pin "3") (pinfunction "BG_3") (pintype "passive"))
    )
    (net (code "23") (name "/LO3") (class "Default")
      (node (ref "Q29") (pin "4") (pinfunction "G_4") (pintype "passive"))
      (node (ref "Q30") (pin "4") (pinfunction "G_4") (pintype "passive"))
      (node (ref "U19") (pin "3") (pinfunction "BG_3") (pintype "passive"))
    )
    (net (code "24") (name "/LO4") (class "Default")
      (node (ref "Q41") (pin "4") (pinfunction "G_4") (pintype "passive"))
      (node (ref "Q42") (pin "4") (pinfunction "G_4") (pintype "passive"))
      (node (ref "U23") (pin "3") (pinfunction "BG_3") (pintype "passive"))
    )
    (net (code "25") (name "/LO5") (class "Default")
      (node (ref "Q7") (pin "4") (pinfunction "G_4") (pintype "passive"))
      (node (ref "Q8") (pin "4") (pinfunction "G_4") (pintype "passive"))
      (node (ref "U12") (pin "3") (pinfunction "BG_3") (pintype "passive"))
    )
    (net (code "26") (name "/LO6") (class "Default")
      (node (ref "Q19") (pin "4") (pinfunction "G_4") (pintype "passive"))
      (node (ref "Q20") (pin "4") (pinfunction "G_4") (pintype "passive"))
      (node (ref "U16") (pin "3") (pinfunction "BG_3") (pintype "passive"))
    )
    (net (code "27") (name "/LO7") (class "Default")
      (node (ref "Q31") (pin "4") (pinfunction "G_4") (pintype "passive"))
      (node (ref "Q32") (pin "4") (pinfunction "G_4") (pintype "passive"))
      (node (ref "U20") (pin "3") (pinfunction "BG_3") (pintype "passive"))
    )
    (net (code "28") (name "/LO8") (class "Default")
      (node (ref "Q43") (pin "4") (pinfunction "G_4") (pintype "passive"))
      (node (ref "Q44") (pin "4") (pinfunction "G_4") (pintype "passive"))
      (node (ref "U24") (pin "3") (pinfunction "BG_3") (pintype "passive"))
    )
    (net (code "29") (name "/PWM1H") (class "Default")
      (node (ref "U12") (pin "5") (pinfunction "IN_5") (pintype "passive"))
    )
    (net (code "30") (name "/PWM1L") (class "Default")
      (node (ref "U11") (pin "5") (pinfunction "IN_5") (pintype "passive"))
    )
    (net (code "31") (name "/PWM2H") (class "Default")
      (node (ref "U16") (pin "5") (pinfunction "IN_5") (pintype "passive"))
    )
    (net (code "32") (name "/PWM2L") (class "Default")
      (node (ref "U15") (pin "5") (pinfunction "IN_5") (pintype "passive"))
    )
    (net (code "33") (name "/PWM3H") (class "Default")
      (node (ref "U20") (pin "5") (pinfunction "IN_5") (pintype "passive"))
    )
    (net (code "34") (name "/PWM3L") (class "Default")
      (node (ref "U19") (pin "5") (pinfunction "IN_5") (pintype "passive"))
    )
    (net (code "35") (name "/PWM4H") (class "Default")
      (node (ref "U24") (pin "5") (pinfunction "IN_5") (pintype "passive"))
    )
    (net (code "36") (name "/PWM4L") (class "Default")
      (node (ref "U23") (pin "5") (pinfunction "IN_5") (pintype "passive"))
    )
    (net (code "37") (name "/SWN1") (class "Default")
      (node (ref "C28") (pin "2") (pinfunction "2_2") (pintype "passive"))
      (node (ref "L1") (pin "1") (pinfunction "1_1") (pintype "passive"))
      (node (ref "Q1") (pin "1") (pinfunction "S_1") (pintype "passive"))
      (node (ref "Q1") (pin "2") (pinfunction "S_2") (pintype "passive"))
      (node (ref "Q1") (pin "3") (pinfunction "S_3") (pintype "passive"))
      (node (ref "Q5") (pin "5") (pinfunction "D_5") (pintype "passive"))
      (node (ref "Q5") (pin "6") (pinfunction "D_6") (pintype "passive"))
      (node (ref "Q5") (pin "7") (pinfunction "D_7") (pintype "passive"))
      (node (ref "Q5") (pin "8") (pinfunction "D_8") (pintype "passive"))
      (node (ref "Q6") (pin "5") (pinfunction "D_5") (pintype "passive"))
      (node (ref "Q6") (pin "6") (pinfunction "D_6") (pintype "passive"))
      (node (ref "Q6") (pin "7") (pinfunction "D_7") (pintype "passive"))
      (node (ref "Q6") (pin "8") (pinfunction "D_8") (pintype "passive"))
      (node (ref "U11") (pin "2") (pinfunction "TS_2") (pintype "passive"))
    )
    (net (code "38") (name "/SWN2") (class "Default")
      (node (ref "C60") (pin "2") (pinfunction "2_2") (pintype "passive"))
      (node (ref "L5") (pin "1") (pinfunction "1_1") (pintype "passive"))
      (node (ref "Q13") (pin "1") (pinfunction "S_1") (pintype "passive"))
      (node (ref "Q13") (pin "2") (pinfunction "S_2") (pintype "passive"))
      (node (ref "Q13") (pin "3") (pinfunction "S_3") (pintype "passive"))
      (node (ref "Q17") (pin "5") (pinfunction "D_5") (pintype "passive"))
      (node (ref "Q17") (pin "6") (pinfunction "D_6") (pintype "passive"))
      (node (ref "Q17") (pin "7") (pinfunction "D_7") (pintype "passive"))
      (node (ref "Q17") (pin "8") (pinfunction "D_8") (pintype "passive"))
      (node (ref "Q18") (pin "5") (pinfunction "D_5") (pintype "passive"))
      (node (ref "Q18") (pin "6") (pinfunction "D_6") (pintype "passive"))
      (node (ref "Q18") (pin "7") (pinfunction "D_7") (pintype "passive"))
      (node (ref "Q18") (pin "8") (pinfunction "D_8") (pintype "passive"))
      (node (ref "U15") (pin "2") (pinfunction "TS_2") (pintype "passive"))
    )
    (net (code "39") (name "/SWN3") (class "Default")
      (node (ref "C92") (pin "2") (pinfunction "2_2") (pintype "passive"))
      (node (ref "L9") (pin "1") (pinfunction "1_1") (pintype "passive"))
      (node (ref "Q25") (pin "1") (pinfunction "S_1") (pintype "passive"))
      (node (ref "Q25") (pin "2") (pinfunction "S_2") (pintype "passive"))
      (node (ref "Q25") (pin "3") (pinfunction "S_3") (pintype "passive"))
      (node (ref "Q29") (pin "5") (pinfunction "D_5") (pintype "passive"))
      (node (ref "Q29") (pin "6") (pinfunction "D_6") (pintype "passive"))
      (node (ref "Q29") (pin "7") (pinfunction "D_7") (pintype "passive"))
      (node (ref "Q29") (pin "8") (pinfunction "D_8") (pintype "passive"))
      (node (ref "Q30") (pin "5") (pinfunction "D_5") (pintype "passive"))
      (node (ref "Q30") (pin "6") (pinfunction "D_6") (pintype "passive"))
      (node (ref "Q30") (pin "7") (pinfunction "D_7") (pintype "passive"))
      (node (ref "Q30") (pin "8") (pinfunction "D_8") (pintype "passive"))
      (node (ref "U19") (pin "2") (pinfunction "TS_2") (pintype "passive"))
    )
    (net (code "40") (name "/SWN4") (class "Default")
      (node (ref "C124") (pin "2") (pinfunction "2_2") (pintype "passive"))
      (node (ref "L13") (pin "1") (pinfunction "1_1") (pintype "passive"))
      (node (ref "Q37") (pin "1") (pinfunction "S_1") (pintype "passive"))
      (node (ref "Q37") (pin "2") (pinfunction "S_2") (pintype "passive"))
      (node (ref "Q37") (pin "3") (pinfunction "S_3") (pintype "passive"))
      (node (ref "Q41") (pin "5") (pinfunction "D_5") (pintype "passive"))
      (node (ref "Q41") (pin "6") (pinfunction "D_6") (pintype "passive"))
      (node (ref "Q41") (pin "7") (pinfunction "D_7") (pintype "passive"))
      (node (ref "Q41") (pin "8") (pinfunction "D_8") (pintype "passive"))
      (node (ref "Q42") (pin "5") (pinfunction "D_5") (pintype "passive"))
      (node (ref "Q42") (pin "6") (pinfunction "D_6") (pintype "passive"))
      (node (ref "Q42") (pin "7") (pinfunction "D_7") (pintype "passive"))
      (node (ref "Q42") (pin "8") (pinfunction "D_8") (pintype "passive"))
      (node (ref "U23") (pin "2") (pinfunction "TS_2") (pintype "passive"))
    )
    (net (code "41") (name "/SWN5") (class "Default")
      (node (ref "C29") (pin "2") (pinfunction "2_2") (pintype "passive"))
      (node (ref "L2") (pin "1") (pinfunction "1_1") (pintype "passive"))
      (node (ref "Q2") (pin "1") (pinfunction "S_1") (pintype "passive"))
      (node (ref "Q2") (pin "2") (pinfunction "S_2") (pintype "passive"))
      (node (ref "Q2") (pin "3") (pinfunction "S_3") (pintype "passive"))
      (node (ref "Q7") (pin "5") (pinfunction "D_5") (pintype "passive"))
      (node (ref "Q7") (pin "6") (pinfunction "D_6") (pintype "passive"))
      (node (ref "Q7") (pin "7") (pinfunction "D_7") (pintype "passive"))
      (node (ref "Q7") (pin "8") (pinfunction "D_8") (pintype "passive"))
      (node (ref "Q8") (pin "5") (pinfunction "D_5") (pintype "passive"))
      (node (ref "Q8") (pin "6") (pinfunction "D_6") (pintype "passive"))
      (node (ref "Q8") (pin "7") (pinfunction "D_7") (pintype "passive"))
      (node (ref "Q8") (pin "8") (pinfunction "D_8") (pintype "passive"))
      (node (ref "U12") (pin "2") (pinfunction "TS_2") (pintype "passive"))
    )
    (net (code "42") (name "/SWN6") (class "Default")
      (node (ref "C61") (pin "2") (pinfunction "2_2") (pintype "passive"))
      (node (ref "L6") (pin "1") (pinfunction "1_1") (pintype "passive"))
      (node (ref "Q14") (pin "1") (pinfunction "S_1") (pintype "passive"))
      (node (ref "Q14") (pin "2") (pinfunction "S_2") (pintype "passive"))
      (node (ref "Q14") (pin "3") (pinfunction "S_3") (pintype "passive"))
      (node (ref "Q19") (pin "5") (pinfunction "D_5") (pintype "passive"))
      (node (ref "Q19") (pin "6") (pinfunction "D_6") (pintype "passive"))
      (node (ref "Q19") (pin "7") (pinfunction "D_7") (pintype "passive"))
      (node (ref "Q19") (pin "8") (pinfunction "D_8") (pintype "passive"))
      (node (ref "Q20") (pin "5") (pinfunction "D_5") (pintype "passive"))
      (node (ref "Q20") (pin "6") (pinfunction "D_6") (pintype "passive"))
      (node (ref "Q20") (pin "7") (pinfunction "D_7") (pintype "passive"))
      (node (ref "Q20") (pin "8") (pinfunction "D_8") (pintype "passive"))
      (node (ref "U16") (pin "2") (pinfunction "TS_2") (pintype "passive"))
    )
    (net (code "43") (name "/SWN7") (class "Default")
      (node (ref "C93") (pin "2") (pinfunction "2_2") (pintype "passive"))
      (node (ref "L10") (pin "1") (pinfunction "1_1") (pintype "passive"))
      (node (ref "Q26") (pin "1") (pinfunction "S_1") (pintype "passive"))
      (node (ref "Q26") (pin "2") (pinfunction "S_2") (pintype "passive"))
      (node (ref "Q26") (pin "3") (pinfunction "S_3") (pintype "passive"))
      (node (ref "Q31") (pin "5") (pinfunction "D_5") (pintype "passive"))
      (node (ref "Q31") (pin "6") (pinfunction "D_6") (pintype "passive"))
      (node (ref "Q31") (pin "7") (pinfunction "D_7") (pintype "passive"))
      (node (ref "Q31") (pin "8") (pinfunction "D_8") (pintype "passive"))
      (node (ref "Q32") (pin "5") (pinfunction "D_5") (pintype "passive"))
      (node (ref "Q32") (pin "6") (pinfunction "D_6") (pintype "passive"))
      (node (ref "Q32") (pin "7") (pinfunction "D_7") (pintype "passive"))
      (node (ref "Q32") (pin "8") (pinfunction "D_8") (pintype "passive"))
      (node (ref "U20") (pin "2") (pinfunction "TS_2") (pintype "passive"))
    )
    (net (code "44") (name "/SWN8") (class "Default")
      (node (ref "C125") (pin "2") (pinfunction "2_2") (pintype "passive"))
      (node (ref "L14") (pin "1") (pinfunction "1_1") (pintype "passive"))
      (node (ref "Q38") (pin "1") (pinfunction "S_1") (pintype "passive"))
      (node (ref "Q38") (pin "2") (pinfunction "S_2") (pintype "passive"))
      (node (ref "Q38") (pin "3") (pinfunction "S_3") (pintype "passive"))
      (node (ref "Q43") (pin "5") (pinfunction "D_5") (pintype "passive"))
      (node (ref "Q43") (pin "6") (pinfunction "D_6") (pintype "passive"))
      (node (ref "Q43") (pin "7") (pinfunction "D_7") (pintype "passive"))
      (node (ref "Q43") (pin "8") (pinfunction "D_8") (pintype "passive"))
      (node (ref "Q44") (pin "5") (pinfunction "D_5") (pintype "passive"))
      (node (ref "Q44") (pin "6") (pinfunction "D_6") (pintype "passive"))
      (node (ref "Q44") (pin "7") (pinfunction "D_7") (pintype "passive"))
      (node (ref "Q44") (pin "8") (pinfunction "D_8") (pintype "passive"))
      (node (ref "U24") (pin "2") (pinfunction "TS_2") (pintype "passive"))
    )
    (net (code "45") (name "GND") (class "Default")
      (node (ref "C100") (pin "1") (pinfunction "1_1") (pintype "passive"))
      (node (ref "C1000") (pin "2") (pinfunction "2_2") (pintype "passive"))
      (node (ref "C1001") (pin "1") (pinfunction "1_1") (pintype "passive"))
      (node (ref "C1002") (pin "2") (pinfunction "2_2") (pintype "passive"))
      (node (ref "C1003") (pin "2") (pinfunction "2_2") (pintype "passive"))
      (node (ref "C1004") (pin "1") (pinfunction "1_1") (pintype "passive"))
      (node (ref "C1005") (pin "2") (pinfunction "2_2") (pintype "passive"))
      (node (ref "C1006") (pin "2") (pinfunction "2_2") (pintype "passive"))
      (node (ref "C1007") (pin "1") (pinfunction "1_1") (pintype "passive"))
      (node (ref "C1008") (pin "2") (pinfunction "2_2") (pintype "passive"))
      (node (ref "C1009") (pin "2") (pinfunction "2_2") (pintype "passive"))
      (node (ref "C101") (pin "1") (pinfunction "1_1") (pintype "passive"))
      (node (ref "C1010") (pin "1") (pinfunction "1_1") (pintype "passive"))
      (node (ref "C1011") (pin "2") (pinfunction "2_2") (pintype "passive"))
      (node (ref "C1012") (pin "2") (pinfunction "2_2") (pintype "passive"))
      (node (ref "C1013") (pin "1") (pinfunction "1_1") (pintype "passive"))
      (node (ref "C1014") (pin "2") (pinfunction "2_2") (pintype "passive"))
      (node (ref "C1015") (pin "2") (pinfunction "2_2") (pintype "passive"))
      (node (ref "C1016") (pin "1") (pinfunction "1_1") (pintype "passive"))
      (node (ref "C1017") (pin "2") (pinfunction "2_2") (pintype "passive"))
      (node (ref "C1018") (pin "2") (pinfunction "2_2") (pintype "passive"))
      (node (ref "C1019") (pin "1") (pinfunction "1_1") (pintype "passive"))
      (node (ref "C102") (pin "1") (pinfunction "1_1") (pintype "passive"))
      (node (ref "C1020") (pin "2") (pinfunction "2_2") (pintype "passive"))
      (node (ref "C1021") (pin "2") (pinfunction "2_2") (pintype "passive"))
      (node (ref "C1022") (pin "1") (pinfunction "1_1") (pintype "passive"))
      (node (ref "C1023") (pin "2") (pinfunction "2_2") (pintype "passive"))
      (node (ref "C1024") (pin "2") (pinfunction "2_2") (pintype "passive"))
      (node (ref "C1025") (pin "1") (pinfunction "1_1") (pintype "passive"))
      (node (ref "C1026") (pin "2") (pinfunction "2_2") (pintype "passive"))
      (node (ref "C1027") (pin "2") (pinfunction "2_2") (pintype "passive"))
      (node (ref "C1028") (pin "1") (pinfunction "1_1") (pintype "passive"))
      (node (ref "C1029") (pin "2") (pinfunction "2_2") (pintype "passive"))
      (node (ref "C103") (pin "1") (pinfunction "1_1") (pintype "passive"))
      (node (ref "C1030") (pin "2") (pinfunction "2_2") (pintype "passive"))
      (node (ref "C1031") (pin "1") (pinfunction "1_1") (pintype "passive"))
      (node (ref "C1032") (pin "2") (pinfunction "2_2") (pintype "passive"))
      (node (ref "C1033") (pin "2") (pinfunction "2_2") (pintype "passive"))
      (node (ref "C1034") (pin "1") (pinfunction "1_1") (pintype "passive"))
      (node (ref "C1035") (pin "2") (pinfunction "2_2") (pintype "passive"))
      (node (ref "C1036") (pin "2") (pinfunction "2_2") (pintype "passive"))
      (node (ref "C1037") (pin "1") (pinfunction "1_1") (pintype "passive"))
      (node (ref "C1038") (pin "2") (pinfunction "2_2") (pintype "passive"))
      (node (ref "C1039") (pin "2") (pinfunction "2_2") (pintype "passive"))
      (node (ref "C104") (pin "1") (pinfunction "1_1") (pintype "passive"))
      (node (ref "C1040") (pin "1") (pinfunction "1_1") (pintype "passive"))
      (node (ref "C1041") (pin "2") (pinfunction "2_2") (pintype "passive"))
      (node (ref "C1042") (pin "2") (pinfunction "2_2") (pintype "passive"))
      (node (ref "C1043") (pin "1") (pinfunction "1_1") (pintype "passive"))
      (node (ref "C1044") (pin "2") (pinfunction "2_2") (pintype "passive"))
      (node (ref "C1045") (pin "2") (pinfunction "2_2") (pintype "passive"))
      (node (ref "C1046") (pin "1") (pinfunction "1_1") (pintype "passive"))
      (node (ref "C1047") (pin "2") (pinfunction "2_2") (pintype "passive"))
      (node (ref "C1048") (pin "2") (pinfunction "2_2") (pintype "passive"))
      (node (ref "C1049") (pin "1") (pinfunction "1_1") (pintype "passive"))
      (node (ref "C105") (pin "1") (pinfunction "1_1") (pintype "passive"))
      (node (ref "C1050") (pin "2") (pinfunction "2_2") (pintype "passive"))
      (node (ref "C1051") (pin "2") (pinfunction "2_2") (pintype "passive"))
      (node (ref "C1052") (pin "1") (pinfunction "1_1") (pintype "passive"))
      (node (ref "C1053") (pin "2") (pinfunction "2_2") (pintype "passive"))
      (node (ref "C1054") (pin "2") (pinfunction "2_2") (pintype "passive"))
      (node (ref "C1055") (pin "1") (pinfunction "1_1") (pintype "passive"))
      (node (ref "C1056") (pin "2") (pinfunction "2_2") (pintype "passive"))
      (node (ref "C1057") (pin "2") (pinfunction "2_2") (pintype "passive"))
      (node (ref "C1058") (pin "1") (pinfunction "1_1") (pintype "passive"))
      (node (ref "C1059") (pin "2") (pinfunction "2_2") (pintype "passive"))
      (node (ref "C1060") (pin "2") (pinfunction "2_2") (pintype "passive"))
      (node (ref "C1061") (pin "1") (pinfunction "1_1") (pintype "passive"))
      (node (ref "C1062") (pin "2") (pinfunction "2_2") (pintype "passive"))
      (node (ref "C1063") (pin "2") (pinfunction "2_2") (pintype "passive"))
      (node (ref "C1064") (pin "1") (pinfunction "1_1") (pintype "passive"))
      (node (ref "C1065") (pin "2") (pinfunction "2_2") (pintype "passive"))
      (node (ref "C1066") (pin "2") (pinfunction "2_2") (pintype "passive"))
      (node (ref "C1067") (pin "1") (pinfunction "1_1") (pintype "passive"))
      (node (ref "C1068") (pin "2") (pinfunction "2_2") (pintype "passive"))
      (node (ref "C1069") (pin "2") (pinfunction "2_2") (pintype "passive"))
      (node (ref "C1070") (pin "1") (pinfunction "1_1") (pintype "passive"))
      (node (ref "C1071") (pin "2") (pinfunction "2_2") (pintype "passive"))
      (node (ref "C116") (pin "1") (pinfunction "1_1") (pintype "passive"))
      (node (ref "C117") (pin "1") (pinfunction "1_1") (pintype "passive"))
      (node (ref "C120") (pin "2") (pinfunction "2_2") (pintype "passive"))
      (node (ref "C121") (pin "2") (pinfunction "2_2") (pintype "passive"))
      (node (ref "C128") (pin "1") (pinfunction "1_1") (pintype "passive"))
      (node (ref "C129") (pin "1") (pinfunction "1_1") (pintype "passive"))
      (node (ref "C130") (pin "1") (pinfunction "1_1") (pintype "passive"))
      (node (ref "C131") (pin "1") (pinfunction "1_1") (pintype "passive"))
      (node (ref "C132") (pin "1") (pinfunction "1_1") (pintype "passive"))
      (node (ref "C133") (pin "1") (pinfunction "1_1") (pintype "passive"))
      (node (ref "C134") (pin "1") (pinfunction "1_1") (pintype "passive"))
      (node (ref "C135") (pin "1") (pinfunction "1_1") (pintype "passive"))
      (node (ref "C136") (pin "1") (pinfunction "1_1") (pintype "passive"))
      (node (ref "C137") (pin "1") (pinfunction "1_1") (pintype "passive"))
      (node (ref "C20") (pin "1") (pinfunction "1_1") (pintype "passive"))
      (node (ref "C21") (pin "1") (pinfunction "1_1") (pintype "passive"))
      (node (ref "C236") (pin "1") (pinfunction "1_1") (pintype "passive"))
      (node (ref "C24") (pin "2") (pinfunction "2_2") (pintype "passive"))
      (node (ref "C25") (pin "2") (pinfunction "2_2") (pintype "passive"))
      (node (ref "C32") (pin "1") (pinfunction "1_1") (pintype "passive"))
      (node (ref "C323") (pin "2") (pinfunction "2_2") (pintype "passive"))
      (node (ref "C324") (pin "2") (pinfunction "2_2") (pintype "passive"))
      (node (ref "C325") (pin "2") (pinfunction "2_2") (pintype "passive"))
      (node (ref "C326") (pin "2") (pinfunction "2_2") (pintype "passive"))
      (node (ref "C327") (pin "2") (pinfunction "2_2") (pintype "passive"))
      (node (ref "C328") (pin "2") (pinfunction "2_2") (pintype "passive"))
      (node (ref "C329") (pin "2") (pinfunction "2_2") (pintype "passive"))
      (node (ref "C33") (pin "1") (pinfunction "1_1") (pintype "passive"))
      (node (ref "C330") (pin "2") (pinfunction "2_2") (pintype "passive"))
      (node (ref "C331") (pin "2") (pinfunction "2_2") (pintype "passive"))
      (node (ref "C332") (pin "2") (pinfunction "2_2") (pintype "passive"))
      (node (ref "C333") (pin "2") (pinfunction "2_2") (pintype "passive"))
      (node (ref "C334") (pin "2") (pinfunction "2_2") (pintype "passive"))
      (node (ref "C335") (pin "2") (pinfunction "2_2") (pintype "passive"))
      (node (ref "C336") (pin "2") (pinfunction "2_2") (pintype "passive"))
      (node (ref "C337") (pin "2") (pinfunction "2_2") (pintype "passive"))
      (node (ref "C338") (pin "2") (pinfunction "2_2") (pintype "passive"))
      (node (ref "C339") (pin "2") (pinfunction "2_2") (pintype "passive"))
      (node (ref "C34") (pin "1") (pinfunction "1_1") (pintype "passive"))
      (node (ref "C340") (pin "2") (pinfunction "2_2") (pintype "passive"))
      (node (ref "C341") (pin "2") (pinfunction "2_2") (pintype "passive"))
      (node (ref "C342") (pin "2") (pinfunction "2_2") (pintype "passive"))
      (node (ref "C343") (pin "2") (pinfunction "2_2") (pintype "passive"))
      (node (ref "C344") (pin "2") (pinfunction "2_2") (pintype "passive"))
      (node (ref "C345") (pin "2") (pinfunction "2_2") (pintype "passive"))
      (node (ref "C346") (pin "2") (pinfunction "2_2") (pintype "passive"))
      (node (ref "C348") (pin "1") (pinfunction "1_1") (pintype "passive"))
      (node (ref "C349") (pin "1") (pinfunction "1_1") (pintype "passive"))
      (node (ref "C35") (pin "1") (pinfunction "1_1") (pintype "passive"))
      (node (ref "C350") (pin "1") (pinfunction "1_1") (pintype "passive"))
      (node (ref "C351") (pin "1") (pinfunction "1_1") (pintype "passive"))
      (node (ref "C352") (pin "1") (pinfunction "1_1") (pintype "passive"))
      (node (ref "C353") (pin "2") (pinfunction "2_2") (pintype "passive"))
      (node (ref "C354") (pin "2") (pinfunction "2_2") (pintype "passive"))
      (node (ref "C355") (pin "2") (pinfunction "2_2") (pintype "passive"))
      (node (ref "C356") (pin "2") (pinfunction "2_2") (pintype "passive"))
      (node (ref "C357") (pin "2") (pinfunction "2_2") (pintype "passive"))
      (node (ref "C358") (pin "2") (pinfunction "2_2") (pintype "passive"))
      (node (ref "C359") (pin "2") (pinfunction "2_2") (pintype "passive"))
      (node (ref "C360") (pin "2") (pinfunction "2_2") (pintype "passive"))
      (node (ref "C361") (pin "2") (pinfunction "2_2") (pintype "passive"))
      (node (ref "C362") (pin "2") (pinfunction "2_2") (pintype "passive"))
      (node (ref "C363") (pin "2") (pinfunction "2_2") (pintype "passive"))
      (node (ref "C364") (pin "2") (pinfunction "2_2") (pintype "passive"))
      (node (ref "C365") (pin "2") (pinfunction "2_2") (pintype "passive"))
      (node (ref "C366") (pin "2") (pinfunction "2_2") (pintype "passive"))
      (node (ref "C367") (pin "2") (pinfunction "2_2") (pintype "passive"))
      (node (ref "C368") (pin "2") (pinfunction "2_2") (pintype "passive"))
      (node (ref "C369") (pin "2") (pinfunction "2_2") (pintype "passive"))
      (node (ref "C37") (pin "1") (pinfunction "1_1") (pintype "passive"))
      (node (ref "C370") (pin "2") (pinfunction "2_2") (pintype "passive"))
      (node (ref "C371") (pin "2") (pinfunction "2_2") (pintype "passive"))
      (node (ref "C372") (pin "2") (pinfunction "2_2") (pintype "passive"))
      (node (ref "C373") (pin "2") (pinfunction "2_2") (pintype "passive"))
      (node (ref "C374") (pin "2") (pinfunction "2_2") (pintype "passive"))
      (node (ref "C375") (pin "2") (pinfunction "2_2") (pintype "passive"))
      (node (ref "C376") (pin "2") (pinfunction "2_2") (pintype "passive"))
      (node (ref "C377") (pin "2") (pinfunction "2_2") (pintype "passive"))
      (node (ref "C378") (pin "2") (pinfunction "2_2") (pintype "passive"))
      (node (ref "C379") (pin "2") (pinfunction "2_2") (pintype "passive"))
      (node (ref "C38") (pin "1") (pinfunction "1_1") (pintype "passive"))
      (node (ref "C380") (pin "2") (pinfunction "2_2") (pintype "passive"))
      (node (ref "C381") (pin "2") (pinfunction "2_2") (pintype "passive"))
      (node (ref "C382") (pin "2") (pinfunction "2_2") (pintype "passive"))
      (node (ref "C383") (pin "2") (pinfunction "2_2") (pintype "passive"))
      (node (ref "C384") (pin "2") (pinfunction "2_2") (pintype "passive"))
      (node (ref "C385") (pin "2") (pinfunction "2_2") (pintype "passive"))
      (node (ref "C386") (pin "2") (pinfunction "2_2") (pintype "passive"))
      (node (ref "C387") (pin "2") (pinfunction "2_2") (pintype "passive"))
      (node (ref "C388") (pin "2") (pinfunction "2_2") (pintype "passive"))
      (node (ref "C389") (pin "2") (pinfunction "2_2") (pintype "passive"))
      (node (ref "C39") (pin "1") (pinfunction "1_1") (pintype "passive"))
      (node (ref "C390") (pin "2") (pinfunction "2_2") (pintype "passive"))
      (node (ref "C391") (pin "2") (pinfunction "2_2") (pintype "passive"))
      (node (ref "C392") (pin "2") (pinfunction "2_2") (pintype "passive"))
      (node (ref "C393") (pin "1") (pinfunction "1_1") (pintype "passive"))
      (node (ref "C394") (pin "1") (pinfunction "1_1") (pintype "passive"))
      (node (ref "C395") (pin "1") (pinfunction "1_1") (pintype "passive"))
      (node (ref "C396") (pin "1") (pinfunction "1_1") (pintype "passive"))
      (node (ref "C397") (pin "1") (pinfunction "1_1") (pintype "passive"))
      (node (ref "C398") (pin "1") (pinfunction "1_1") (pintype "passive"))
      (node (ref "C399") (pin "1") (pinfunction "1_1") (pintype "passive"))
      (node (ref "C40") (pin "1") (pinfunction "1_1") (pintype "passive"))
      (node (ref "C400") (pin "1") (pinfunction "1_1") (pintype "passive"))
      (node (ref "C401") (pin "1") (pinfunction "1_1") (pintype "passive"))
      (node (ref "C402") (pin "1") (pinfunction "1_1") (pintype "passive"))
      (node (ref "C403") (pin "1") (pinfunction "1_1") (pintype "passive"))
      (node (ref "C404") (pin "1") (pinfunction "1_1") (pintype "passive"))
      (node (ref "C405") (pin "1") (pinfunction "1_1") (pintype "passive"))
      (node (ref "C406") (pin "1") (pinfunction "1_1") (pintype "passive"))
      (node (ref "C407") (pin "1") (pinfunction "1_1") (pintype "passive"))
      (node (ref "C408") (pin "1") (pinfunction "1_1") (pintype "passive"))
      (node (ref "C409") (pin "1") (pinfunction "1_1") (pintype "passive"))
      (node (ref "C41") (pin "1") (pinfunction "1_1") (pintype "passive"))
      (node (ref "C410") (pin "1") (pinfunction "1_1") (pintype "passive"))
      (node (ref "C411") (pin "1") (pinfunction "1_1") (pintype "passive"))
      (node (ref "C412") (pin "1") (pinfunction "1_1") (pintype "passive"))
      (node (ref "C413") (pin "1") (pinfunction "1_1") (pintype "passive"))
      (node (ref "C414") (pin "1") (pinfunction "1_1") (pintype "passive"))
      (node (ref "C415") (pin "1") (pinfunction "1_1") (pintype "passive"))
      (node (ref "C416") (pin "1") (pinfunction "1_1") (pintype "passive"))
      (node (ref "C417") (pin "1") (pinfunction "1_1") (pintype "passive"))
      (node (ref "C418") (pin "1") (pinfunction "1_1") (pintype "passive"))
      (node (ref "C419") (pin "1") (pinfunction "1_1") (pintype "passive"))
      (node (ref "C420") (pin "1") (pinfunction "1_1") (pintype "passive"))
      (node (ref "C421") (pin "1") (pinfunction "1_1") (pintype "passive"))
      (node (ref "C422") (pin "1") (pinfunction "1_1") (pintype "passive"))
      (node (ref "C423") (pin "1") (pinfunction "1_1") (pintype "passive"))
      (node (ref "C424") (pin "1") (pinfunction "1_1") (pintype "passive"))
      (node (ref "C425") (pin "1") (pinfunction "1_1") (pintype "passive"))
      (node (ref "C426") (pin "1") (pinfunction "1_1") (pintype "passive"))
      (node (ref "C427") (pin "1") (pinfunction "1_1") (pintype "passive"))
      (node (ref "C428") (pin "2") (pinfunction "2_2") (pintype "passive"))
      (node (ref "C429") (pin "2") (pinfunction "2_2") (pintype "passive"))
      (node (ref "C430") (pin "2") (pinfunction "2_2") (pintype "passive"))
      (node (ref "C431") (pin "2") (pinfunction "2_2") (pintype "passive"))
      (node (ref "C432") (pin "2") (pinfunction "2_2") (pintype "passive"))
      (node (ref "C433") (pin "2") (pinfunction "2_2") (pintype "passive"))
      (node (ref "C434") (pin "2") (pinfunction "2_2") (pintype "passive"))
      (node (ref "C435") (pin "2") (pinfunction "2_2") (pintype "passive"))
      (node (ref "C436") (pin "2") (pinfunction "2_2") (pintype "passive"))
      (node (ref "C437") (pin "2") (pinfunction "2_2") (pintype "passive"))
      (node (ref "C438") (pin "2") (pinfunction "2_2") (pintype "passive"))
      (node (ref "C439") (pin "2") (pinfunction "2_2") (pintype "passive"))
      (node (ref "C440") (pin "2") (pinfunction "2_2") (pintype "passive"))
      (node (ref "C441") (pin "2") (pinfunction "2_2") (pintype "passive"))
      (node (ref "C442") (pin "2") (pinfunction "2_2") (pintype "passive"))
      (node (ref "C443") (pin "2") (pinfunction "2_2") (pintype "passive"))
      (node (ref "C444") (pin "2") (pinfunction "2_2") (pintype "passive"))
      (node (ref "C445") (pin "2") (pinfunction "2_2") (pintype "passive"))
      (node (ref "C446") (pin "2") (pinfunction "2_2") (pintype "passive"))
      (node (ref "C447") (pin "2") (pinfunction "2_2") (pintype "passive"))
      (node (ref "C448") (pin "2") (pinfunction "2_2") (pintype "passive"))
      (node (ref "C449") (pin "2") (pinfunction "2_2") (pintype "passive"))
      (node (ref "C450") (pin "2") (pinfunction "2_2") (pintype "passive"))
      (node (ref "C451") (pin "2") (pinfunction "2_2") (pintype "passive"))
      (node (ref "C452") (pin "2") (pinfunction "2_2") (pintype "passive"))
      (node (ref "C453") (pin "2") (pinfunction "2_2") (pintype "passive"))
      (node (ref "C454") (pin "2") (pinfunction "2_2") (pintype "passive"))
      (node (ref "C455") (pin "2") (pinfunction "2_2") (pintype "passive"))
      (node (ref "C456") (pin "2") (pinfunction "2_2") (pintype "passive"))
      (node (ref "C457") (pin "2") (pinfunction "2_2") (pintype "passive"))
      (node (ref "C458") (pin "2") (pinfunction "2_2") (pintype "passive"))
      (node (ref "C459") (pin "2") (pinfunction "2_2") (pintype "passive"))
      (node (ref "C460") (pin "2") (pinfunction "2_2") (pintype "passive"))
      (node (ref "C461") (pin "2") (pinfunction "2_2") (pintype "passive"))
      (node (ref "C462") (pin "2") (pinfunction "2_2") (pintype "passive"))
      (node (ref "C463") (pin "2") (pinfunction "2_2") (pintype "passive"))
      (node (ref "C464") (pin "2") (pinfunction "2_2") (pintype "passive"))
      (node (ref "C465") (pin "2") (pinfunction "2_2") (pintype "passive"))
      (node (ref "C466") (pin "2") (pinfunction "2_2") (pintype "passive"))
      (node (ref "C467") (pin "2") (pinfunction "2_2") (pintype "passive"))
      (node (ref "C468") (pin "2") (pinfunction "2_2") (pintype "passive"))
      (node (ref "C469") (pin "2") (pinfunction "2_2") (pintype "passive"))
      (node (ref "C470") (pin "2") (pinfunction "2_2") (pintype "passive"))
      (node (ref "C471") (pin "2") (pinfunction "2_2") (pintype "passive"))
      (node (ref "C472") (pin "2") (pinfunction "2_2") (pintype "passive"))
      (node (ref "C473") (pin "2") (pinfunction "2_2") (pintype "passive"))
      (node (ref "C474") (pin "2") (pinfunction "2_2") (pintype "passive"))
      (node (ref "C475") (pin "2") (pinfunction "2_2") (pintype "passive"))
      (node (ref "C476") (pin "2") (pinfunction "2_2") (pintype "passive"))
      (node (ref "C477") (pin "2") (pinfunction "2_2") (pintype "passive"))
      (node (ref "C478") (pin "2") (pinfunction "2_2") (pintype "passive"))
      (node (ref "C479") (pin "2") (pinfunction "2_2") (pintype "passive"))
      (node (ref "C480") (pin "2") (pinfunction "2_2") (pintype "passive"))
      (node (ref "C481") (pin "2") (pinfunction "2_2") (pintype "passive"))
      (node (ref "C482") (pin "2") (pinfunction "2_2") (pintype "passive"))
      (node (ref "C483") (pin "2") (pinfunction "2_2") (pintype "passive"))
      (node (ref "C484") (pin "2") (pinfunction "2_2") (pintype "passive"))
      (node (ref "C485") (pin "2") (pinfunction "2_2") (pintype "passive"))
      (node (ref "C486") (pin "2") (pinfunction "2_2") (pintype "passive"))
      (node (ref "C487") (pin "2") (pinfunction "2_2") (pintype "passive"))
      (node (ref "C488") (pin "2") (pinfunction "2_2") (pintype "passive"))
      (node (ref "C489") (pin "2") (pinfunction "2_2") (pintype "passive"))
      (node (ref "C490") (pin "2") (pinfunction "2_2") (pintype "passive"))
      (node (ref "C491") (pin "2") (pinfunction "2_2") (pintype "passive"))
      (node (ref "C52") (pin "1") (pinfunction "1_1") (pintype "passive"))
      (node (ref "C53") (pin "1") (pinfunction "1_1") (pintype "passive"))
      (node (ref "C56") (pin "2") (pinfunction "2_2") (pintype "passive"))
      (node (ref "C57") (pin "2") (pinfunction "2_2") (pintype "passive"))
      (node (ref "C593") (pin "1") (pinfunction "1_1") (pintype "passive"))
      (node (ref "C596") (pin "1") (pinfunction "1_1") (pintype "passive"))
      (node (ref "C598") (pin "2") (pinfunction "2_2") (pintype "passive"))
      (node (ref "C599") (pin "1") (pinfunction "1_1") (pintype "passive"))
      (node (ref "C600") (pin "2") (pinfunction "2_2") (pintype "passive"))
      (node (ref "C602") (pin "1") (pinfunction "1_1") (pintype "passive"))
      (node (ref "C603") (pin "2") (pinfunction "2_2") (pintype "passive"))
      (node (ref "C605") (pin "1") (pinfunction "1_1") (pintype "passive"))
      (node (ref "C606") (pin "2") (pinfunction "2_2") (pintype "passive"))
      (node (ref "C64") (pin "1") (pinfunction "1_1") (pintype "passive"))
      (node (ref "C640") (pin "2") (pinfunction "2_2") (pintype "passive"))
      (node (ref "C642") (pin "2") (pinfunction "2_2") (pintype "passive"))
      (node (ref "C643") (pin "2") (pinfunction "2_2") (pintype "passive"))
      (node (ref "C645") (pin "2") (pinfunction "2_2") (pintype "passive"))
      (node (ref "C646") (pin "2") (pinfunction "2_2") (pintype "passive"))
      (node (ref "C65") (pin "1") (pinfunction "1_1") (pintype "passive"))
      (node (ref "C652") (pin "2") (pinfunction "2_2") (pintype "passive"))
      (node (ref "C653") (pin "1") (pinfunction "1_1") (pintype "passive"))
      (node (ref "C654") (pin "2") (pinfunction "2_2") (pintype "passive"))
      (node (ref "C655") (pin "2") (pinfunction "2_2") (pintype "passive"))
      (node (ref "C656") (pin "1") (pinfunction "1_1") (pintype "passive"))
      (node (ref "C657") (pin "2") (pinfunction "2_2") (pintype "passive"))
      (node (ref "C658") (pin "2") (pinfunction "2_2") (pintype "passive"))
      (node (ref "C659") (pin "1") (pinfunction "1_1") (pintype "passive"))
      (node (ref "C66") (pin "1") (pinfunction "1_1") (pintype "passive"))
      (node (ref "C660") (pin "2") (pinfunction "2_2") (pintype "passive"))
      (node (ref "C661") (pin "2") (pinfunction "2_2") (pintype "passive"))
      (node (ref "C662") (pin "1") (pinfunction "1_1") (pintype "passive"))
      (node (ref "C663") (pin "2") (pinfunction "2_2") (pintype "passive"))
      (node (ref "C664") (pin "2") (pinfunction "2_2") (pintype "passive"))
      (node (ref "C665") (pin "1") (pinfunction "1_1") (pintype "passive"))
      (node (ref "C666") (pin "2") (pinfunction "2_2") (pintype "passive"))
      (node (ref "C667") (pin "2") (pinfunction "2_2") (pintype "passive"))
      (node (ref "C668") (pin "1") (pinfunction "1_1") (pintype "passive"))
      (node (ref "C669") (pin "2") (pinfunction "2_2") (pintype "passive"))
      (node (ref "C67") (pin "1") (pinfunction "1_1") (pintype "passive"))
      (node (ref "C670") (pin "2") (pinfunction "2_2") (pintype "passive"))
      (node (ref "C671") (pin "1") (pinfunction "1_1") (pintype "passive"))
      (node (ref "C672") (pin "2") (pinfunction "2_2") (pintype "passive"))
      (node (ref "C673") (pin "2") (pinfunction "2_2") (pintype "passive"))
      (node (ref "C674") (pin "1") (pinfunction "1_1") (pintype "passive"))
      (node (ref "C675") (pin "2") (pinfunction "2_2") (pintype "passive"))
      (node (ref "C676") (pin "2") (pinfunction "2_2") (pintype "passive"))
      (node (ref "C677") (pin "1") (pinfunction "1_1") (pintype "passive"))
      (node (ref "C678") (pin "2") (pinfunction "2_2") (pintype "passive"))
      (node (ref "C679") (pin "2") (pinfunction "2_2") (pintype "passive"))
      (node (ref "C68") (pin "1") (pinfunction "1_1") (pintype "passive"))
      (node (ref "C680") (pin "1") (pinfunction "1_1") (pintype "passive"))
      (node (ref "C681") (pin "2") (pinfunction "2_2") (pintype "passive"))
      (node (ref "C686") (pin "1") (pinfunction "1_1") (pintype "passive"))
      (node (ref "C688") (pin "2") (pinfunction "2_2") (pintype "passive"))
      (node (ref "C689") (pin "1") (pinfunction "1_1") (pintype "passive"))
      (node (ref "C69") (pin "1") (pinfunction "1_1") (pintype "passive"))
      (node (ref "C692") (pin "1") (pinfunction "1_1") (pintype "passive"))
      (node (ref "C695") (pin "1") (pinfunction "1_1") (pintype "passive"))
      (node (ref "C70") (pin "1") (pinfunction "1_1") (pintype "passive"))
      (node (ref "C71") (pin "1") (pinfunction "1_1") (pintype "passive"))
      (node (ref "C711") (pin "2") (pinfunction "2_2") (pintype "passive"))
      (node (ref "C712") (pin "2") (pinfunction "2_2") (pintype "passive"))
      (node (ref "C714") (pin "2") (pinfunction "2_2") (pintype "passive"))
      (node (ref "C715") (pin "2") (pinfunction "2_2") (pintype "passive"))
      (node (ref "C717") (pin "2") (pinfunction "2_2") (pintype "passive"))
      (node (ref "C72") (pin "1") (pinfunction "1_1") (pintype "passive"))
      (node (ref "C73") (pin "1") (pinfunction "1_1") (pintype "passive"))
      (node (ref "C742") (pin "2") (pinfunction "2_2") (pintype "passive"))
      (node (ref "C743") (pin "1") (pinfunction "1_1") (pintype "passive"))
      (node (ref "C744") (pin "2") (pinfunction "2_2") (pintype "passive"))
      (node (ref "C745") (pin "2") (pinfunction "2_2") (pintype "passive"))
      (node (ref "C746") (pin "1") (pinfunction "1_1") (pintype "passive"))
      (node (ref "C747") (pin "2") (pinfunction "2_2") (pintype "passive"))
      (node (ref "C748") (pin "2") (pinfunction "2_2") (pintype "passive"))
      (node (ref "C749") (pin "1") (pinfunction "1_1") (pintype "passive"))
      (node (ref "C750") (pin "2") (pinfunction "2_2") (pintype "passive"))
      (node (ref "C751") (pin "2") (pinfunction "2_2") (pintype "passive"))
      (node (ref "C752") (pin "1") (pinfunction "1_1") (pintype "passive"))
      (node (ref "C753") (pin "2") (pinfunction "2_2") (pintype "passive"))
      (node (ref "C754") (pin "2") (pinfunction "2_2") (pintype "passive"))
      (node (ref "C755") (pin "1") (pinfunction "1_1") (pintype "passive"))
      (node (ref "C756") (pin "2") (pinfunction "2_2") (pintype "passive"))
      (node (ref "C757") (pin "2") (pinfunction "2_2") (pintype "passive"))
      (node (ref "C758") (pin "1") (pinfunction "1_1") (pintype "passive"))
      (node (ref "C759") (pin "2") (pinfunction "2_2") (pintype "passive"))
      (node (ref "C760") (pin "2") (pinfunction "2_2") (pintype "passive"))
      (node (ref "C761") (pin "1") (pinfunction "1_1") (pintype "passive"))
      (node (ref "C762") (pin "2") (pinfunction "2_2") (pintype "passive"))
      (node (ref "C763") (pin "2") (pinfunction "2_2") (pintype "passive"))
      (node (ref "C764") (pin "1") (pinfunction "1_1") (pintype "passive"))
      (node (ref "C765") (pin "2") (pinfunction "2_2") (pintype "passive"))
      (node (ref "C766") (pin "2") (pinfunction "2_2") (pintype "passive"))
      (node (ref "C767") (pin "1") (pinfunction "1_1") (pintype "passive"))
      (node (ref "C768") (pin "2") (pinfunction "2_2") (pintype "passive"))
      (node (ref "C769") (pin "2") (pinfunction "2_2") (pintype "passive"))
      (node (ref "C770") (pin "1") (pinfunction "1_1") (pintype "passive"))
      (node (ref "C771") (pin "2") (pinfunction "2_2") (pintype "passive"))
      (node (ref "C776") (pin "1") (pinfunction "1_1") (pintype "passive"))
      (node (ref "C779") (pin "1") (pinfunction "1_1") (pintype "passive"))
      (node (ref "C782") (pin "1") (pinfunction "1_1") (pintype "passive"))
      (node (ref "C785") (pin "1") (pinfunction "1_1") (pintype "passive"))
      (node (ref "C807") (pin "2") (pinfunction "2_2") (pintype "passive"))
      (node (ref "C808") (pin "2") (pinfunction "2_2") (pintype "passive"))
      (node (ref "C810") (pin "2") (pinfunction "2_2") (pintype "passive"))
      (node (ref "C811") (pin "2") (pinfunction "2_2") (pintype "passive"))
      (node (ref "C813") (pin "2") (pinfunction "2_2") (pintype "passive"))
      (node (ref "C814") (pin "2") (pinfunction "2_2") (pintype "passive"))
      (node (ref "C832") (pin "2") (pinfunction "2_2") (pintype "passive"))
      (node (ref "C833") (pin "1") (pinfunction "1_1") (pintype "passive"))
      (node (ref "C834") (pin "2") (pinfunction "2_2") (pintype "passive"))
      (node (ref "C835") (pin "2") (pinfunction "2_2") (pintype "passive"))
      (node (ref "C836") (pin "1") (pinfunction "1_1") (pintype "passive"))
      (node (ref "C837") (pin "2") (pinfunction "2_2") (pintype "passive"))
      (node (ref "C838") (pin "2") (pinfunction "2_2") (pintype "passive"))
      (node (ref "C839") (pin "1") (pinfunction "1_1") (pintype "passive"))
      (node (ref "C84") (pin "1") (pinfunction "1_1") (pintype "passive"))
      (node (ref "C840") (pin "2") (pinfunction "2_2") (pintype "passive"))
      (node (ref "C841") (pin "2") (pinfunction "2_2") (pintype "passive"))
      (node (ref "C842") (pin "1") (pinfunction "1_1") (pintype "passive"))
      (node (ref "C843") (pin "2") (pinfunction "2_2") (pintype "passive"))
      (node (ref "C844") (pin "2") (pinfunction "2_2") (pintype "passive"))
      (node (ref "C845") (pin "1") (pinfunction "1_1") (pintype "passive"))
      (node (ref "C846") (pin "2") (pinfunction "2_2") (pintype "passive"))
      (node (ref "C847") (pin "2") (pinfunction "2_2") (pintype "passive"))
      (node (ref "C848") (pin "1") (pinfunction "1_1") (pintype "passive"))
      (node (ref "C849") (pin "2") (pinfunction "2_2") (pintype "passive"))
      (node (ref "C85") (pin "1") (pinfunction "1_1") (pintype "passive"))
      (node (ref "C850") (pin "2") (pinfunction "2_2") (pintype "passive"))
      (node (ref "C851") (pin "1") (pinfunction "1_1") (pintype "passive"))
      (node (ref "C852") (pin "2") (pinfunction "2_2") (pintype "passive"))
      (node (ref "C853") (pin "2") (pinfunction "2_2") (pintype "passive"))
      (node (ref "C854") (pin "1") (pinfunction "1_1") (pintype "passive"))
      (node (ref "C855") (pin "2") (pinfunction "2_2") (pintype "passive"))
      (node (ref "C856") (pin "2") (pinfunction "2_2") (pintype "passive"))
      (node (ref "C857") (pin "1") (pinfunction "1_1") (pintype "passive"))
      (node (ref "C858") (pin "2") (pinfunction "2_2") (pintype "passive"))
      (node (ref "C859") (pin "2") (pinfunction "2_2") (pintype "passive"))
      (node (ref "C860") (pin "1") (pinfunction "1_1") (pintype "passive"))
      (node (ref "C861") (pin "2") (pinfunction "2_2") (pintype "passive"))
      (node (ref "C866") (pin "1") (pinfunction "1_1") (pintype "passive"))
      (node (ref "C868") (pin "2") (pinfunction "2_2") (pintype "passive"))
      (node (ref "C869") (pin "1") (pinfunction "1_1") (pintype "passive"))
      (node (ref "C872") (pin "1") (pinfunction "1_1") (pintype "passive"))
      (node (ref "C876") (pin "2") (pinfunction "2_2") (pintype "passive"))
      (node (ref "C877") (pin "2") (pinfunction "2_2") (pintype "passive"))
      (node (ref "C879") (pin "2") (pinfunction "2_2") (pintype "passive"))
      (node (ref "C88") (pin "2") (pinfunction "2_2") (pintype "passive"))
      (node (ref "C880") (pin "2") (pinfunction "2_2") (pintype "passive"))
      (node (ref "C882") (pin "2") (pinfunction "2_2") (pintype "passive"))
      (node (ref "C89") (pin "2") (pinfunction "2_2") (pintype "passive"))
      (node (ref "C913") (pin "2") (pinfunction "2_2") (pintype "passive"))
      (node (ref "C915") (pin "2") (pinfunction "2_2") (pintype "passive"))
      (node (ref "C916") (pin "2") (pinfunction "2_2") (pintype "passive"))
      (node (ref "C918") (pin "2") (pinfunction "2_2") (pintype "passive"))
      (node (ref "C919") (pin "2") (pinfunction "2_2") (pintype "passive"))
      (node (ref "C922") (pin "2") (pinfunction "2_2") (pintype "passive"))
      (node (ref "C923") (pin "1") (pinfunction "1_1") (pintype "passive"))
      (node (ref "C924") (pin "2") (pinfunction "2_2") (pintype "passive"))
      (node (ref "C925") (pin "2") (pinfunction "2_2") (pintype "passive"))
      (node (ref "C926") (pin "1") (pinfunction "1_1") (pintype "passive"))
      (node (ref "C927") (pin "2") (pinfunction "2_2") (pintype "passive"))
      (node (ref "C928") (pin "2") (pinfunction "2_2") (pintype "passive"))
      (node (ref "C929") (pin "1") (pinfunction "1_1") (pintype "passive"))
      (node (ref "C930") (pin "2") (pinfunction "2_2") (pintype "passive"))
      (node (ref "C931") (pin "2") (pinfunction "2_2") (pintype "passive"))
      (node (ref "C932") (pin "1") (pinfunction "1_1") (pintype "passive"))
      (node (ref "C933") (pin "2") (pinfunction "2_2") (pintype "passive"))
      (node (ref "C934") (pin "2") (pinfunction "2_2") (pintype "passive"))
      (node (ref "C935") (pin "1") (pinfunction "1_1") (pintype "passive"))
      (node (ref "C936") (pin "2") (pinfunction "2_2") (pintype "passive"))
      (node (ref "C937") (pin "2") (pinfunction "2_2") (pintype "passive"))
      (node (ref "C938") (pin "1") (pinfunction "1_1") (pintype "passive"))
      (node (ref "C939") (pin "2") (pinfunction "2_2") (pintype "passive"))
      (node (ref "C940") (pin "2") (pinfunction "2_2") (pintype "passive"))
      (node (ref "C941") (pin "1") (pinfunction "1_1") (pintype "passive"))
      (node (ref "C942") (pin "2") (pinfunction "2_2") (pintype "passive"))
      (node (ref "C943") (pin "2") (pinfunction "2_2") (pintype "passive"))
      (node (ref "C944") (pin "1") (pinfunction "1_1") (pintype "passive"))
      (node (ref "C945") (pin "2") (pinfunction "2_2") (pintype "passive"))
      (node (ref "C946") (pin "2") (pinfunction "2_2") (pintype "passive"))
      (node (ref "C947") (pin "1") (pinfunction "1_1") (pintype "passive"))
      (node (ref "C948") (pin "2") (pinfunction "2_2") (pintype "passive"))
      (node (ref "C949") (pin "2") (pinfunction "2_2") (pintype "passive"))
      (node (ref "C950") (pin "1") (pinfunction "1_1") (pintype "passive"))
      (node (ref "C951") (pin "2") (pinfunction "2_2") (pintype "passive"))
      (node (ref "C952") (pin "2") (pinfunction "2_2") (pintype "passive"))
      (node (ref "C953") (pin "1") (pinfunction "1_1") (pintype "passive"))
      (node (ref "C954") (pin "2") (pinfunction "2_2") (pintype "passive"))
      (node (ref "C955") (pin "2") (pinfunction "2_2") (pintype "passive"))
      (node (ref "C956") (pin "1") (pinfunction "1_1") (pintype "passive"))
      (node (ref "C957") (pin "2") (pinfunction "2_2") (pintype "passive"))
      (node (ref "C958") (pin "2") (pinfunction "2_2") (pintype "passive"))
      (node (ref "C959") (pin "1") (pinfunction "1_1") (pintype "passive"))
      (node (ref "C96") (pin "1") (pinfunction "1_1") (pintype "passive"))
      (node (ref "C960") (pin "2") (pinfunction "2_2") (pintype "passive"))
      (node (ref "C961") (pin "2") (pinfunction "2_2") (pintype "passive"))
      (node (ref "C962") (pin "1") (pinfunction "1_1") (pintype "passive"))
      (node (ref "C963") (pin "2") (pinfunction "2_2") (pintype "passive"))
      (node (ref "C964") (pin "2") (pinfunction "2_2") (pintype "passive"))
      (node (ref "C965") (pin "1") (pinfunction "1_1") (pintype "passive"))
      (node (ref "C966") (pin "2") (pinfunction "2_2") (pintype "passive"))
      (node (ref "C967") (pin "2") (pinfunction "2_2") (pintype "passive"))
      (node (ref "C968") (pin "1") (pinfunction "1_1") (pintype "passive"))
      (node (ref "C969") (pin "2") (pinfunction "2_2") (pintype "passive"))
      (node (ref "C97") (pin "1") (pinfunction "1_1") (pintype "passive"))
      (node (ref "C970") (pin "2") (pinfunction "2_2") (pintype "passive"))
      (node (ref "C971") (pin "1") (pinfunction "1_1") (pintype "passive"))
      (node (ref "C972") (pin "2") (pinfunction "2_2") (pintype "passive"))
      (node (ref "C973") (pin "2") (pinfunction "2_2") (pintype "passive"))
      (node (ref "C974") (pin "1") (pinfunction "1_1") (pintype "passive"))
      (node (ref "C975") (pin "2") (pinfunction "2_2") (pintype "passive"))
      (node (ref "C976") (pin "2") (pinfunction "2_2") (pintype "passive"))
      (node (ref "C977") (pin "1") (pinfunction "1_1") (pintype "passive"))
      (node (ref "C978") (pin "2") (pinfunction "2_2") (pintype "passive"))
      (node (ref "C979") (pin "2") (pinfunction "2_2") (pintype "passive"))
      (node (ref "C98") (pin "1") (pinfunction "1_1") (pintype "passive"))
      (node (ref "C980") (pin "1") (pinfunction "1_1") (pintype "passive"))
      (node (ref "C981") (pin "2") (pinfunction "2_2") (pintype "passive"))
      (node (ref "C982") (pin "2") (pinfunction "2_2") (pintype "passive"))
      (node (ref "C983") (pin "1") (pinfunction "1_1") (pintype "passive"))
      (node (ref "C984") (pin "2") (pinfunction "2_2") (pintype "passive"))
      (node (ref "C985") (pin "2") (pinfunction "2_2") (pintype "passive"))
      (node (ref "C986") (pin "1") (pinfunction "1_1") (pintype "passive"))
      (node (ref "C987") (pin "2") (pinfunction "2_2") (pintype "passive"))
      (node (ref "C988") (pin "2") (pinfunction "2_2") (pintype "passive"))
      (node (ref "C989") (pin "1") (pinfunction "1_1") (pintype "passive"))
      (node (ref "C99") (pin "1") (pinfunction "1_1") (pintype "passive"))
      (node (ref "C990") (pin "2") (pinfunction "2_2") (pintype "passive"))
      (node (ref "C991") (pin "2") (pinfunction "2_2") (pintype "passive"))
      (node (ref "C992") (pin "1") (pinfunction "1_1") (pintype "passive"))
      (node (ref "C993") (pin "2") (pinfunction "2_2") (pintype "passive"))
      (node (ref "C994") (pin "2") (pinfunction "2_2") (pintype "passive"))
      (node (ref "C995") (pin "1") (pinfunction "1_1") (pintype "passive"))
      (node (ref "C996") (pin "2") (pinfunction "2_2") (pintype "passive"))
      (node (ref "C997") (pin "2") (pinfunction "2_2") (pintype "passive"))
      (node (ref "C998") (pin "1") (pinfunction "1_1") (pintype "passive"))
      (node (ref "C999") (pin "2") (pinfunction "2_2") (pintype "passive"))
      (node (ref "Q17") (pin "1") (pinfunction "S_1") (pintype "passive"))
      (node (ref "Q17") (pin "2") (pinfunction "S_2") (pintype "passive"))
      (node (ref "Q17") (pin "3") (pinfunction "S_3") (pintype "passive"))
      (node (ref "Q18") (pin "1") (pinfunction "S_1") (pintype "passive"))
      (node (ref "Q18") (pin "2") (pinfunction "S_2") (pintype "passive"))
      (node (ref "Q18") (pin "3") (pinfunction "S_3") (pintype "passive"))
      (node (ref "Q19") (pin "1") (pinfunction "S_1") (pintype "passive"))
      (node (ref "Q19") (pin "2") (pinfunction "S_2") (pintype "passive"))
      (node (ref "Q19") (pin "3") (pinfunction "S_3") (pintype "passive"))
      (node (ref "Q20") (pin "1") (pinfunction "S_1") (pintype "passive"))
      (node (ref "Q20") (pin "2") (pinfunction "S_2") (pintype "passive"))
      (node (ref "Q20") (pin "3") (pinfunction "S_3") (pintype "passive"))
      (node (ref "Q29") (pin "1") (pinfunction "S_1") (pintype "passive"))
      (node (ref "Q29") (pin "2") (pinfunction "S_2") (pintype "passive"))
      (node (ref "Q29") (pin "3") (pinfunction "S_3") (pintype "passive"))
      (node (ref "Q30") (pin "1") (pinfunction "S_1") (pintype "passive"))
      (node (ref "Q30") (pin "2") (pinfunction "S_2") (pintype "passive"))
      (node (ref "Q30") (pin "3") (pinfunction "S_3") (pintype "passive"))
      (node (ref "Q31") (pin "1") (pinfunction "S_1") (pintype "passive"))
      (node (ref "Q31") (pin "2") (pinfunction "S_2") (pintype "passive"))
      (node (ref "Q31") (pin "3") (pinfunction "S_3") (pintype "passive"))
      (node (ref "Q32") (pin "1") (pinfunction "S_1") (pintype "passive"))
      (node (ref "Q32") (pin "2") (pinfunction "S_2") (pintype "passive"))
      (node (ref "Q32") (pin "3") (pinfunction "S_3") (pintype "passive"))
      (node (ref "Q41") (pin "1") (pinfunction "S_1") (pintype "passive"))
      (node (ref "Q41") (pin "2") (pinfunction "S_2") (pintype "passive"))
      (node (ref "Q41") (pin "3") (pinfunction "S_3") (pintype "passive"))
      (node (ref "Q42") (pin "1") (pinfunction "S_1") (pintype "passive"))
      (node (ref "Q42") (pin "2") (pinfunction "S_2") (pintype "passive"))
      (node (ref "Q42") (pin "3") (pinfunction "S_3") (pintype "passive"))
      (node (ref "Q43") (pin "1") (pinfunction "S_1") (pintype "passive"))
      (node (ref "Q43") (pin "2") (pinfunction "S_2") (pintype "passive"))
      (node (ref "Q43") (pin "3") (pinfunction "S_3") (pintype "passive"))
      (node (ref "Q44") (pin "1") (pinfunction "S_1") (pintype "passive"))
      (node (ref "Q44") (pin "2") (pinfunction "S_2") (pintype "passive"))
      (node (ref "Q44") (pin "3") (pinfunction "S_3") (pintype "passive"))
      (node (ref "Q5") (pin "1") (pinfunction "S_1") (pintype "passive"))
      (node (ref "Q5") (pin "2") (pinfunction "S_2") (pintype "passive"))
      (node (ref "Q5") (pin "3") (pinfunction "S_3") (pintype "passive"))
      (node (ref "Q6") (pin "1") (pinfunction "S_1") (pintype "passive"))
      (node (ref "Q6") (pin "2") (pinfunction "S_2") (pintype "passive"))
      (node (ref "Q6") (pin "3") (pinfunction "S_3") (pintype "passive"))
      (node (ref "Q7") (pin "1") (pinfunction "S_1") (pintype "passive"))
      (node (ref "Q7") (pin "2") (pinfunction "S_2") (pintype "passive"))
      (node (ref "Q7") (pin "3") (pinfunction "S_3") (pintype "passive"))
      (node (ref "Q8") (pin "1") (pinfunction "S_1") (pintype "passive"))
      (node (ref "Q8") (pin "2") (pinfunction "S_2") (pintype "passive"))
      (node (ref "Q8") (pin "3") (pinfunction "S_3") (pintype "passive"))
      (node (ref "U11") (pin "4") (pinfunction "GND_4") (pintype "passive"))
      (node (ref "U11") (pin "9") (pinfunction "EP_9") (pintype "passive"))
      (node (ref "U12") (pin "4") (pinfunction "GND_4") (pintype "passive"))
      (node (ref "U12") (pin "9") (pinfunction "EP_9") (pintype "passive"))
      (node (ref "U15") (pin "4") (pinfunction "GND_4") (pintype "passive"))
      (node (ref "U15") (pin "9") (pinfunction "EP_9") (pintype "passive"))
      (node (ref "U16") (pin "4") (pinfunction "GND_4") (pintype "passive"))
      (node (ref "U16") (pin "9") (pinfunction "EP_9") (pintype "passive"))
      (node (ref "U19") (pin "4") (pinfunction "GND_4") (pintype "passive"))
      (node (ref "U19") (pin "9") (pinfunction "EP_9") (pintype "passive"))
      (node (ref "U20") (pin "4") (pinfunction "GND_4") (pintype "passive"))
      (node (ref "U20") (pin "9") (pinfunction "EP_9") (pintype "passive"))
      (node (ref "U23") (pin "4") (pinfunction "GND_4") (pintype "passive"))
      (node (ref "U23") (pin "9") (pinfunction "EP_9") (pintype "passive"))
      (node (ref "U24") (pin "4") (pinfunction "GND_4") (pintype "passive"))
      (node (ref "U24") (pin "9") (pinfunction "EP_9") (pintype "passive"))
    )
  )
)
